# core.net
KiCad netlist of a schematic drawn in EAGLE
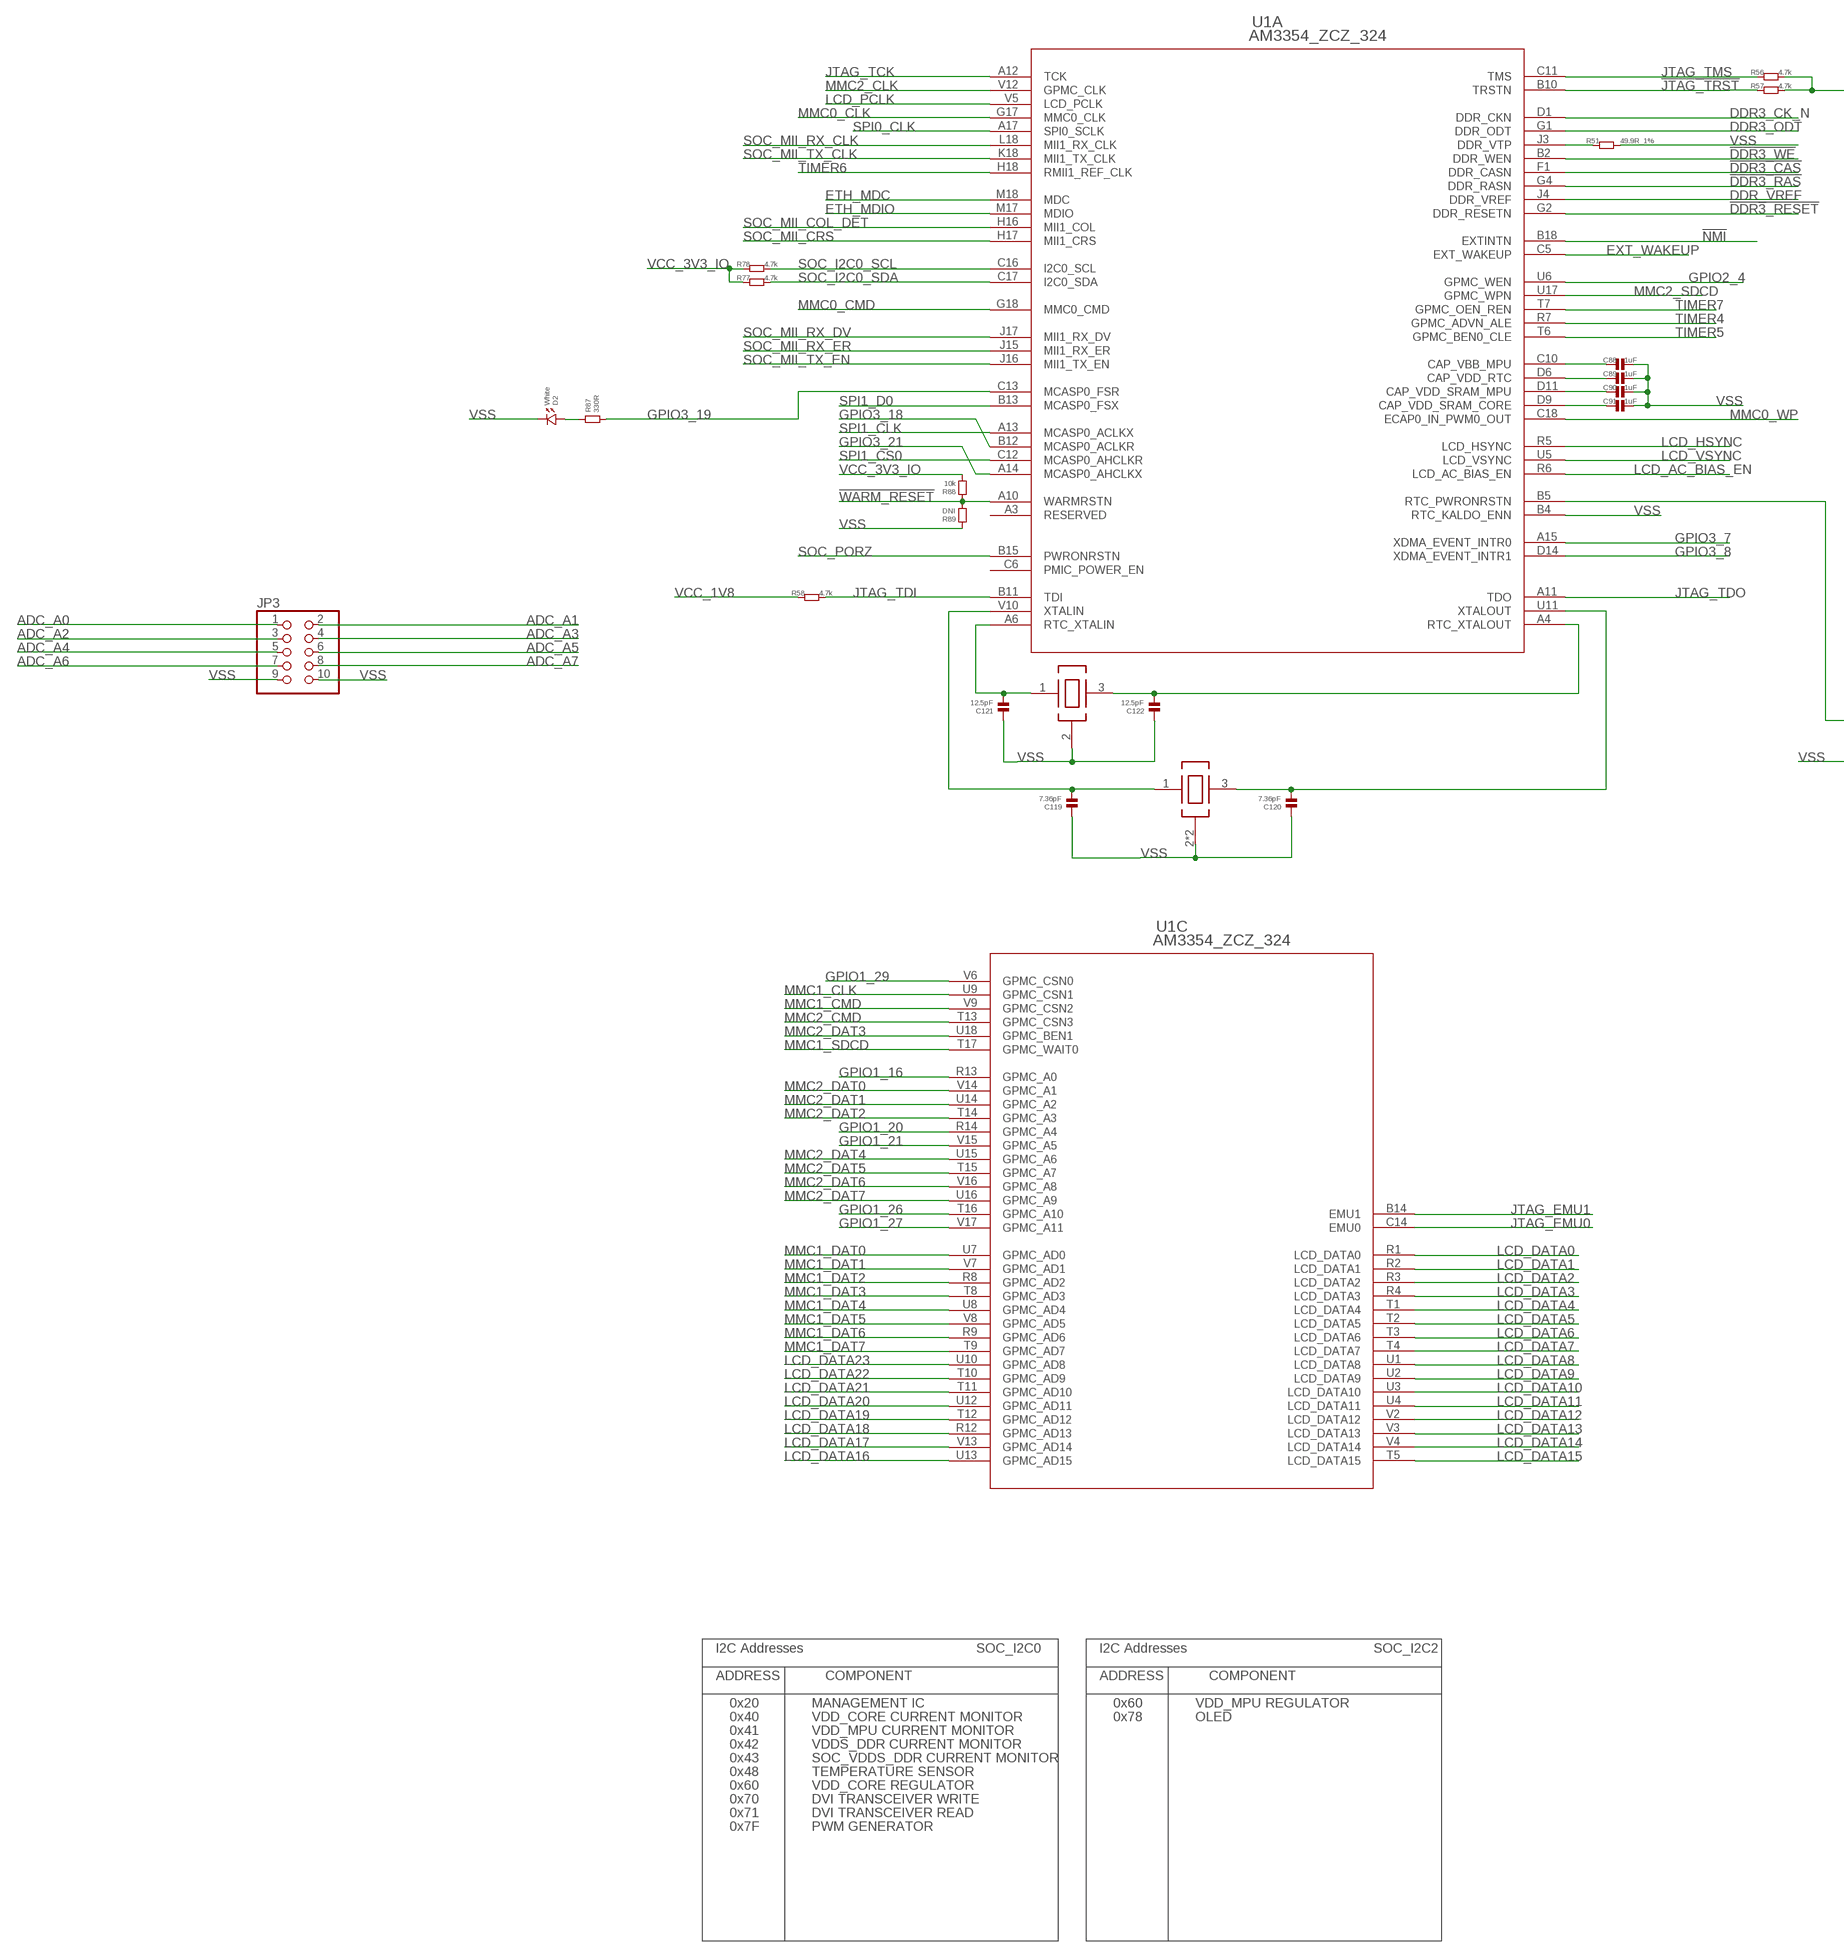
[diagram p0: schematic, sheet 1, part 1 of 2]
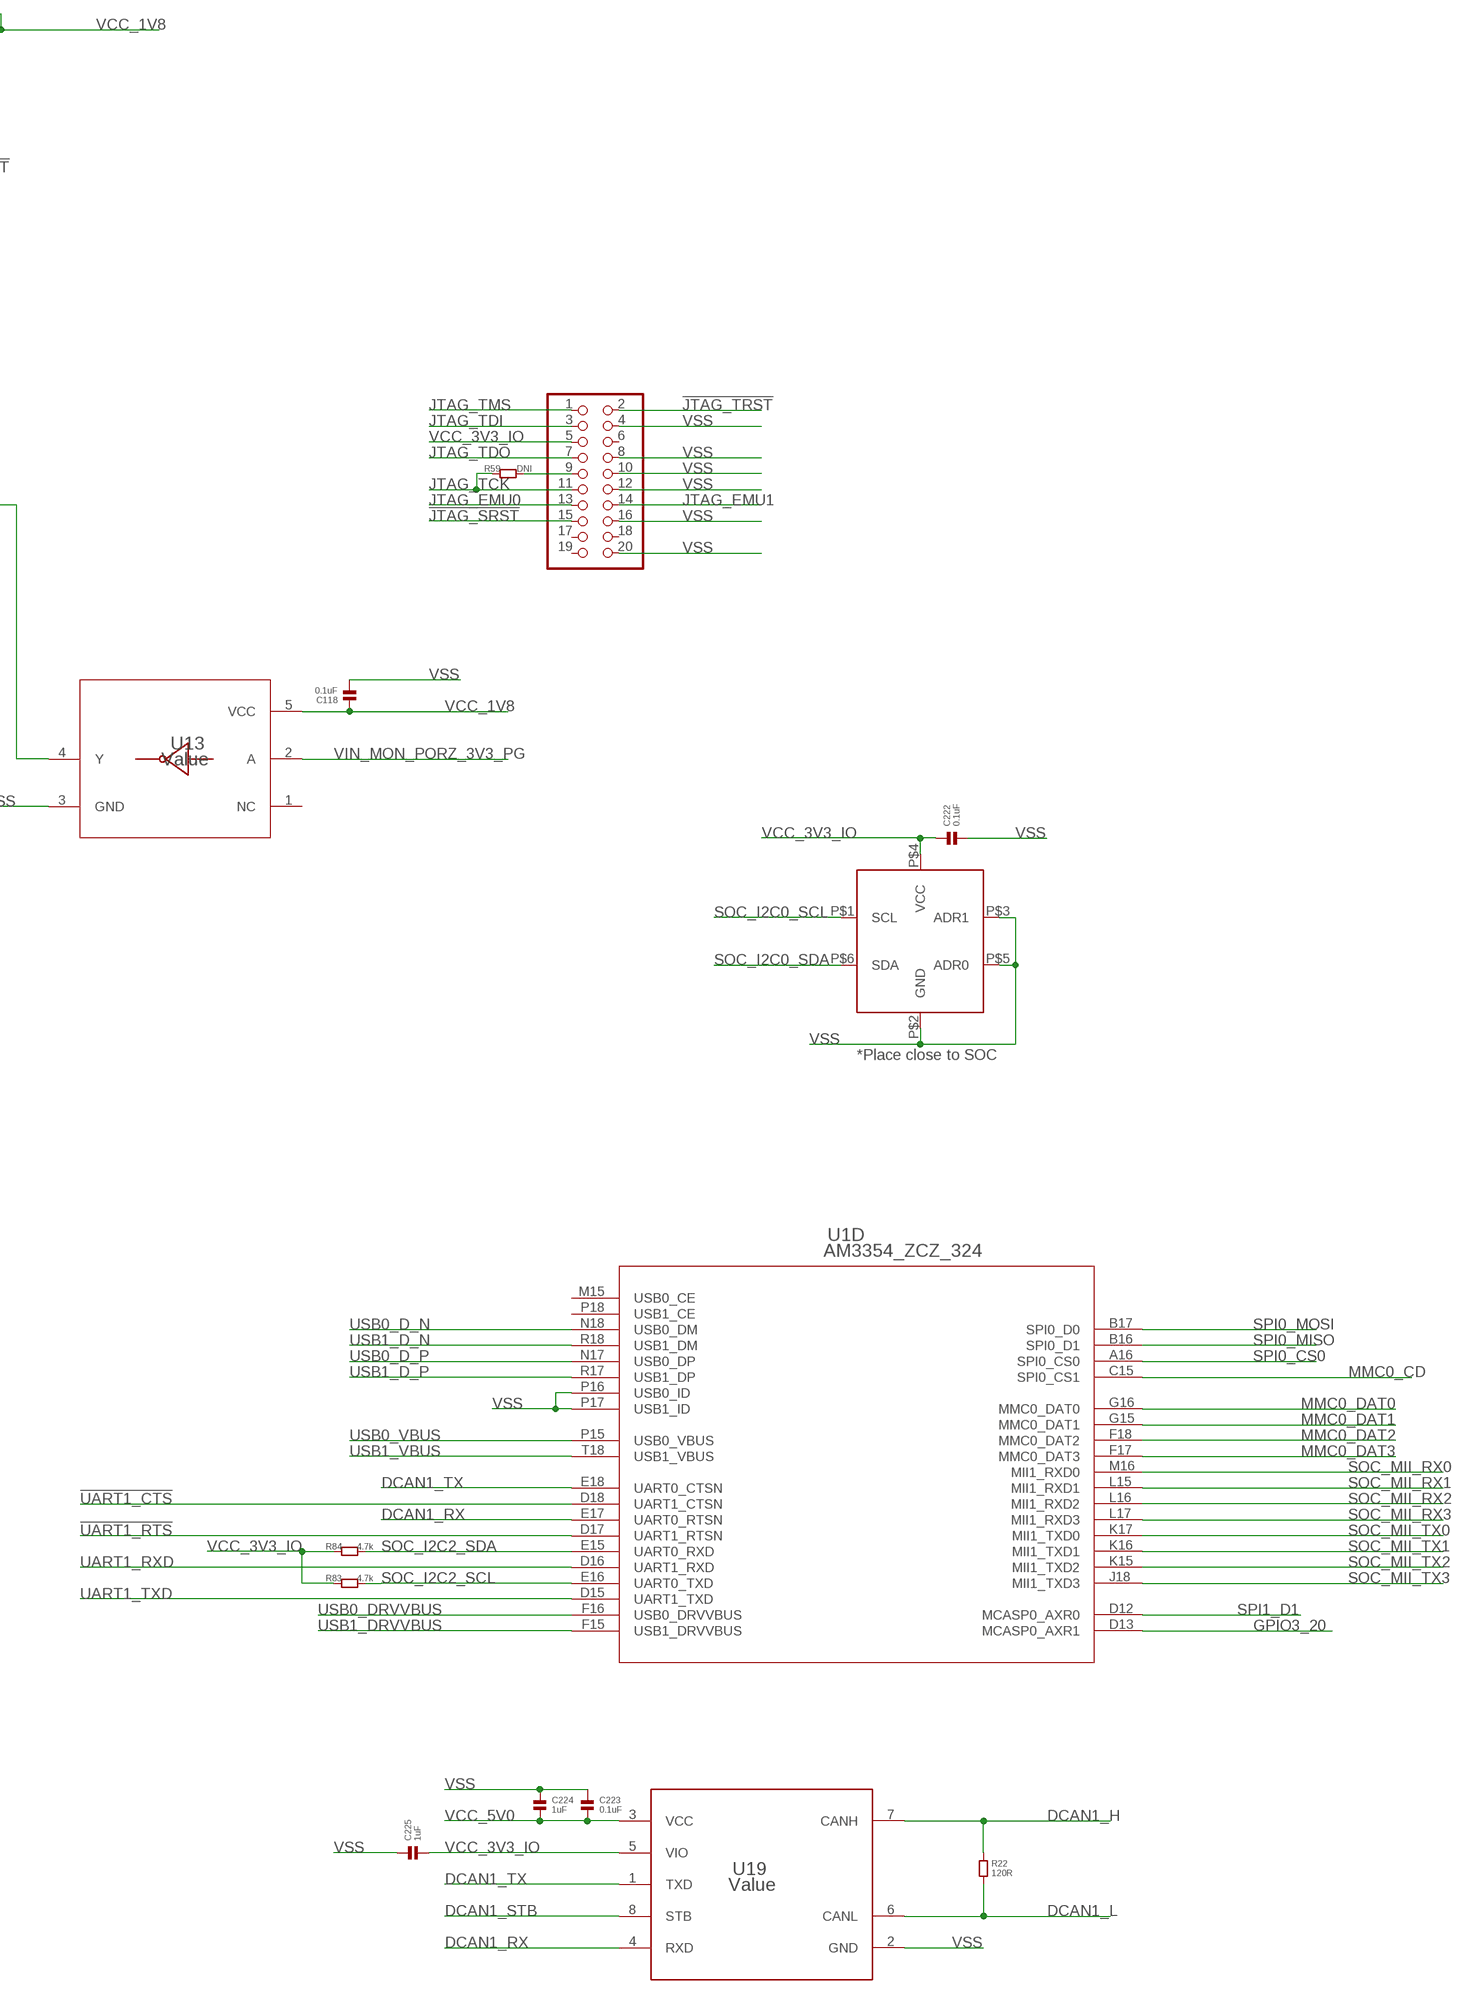
[diagram p1: schematic, sheet 1, part 2 of 2]
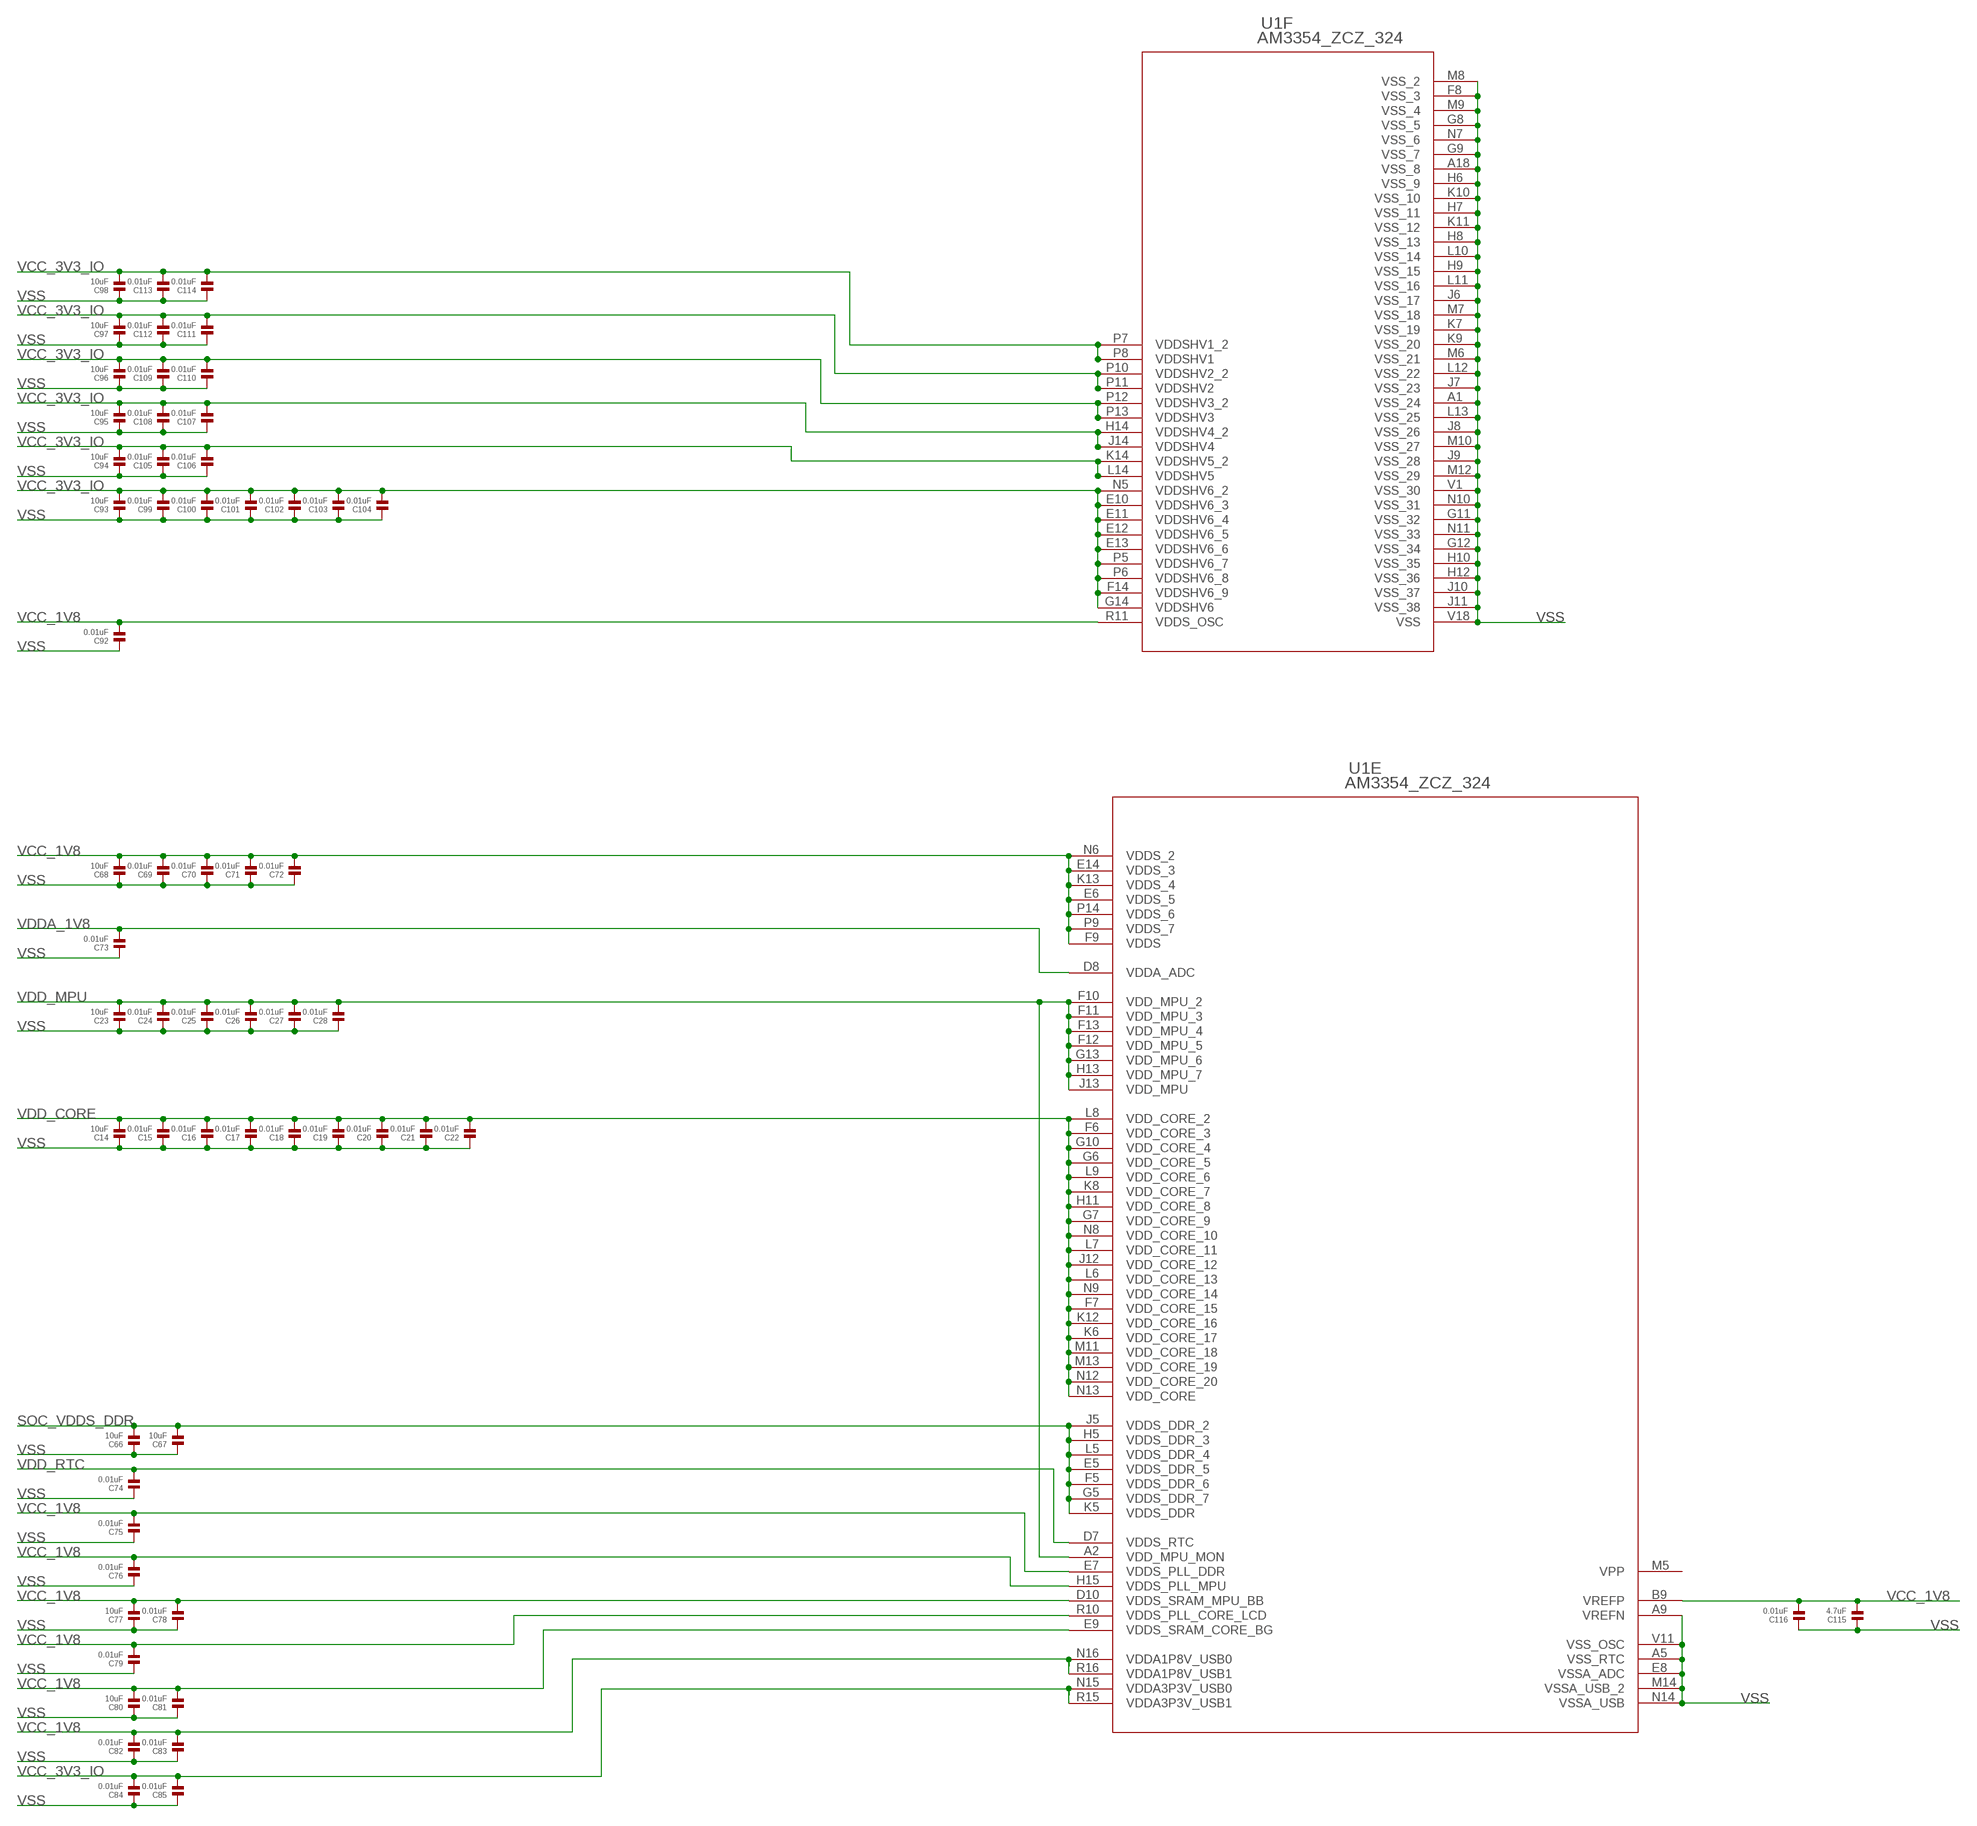
[diagram p2: schematic, sheet 2]
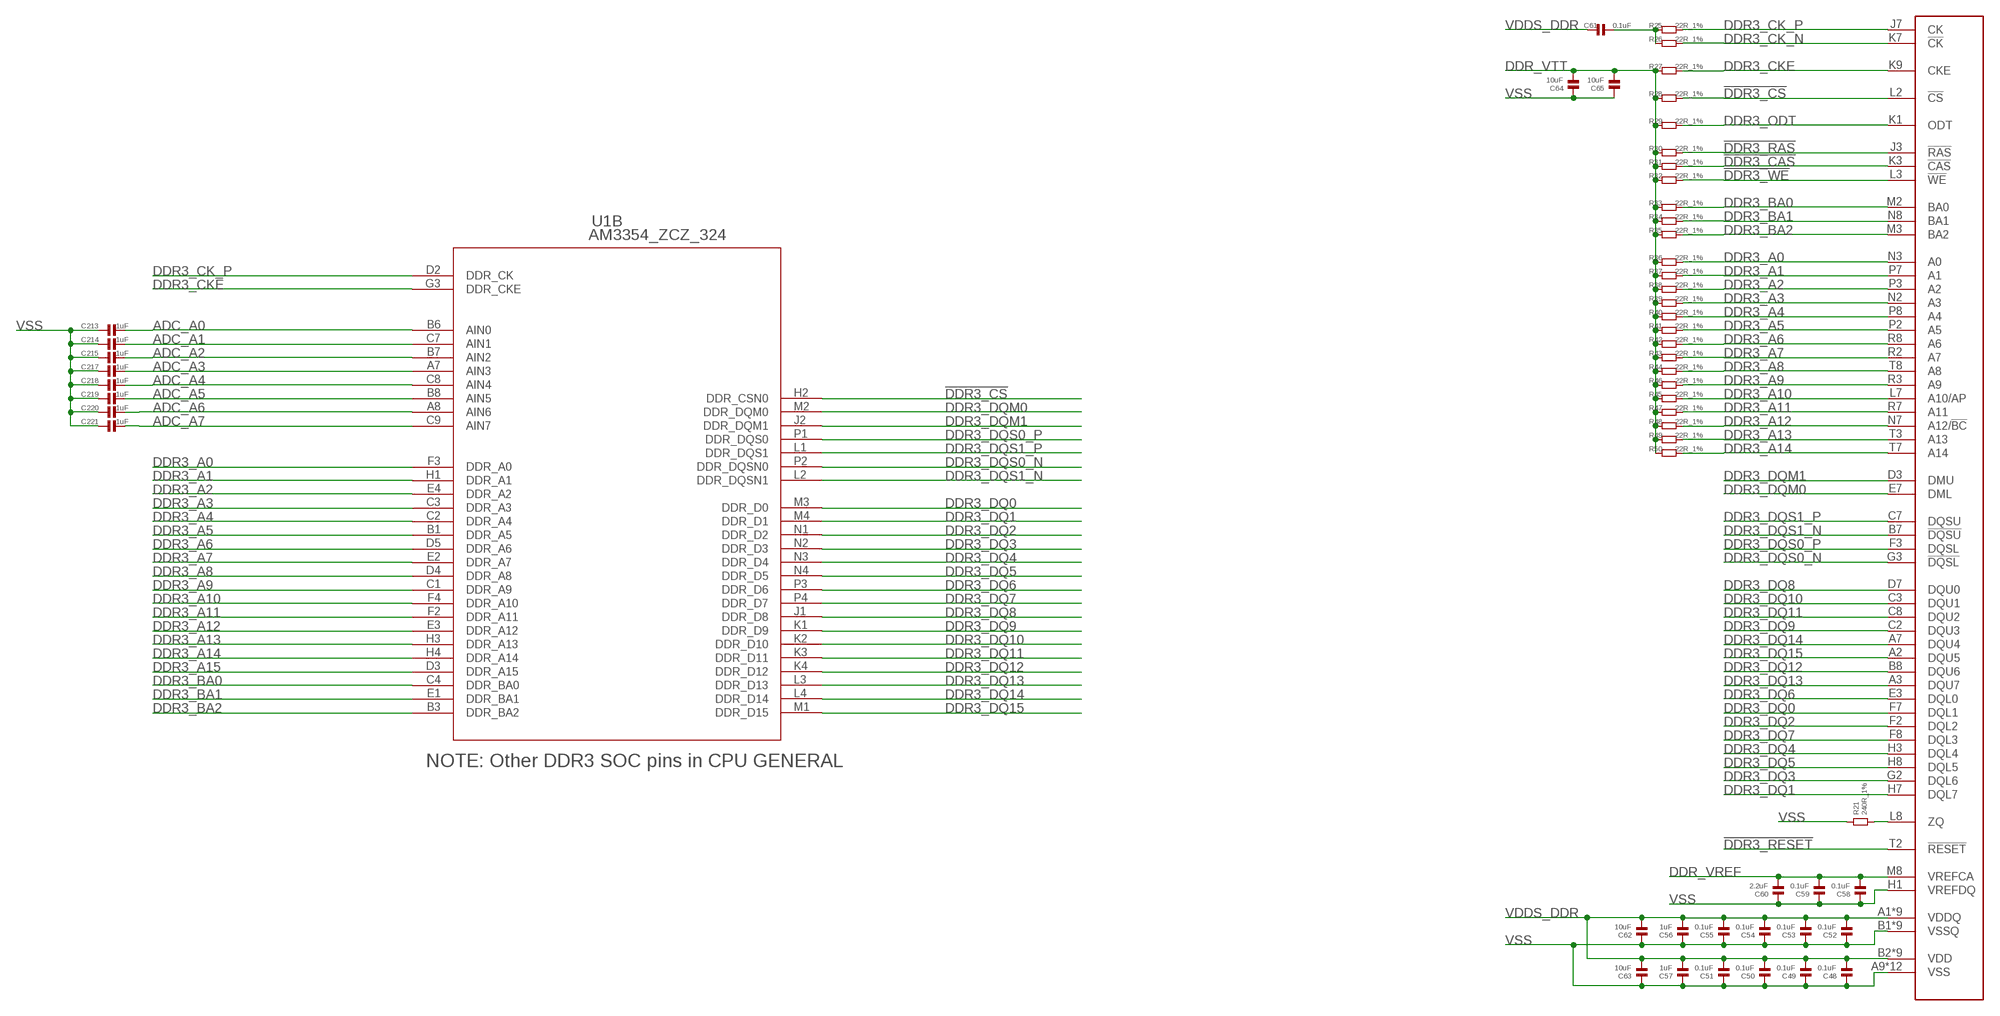
[diagram p3: schematic, sheet 3]
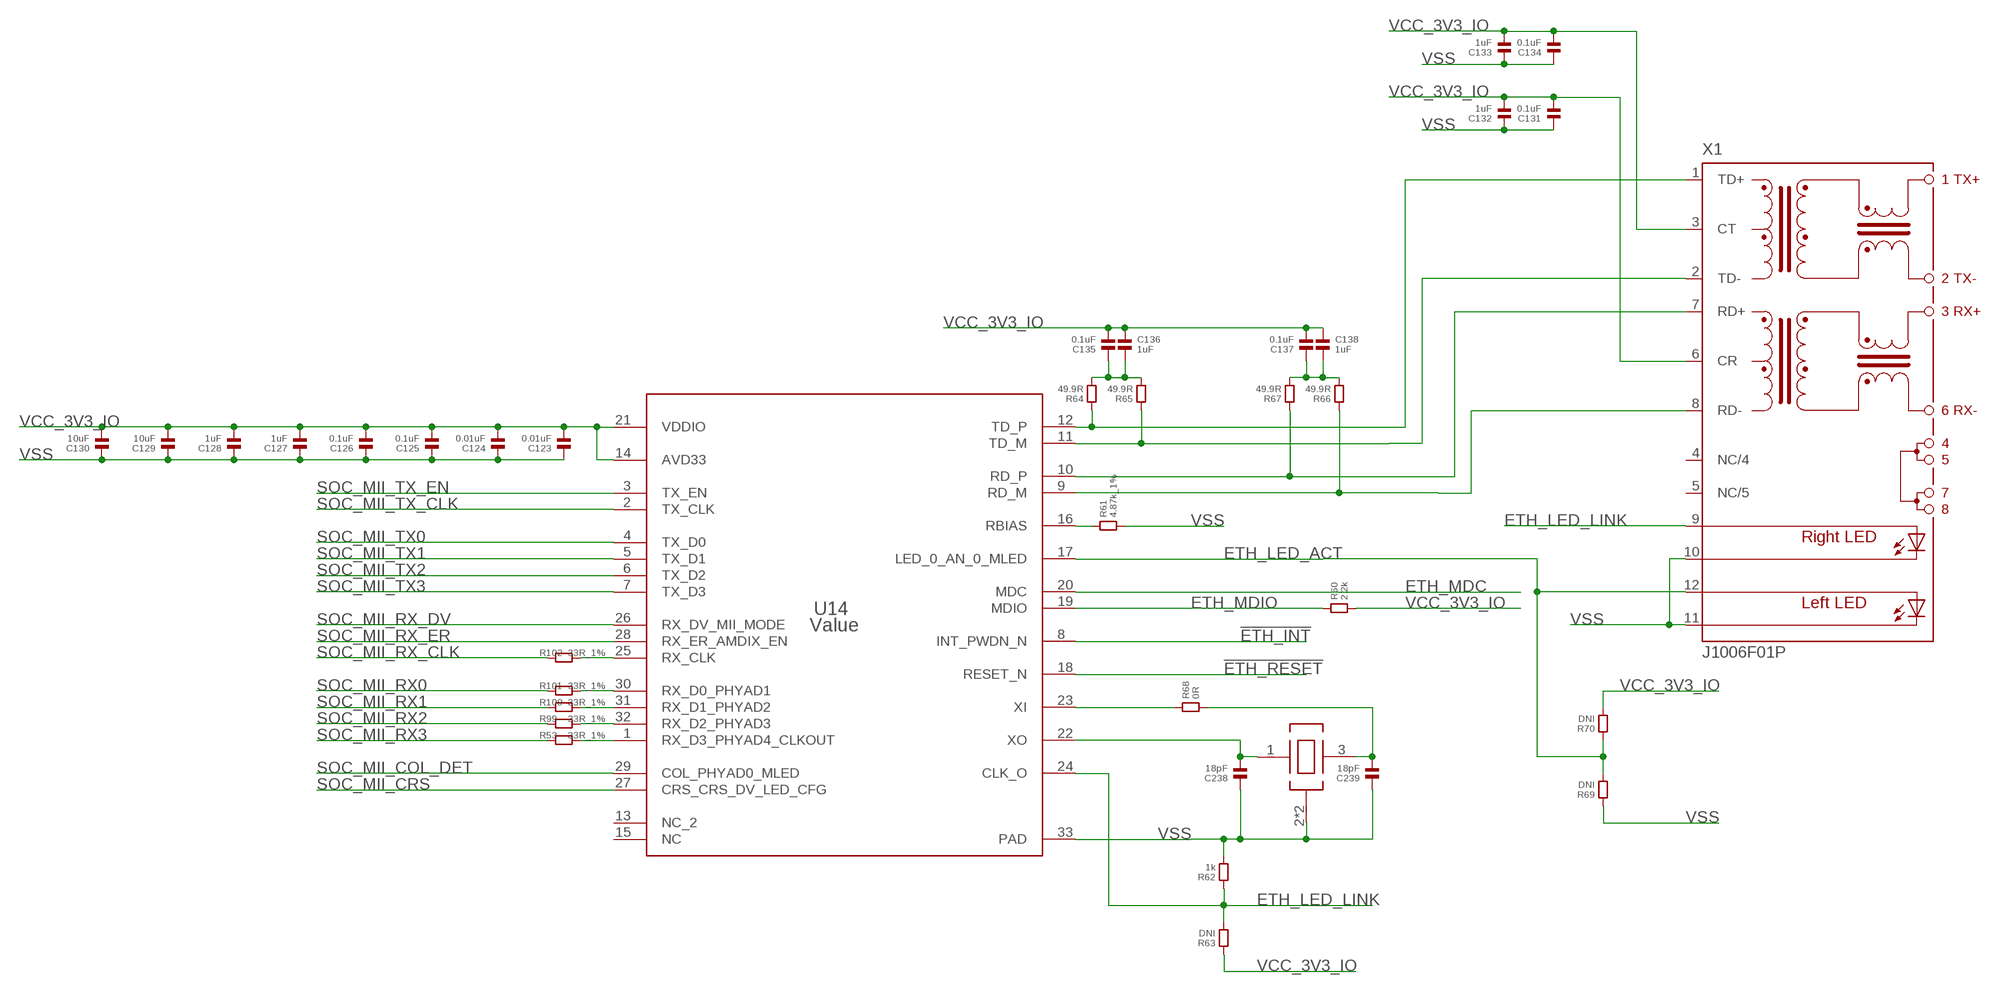
[diagram p4: schematic, sheet 4]
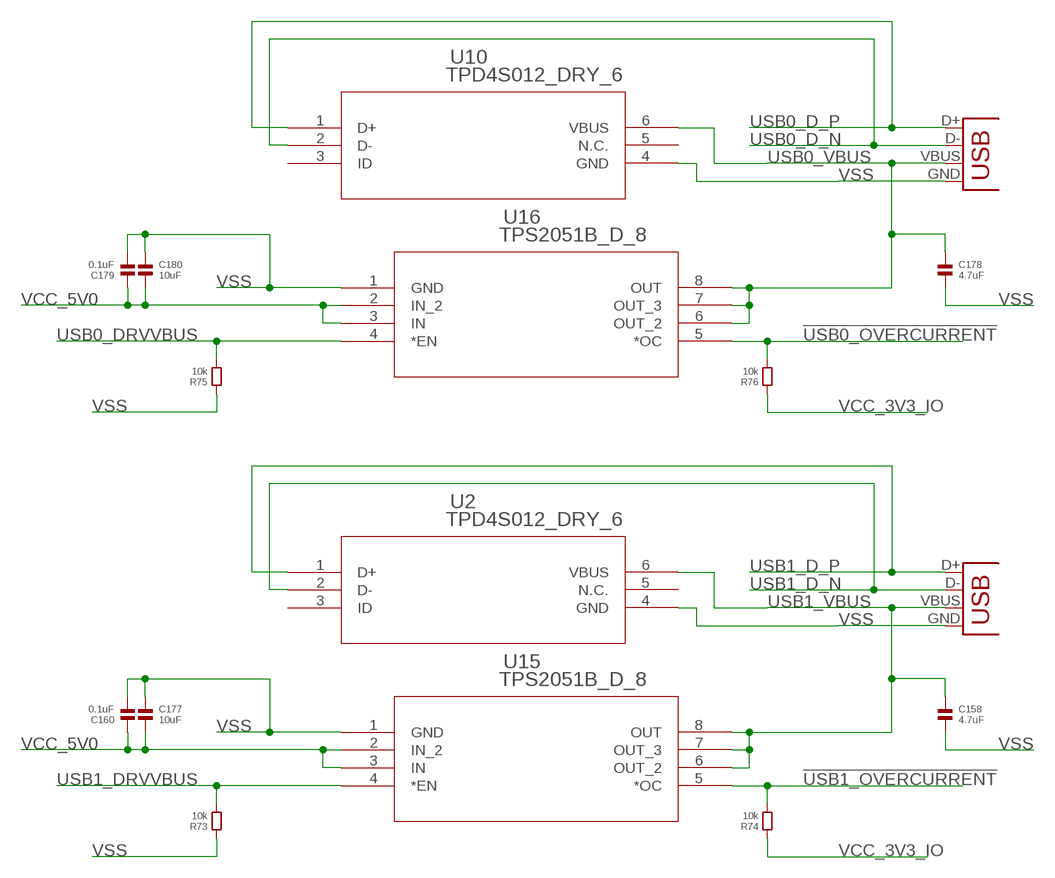
[diagram p5: schematic, sheet 5]
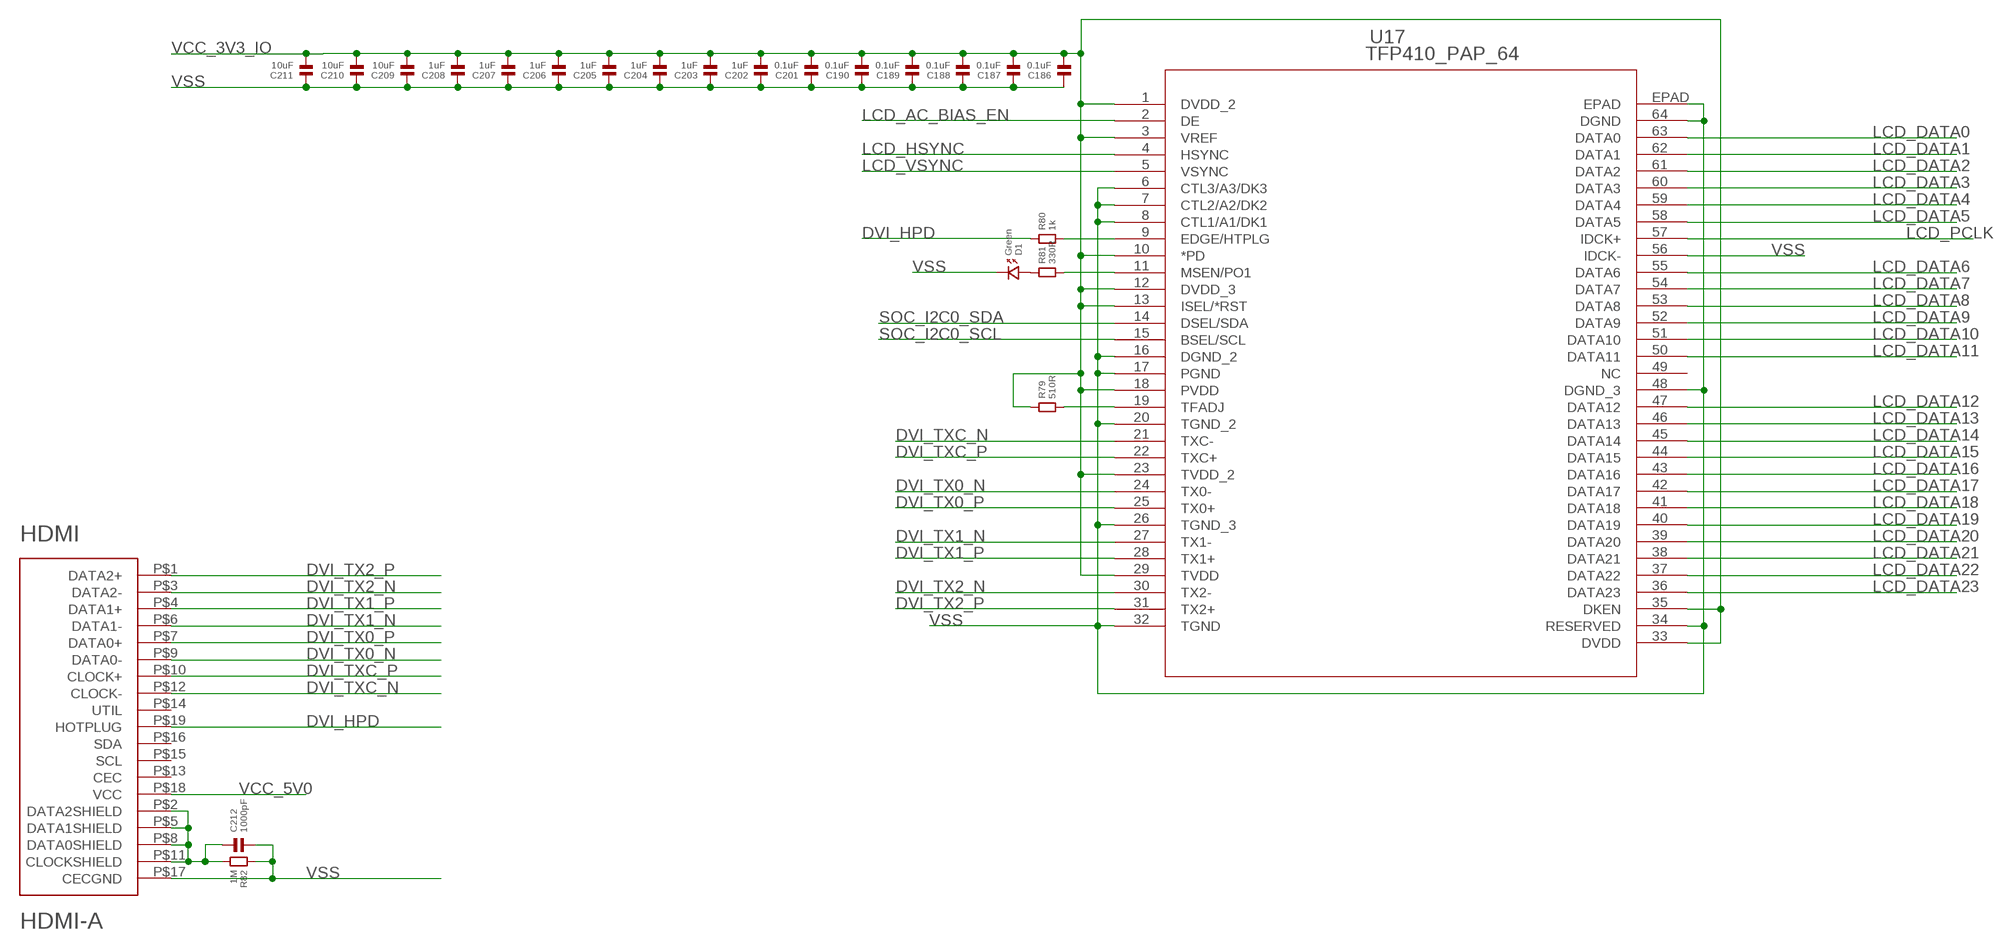
[diagram p6: schematic, sheet 6]
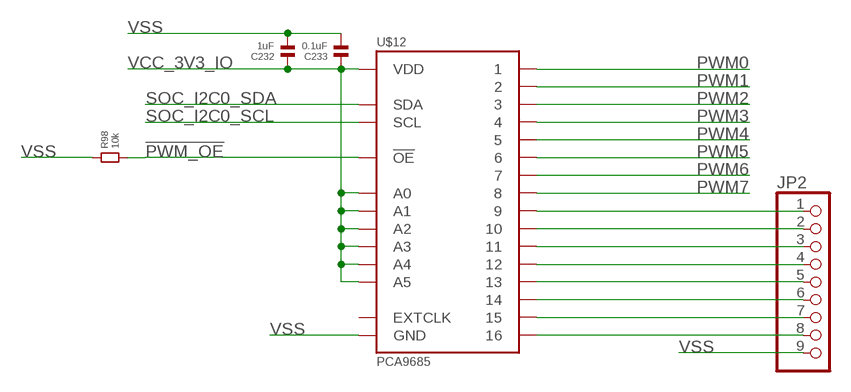
[diagram p7: schematic, sheet 7]
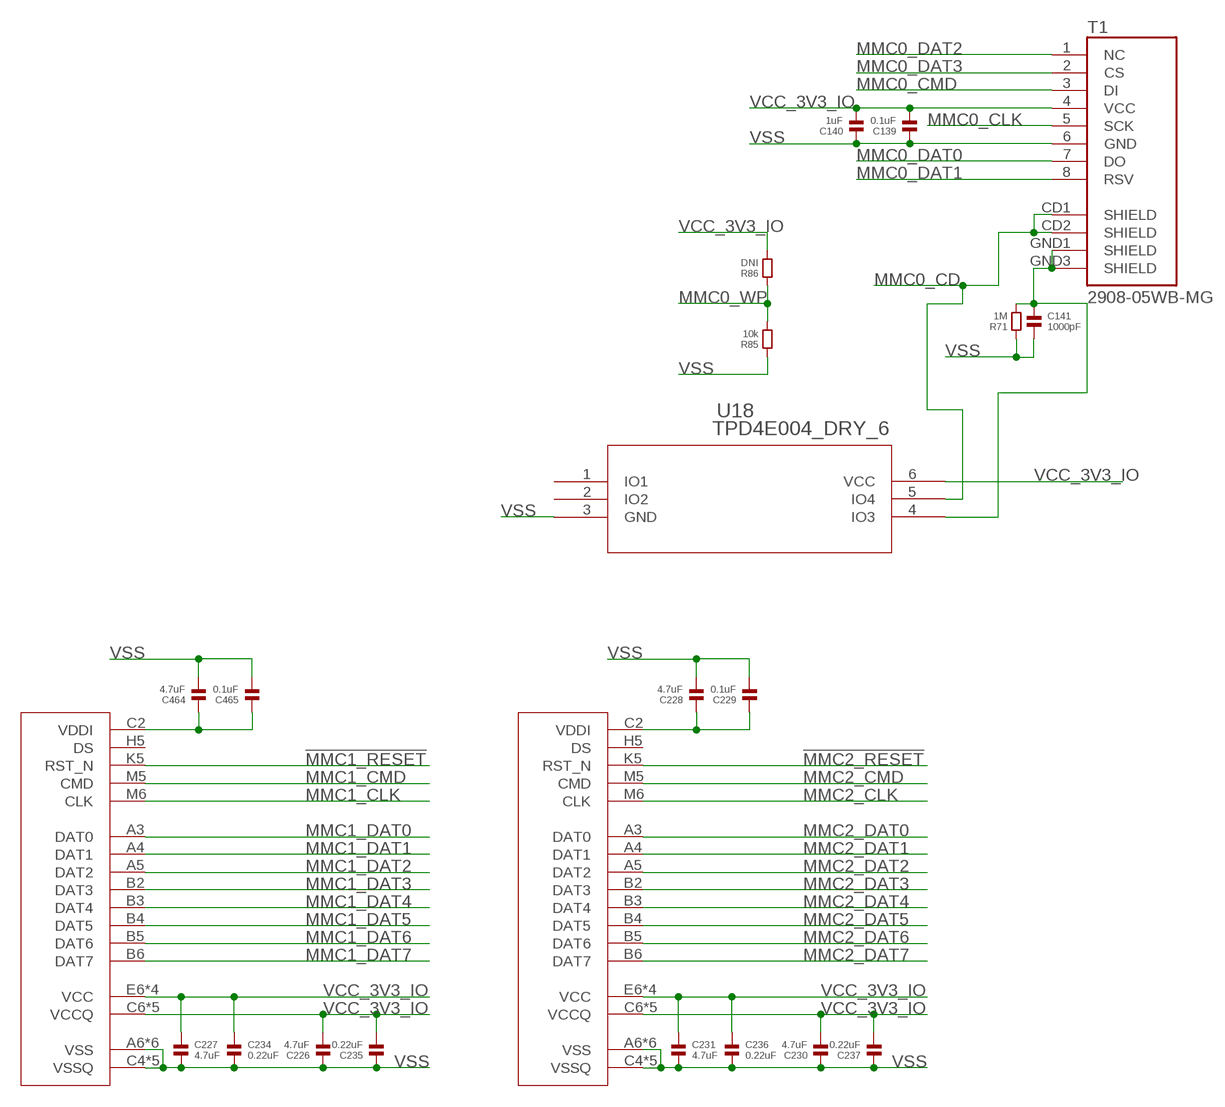
[diagram p8: schematic, sheet 8]
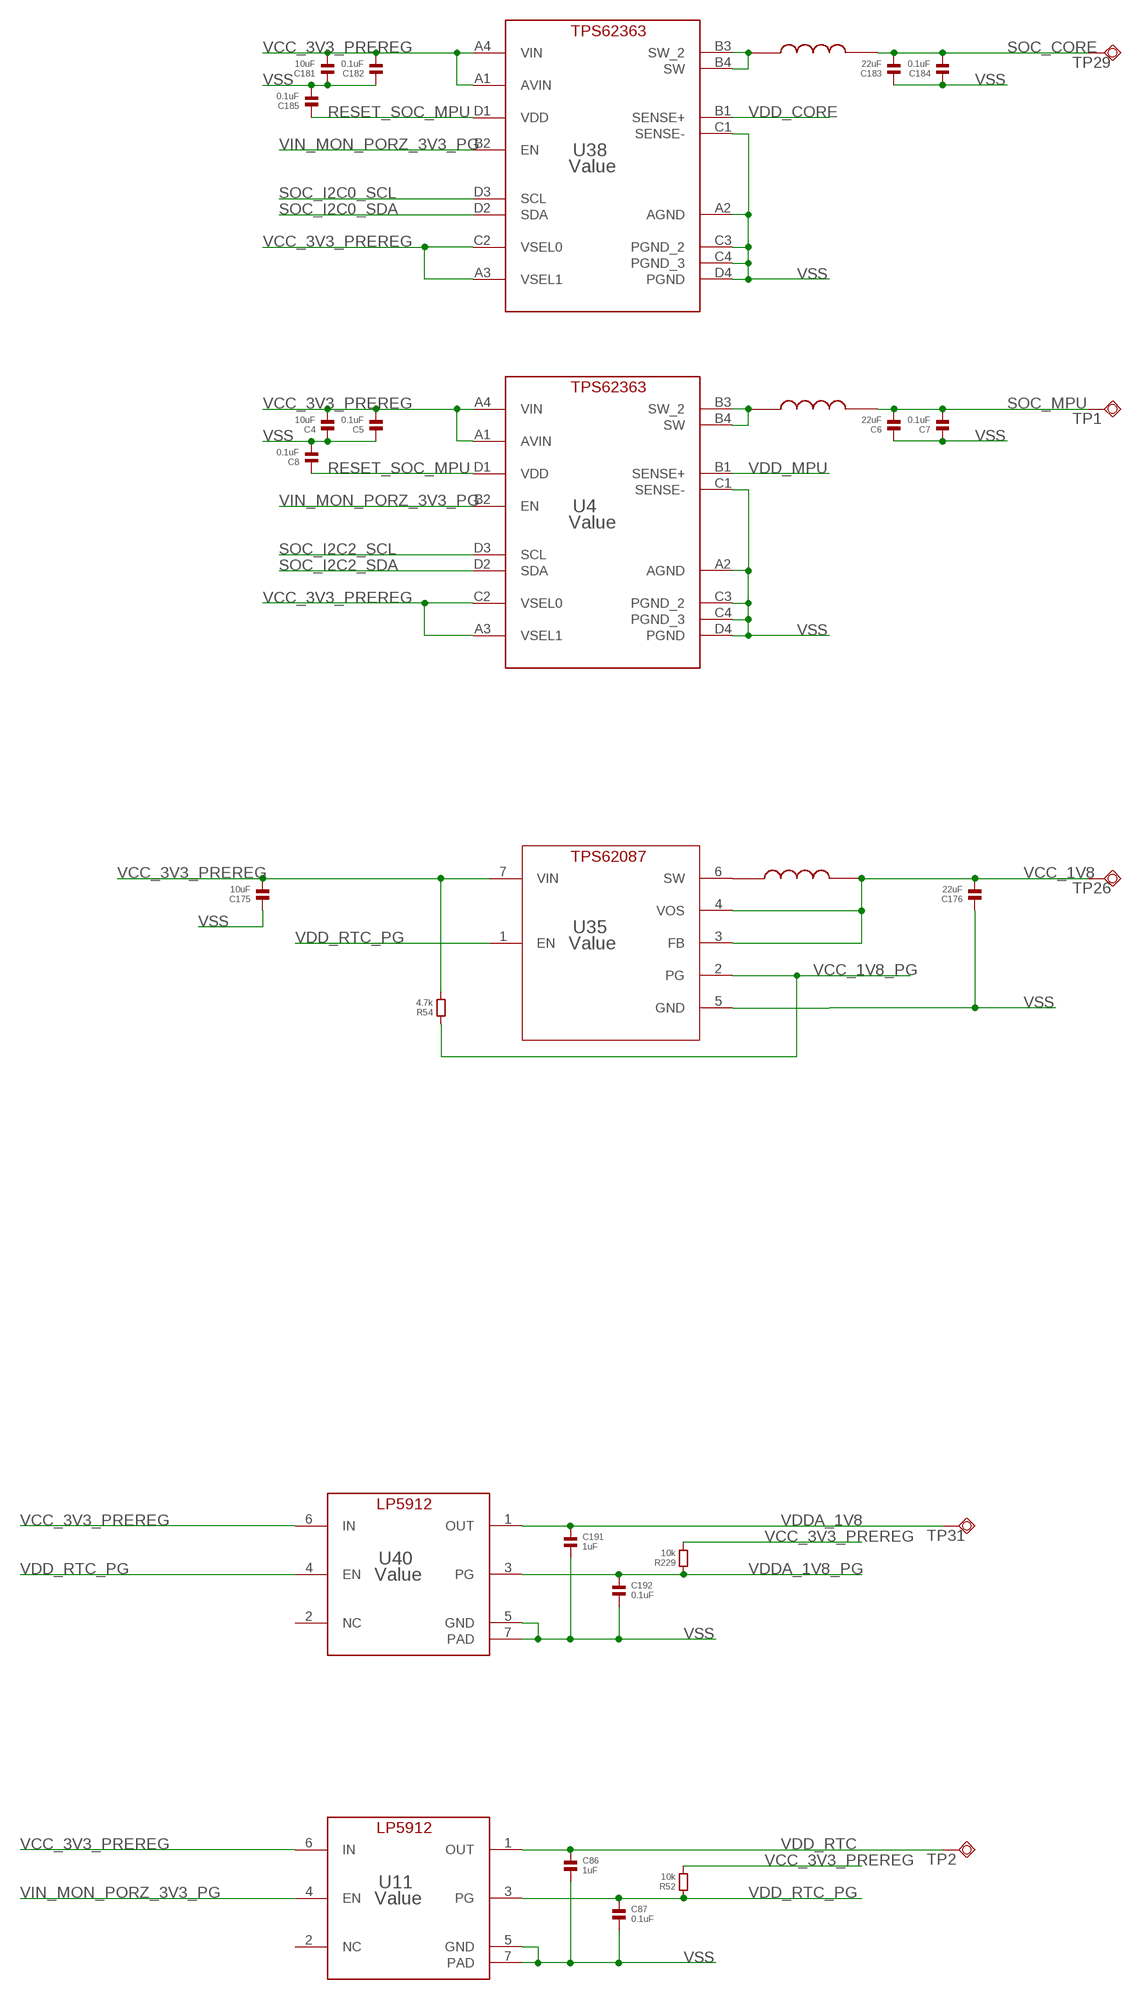
[diagram p9: schematic, sheet 9, part 1 of 2]
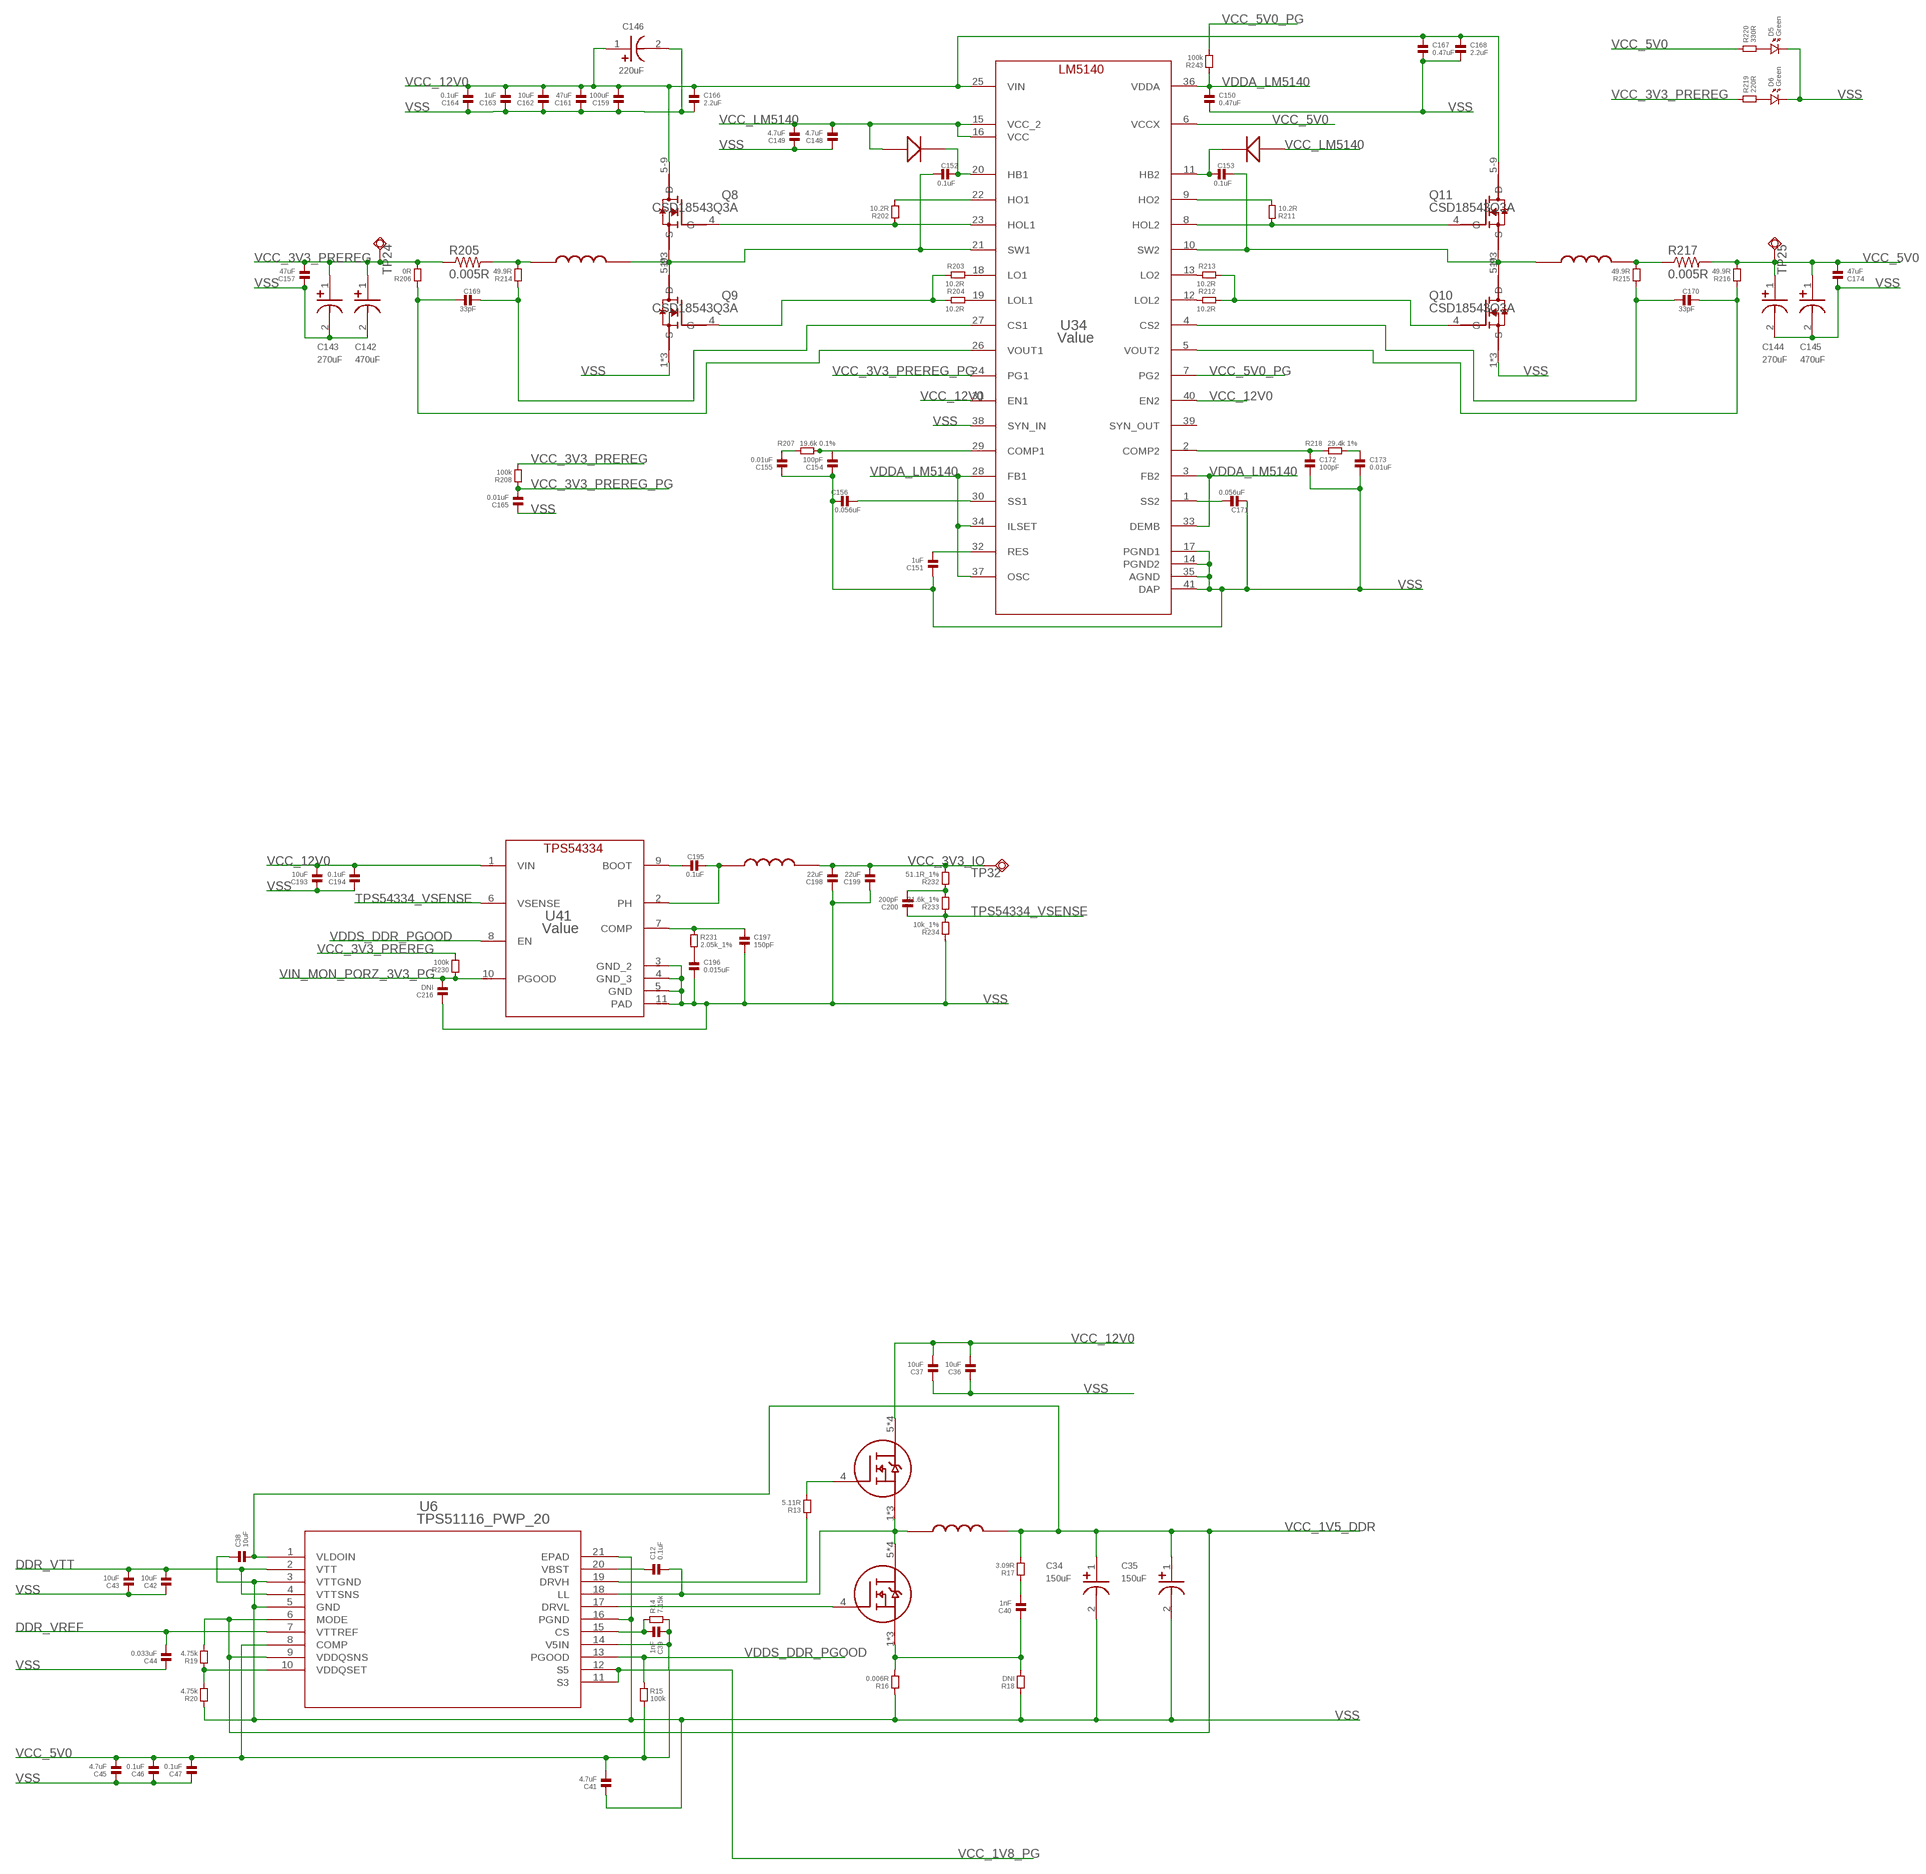
[diagram p10: schematic, sheet 9, part 2 of 2]
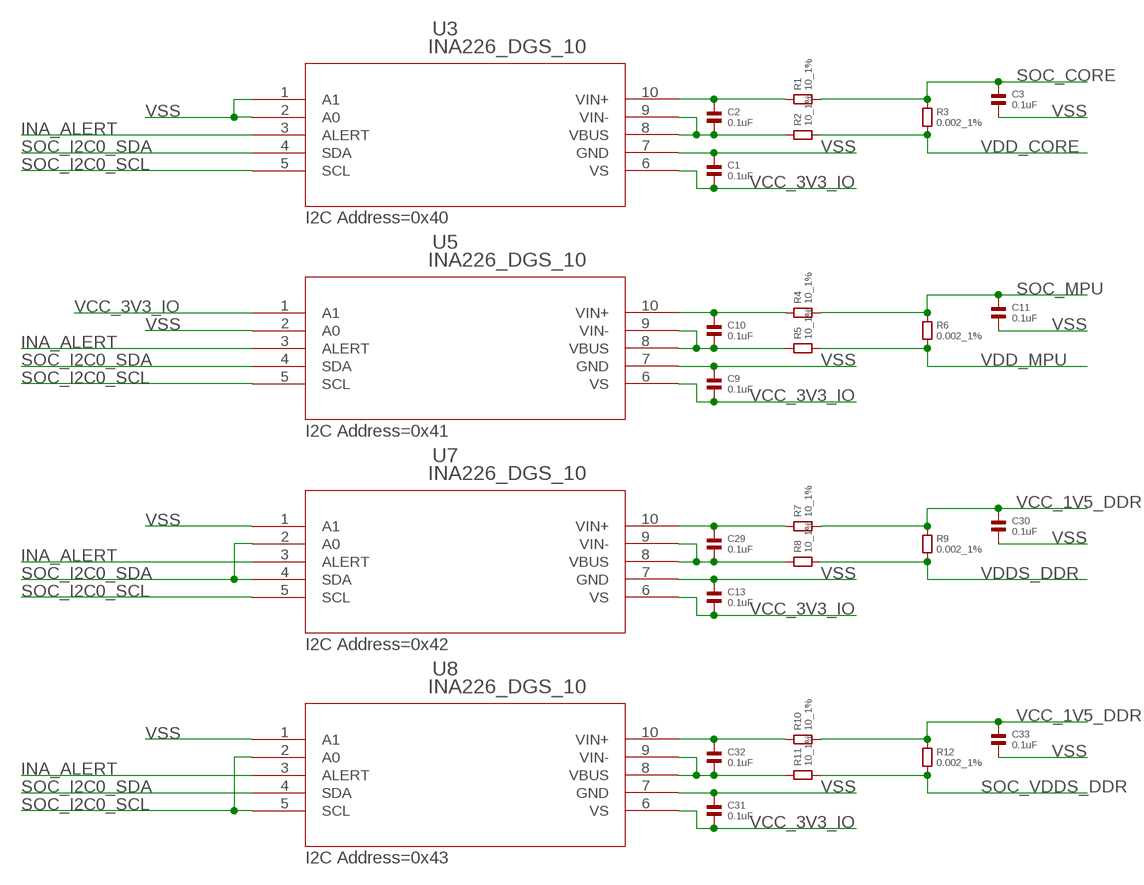
[diagram p11: schematic, sheet 10]
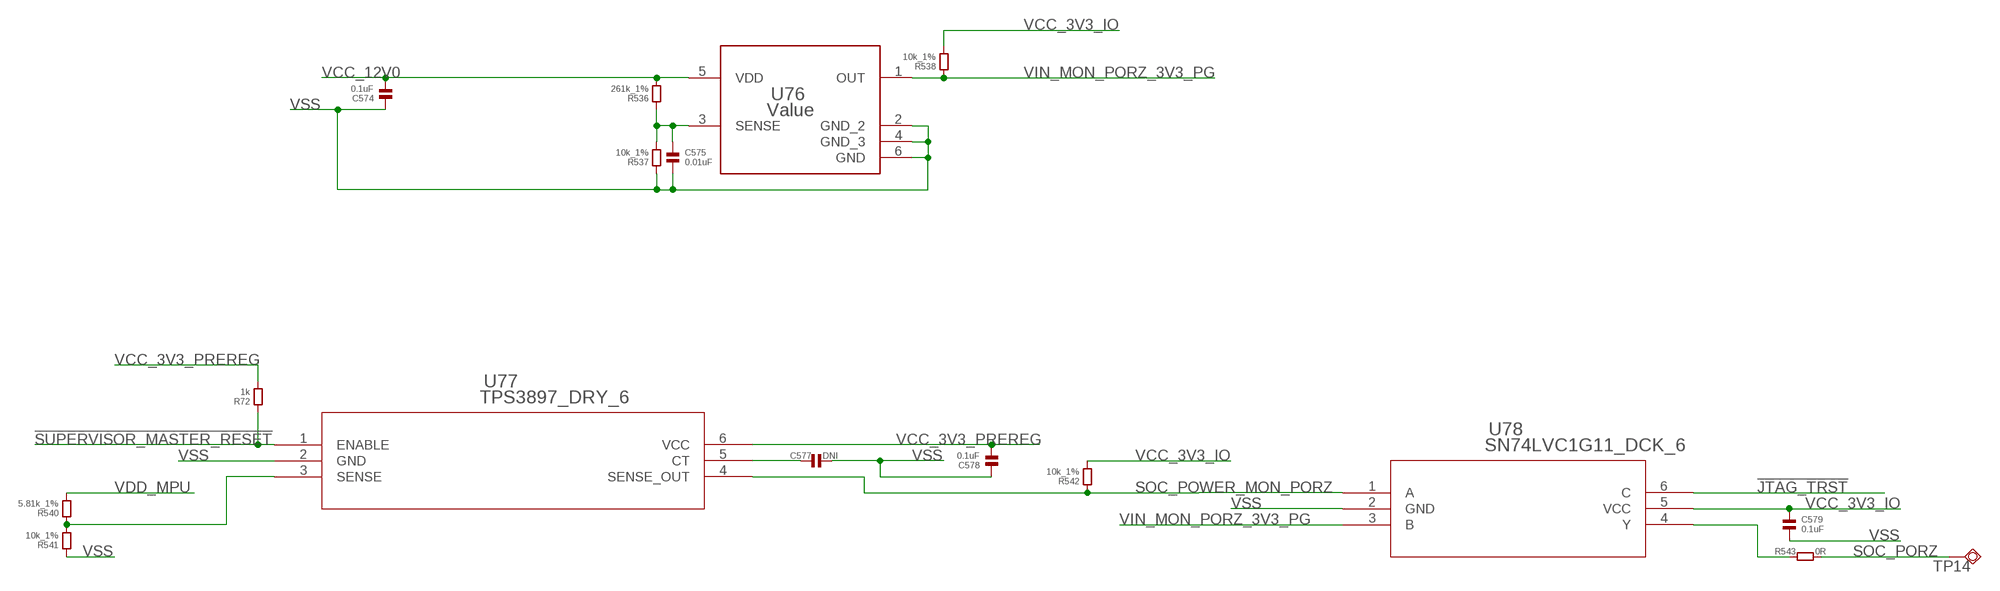
[diagram p12: schematic, sheet 11]
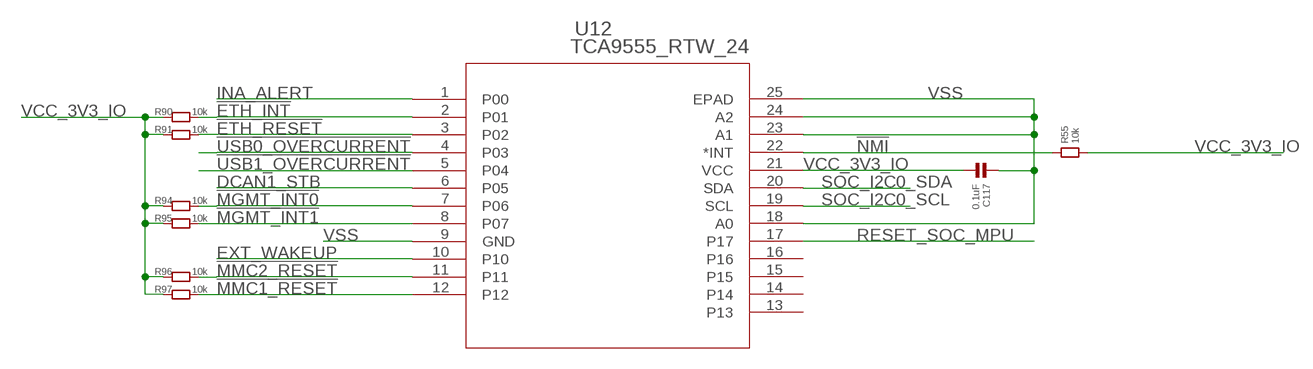
[diagram p13: schematic, sheet 12]
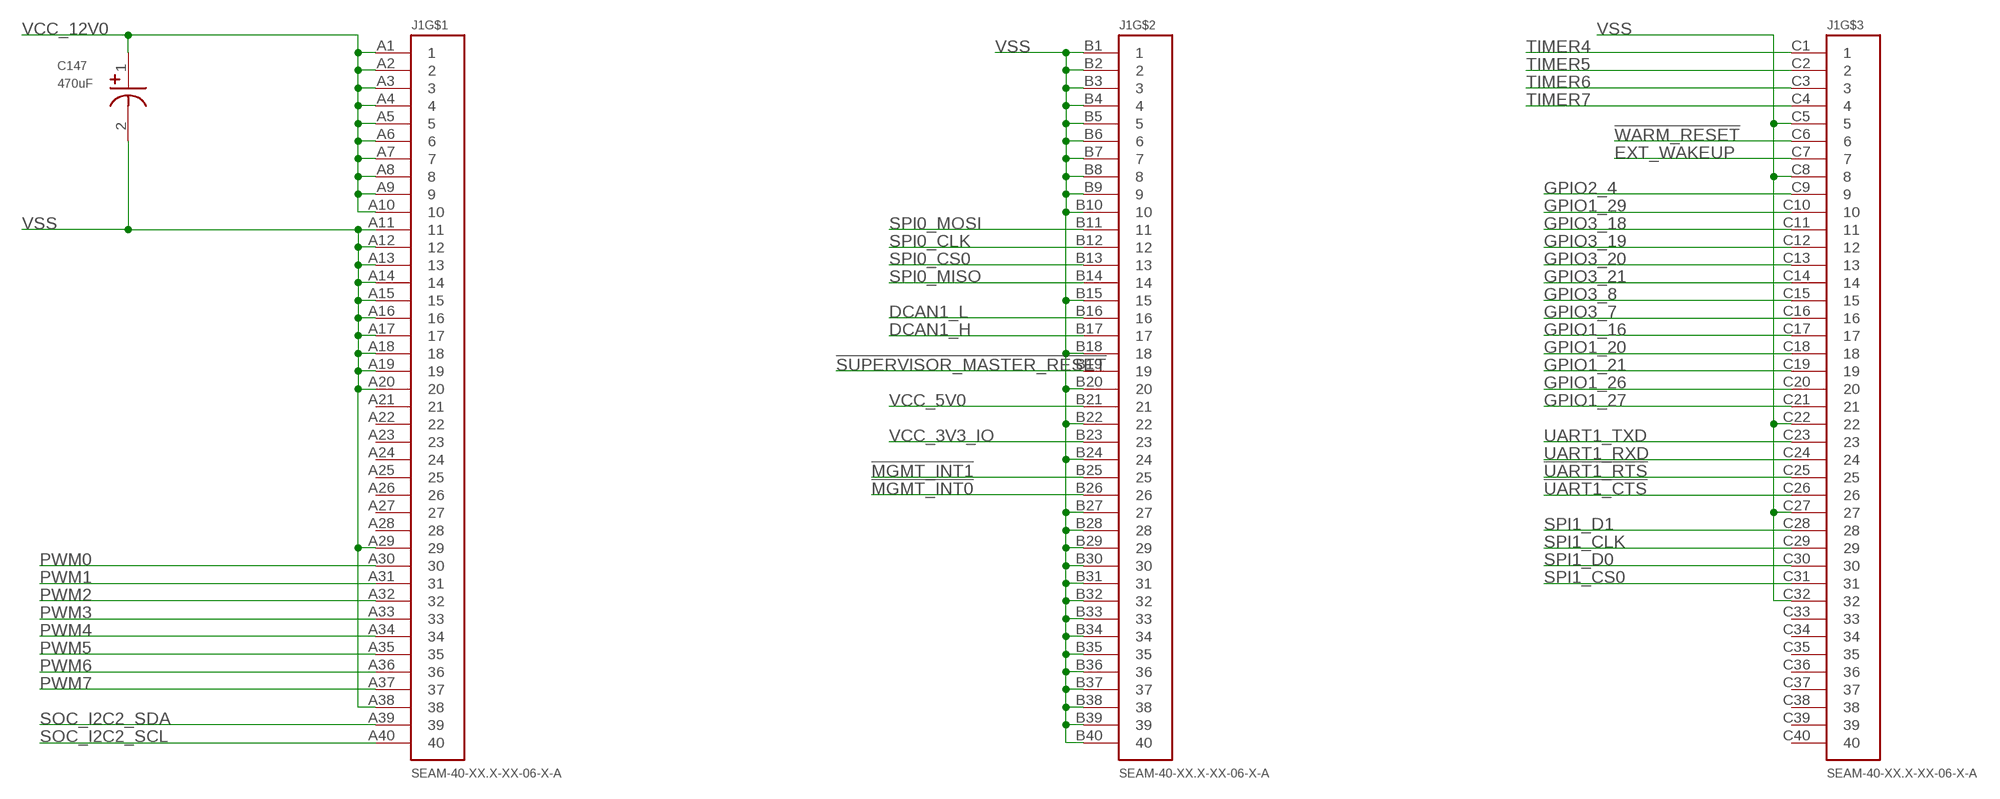
[diagram p14: schematic, sheet 13, part 1 of 2]
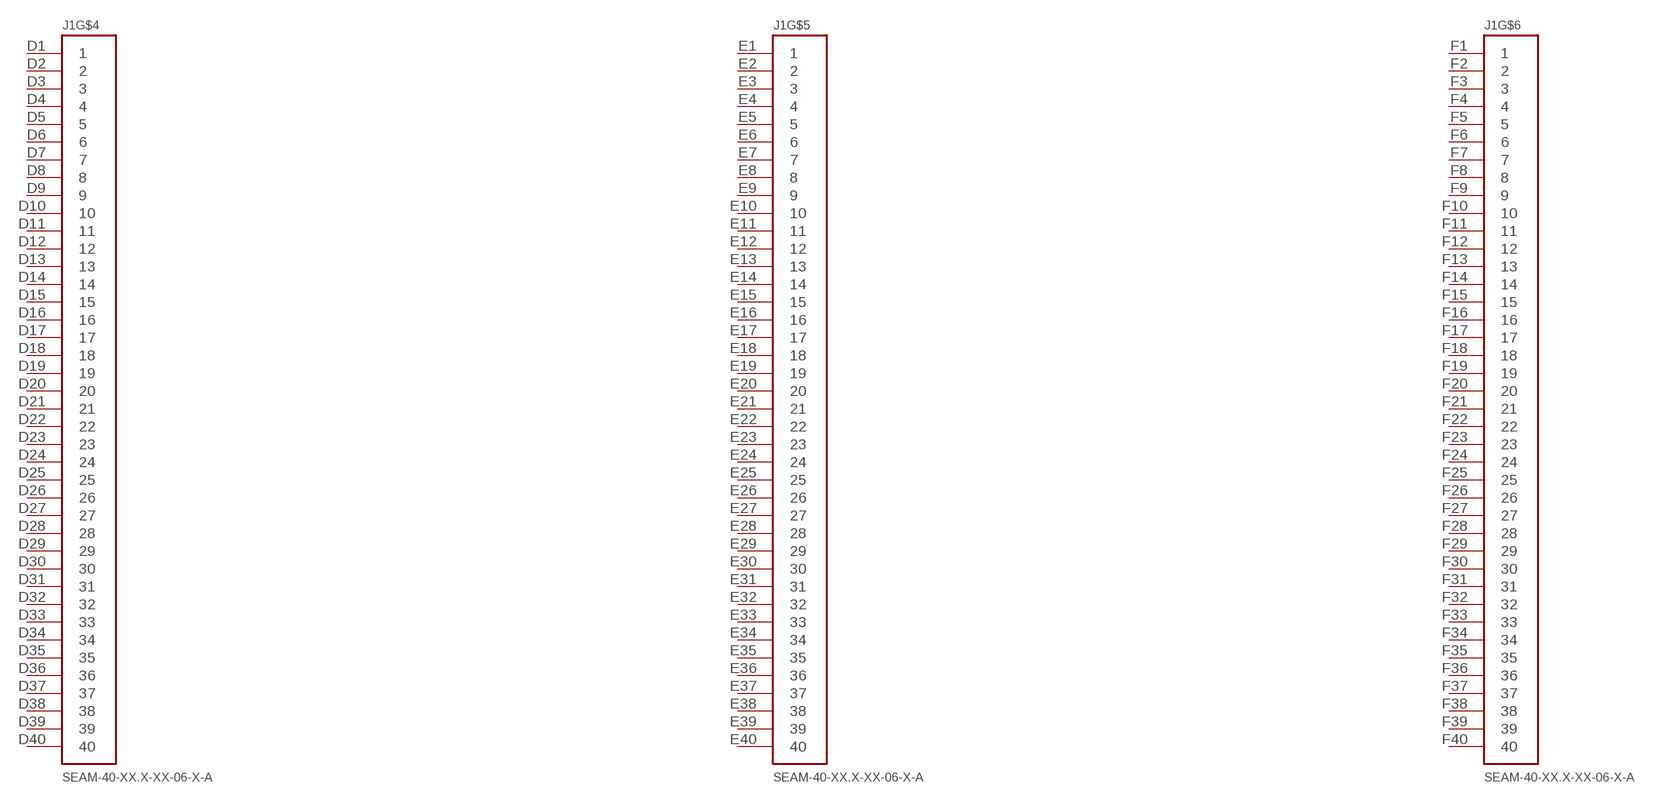
[diagram p15: schematic, sheet 13, part 2 of 2]

(export (version "E")
  (design (tool "Eeschema 10.0.6"))
  (components
    (comp (ref "C14")
      (value "10uF")
      (footprint "eagle-import:0402")
      (libsource (lib "eagle-import") (part "CAPACITOR.0402"))
    )
    (comp (ref "C15")
      (value "0.01uF")
      (footprint "eagle-import:0201")
      (libsource (lib "eagle-import") (part "CAPACITOR.0201"))
    )
    (comp (ref "C16")
      (value "0.01uF")
      (footprint "eagle-import:0201")
      (libsource (lib "eagle-import") (part "CAPACITOR.0201"))
    )
    (comp (ref "C17")
      (value "0.01uF")
      (footprint "eagle-import:0201")
      (libsource (lib "eagle-import") (part "CAPACITOR.0201"))
    )
    (comp (ref "C18")
      (value "0.01uF")
      (footprint "eagle-import:0201")
      (libsource (lib "eagle-import") (part "CAPACITOR.0201"))
    )
    (comp (ref "C19")
      (value "0.01uF")
      (footprint "eagle-import:0201")
      (libsource (lib "eagle-import") (part "CAPACITOR.0201"))
    )
    (comp (ref "C20")
      (value "0.01uF")
      (footprint "eagle-import:0201")
      (libsource (lib "eagle-import") (part "CAPACITOR.0201"))
    )
    (comp (ref "C21")
      (value "0.01uF")
      (footprint "eagle-import:0201")
      (libsource (lib "eagle-import") (part "CAPACITOR.0201"))
    )
    (comp (ref "C22")
      (value "0.01uF")
      (footprint "eagle-import:0201")
      (libsource (lib "eagle-import") (part "CAPACITOR.0201"))
    )
    (comp (ref "C23")
      (value "10uF")
      (footprint "eagle-import:0402")
      (libsource (lib "eagle-import") (part "CAPACITOR.0402"))
    )
    (comp (ref "C24")
      (value "0.01uF")
      (footprint "eagle-import:0201")
      (libsource (lib "eagle-import") (part "CAPACITOR.0201"))
    )
    (comp (ref "C25")
      (value "0.01uF")
      (footprint "eagle-import:0201")
      (libsource (lib "eagle-import") (part "CAPACITOR.0201"))
    )
    (comp (ref "C26")
      (value "0.01uF")
      (footprint "eagle-import:0201")
      (libsource (lib "eagle-import") (part "CAPACITOR.0201"))
    )
    (comp (ref "C27")
      (value "0.01uF")
      (footprint "eagle-import:0201")
      (libsource (lib "eagle-import") (part "CAPACITOR.0201"))
    )
    (comp (ref "C28")
      (value "0.01uF")
      (footprint "eagle-import:0201")
      (libsource (lib "eagle-import") (part "CAPACITOR.0201"))
    )
    (comp (ref "C66")
      (value "10uF")
      (footprint "eagle-import:0402")
      (libsource (lib "eagle-import") (part "CAPACITOR.0402"))
    )
    (comp (ref "C67")
      (value "10uF")
      (footprint "eagle-import:0402")
      (libsource (lib "eagle-import") (part "CAPACITOR.0402"))
    )
    (comp (ref "C68")
      (value "10uF")
      (footprint "eagle-import:0402")
      (libsource (lib "eagle-import") (part "CAPACITOR.0402"))
    )
    (comp (ref "C69")
      (value "0.01uF")
      (footprint "eagle-import:0201")
      (libsource (lib "eagle-import") (part "CAPACITOR.0201"))
    )
    (comp (ref "C70")
      (value "0.01uF")
      (footprint "eagle-import:0201")
      (libsource (lib "eagle-import") (part "CAPACITOR.0201"))
    )
    (comp (ref "C71")
      (value "0.01uF")
      (footprint "eagle-import:0201")
      (libsource (lib "eagle-import") (part "CAPACITOR.0201"))
    )
    (comp (ref "C72")
      (value "0.01uF")
      (footprint "eagle-import:0201")
      (libsource (lib "eagle-import") (part "CAPACITOR.0201"))
    )
    (comp (ref "C73")
      (value "0.01uF")
      (footprint "eagle-import:0201")
      (libsource (lib "eagle-import") (part "CAPACITOR.0201"))
    )
    (comp (ref "C74")
      (value "0.01uF")
      (footprint "eagle-import:0201")
      (libsource (lib "eagle-import") (part "CAPACITOR.0201"))
    )
    (comp (ref "C75")
      (value "0.01uF")
      (footprint "eagle-import:0201")
      (libsource (lib "eagle-import") (part "CAPACITOR.0201"))
    )
    (comp (ref "C76")
      (value "0.01uF")
      (footprint "eagle-import:0201")
      (libsource (lib "eagle-import") (part "CAPACITOR.0201"))
    )
    (comp (ref "C77")
      (value "10uF")
      (footprint "eagle-import:0402")
      (libsource (lib "eagle-import") (part "CAPACITOR.0402"))
    )
    (comp (ref "C78")
      (value "0.01uF")
      (footprint "eagle-import:0201")
      (libsource (lib "eagle-import") (part "CAPACITOR.0201"))
    )
    (comp (ref "C79")
      (value "0.01uF")
      (footprint "eagle-import:0201")
      (libsource (lib "eagle-import") (part "CAPACITOR.0201"))
    )
    (comp (ref "C80")
      (value "10uF")
      (footprint "eagle-import:0402")
      (libsource (lib "eagle-import") (part "CAPACITOR.0402"))
    )
    (comp (ref "C81")
      (value "0.01uF")
      (footprint "eagle-import:0201")
      (libsource (lib "eagle-import") (part "CAPACITOR.0201"))
    )
    (comp (ref "C82")
      (value "0.01uF")
      (footprint "eagle-import:0201")
      (libsource (lib "eagle-import") (part "CAPACITOR.0201"))
    )
    (comp (ref "C83")
      (value "0.01uF")
      (footprint "eagle-import:0201")
      (libsource (lib "eagle-import") (part "CAPACITOR.0201"))
    )
    (comp (ref "C84")
      (value "0.01uF")
      (footprint "eagle-import:0201")
      (libsource (lib "eagle-import") (part "CAPACITOR.0201"))
    )
    (comp (ref "C85")
      (value "0.01uF")
      (footprint "eagle-import:0201")
      (libsource (lib "eagle-import") (part "CAPACITOR.0201"))
    )
    (comp (ref "C92")
      (value "0.01uF")
      (footprint "eagle-import:0201")
      (libsource (lib "eagle-import") (part "CAPACITOR.0201"))
    )
    (comp (ref "C93")
      (value "10uF")
      (footprint "eagle-import:0402")
      (libsource (lib "eagle-import") (part "CAPACITOR.0402"))
    )
    (comp (ref "C94")
      (value "10uF")
      (footprint "eagle-import:0402")
      (libsource (lib "eagle-import") (part "CAPACITOR.0402"))
    )
    (comp (ref "C95")
      (value "10uF")
      (footprint "eagle-import:0402")
      (libsource (lib "eagle-import") (part "CAPACITOR.0402"))
    )
    (comp (ref "C96")
      (value "10uF")
      (footprint "eagle-import:0402")
      (libsource (lib "eagle-import") (part "CAPACITOR.0402"))
    )
    (comp (ref "C97")
      (value "10uF")
      (footprint "eagle-import:0402")
      (libsource (lib "eagle-import") (part "CAPACITOR.0402"))
    )
    (comp (ref "C98")
      (value "10uF")
      (footprint "eagle-import:0402")
      (libsource (lib "eagle-import") (part "CAPACITOR.0402"))
    )
    (comp (ref "C99")
      (value "0.01uF")
      (footprint "eagle-import:0201")
      (libsource (lib "eagle-import") (part "CAPACITOR.0201"))
    )
    (comp (ref "C100")
      (value "0.01uF")
      (footprint "eagle-import:0201")
      (libsource (lib "eagle-import") (part "CAPACITOR.0201"))
    )
    (comp (ref "C101")
      (value "0.01uF")
      (footprint "eagle-import:0201")
      (libsource (lib "eagle-import") (part "CAPACITOR.0201"))
    )
    (comp (ref "C102")
      (value "0.01uF")
      (footprint "eagle-import:0201")
      (libsource (lib "eagle-import") (part "CAPACITOR.0201"))
    )
    (comp (ref "C103")
      (value "0.01uF")
      (footprint "eagle-import:0201")
      (libsource (lib "eagle-import") (part "CAPACITOR.0201"))
    )
    (comp (ref "C104")
      (value "0.01uF")
      (footprint "eagle-import:0201")
      (libsource (lib "eagle-import") (part "CAPACITOR.0201"))
    )
    (comp (ref "C105")
      (value "0.01uF")
      (footprint "eagle-import:0201")
      (libsource (lib "eagle-import") (part "CAPACITOR.0201"))
    )
    (comp (ref "C106")
      (value "0.01uF")
      (footprint "eagle-import:0201")
      (libsource (lib "eagle-import") (part "CAPACITOR.0201"))
    )
    (comp (ref "C107")
      (value "0.01uF")
      (footprint "eagle-import:0201")
      (libsource (lib "eagle-import") (part "CAPACITOR.0201"))
    )
    (comp (ref "C108")
      (value "0.01uF")
      (footprint "eagle-import:0201")
      (libsource (lib "eagle-import") (part "CAPACITOR.0201"))
    )
    (comp (ref "C109")
      (value "0.01uF")
      (footprint "eagle-import:0201")
      (libsource (lib "eagle-import") (part "CAPACITOR.0201"))
    )
    (comp (ref "C110")
      (value "0.01uF")
      (footprint "eagle-import:0201")
      (libsource (lib "eagle-import") (part "CAPACITOR.0201"))
    )
    (comp (ref "C111")
      (value "0.01uF")
      (footprint "eagle-import:0201")
      (libsource (lib "eagle-import") (part "CAPACITOR.0201"))
    )
    (comp (ref "C112")
      (value "0.01uF")
      (footprint "eagle-import:0201")
      (libsource (lib "eagle-import") (part "CAPACITOR.0201"))
    )
    (comp (ref "C113")
      (value "0.01uF")
      (footprint "eagle-import:0201")
      (libsource (lib "eagle-import") (part "CAPACITOR.0201"))
    )
    (comp (ref "C114")
      (value "0.01uF")
      (footprint "eagle-import:0201")
      (libsource (lib "eagle-import") (part "CAPACITOR.0201"))
    )
    (comp (ref "C115")
      (value "4.7uF")
      (footprint "eagle-import:0402")
      (libsource (lib "eagle-import") (part "CAPACITOR.0402"))
    )
    (comp (ref "C116")
      (value "0.01uF")
      (footprint "eagle-import:0201")
      (libsource (lib "eagle-import") (part "CAPACITOR.0201"))
    )
    (comp (ref "U1")
      (value "AM3354_ZCZ_324")
      (footprint "eagle-import:ZCZ324")
      (fields (field (name "GENERIC_PART_NUMBER") "AM3354") (field (name "MANUFACTURER") "Texas Instruments"))
      (libsource (lib "eagle-import") (part "AM3354_ZCZ_324"))
    )
    (comp (ref "C88")
      (value "1uF")
      (footprint "eagle-import:0201")
      (libsource (lib "eagle-import") (part "CAPACITOR.0201"))
    )
    (comp (ref "C89")
      (value "1uF")
      (footprint "eagle-import:0201")
      (libsource (lib "eagle-import") (part "CAPACITOR.0201"))
    )
    (comp (ref "C90")
      (value "1uF")
      (footprint "eagle-import:0201")
      (libsource (lib "eagle-import") (part "CAPACITOR.0201"))
    )
    (comp (ref "C91")
      (value "1uF")
      (footprint "eagle-import:0201")
      (libsource (lib "eagle-import") (part "CAPACITOR.0201"))
    )
    (comp (ref "C118")
      (value "0.1uF")
      (footprint "eagle-import:0402")
      (libsource (lib "eagle-import") (part "CAPACITOR.0402"))
    )
    (comp (ref "C119")
      (value "7.36pF")
      (footprint "eagle-import:0402")
      (libsource (lib "eagle-import") (part "CAPACITOR.0402"))
    )
    (comp (ref "C120")
      (value "7.36pF")
      (footprint "eagle-import:0402")
      (libsource (lib "eagle-import") (part "CAPACITOR.0402"))
    )
    (comp (ref "C121")
      (value "12.5pF")
      (footprint "eagle-import:0402")
      (libsource (lib "eagle-import") (part "CAPACITOR.0402"))
    )
    (comp (ref "C122")
      (value "12.5pF")
      (footprint "eagle-import:0402")
      (libsource (lib "eagle-import") (part "CAPACITOR.0402"))
    )
    (comp (ref "C222")
      (value "0.1uF")
      (footprint "eagle-import:0402")
      (libsource (lib "eagle-import") (part "CAPACITOR.0402"))
    )
    (comp (ref "C223")
      (value "0.1uF")
      (footprint "eagle-import:0402")
      (libsource (lib "eagle-import") (part "CAPACITOR.0402"))
    )
    (comp (ref "C224")
      (value "1uF")
      (footprint "eagle-import:0402")
      (libsource (lib "eagle-import") (part "CAPACITOR.0402"))
    )
    (comp (ref "C225")
      (value "1uF")
      (footprint "eagle-import:0402")
      (libsource (lib "eagle-import") (part "CAPACITOR.0402"))
    )
    (comp (ref "D2")
      (value "White")
      (footprint "eagle-import:0603.LED")
      (libsource (lib "eagle-import") (part "LED.0603"))
    )
    (comp (ref "JP1")
      (value "PINHD-2X10")
      (footprint "eagle-import:2X10")
      (libsource (lib "eagle-import") (part "PINHD-2X10"))
    )
    (comp (ref "JP3")
      (value "PINHD-2X5")
      (footprint "eagle-import:2X05")
      (libsource (lib "eagle-import") (part "PINHD-2X5"))
    )
    (comp (ref "R22")
      (value "120R")
      (footprint "eagle-import:0402")
      (libsource (lib "eagle-import") (part "RESISTOR.0402"))
    )
    (comp (ref "R51")
      (value "49.9R_1%")
      (footprint "eagle-import:0201")
      (libsource (lib "eagle-import") (part "RESISTOR.0201"))
    )
    (comp (ref "R56")
      (value "4.7k")
      (footprint "eagle-import:0603")
      (libsource (lib "eagle-import") (part "RESISTOR.0603"))
    )
    (comp (ref "R57")
      (value "4.7k")
      (footprint "eagle-import:0603")
      (libsource (lib "eagle-import") (part "RESISTOR.0603"))
    )
    (comp (ref "R58")
      (value "4.7k")
      (footprint "eagle-import:0603")
      (libsource (lib "eagle-import") (part "RESISTOR.0603"))
    )
    (comp (ref "R59")
      (value "DNI")
      (footprint "eagle-import:0402")
      (libsource (lib "eagle-import") (part "RESISTOR.0402"))
    )
    (comp (ref "R77")
      (value "4.7k")
      (footprint "eagle-import:0402")
      (libsource (lib "eagle-import") (part "RESISTOR.0402"))
    )
    (comp (ref "R78")
      (value "4.7k")
      (footprint "eagle-import:0402")
      (libsource (lib "eagle-import") (part "RESISTOR.0402"))
    )
    (comp (ref "R83")
      (value "4.7k")
      (footprint "eagle-import:0402")
      (libsource (lib "eagle-import") (part "RESISTOR.0402"))
    )
    (comp (ref "R84")
      (value "4.7k")
      (footprint "eagle-import:0402")
      (libsource (lib "eagle-import") (part "RESISTOR.0402"))
    )
    (comp (ref "R87")
      (value "330R")
      (footprint "eagle-import:0603")
      (libsource (lib "eagle-import") (part "RESISTOR.0603"))
    )
    (comp (ref "R88")
      (value "10k")
      (footprint "eagle-import:0402")
      (libsource (lib "eagle-import") (part "RESISTOR.0402"))
    )
    (comp (ref "R89")
      (value "DNI")
      (footprint "eagle-import:0402")
      (libsource (lib "eagle-import") (part "RESISTOR.0402"))
    )
    (comp (ref "U$5")
      (value "ECS-.327-12.5-1210B-N-TR")
      (footprint "eagle-import:OSCCC120X100X35")
      (libsource (lib "eagle-import") (part "ECS-.327-12.5-1210B-N-TR"))
    )
    (comp (ref "U$6")
      (value "NX3225SA-26.000000MHZ-G3")
      (footprint "eagle-import:OSCCC320X250X70")
      (libsource (lib "eagle-import") (part "NX3225SA-26.000000MHZ-G3"))
    )
    (comp (ref "U$9")
      (value "TMP100")
      (footprint "eagle-import:SOT23-6")
      (libsource (lib "eagle-import") (part "TMP100"))
    )
    (comp (ref "U13")
      (value "Value")
      (footprint "eagle-import:DCK0005A_N")
      (fields
        (field (name "ALTERNATEPARTNUMBER") "SN74LVC1G04DCKT")
        (field (name "MANUFACTURER") "Texas Instruments")
        (field (name "PARTNUMBER") "SN74LVC1G04DCKR")
      )
      (libsource (lib "eagle-import") (part "SN74LVC1G04DCKR"))
    )
    (comp (ref "U19")
      (value "Value")
      (footprint "eagle-import:D0008A_N")
      (fields (field (name "MANUFACTURER") "Texas Instruments") (field (name "PARTNUMBER") "TCAN1042VDRQ1"))
      (libsource (lib "eagle-import") (part "TCAN1042VDRQ1"))
    )
    (comp (ref "C158")
      (value "4.7uF")
      (footprint "eagle-import:0603")
      (libsource (lib "eagle-import") (part "CAPACITOR.0603"))
    )
    (comp (ref "C160")
      (value "0.1uF")
      (footprint "eagle-import:0603")
      (libsource (lib "eagle-import") (part "CAPACITOR.0603"))
    )
    (comp (ref "C177")
      (value "10uF")
      (footprint "eagle-import:0603")
      (libsource (lib "eagle-import") (part "CAPACITOR.0603"))
    )
    (comp (ref "C178")
      (value "4.7uF")
      (footprint "eagle-import:0603")
      (libsource (lib "eagle-import") (part "CAPACITOR.0603"))
    )
    (comp (ref "C179")
      (value "0.1uF")
      (footprint "eagle-import:0603")
      (libsource (lib "eagle-import") (part "CAPACITOR.0603"))
    )
    (comp (ref "C180")
      (value "10uF")
      (footprint "eagle-import:0603")
      (libsource (lib "eagle-import") (part "CAPACITOR.0603"))
    )
    (comp (ref "R73")
      (value "10k")
      (footprint "eagle-import:0402")
      (libsource (lib "eagle-import") (part "RESISTOR.0402"))
    )
    (comp (ref "R74")
      (value "10k")
      (footprint "eagle-import:0402")
      (libsource (lib "eagle-import") (part "RESISTOR.0402"))
    )
    (comp (ref "R75")
      (value "10k")
      (footprint "eagle-import:0402")
      (libsource (lib "eagle-import") (part "RESISTOR.0402"))
    )
    (comp (ref "R76")
      (value "10k")
      (footprint "eagle-import:0402")
      (libsource (lib "eagle-import") (part "RESISTOR.0402"))
    )
    (comp (ref "U2")
      (value "TPD4S012_DRY_6")
      (footprint "eagle-import:DRY6")
      (fields
        (field (name "GENERIC_PART_NUMBER") "TPD4S012")
        (field (name "MANUFACTURER") "Texas Instruments")
        (field (name "MANUFACTURER_PART_NUMBER") "tpd4s012_dry_6")
      )
      (libsource (lib "eagle-import") (part "TPD4S012_DRY_6"))
    )
    (comp (ref "U10")
      (value "TPD4S012_DRY_6")
      (footprint "eagle-import:DRY6")
      (fields
        (field (name "GENERIC_PART_NUMBER") "TPD4S012")
        (field (name "MANUFACTURER") "Texas Instruments")
        (field (name "MANUFACTURER_PART_NUMBER") "tpd4s012_dry_6")
      )
      (libsource (lib "eagle-import") (part "TPD4S012_DRY_6"))
    )
    (comp (ref "U15")
      (value "TPS2051B_D_8")
      (footprint "eagle-import:D8")
      (fields
        (field (name "GENERIC_PART_NUMBER") "TPS2051B")
        (field (name "MANUFACTURER") "Texas Instruments")
        (field (name "MANUFACTURER_PART_NUMBER") "tps2051b_d_8")
      )
      (libsource (lib "eagle-import") (part "TPS2051B_D_8"))
    )
    (comp (ref "U16")
      (value "TPS2051B_D_8")
      (footprint "eagle-import:D8")
      (fields
        (field (name "GENERIC_PART_NUMBER") "TPS2051B")
        (field (name "MANUFACTURER") "Texas Instruments")
        (field (name "MANUFACTURER_PART_NUMBER") "tps2051b_d_8")
      )
      (libsource (lib "eagle-import") (part "TPS2051B_D_8"))
    )
    (comp (ref "X2")
      (value "USB-A-H")
      (footprint "eagle-import:USB-A-H")
      (libsource (lib "eagle-import") (part "USB-A-H"))
    )
    (comp (ref "X3")
      (value "USB-A-H")
      (footprint "eagle-import:USB-A-H")
      (libsource (lib "eagle-import") (part "USB-A-H"))
    )
    (comp (ref "C232")
      (value "1uF")
      (footprint "eagle-import:0402")
      (libsource (lib "eagle-import") (part "CAPACITOR.0402"))
    )
    (comp (ref "C233")
      (value "0.1uF")
      (footprint "eagle-import:0402")
      (libsource (lib "eagle-import") (part "CAPACITOR.0402"))
    )
    (comp (ref "JP2")
      (value "PINHD-1X9")
      (footprint "eagle-import:1X09")
      (libsource (lib "eagle-import") (part "PINHD-1X9"))
    )
    (comp (ref "R98")
      (value "10k")
      (footprint "eagle-import:0402")
      (libsource (lib "eagle-import") (part "RESISTOR.0402"))
    )
    (comp (ref "U$12")
      (value "PCA9685")
      (footprint "eagle-import:HVQFN28")
      (libsource (lib "eagle-import") (part "PCA9685"))
    )
    (comp (ref "C139")
      (value "0.1uF")
      (footprint "eagle-import:0402")
      (libsource (lib "eagle-import") (part "CAPACITOR.0402"))
    )
    (comp (ref "C140")
      (value "1uF")
      (footprint "eagle-import:0402")
      (libsource (lib "eagle-import") (part "CAPACITOR.0402"))
    )
    (comp (ref "C141")
      (value "1000pF")
      (footprint "eagle-import:0402")
      (libsource (lib "eagle-import") (part "CAPACITOR.0402"))
    )
    (comp (ref "C226")
      (value "4.7uF")
      (footprint "eagle-import:0603")
      (libsource (lib "eagle-import") (part "CAPACITOR.0603"))
    )
    (comp (ref "C227")
      (value "4.7uF")
      (footprint "eagle-import:0603")
      (libsource (lib "eagle-import") (part "CAPACITOR.0603"))
    )
    (comp (ref "C228")
      (value "4.7uF")
      (footprint "eagle-import:0603")
      (libsource (lib "eagle-import") (part "CAPACITOR.0603"))
    )
    (comp (ref "C229")
      (value "0.1uF")
      (footprint "eagle-import:0603")
      (libsource (lib "eagle-import") (part "CAPACITOR.0603"))
    )
    (comp (ref "C230")
      (value "4.7uF")
      (footprint "eagle-import:0603")
      (libsource (lib "eagle-import") (part "CAPACITOR.0603"))
    )
    (comp (ref "C231")
      (value "4.7uF")
      (footprint "eagle-import:0603")
      (libsource (lib "eagle-import") (part "CAPACITOR.0603"))
    )
    (comp (ref "C234")
      (value "0.22uF")
      (footprint "eagle-import:0603")
      (libsource (lib "eagle-import") (part "CAPACITOR.0603"))
    )
    (comp (ref "C235")
      (value "0.22uF")
      (footprint "eagle-import:0603")
      (libsource (lib "eagle-import") (part "CAPACITOR.0603"))
    )
    (comp (ref "C236")
      (value "0.22uF")
      (footprint "eagle-import:0603")
      (libsource (lib "eagle-import") (part "CAPACITOR.0603"))
    )
    (comp (ref "C237")
      (value "0.22uF")
      (footprint "eagle-import:0603")
      (libsource (lib "eagle-import") (part "CAPACITOR.0603"))
    )
    (comp (ref "C464")
      (value "4.7uF")
      (footprint "eagle-import:0603")
      (libsource (lib "eagle-import") (part "CAPACITOR.0603"))
    )
    (comp (ref "C465")
      (value "0.1uF")
      (footprint "eagle-import:0603")
      (libsource (lib "eagle-import") (part "CAPACITOR.0603"))
    )
    (comp (ref "R71")
      (value "1M")
      (footprint "eagle-import:0402")
      (libsource (lib "eagle-import") (part "RESISTOR.0402"))
    )
    (comp (ref "R85")
      (value "10k")
      (footprint "eagle-import:0402")
      (libsource (lib "eagle-import") (part "RESISTOR.0402"))
    )
    (comp (ref "R86")
      (value "DNI")
      (footprint "eagle-import:0402")
      (libsource (lib "eagle-import") (part "RESISTOR.0402"))
    )
    (comp (ref "T1")
      (value "2908-05WB-MG")
      (footprint "eagle-import:MICRO-SD-SOCKET-PP")
      (libsource (lib "eagle-import") (part "2908-05WB-MG"))
    )
    (comp (ref "U$10")
      (value "IS21ES16G")
      (footprint "eagle-import:BGA153C50P14X14_1150X1300X100N")
      (libsource (lib "eagle-import") (part "IS21ES16G"))
    )
    (comp (ref "U$11")
      (value "IS21ES16G")
      (footprint "eagle-import:BGA153C50P14X14_1150X1300X100N")
      (libsource (lib "eagle-import") (part "IS21ES16G"))
    )
    (comp (ref "U18")
      (value "TPD4E004_DRY_6")
      (footprint "eagle-import:DRY6")
      (fields
        (field (name "GENERIC_PART_NUMBER") "TPD4E004")
        (field (name "MANUFACTURER") "Texas Instruments")
        (field (name "MANUFACTURER_PART_NUMBER") "tpd4e004_dry_6")
      )
      (libsource (lib "eagle-import") (part "TPD4E004_DRY_6"))
    )
    (comp (ref "C48")
      (value "0.1uF")
      (footprint "eagle-import:0402")
      (libsource (lib "eagle-import") (part "CAPACITOR.0402"))
    )
    (comp (ref "C49")
      (value "0.1uF")
      (footprint "eagle-import:0402")
      (libsource (lib "eagle-import") (part "CAPACITOR.0402"))
    )
    (comp (ref "C50")
      (value "0.1uF")
      (footprint "eagle-import:0402")
      (libsource (lib "eagle-import") (part "CAPACITOR.0402"))
    )
    (comp (ref "C51")
      (value "0.1uF")
      (footprint "eagle-import:0402")
      (libsource (lib "eagle-import") (part "CAPACITOR.0402"))
    )
    (comp (ref "C52")
      (value "0.1uF")
      (footprint "eagle-import:0402")
      (libsource (lib "eagle-import") (part "CAPACITOR.0402"))
    )
    (comp (ref "C53")
      (value "0.1uF")
      (footprint "eagle-import:0402")
      (libsource (lib "eagle-import") (part "CAPACITOR.0402"))
    )
    (comp (ref "C54")
      (value "0.1uF")
      (footprint "eagle-import:0402")
      (libsource (lib "eagle-import") (part "CAPACITOR.0402"))
    )
    (comp (ref "C55")
      (value "0.1uF")
      (footprint "eagle-import:0402")
      (libsource (lib "eagle-import") (part "CAPACITOR.0402"))
    )
    (comp (ref "C56")
      (value "1uF")
      (footprint "eagle-import:0402")
      (libsource (lib "eagle-import") (part "CAPACITOR.0402"))
    )
    (comp (ref "C57")
      (value "1uF")
      (footprint "eagle-import:0402")
      (libsource (lib "eagle-import") (part "CAPACITOR.0402"))
    )
    (comp (ref "C58")
      (value "0.1uF")
      (footprint "eagle-import:0201")
      (libsource (lib "eagle-import") (part "CAPACITOR.0201"))
    )
    (comp (ref "C59")
      (value "0.1uF")
      (footprint "eagle-import:0402")
      (libsource (lib "eagle-import") (part "CAPACITOR.0402"))
    )
    (comp (ref "C60")
      (value "2.2uF")
      (footprint "eagle-import:0603")
      (libsource (lib "eagle-import") (part "CAPACITOR.0603"))
    )
    (comp (ref "C61")
      (value "0.1uF")
      (footprint "eagle-import:0201")
      (libsource (lib "eagle-import") (part "CAPACITOR.0201"))
    )
    (comp (ref "C62")
      (value "10uF")
      (footprint "eagle-import:0603")
      (libsource (lib "eagle-import") (part "CAPACITOR.0603"))
    )
    (comp (ref "C63")
      (value "10uF")
      (footprint "eagle-import:0603")
      (libsource (lib "eagle-import") (part "CAPACITOR.0603"))
    )
    (comp (ref "C64")
      (value "10uF")
      (footprint "eagle-import:0402")
      (libsource (lib "eagle-import") (part "CAPACITOR.0402"))
    )
    (comp (ref "C65")
      (value "10uF")
      (footprint "eagle-import:0402")
      (libsource (lib "eagle-import") (part "CAPACITOR.0402"))
    )
    (comp (ref "C213")
      (value "1uF")
      (footprint "eagle-import:0402")
      (libsource (lib "eagle-import") (part "CAPACITOR.0402"))
    )
    (comp (ref "C214")
      (value "1uF")
      (footprint "eagle-import:0402")
      (libsource (lib "eagle-import") (part "CAPACITOR.0402"))
    )
    (comp (ref "C215")
      (value "1uF")
      (footprint "eagle-import:0402")
      (libsource (lib "eagle-import") (part "CAPACITOR.0402"))
    )
    (comp (ref "C217")
      (value "1uF")
      (footprint "eagle-import:0402")
      (libsource (lib "eagle-import") (part "CAPACITOR.0402"))
    )
    (comp (ref "C218")
      (value "1uF")
      (footprint "eagle-import:0402")
      (libsource (lib "eagle-import") (part "CAPACITOR.0402"))
    )
    (comp (ref "C219")
      (value "1uF")
      (footprint "eagle-import:0402")
      (libsource (lib "eagle-import") (part "CAPACITOR.0402"))
    )
    (comp (ref "C220")
      (value "1uF")
      (footprint "eagle-import:0402")
      (libsource (lib "eagle-import") (part "CAPACITOR.0402"))
    )
    (comp (ref "C221")
      (value "1uF")
      (footprint "eagle-import:0402")
      (libsource (lib "eagle-import") (part "CAPACITOR.0402"))
    )
    (comp (ref "R21")
      (value "240R_1%")
      (footprint "eagle-import:0402")
      (libsource (lib "eagle-import") (part "RESISTOR.0402"))
    )
    (comp (ref "R25")
      (value "22R_1%")
      (footprint "eagle-import:0201")
      (libsource (lib "eagle-import") (part "RESISTOR.0201"))
    )
    (comp (ref "R26")
      (value "22R_1%")
      (footprint "eagle-import:0201")
      (libsource (lib "eagle-import") (part "RESISTOR.0201"))
    )
    (comp (ref "R27")
      (value "22R_1%")
      (footprint "eagle-import:0201")
      (libsource (lib "eagle-import") (part "RESISTOR.0201"))
    )
    (comp (ref "R28")
      (value "22R_1%")
      (footprint "eagle-import:0201")
      (libsource (lib "eagle-import") (part "RESISTOR.0201"))
    )
    (comp (ref "R29")
      (value "22R_1%")
      (footprint "eagle-import:0201")
      (libsource (lib "eagle-import") (part "RESISTOR.0201"))
    )
    (comp (ref "R30")
      (value "22R_1%")
      (footprint "eagle-import:0201")
      (libsource (lib "eagle-import") (part "RESISTOR.0201"))
    )
    (comp (ref "R31")
      (value "22R_1%")
      (footprint "eagle-import:0201")
      (libsource (lib "eagle-import") (part "RESISTOR.0201"))
    )
    (comp (ref "R32")
      (value "22R_1%")
      (footprint "eagle-import:0201")
      (libsource (lib "eagle-import") (part "RESISTOR.0201"))
    )
    (comp (ref "R33")
      (value "22R_1%")
      (footprint "eagle-import:0201")
      (libsource (lib "eagle-import") (part "RESISTOR.0201"))
    )
    (comp (ref "R34")
      (value "22R_1%")
      (footprint "eagle-import:0201")
      (libsource (lib "eagle-import") (part "RESISTOR.0201"))
    )
    (comp (ref "R35")
      (value "22R_1%")
      (footprint "eagle-import:0201")
      (libsource (lib "eagle-import") (part "RESISTOR.0201"))
    )
    (comp (ref "R36")
      (value "22R_1%")
      (footprint "eagle-import:0201")
      (libsource (lib "eagle-import") (part "RESISTOR.0201"))
    )
    (comp (ref "R37")
      (value "22R_1%")
      (footprint "eagle-import:0201")
      (libsource (lib "eagle-import") (part "RESISTOR.0201"))
    )
    (comp (ref "R38")
      (value "22R_1%")
      (footprint "eagle-import:0201")
      (libsource (lib "eagle-import") (part "RESISTOR.0201"))
    )
    (comp (ref "R39")
      (value "22R_1%")
      (footprint "eagle-import:0201")
      (libsource (lib "eagle-import") (part "RESISTOR.0201"))
    )
    (comp (ref "R40")
      (value "22R_1%")
      (footprint "eagle-import:0201")
      (libsource (lib "eagle-import") (part "RESISTOR.0201"))
    )
    (comp (ref "R41")
      (value "22R_1%")
      (footprint "eagle-import:0201")
      (libsource (lib "eagle-import") (part "RESISTOR.0201"))
    )
    (comp (ref "R42")
      (value "22R_1%")
      (footprint "eagle-import:0201")
      (libsource (lib "eagle-import") (part "RESISTOR.0201"))
    )
    (comp (ref "R43")
      (value "22R_1%")
      (footprint "eagle-import:0201")
      (libsource (lib "eagle-import") (part "RESISTOR.0201"))
    )
    (comp (ref "R44")
      (value "22R_1%")
      (footprint "eagle-import:0201")
      (libsource (lib "eagle-import") (part "RESISTOR.0201"))
    )
    (comp (ref "R45")
      (value "22R_1%")
      (footprint "eagle-import:0201")
      (libsource (lib "eagle-import") (part "RESISTOR.0201"))
    )
    (comp (ref "R46")
      (value "22R_1%")
      (footprint "eagle-import:0201")
      (libsource (lib "eagle-import") (part "RESISTOR.0201"))
    )
    (comp (ref "R47")
      (value "22R_1%")
      (footprint "eagle-import:0201")
      (libsource (lib "eagle-import") (part "RESISTOR.0201"))
    )
    (comp (ref "R48")
      (value "22R_1%")
      (footprint "eagle-import:0201")
      (libsource (lib "eagle-import") (part "RESISTOR.0201"))
    )
    (comp (ref "R49")
      (value "22R_1%")
      (footprint "eagle-import:0201")
      (libsource (lib "eagle-import") (part "RESISTOR.0201"))
    )
    (comp (ref "R50")
      (value "22R_1%")
      (footprint "eagle-import:0201")
      (libsource (lib "eagle-import") (part "RESISTOR.0201"))
    )
    (comp (ref "U9")
      (value "AS4C256M16D3B-12BIN")
      (footprint "eagle-import:BGA144C80P9X16_1350X900X120")
      (libsource (lib "eagle-import") (part "AS4C256M16D3B-12BIN"))
    )
    (comp (ref "C117")
      (value "0.1uF")
      (footprint "eagle-import:0402")
      (libsource (lib "eagle-import") (part "CAPACITOR.0402"))
    )
    (comp (ref "R55")
      (value "10k")
      (footprint "eagle-import:0402")
      (libsource (lib "eagle-import") (part "RESISTOR.0402"))
    )
    (comp (ref "R90")
      (value "10k")
      (footprint "eagle-import:0402")
      (libsource (lib "eagle-import") (part "RESISTOR.0402"))
    )
    (comp (ref "R91")
      (value "10k")
      (footprint "eagle-import:0402")
      (libsource (lib "eagle-import") (part "RESISTOR.0402"))
    )
    (comp (ref "R94")
      (value "10k")
      (footprint "eagle-import:0402")
      (libsource (lib "eagle-import") (part "RESISTOR.0402"))
    )
    (comp (ref "R95")
      (value "10k")
      (footprint "eagle-import:0402")
      (libsource (lib "eagle-import") (part "RESISTOR.0402"))
    )
    (comp (ref "R96")
      (value "10k")
      (footprint "eagle-import:0402")
      (libsource (lib "eagle-import") (part "RESISTOR.0402"))
    )
    (comp (ref "R97")
      (value "10k")
      (footprint "eagle-import:0402")
      (libsource (lib "eagle-import") (part "RESISTOR.0402"))
    )
    (comp (ref "U12")
      (value "TCA9555_RTW_24")
      (footprint "eagle-import:RTW24_2P45X2P45")
      (fields
        (field (name "GENERIC_PART_NUMBER") "TCA9555")
        (field (name "MANUFACTURER") "Texas Instruments")
        (field (name "MANUFACTURER_PART_NUMBER") "tca9555_rtw_24")
      )
      (libsource (lib "eagle-import") (part "TCA9555_RTW_24"))
    )
    (comp (ref "C4")
      (value "10uF")
      (footprint "eagle-import:0603")
      (libsource (lib "eagle-import") (part "CAPACITOR.0603"))
    )
    (comp (ref "C5")
      (value "0.1uF")
      (footprint "eagle-import:0603")
      (libsource (lib "eagle-import") (part "CAPACITOR.0603"))
    )
    (comp (ref "C6")
      (value "22uF")
      (footprint "eagle-import:0603")
      (libsource (lib "eagle-import") (part "CAPACITOR.0603"))
    )
    (comp (ref "C7")
      (value "0.1uF")
      (footprint "eagle-import:0603")
      (libsource (lib "eagle-import") (part "CAPACITOR.0603"))
    )
    (comp (ref "C8")
      (value "0.1uF")
      (footprint "eagle-import:0603")
      (libsource (lib "eagle-import") (part "CAPACITOR.0603"))
    )
    (comp (ref "C12")
      (value "0.1uF")
      (footprint "eagle-import:0603")
      (libsource (lib "eagle-import") (part "CAPACITOR.0603"))
    )
    (comp (ref "C34")
      (value "150uF")
      (footprint "eagle-import:CAPPRD350W65D800H1500B")
      (libsource (lib "eagle-import") (part "CAPACITOR_POLARIZED2"))
    )
    (comp (ref "C35")
      (value "150uF")
      (footprint "eagle-import:CAPPRD350W65D800H1500B")
      (libsource (lib "eagle-import") (part "CAPACITOR_POLARIZED2"))
    )
    (comp (ref "C36")
      (value "10uF")
      (footprint "eagle-import:0603")
      (libsource (lib "eagle-import") (part "CAPACITOR.0603"))
    )
    (comp (ref "C37")
      (value "10uF")
      (footprint "eagle-import:0603")
      (libsource (lib "eagle-import") (part "CAPACITOR.0603"))
    )
    (comp (ref "C38")
      (value "10uF")
      (footprint "eagle-import:0603")
      (libsource (lib "eagle-import") (part "CAPACITOR.0603"))
    )
    (comp (ref "C39")
      (value "1nF")
      (footprint "eagle-import:0603")
      (libsource (lib "eagle-import") (part "CAPACITOR.0603"))
    )
    (comp (ref "C40")
      (value "1nF")
      (footprint "eagle-import:0603")
      (libsource (lib "eagle-import") (part "CAPACITOR.0603"))
    )
    (comp (ref "C41")
      (value "4.7uF")
      (footprint "eagle-import:0603")
      (libsource (lib "eagle-import") (part "CAPACITOR.0603"))
    )
    (comp (ref "C42")
      (value "10uF")
      (footprint "eagle-import:0603")
      (libsource (lib "eagle-import") (part "CAPACITOR.0603"))
    )
    (comp (ref "C43")
      (value "10uF")
      (footprint "eagle-import:0603")
      (libsource (lib "eagle-import") (part "CAPACITOR.0603"))
    )
    (comp (ref "C44")
      (value "0.033uF")
      (footprint "eagle-import:0603")
      (libsource (lib "eagle-import") (part "CAPACITOR.0603"))
    )
    (comp (ref "C45")
      (value "4.7uF")
      (footprint "eagle-import:0603")
      (libsource (lib "eagle-import") (part "CAPACITOR.0603"))
    )
    (comp (ref "C46")
      (value "0.1uF")
      (footprint "eagle-import:0603")
      (libsource (lib "eagle-import") (part "CAPACITOR.0603"))
    )
    (comp (ref "C47")
      (value "0.1uF")
      (footprint "eagle-import:0603")
      (libsource (lib "eagle-import") (part "CAPACITOR.0603"))
    )
    (comp (ref "C86")
      (value "1uF")
      (footprint "eagle-import:0603")
      (libsource (lib "eagle-import") (part "CAPACITOR.0603"))
    )
    (comp (ref "C87")
      (value "0.1uF")
      (footprint "eagle-import:0603")
      (libsource (lib "eagle-import") (part "CAPACITOR.0603"))
    )
    (comp (ref "C142")
      (value "470uF")
      (footprint "eagle-import:CAPPRD300W65D800H1200B")
      (libsource (lib "eagle-import") (part "CAPACITOR_POLARIZED1"))
    )
    (comp (ref "C143")
      (value "270uF")
      (footprint "eagle-import:CAPPRD350W65D800H1500B")
      (libsource (lib "eagle-import") (part "CAPACITOR_POLARIZED2"))
    )
    (comp (ref "C144")
      (value "270uF")
      (footprint "eagle-import:CAPPRD350W65D800H1500B")
      (libsource (lib "eagle-import") (part "CAPACITOR_POLARIZED2"))
    )
    (comp (ref "C145")
      (value "470uF")
      (footprint "eagle-import:CAPPRD300W65D800H1200B")
      (libsource (lib "eagle-import") (part "CAPACITOR_POLARIZED1"))
    )
    (comp (ref "C146")
      (value "220uF")
      (footprint "eagle-import:CAPPRD250W65D600H1100B")
      (libsource (lib "eagle-import") (part "CAPACITOR_POLARIZED"))
    )
    (comp (ref "C148")
      (value "4.7uF")
      (footprint "eagle-import:0603")
      (libsource (lib "eagle-import") (part "CAPACITOR.0603"))
    )
    (comp (ref "C149")
      (value "4.7uF")
      (footprint "eagle-import:0603")
      (libsource (lib "eagle-import") (part "CAPACITOR.0603"))
    )
    (comp (ref "C150")
      (value "0.47uF")
      (footprint "eagle-import:0603")
      (libsource (lib "eagle-import") (part "CAPACITOR.0603"))
    )
    (comp (ref "C151")
      (value "1uF")
      (footprint "eagle-import:0603")
      (libsource (lib "eagle-import") (part "CAPACITOR.0603"))
    )
    (comp (ref "C152")
      (value "0.1uF")
      (footprint "eagle-import:0603")
      (libsource (lib "eagle-import") (part "CAPACITOR.0603"))
    )
    (comp (ref "C153")
      (value "0.1uF")
      (footprint "eagle-import:0603")
      (libsource (lib "eagle-import") (part "CAPACITOR.0603"))
    )
    (comp (ref "C154")
      (value "100pF")
      (footprint "eagle-import:0603")
      (libsource (lib "eagle-import") (part "CAPACITOR.0603"))
    )
    (comp (ref "C155")
      (value "0.01uF")
      (footprint "eagle-import:0603")
      (libsource (lib "eagle-import") (part "CAPACITOR.0603"))
    )
    (comp (ref "C156")
      (value "0.056uF")
      (footprint "eagle-import:0603")
      (libsource (lib "eagle-import") (part "CAPACITOR.0603"))
    )
    (comp (ref "C157")
      (value "47uF")
      (footprint "eagle-import:0805")
      (libsource (lib "eagle-import") (part "CAPACITOR.0805"))
    )
    (comp (ref "C159")
      (value "100uF")
      (footprint "eagle-import:0805")
      (libsource (lib "eagle-import") (part "CAPACITOR.0805"))
    )
    (comp (ref "C161")
      (value "47uF")
      (footprint "eagle-import:0805")
      (libsource (lib "eagle-import") (part "CAPACITOR.0805"))
    )
    (comp (ref "C162")
      (value "10uF")
      (footprint "eagle-import:0603")
      (libsource (lib "eagle-import") (part "CAPACITOR.0603"))
    )
    (comp (ref "C163")
      (value "1uF")
      (footprint "eagle-import:0603")
      (libsource (lib "eagle-import") (part "CAPACITOR.0603"))
    )
    (comp (ref "C164")
      (value "0.1uF")
      (footprint "eagle-import:0603")
      (libsource (lib "eagle-import") (part "CAPACITOR.0603"))
    )
    (comp (ref "C165")
      (value "0.01uF")
      (footprint "eagle-import:0603")
      (libsource (lib "eagle-import") (part "CAPACITOR.0603"))
    )
    (comp (ref "C166")
      (value "2.2uF")
      (footprint "eagle-import:0603")
      (libsource (lib "eagle-import") (part "CAPACITOR.0603"))
    )
    (comp (ref "C167")
      (value "0.47uF")
      (footprint "eagle-import:0603")
      (libsource (lib "eagle-import") (part "CAPACITOR.0603"))
    )
    (comp (ref "C168")
      (value "2.2uF")
      (footprint "eagle-import:0603")
      (libsource (lib "eagle-import") (part "CAPACITOR.0603"))
    )
    (comp (ref "C169")
      (value "33pF")
      (footprint "eagle-import:0603")
      (libsource (lib "eagle-import") (part "CAPACITOR.0603"))
    )
    (comp (ref "C170")
      (value "33pF")
      (footprint "eagle-import:0603")
      (libsource (lib "eagle-import") (part "CAPACITOR.0603"))
    )
    (comp (ref "C171")
      (value "0.056uF")
      (footprint "eagle-import:0603")
      (libsource (lib "eagle-import") (part "CAPACITOR.0603"))
    )
    (comp (ref "C172")
      (value "100pF")
      (footprint "eagle-import:0603")
      (libsource (lib "eagle-import") (part "CAPACITOR.0603"))
    )
    (comp (ref "C173")
      (value "0.01uF")
      (footprint "eagle-import:0603")
      (libsource (lib "eagle-import") (part "CAPACITOR.0603"))
    )
    (comp (ref "C174")
      (value "47uF")
      (footprint "eagle-import:0805")
      (libsource (lib "eagle-import") (part "CAPACITOR.0805"))
    )
    (comp (ref "C175")
      (value "10uF")
      (footprint "eagle-import:0603")
      (libsource (lib "eagle-import") (part "CAPACITOR.0603"))
    )
    (comp (ref "C176")
      (value "22uF")
      (footprint "eagle-import:0603")
      (libsource (lib "eagle-import") (part "CAPACITOR.0603"))
    )
    (comp (ref "C181")
      (value "10uF")
      (footprint "eagle-import:0603")
      (libsource (lib "eagle-import") (part "CAPACITOR.0603"))
    )
    (comp (ref "C182")
      (value "0.1uF")
      (footprint "eagle-import:0603")
      (libsource (lib "eagle-import") (part "CAPACITOR.0603"))
    )
    (comp (ref "C183")
      (value "22uF")
      (footprint "eagle-import:0603")
      (libsource (lib "eagle-import") (part "CAPACITOR.0603"))
    )
    (comp (ref "C184")
      (value "0.1uF")
      (footprint "eagle-import:0603")
      (libsource (lib "eagle-import") (part "CAPACITOR.0603"))
    )
    (comp (ref "C185")
      (value "0.1uF")
      (footprint "eagle-import:0603")
      (libsource (lib "eagle-import") (part "CAPACITOR.0603"))
    )
    (comp (ref "C191")
      (value "1uF")
      (footprint "eagle-import:0603")
      (libsource (lib "eagle-import") (part "CAPACITOR.0603"))
    )
    (comp (ref "C192")
      (value "0.1uF")
      (footprint "eagle-import:0603")
      (libsource (lib "eagle-import") (part "CAPACITOR.0603"))
    )
    (comp (ref "C193")
      (value "10uF")
      (footprint "eagle-import:0805")
      (libsource (lib "eagle-import") (part "CAPACITOR.0805"))
    )
    (comp (ref "C194")
      (value "0.1uF")
      (footprint "eagle-import:0805")
      (libsource (lib "eagle-import") (part "CAPACITOR.0805"))
    )
    (comp (ref "C195")
      (value "0.1uF")
      (footprint "eagle-import:0603")
      (libsource (lib "eagle-import") (part "CAPACITOR.0603"))
    )
    (comp (ref "C196")
      (value "0.015uF")
      (footprint "eagle-import:0603")
      (libsource (lib "eagle-import") (part "CAPACITOR.0603"))
    )
    (comp (ref "C197")
      (value "150pF")
      (footprint "eagle-import:0603")
      (libsource (lib "eagle-import") (part "CAPACITOR.0603"))
    )
    (comp (ref "C198")
      (value "22uF")
      (footprint "eagle-import:0603")
      (libsource (lib "eagle-import") (part "CAPACITOR.0603"))
    )
    (comp (ref "C199")
      (value "22uF")
      (footprint "eagle-import:0603")
      (libsource (lib "eagle-import") (part "CAPACITOR.0603"))
    )
    (comp (ref "C200")
      (value "200pF")
      (footprint "eagle-import:0603")
      (libsource (lib "eagle-import") (part "CAPACITOR.0603"))
    )
    (comp (ref "C216")
      (value "DNI")
      (footprint "eagle-import:0603")
      (libsource (lib "eagle-import") (part "CAPACITOR.0603"))
    )
    (comp (ref "D5")
      (value "Green")
      (footprint "eagle-import:0603.LED")
      (libsource (lib "eagle-import") (part "LED.0603"))
    )
    (comp (ref "D6")
      (value "Green")
      (footprint "eagle-import:0603.LED")
      (libsource (lib "eagle-import") (part "LED.0603"))
    )
    (comp (ref "Q8")
      (value "CSD18543Q3A")
      (footprint "eagle-import:SON65P300X315X90-9N")
      (fields (field (name "MF") "Texas Instruments"))
      (libsource (lib "eagle-import") (part "CSD18543Q3A"))
    )
    (comp (ref "Q9")
      (value "CSD18543Q3A")
      (footprint "eagle-import:SON65P300X315X90-9N")
      (fields (field (name "MF") "Texas Instruments"))
      (libsource (lib "eagle-import") (part "CSD18543Q3A"))
    )
    (comp (ref "Q10")
      (value "CSD18543Q3A")
      (footprint "eagle-import:SON65P300X315X90-9N")
      (fields (field (name "MF") "Texas Instruments"))
      (libsource (lib "eagle-import") (part "CSD18543Q3A"))
    )
    (comp (ref "Q11")
      (value "CSD18543Q3A")
      (footprint "eagle-import:SON65P300X315X90-9N")
      (fields (field (name "MF") "Texas Instruments"))
      (libsource (lib "eagle-import") (part "CSD18543Q3A"))
    )
    (comp (ref "R13")
      (value "5.11R")
      (footprint "eagle-import:0603")
      (libsource (lib "eagle-import") (part "RESISTOR.0603"))
    )
    (comp (ref "R14")
      (value "7.15k")
      (footprint "eagle-import:0603")
      (libsource (lib "eagle-import") (part "RESISTOR.0603"))
    )
    (comp (ref "R15")
      (value "100k")
      (footprint "eagle-import:0603")
      (libsource (lib "eagle-import") (part "RESISTOR.0603"))
    )
    (comp (ref "R16")
      (value "0.006R")
      (footprint "eagle-import:0805")
      (libsource (lib "eagle-import") (part "RESISTOR.0805"))
    )
    (comp (ref "R17")
      (value "3.09R")
      (footprint "eagle-import:0603")
      (libsource (lib "eagle-import") (part "RESISTOR.0603"))
    )
    (comp (ref "R18")
      (value "DNI")
      (footprint "eagle-import:0603")
      (libsource (lib "eagle-import") (part "RESISTOR.0603"))
    )
    (comp (ref "R19")
      (value "4.75k")
      (footprint "eagle-import:0603")
      (libsource (lib "eagle-import") (part "RESISTOR.0603"))
    )
    (comp (ref "R20")
      (value "4.75k")
      (footprint "eagle-import:0603")
      (libsource (lib "eagle-import") (part "RESISTOR.0603"))
    )
    (comp (ref "R52")
      (value "10k")
      (footprint "eagle-import:0603")
      (libsource (lib "eagle-import") (part "RESISTOR.0603"))
    )
    (comp (ref "R54")
      (value "4.7k")
      (footprint "eagle-import:0603")
      (libsource (lib "eagle-import") (part "RESISTOR.0603"))
    )
    (comp (ref "R202")
      (value "10.2R")
      (footprint "eagle-import:0603")
      (libsource (lib "eagle-import") (part "RESISTOR.0603"))
    )
    (comp (ref "R203")
      (value "10.2R")
      (footprint "eagle-import:0603")
      (libsource (lib "eagle-import") (part "RESISTOR.0603"))
    )
    (comp (ref "R204")
      (value "10.2R")
      (footprint "eagle-import:0603")
      (libsource (lib "eagle-import") (part "RESISTOR.0603"))
    )
    (comp (ref "R205")
      (value "0.005R")
      (footprint "eagle-import:R2512")
      (libsource (lib "eagle-import") (part "R-US_R2512"))
    )
    (comp (ref "R206")
      (value "0R")
      (footprint "eagle-import:0603")
      (libsource (lib "eagle-import") (part "RESISTOR.0603"))
    )
    (comp (ref "R207")
      (value "19.6k 0.1%")
      (footprint "eagle-import:0603")
      (libsource (lib "eagle-import") (part "RESISTOR.0603"))
    )
    (comp (ref "R208")
      (value "100k")
      (footprint "eagle-import:0603")
      (libsource (lib "eagle-import") (part "RESISTOR.0603"))
    )
    (comp (ref "R211")
      (value "10.2R")
      (footprint "eagle-import:0603")
      (libsource (lib "eagle-import") (part "RESISTOR.0603"))
    )
    (comp (ref "R212")
      (value "10.2R")
      (footprint "eagle-import:0603")
      (libsource (lib "eagle-import") (part "RESISTOR.0603"))
    )
    (comp (ref "R213")
      (value "10.2R")
      (footprint "eagle-import:0603")
      (libsource (lib "eagle-import") (part "RESISTOR.0603"))
    )
    (comp (ref "R214")
      (value "49.9R")
      (footprint "eagle-import:0603")
      (libsource (lib "eagle-import") (part "RESISTOR.0603"))
    )
    (comp (ref "R215")
      (value "49.9R")
      (footprint "eagle-import:0603")
      (libsource (lib "eagle-import") (part "RESISTOR.0603"))
    )
    (comp (ref "R216")
      (value "49.9R")
      (footprint "eagle-import:0603")
      (libsource (lib "eagle-import") (part "RESISTOR.0603"))
    )
    (comp (ref "R217")
      (value "0.005R")
      (footprint "eagle-import:R2512")
      (libsource (lib "eagle-import") (part "R-US_R2512"))
    )
    (comp (ref "R218")
      (value "29.4k 1%")
      (footprint "eagle-import:0603")
      (libsource (lib "eagle-import") (part "RESISTOR.0603"))
    )
    (comp (ref "R219")
      (value "220R")
      (footprint "eagle-import:0603")
      (libsource (lib "eagle-import") (part "RESISTOR.0603"))
    )
    (comp (ref "R220")
      (value "330R")
      (footprint "eagle-import:0603")
      (libsource (lib "eagle-import") (part "RESISTOR.0603"))
    )
    (comp (ref "R229")
      (value "10k")
      (footprint "eagle-import:0603")
      (libsource (lib "eagle-import") (part "RESISTOR.0603"))
    )
    (comp (ref "R230")
      (value "100k")
      (footprint "eagle-import:0603")
      (libsource (lib "eagle-import") (part "RESISTOR.0603"))
    )
    (comp (ref "R231")
      (value "2.05k_1%")
      (footprint "eagle-import:0603")
      (libsource (lib "eagle-import") (part "RESISTOR.0603"))
    )
    (comp (ref "R232")
      (value "51.1R_1%")
      (footprint "eagle-import:0603")
      (libsource (lib "eagle-import") (part "RESISTOR.0603"))
    )
    (comp (ref "R233")
      (value "31.6k_1%")
      (footprint "eagle-import:0603")
      (libsource (lib "eagle-import") (part "RESISTOR.0603"))
    )
    (comp (ref "R234")
      (value "10k_1%")
      (footprint "eagle-import:0603")
      (libsource (lib "eagle-import") (part "RESISTOR.0603"))
    )
    (comp (ref "R243")
      (value "100k")
      (footprint "eagle-import:0603")
      (libsource (lib "eagle-import") (part "RESISTOR.0603"))
    )
    (comp (ref "TP1")
      (value "TESTPAD_TPSQB1,27")
      (footprint "eagle-import:TESTPAD_B1,27")
      (libsource (lib "eagle-import") (part "TESTPAD_TPSQB1,27"))
    )
    (comp (ref "TP2")
      (value "TESTPAD_TPSQB1,27")
      (footprint "eagle-import:TESTPAD_B1,27")
      (libsource (lib "eagle-import") (part "TESTPAD_TPSQB1,27"))
    )
    (comp (ref "TP24")
      (value "TESTPAD_TPSQB1,27")
      (footprint "eagle-import:TESTPAD_B1,27")
      (libsource (lib "eagle-import") (part "TESTPAD_TPSQB1,27"))
    )
    (comp (ref "TP25")
      (value "TESTPAD_TPSQB1,27")
      (footprint "eagle-import:TESTPAD_B1,27")
      (libsource (lib "eagle-import") (part "TESTPAD_TPSQB1,27"))
    )
    (comp (ref "TP26")
      (value "TESTPAD_TPSQB1,27")
      (footprint "eagle-import:TESTPAD_B1,27")
      (libsource (lib "eagle-import") (part "TESTPAD_TPSQB1,27"))
    )
    (comp (ref "TP29")
      (value "TESTPAD_TPSQB1,27")
      (footprint "eagle-import:TESTPAD_B1,27")
      (libsource (lib "eagle-import") (part "TESTPAD_TPSQB1,27"))
    )
    (comp (ref "TP31")
      (value "TESTPAD_TPSQB1,27")
      (footprint "eagle-import:TESTPAD_B1,27")
      (libsource (lib "eagle-import") (part "TESTPAD_TPSQB1,27"))
    )
    (comp (ref "TP32")
      (value "TESTPAD_TPSQB1,27")
      (footprint "eagle-import:TESTPAD_B1,27")
      (libsource (lib "eagle-import") (part "TESTPAD_TPSQB1,27"))
    )
    (comp (ref "U$1")
      (value "XFL4015-471MEB")
      (footprint "eagle-import:XFL4015-471MEB")
      (libsource (lib "eagle-import") (part "XFL4015-471MEB"))
    )
    (comp (ref "U$2")
      (value "IRF7821")
      (footprint "eagle-import:SOIC127P600X175-8_V2")
      (libsource (lib "eagle-import") (part "IRF7821"))
    )
    (comp (ref "U$3")
      (value "IRF7832")
      (footprint "eagle-import:SOIC127P600X175-8_V2")
      (libsource (lib "eagle-import") (part "IRF7832"))
    )
    (comp (ref "U$4")
      (value "XFL4020-102MEB")
      (footprint "eagle-import:XFL4020-102MEB")
      (libsource (lib "eagle-import") (part "XFL4020-102MEB"))
    )
    (comp (ref "U$20")
      (value "DB2441700L")
      (footprint "eagle-import:DB2441700L")
      (libsource (lib "eagle-import") (part "DB2441700L"))
    )
    (comp (ref "U$21")
      (value "DB2441700L")
      (footprint "eagle-import:DB2441700L")
      (libsource (lib "eagle-import") (part "DB2441700L"))
    )
    (comp (ref "U$22")
      (value "XEL6030-152MEB")
      (footprint "eagle-import:XEL6030-152MEB")
      (libsource (lib "eagle-import") (part "XEL6030-152MEB"))
    )
    (comp (ref "U$25")
      (value "XEL6030-152MEB")
      (footprint "eagle-import:XEL6030-152MEB")
      (libsource (lib "eagle-import") (part "XEL6030-152MEB"))
    )
    (comp (ref "U$28")
      (value "XFL4015-471MEB")
      (footprint "eagle-import:XFL4015-471MEB")
      (libsource (lib "eagle-import") (part "XFL4015-471MEB"))
    )
    (comp (ref "U$30")
      (value "XFL4015-471MEB")
      (footprint "eagle-import:XFL4015-471MEB")
      (libsource (lib "eagle-import") (part "XFL4015-471MEB"))
    )
    (comp (ref "U$33")
      (value "XEL4030-682ME_")
      (footprint "eagle-import:XEL4030-682ME_")
      (libsource (lib "eagle-import") (part "XEL4030-682ME_"))
    )
    (comp (ref "U4")
      (value "Value")
      (footprint "eagle-import:YZH0016AFAF")
      (fields
        (field (name "ALTERNATEPARTNUMBER") "TPS62363YZHT")
        (field (name "MANUFACTURER") "Texas Instruments")
        (field (name "PARTNUMBER") "TPS62363YZHR")
      )
      (libsource (lib "eagle-import") (part "TPS62363YZHR"))
    )
    (comp (ref "U6")
      (value "TPS51116_PWP_20")
      (footprint "eagle-import:PWP20_3P4X2P4")
      (fields
        (field (name "GENERIC_PART_NUMBER") "TPS51116")
        (field (name "MANUFACTURER") "Texas Instruments")
        (field (name "MANUFACTURER_PART_NUMBER") "tps51116_pwp_20")
      )
      (libsource (lib "eagle-import") (part "TPS51116_PWP_20"))
    )
    (comp (ref "U11")
      (value "Value")
      (footprint "eagle-import:DRV0006A")
      (fields (field (name "MANUFACTURER") "Texas Instruments") (field (name "PARTNUMBER") "LP59121.1DRVR"))
      (libsource (lib "eagle-import") (part "LP5912-1.1DRVR"))
    )
    (comp (ref "U34")
      (value "Value")
      (footprint "eagle-import:RWG0040A")
      (fields (field (name "MANUFACTURER") "Texas Instruments") (field (name "PARTNUMBER") "LM5140QRWGRQ1"))
      (libsource (lib "eagle-import") (part "LM5140QRWGRQ1"))
    )
    (comp (ref "U35")
      (value "Value")
      (footprint "eagle-import:RLT0007A")
      (fields (field (name "MANUFACTURER") "Texas Instruments") (field (name "PARTNUMBER") "TPS62087RLTR"))
      (libsource (lib "eagle-import") (part "TPS62087RLTR"))
    )
    (comp (ref "U38")
      (value "Value")
      (footprint "eagle-import:YZH0016AFAF")
      (fields
        (field (name "ALTERNATEPARTNUMBER") "TPS62363YZHT")
        (field (name "MANUFACTURER") "Texas Instruments")
        (field (name "PARTNUMBER") "TPS62363YZHR")
      )
      (libsource (lib "eagle-import") (part "TPS62363YZHR"))
    )
    (comp (ref "U40")
      (value "Value")
      (footprint "eagle-import:DRV0006A")
      (fields (field (name "MANUFACTURER") "Texas Instruments") (field (name "PARTNUMBER") "LP59121.1DRVR"))
      (libsource (lib "eagle-import") (part "LP5912-1.1DRVR"))
    )
    (comp (ref "U41")
      (value "Value")
      (footprint "eagle-import:DRC0010J")
      (fields
        (field (name "ALTERNATEPARTNUMBER") "TPS54334DRCT")
        (field (name "MANUFACTURER") "Texas Instruments")
        (field (name "PARTNUMBER") "TPS54334DRCR")
      )
      (libsource (lib "eagle-import") (part "TPS54334DRCR"))
    )
    (comp (ref "C123")
      (value "0.01uF")
      (footprint "eagle-import:0402")
      (libsource (lib "eagle-import") (part "CAPACITOR.0402"))
    )
    (comp (ref "C124")
      (value "0.01uF")
      (footprint "eagle-import:0402")
      (libsource (lib "eagle-import") (part "CAPACITOR.0402"))
    )
    (comp (ref "C125")
      (value "0.1uF")
      (footprint "eagle-import:0402")
      (libsource (lib "eagle-import") (part "CAPACITOR.0402"))
    )
    (comp (ref "C126")
      (value "0.1uF")
      (footprint "eagle-import:0402")
      (libsource (lib "eagle-import") (part "CAPACITOR.0402"))
    )
    (comp (ref "C127")
      (value "1uF")
      (footprint "eagle-import:0402")
      (libsource (lib "eagle-import") (part "CAPACITOR.0402"))
    )
    (comp (ref "C128")
      (value "1uF")
      (footprint "eagle-import:0402")
      (libsource (lib "eagle-import") (part "CAPACITOR.0402"))
    )
    (comp (ref "C129")
      (value "10uF")
      (footprint "eagle-import:0402")
      (libsource (lib "eagle-import") (part "CAPACITOR.0402"))
    )
    (comp (ref "C130")
      (value "10uF")
      (footprint "eagle-import:0402")
      (libsource (lib "eagle-import") (part "CAPACITOR.0402"))
    )
    (comp (ref "C131")
      (value "0.1uF")
      (footprint "eagle-import:0402")
      (libsource (lib "eagle-import") (part "CAPACITOR.0402"))
    )
    (comp (ref "C132")
      (value "1uF")
      (footprint "eagle-import:0402")
      (libsource (lib "eagle-import") (part "CAPACITOR.0402"))
    )
    (comp (ref "C133")
      (value "1uF")
      (footprint "eagle-import:0402")
      (libsource (lib "eagle-import") (part "CAPACITOR.0402"))
    )
    (comp (ref "C134")
      (value "0.1uF")
      (footprint "eagle-import:0402")
      (libsource (lib "eagle-import") (part "CAPACITOR.0402"))
    )
    (comp (ref "C135")
      (value "0.1uF")
      (footprint "eagle-import:0402")
      (libsource (lib "eagle-import") (part "CAPACITOR.0402"))
    )
    (comp (ref "C136")
      (value "1uF")
      (footprint "eagle-import:0402")
      (libsource (lib "eagle-import") (part "CAPACITOR.0402"))
    )
    (comp (ref "C137")
      (value "0.1uF")
      (footprint "eagle-import:0402")
      (libsource (lib "eagle-import") (part "CAPACITOR.0402"))
    )
    (comp (ref "C138")
      (value "1uF")
      (footprint "eagle-import:0402")
      (libsource (lib "eagle-import") (part "CAPACITOR.0402"))
    )
    (comp (ref "C238")
      (value "18pF")
      (footprint "eagle-import:0402")
      (libsource (lib "eagle-import") (part "CAPACITOR.0402"))
    )
    (comp (ref "C239")
      (value "18pF")
      (footprint "eagle-import:0402")
      (libsource (lib "eagle-import") (part "CAPACITOR.0402"))
    )
    (comp (ref "R53")
      (value "33R_1%")
      (footprint "eagle-import:0402")
      (libsource (lib "eagle-import") (part "RESISTOR.0402"))
    )
    (comp (ref "R60")
      (value "2.2k")
      (footprint "eagle-import:0402")
      (libsource (lib "eagle-import") (part "RESISTOR.0402"))
    )
    (comp (ref "R61")
      (value "4.87k_1%")
      (footprint "eagle-import:0402")
      (libsource (lib "eagle-import") (part "RESISTOR.0402"))
    )
    (comp (ref "R62")
      (value "1k")
      (footprint "eagle-import:0402")
      (libsource (lib "eagle-import") (part "RESISTOR.0402"))
    )
    (comp (ref "R63")
      (value "DNI")
      (footprint "eagle-import:0402")
      (libsource (lib "eagle-import") (part "RESISTOR.0402"))
    )
    (comp (ref "R64")
      (value "49.9R")
      (footprint "eagle-import:0402")
      (libsource (lib "eagle-import") (part "RESISTOR.0402"))
    )
    (comp (ref "R65")
      (value "49.9R")
      (footprint "eagle-import:0402")
      (libsource (lib "eagle-import") (part "RESISTOR.0402"))
    )
    (comp (ref "R66")
      (value "49.9R")
      (footprint "eagle-import:0402")
      (libsource (lib "eagle-import") (part "RESISTOR.0402"))
    )
    (comp (ref "R67")
      (value "49.9R")
      (footprint "eagle-import:0402")
      (libsource (lib "eagle-import") (part "RESISTOR.0402"))
    )
    (comp (ref "R68")
      (value "0R")
      (footprint "eagle-import:0402")
      (libsource (lib "eagle-import") (part "RESISTOR.0402"))
    )
    (comp (ref "R69")
      (value "DNI")
      (footprint "eagle-import:0402")
      (libsource (lib "eagle-import") (part "RESISTOR.0402"))
    )
    (comp (ref "R70")
      (value "DNI")
      (footprint "eagle-import:0402")
      (libsource (lib "eagle-import") (part "RESISTOR.0402"))
    )
    (comp (ref "R99")
      (value "33R_1%")
      (footprint "eagle-import:0402")
      (libsource (lib "eagle-import") (part "RESISTOR.0402"))
    )
    (comp (ref "R100")
      (value "33R_1%")
      (footprint "eagle-import:0402")
      (libsource (lib "eagle-import") (part "RESISTOR.0402"))
    )
    (comp (ref "R101")
      (value "33R_1%")
      (footprint "eagle-import:0402")
      (libsource (lib "eagle-import") (part "RESISTOR.0402"))
    )
    (comp (ref "R102")
      (value "33R_1%")
      (footprint "eagle-import:0402")
      (libsource (lib "eagle-import") (part "RESISTOR.0402"))
    )
    (comp (ref "U$7")
      (value "ECS-250-18-36B-CKY-TR")
      (footprint "eagle-import:OSCCC250X200X65")
      (libsource (lib "eagle-import") (part "ECS-250-18-36B-CKY-TR"))
    )
    (comp (ref "U14")
      (value "Value")
      (footprint "eagle-import:RHB0032B")
      (fields (field (name "MANUFACTURER") "Texas Instruments") (field (name "PARTNUMBER") "DP83822HRHBR"))
      (libsource (lib "eagle-import") (part "DP83822HRHBR"))
    )
    (comp (ref "X1")
      (value "J1006F01P")
      (footprint "eagle-import:J1")
      (libsource (lib "eagle-import") (part "J1006F01P"))
    )
    (comp (ref "C574")
      (value "0.1uF")
      (footprint "eagle-import:0402")
      (libsource (lib "eagle-import") (part "CAPACITOR.0402"))
    )
    (comp (ref "C575")
      (value "0.01uF")
      (footprint "eagle-import:0402")
      (libsource (lib "eagle-import") (part "CAPACITOR.0402"))
    )
    (comp (ref "C577")
      (value "DNI")
      (footprint "eagle-import:0402")
      (libsource (lib "eagle-import") (part "CAPACITOR.0402"))
    )
    (comp (ref "C578")
      (value "0.1uF")
      (footprint "eagle-import:0402")
      (libsource (lib "eagle-import") (part "CAPACITOR.0402"))
    )
    (comp (ref "C579")
      (value "0.1uF")
      (footprint "eagle-import:0402")
      (libsource (lib "eagle-import") (part "CAPACITOR.0402"))
    )
    (comp (ref "R72")
      (value "1k")
      (footprint "eagle-import:0402")
      (libsource (lib "eagle-import") (part "RESISTOR.0402"))
    )
    (comp (ref "R536")
      (value "261k_1%")
      (footprint "eagle-import:0402")
      (libsource (lib "eagle-import") (part "RESISTOR.0402"))
    )
    (comp (ref "R537")
      (value "10k_1%")
      (footprint "eagle-import:0402")
      (libsource (lib "eagle-import") (part "RESISTOR.0402"))
    )
    (comp (ref "R538")
      (value "10k_1%")
      (footprint "eagle-import:0402")
      (libsource (lib "eagle-import") (part "RESISTOR.0402"))
    )
    (comp (ref "R540")
      (value "5.81k_1%")
      (footprint "eagle-import:0402")
      (libsource (lib "eagle-import") (part "RESISTOR.0402"))
    )
    (comp (ref "R541")
      (value "10k_1%")
      (footprint "eagle-import:0402")
      (libsource (lib "eagle-import") (part "RESISTOR.0402"))
    )
    (comp (ref "R542")
      (value "10k_1%")
      (footprint "eagle-import:0402")
      (libsource (lib "eagle-import") (part "RESISTOR.0402"))
    )
    (comp (ref "R543")
      (value "0R")
      (footprint "eagle-import:0402")
      (libsource (lib "eagle-import") (part "RESISTOR.0402"))
    )
    (comp (ref "TP14")
      (value "TESTPAD_TPSQB1,27")
      (footprint "eagle-import:TESTPAD_B1,27")
      (libsource (lib "eagle-import") (part "TESTPAD_TPSQB1,27"))
    )
    (comp (ref "U76")
      (value "Value")
      (footprint "eagle-import:DDC0006A_N")
      (fields (field (name "MANUFACTURER") "Texas Instruments") (field (name "PARTNUMBER") "TPS3711DDCR"))
      (libsource (lib "eagle-import") (part "TPS3711DDCR"))
    )
    (comp (ref "U77")
      (value "TPS3897_DRY_6")
      (footprint "eagle-import:DRY6")
      (fields
        (field (name "GENERIC_PART_NUMBER") "TPS3897")
        (field (name "MANUFACTURER") "Texas Instruments")
        (field (name "MANUFACTURER_PART_NUMBER") "tps3897_dry_6")
      )
      (libsource (lib "eagle-import") (part "TPS3897_DRY_6"))
    )
    (comp (ref "U78")
      (value "SN74LVC1G11_DCK_6")
      (footprint "eagle-import:DCK6")
      (fields
        (field (name "GENERIC_PART_NUMBER") "SN74LVC1G11")
        (field (name "MANUFACTURER") "Texas Instruments")
        (field (name "MANUFACTURER_PART_NUMBER") "sn74lvc1g11_dck_6")
      )
      (libsource (lib "eagle-import") (part "SN74LVC1G11_DCK_6"))
    )
    (comp (ref "C147")
      (value "470uF")
      (footprint "eagle-import:CAPPRD300W65D800H1200B")
      (libsource (lib "eagle-import") (part "CAPACITOR_POLARIZED1"))
    )
    (comp (ref "J1")
      (value "SEAM-40-XX.X-XX-06-X-A")
      (footprint "eagle-import:SEAM-40-XX.X-XX-06-X-A")
      (libsource (lib "eagle-import") (part "SEAM-40-XX.X-XX-06-X-A"))
    )
    (comp (ref "C1")
      (value "0.1uF")
      (footprint "eagle-import:0603")
      (libsource (lib "eagle-import") (part "CAPACITOR.0603"))
    )
    (comp (ref "C2")
      (value "0.1uF")
      (footprint "eagle-import:0603")
      (libsource (lib "eagle-import") (part "CAPACITOR.0603"))
    )
    (comp (ref "C3")
      (value "0.1uF")
      (footprint "eagle-import:0603")
      (libsource (lib "eagle-import") (part "CAPACITOR.0603"))
    )
    (comp (ref "C9")
      (value "0.1uF")
      (footprint "eagle-import:0603")
      (libsource (lib "eagle-import") (part "CAPACITOR.0603"))
    )
    (comp (ref "C10")
      (value "0.1uF")
      (footprint "eagle-import:0603")
      (libsource (lib "eagle-import") (part "CAPACITOR.0603"))
    )
    (comp (ref "C11")
      (value "0.1uF")
      (footprint "eagle-import:0603")
      (libsource (lib "eagle-import") (part "CAPACITOR.0603"))
    )
    (comp (ref "C13")
      (value "0.1uF")
      (footprint "eagle-import:0603")
      (libsource (lib "eagle-import") (part "CAPACITOR.0603"))
    )
    (comp (ref "C29")
      (value "0.1uF")
      (footprint "eagle-import:0603")
      (libsource (lib "eagle-import") (part "CAPACITOR.0603"))
    )
    (comp (ref "C30")
      (value "0.1uF")
      (footprint "eagle-import:0603")
      (libsource (lib "eagle-import") (part "CAPACITOR.0603"))
    )
    (comp (ref "C31")
      (value "0.1uF")
      (footprint "eagle-import:0603")
      (libsource (lib "eagle-import") (part "CAPACITOR.0603"))
    )
    (comp (ref "C32")
      (value "0.1uF")
      (footprint "eagle-import:0603")
      (libsource (lib "eagle-import") (part "CAPACITOR.0603"))
    )
    (comp (ref "C33")
      (value "0.1uF")
      (footprint "eagle-import:0603")
      (libsource (lib "eagle-import") (part "CAPACITOR.0603"))
    )
    (comp (ref "R1")
      (value "10_1%")
      (footprint "eagle-import:0603")
      (libsource (lib "eagle-import") (part "RESISTOR.0603"))
    )
    (comp (ref "R2")
      (value "10_1%")
      (footprint "eagle-import:0603")
      (libsource (lib "eagle-import") (part "RESISTOR.0603"))
    )
    (comp (ref "R3")
      (value "0.002_1%")
      (footprint "eagle-import:1206")
      (libsource (lib "eagle-import") (part "RESISTOR.1206"))
    )
    (comp (ref "R4")
      (value "10_1%")
      (footprint "eagle-import:0603")
      (libsource (lib "eagle-import") (part "RESISTOR.0603"))
    )
    (comp (ref "R5")
      (value "10_1%")
      (footprint "eagle-import:0603")
      (libsource (lib "eagle-import") (part "RESISTOR.0603"))
    )
    (comp (ref "R6")
      (value "0.002_1%")
      (footprint "eagle-import:1206")
      (libsource (lib "eagle-import") (part "RESISTOR.1206"))
    )
    (comp (ref "R7")
      (value "10_1%")
      (footprint "eagle-import:0603")
      (libsource (lib "eagle-import") (part "RESISTOR.0603"))
    )
    (comp (ref "R8")
      (value "10_1%")
      (footprint "eagle-import:0603")
      (libsource (lib "eagle-import") (part "RESISTOR.0603"))
    )
    (comp (ref "R9")
      (value "0.002_1%")
      (footprint "eagle-import:1206")
      (libsource (lib "eagle-import") (part "RESISTOR.1206"))
    )
    (comp (ref "R10")
      (value "10_1%")
      (footprint "eagle-import:0603")
      (libsource (lib "eagle-import") (part "RESISTOR.0603"))
    )
    (comp (ref "R11")
      (value "10_1%")
      (footprint "eagle-import:0603")
      (libsource (lib "eagle-import") (part "RESISTOR.0603"))
    )
    (comp (ref "R12")
      (value "0.002_1%")
      (footprint "eagle-import:1206")
      (libsource (lib "eagle-import") (part "RESISTOR.1206"))
    )
    (comp (ref "U3")
      (value "INA226_DGS_10")
      (footprint "eagle-import:DGS10")
      (fields
        (field (name "GENERIC_PART_NUMBER") "INA226")
        (field (name "MANUFACTURER") "Texas Instruments")
        (field (name "MANUFACTURER_PART_NUMBER") "ina226_dgs_10")
      )
      (libsource (lib "eagle-import") (part "INA226_DGS_10"))
    )
    (comp (ref "U5")
      (value "INA226_DGS_10")
      (footprint "eagle-import:DGS10")
      (fields
        (field (name "GENERIC_PART_NUMBER") "INA226")
        (field (name "MANUFACTURER") "Texas Instruments")
        (field (name "MANUFACTURER_PART_NUMBER") "ina226_dgs_10")
      )
      (libsource (lib "eagle-import") (part "INA226_DGS_10"))
    )
    (comp (ref "U7")
      (value "INA226_DGS_10")
      (footprint "eagle-import:DGS10")
      (fields
        (field (name "GENERIC_PART_NUMBER") "INA226")
        (field (name "MANUFACTURER") "Texas Instruments")
        (field (name "MANUFACTURER_PART_NUMBER") "ina226_dgs_10")
      )
      (libsource (lib "eagle-import") (part "INA226_DGS_10"))
    )
    (comp (ref "U8")
      (value "INA226_DGS_10")
      (footprint "eagle-import:DGS10")
      (fields
        (field (name "GENERIC_PART_NUMBER") "INA226")
        (field (name "MANUFACTURER") "Texas Instruments")
        (field (name "MANUFACTURER_PART_NUMBER") "ina226_dgs_10")
      )
      (libsource (lib "eagle-import") (part "INA226_DGS_10"))
    )
    (comp (ref "C186")
      (value "0.1uF")
      (footprint "eagle-import:0402")
      (libsource (lib "eagle-import") (part "CAPACITOR.0402"))
    )
    (comp (ref "C187")
      (value "0.1uF")
      (footprint "eagle-import:0402")
      (libsource (lib "eagle-import") (part "CAPACITOR.0402"))
    )
    (comp (ref "C188")
      (value "0.1uF")
      (footprint "eagle-import:0402")
      (libsource (lib "eagle-import") (part "CAPACITOR.0402"))
    )
    (comp (ref "C189")
      (value "0.1uF")
      (footprint "eagle-import:0402")
      (libsource (lib "eagle-import") (part "CAPACITOR.0402"))
    )
    (comp (ref "C190")
      (value "0.1uF")
      (footprint "eagle-import:0402")
      (libsource (lib "eagle-import") (part "CAPACITOR.0402"))
    )
    (comp (ref "C201")
      (value "0.1uF")
      (footprint "eagle-import:0402")
      (libsource (lib "eagle-import") (part "CAPACITOR.0402"))
    )
    (comp (ref "C202")
      (value "1uF")
      (footprint "eagle-import:0402")
      (libsource (lib "eagle-import") (part "CAPACITOR.0402"))
    )
    (comp (ref "C203")
      (value "1uF")
      (footprint "eagle-import:0402")
      (libsource (lib "eagle-import") (part "CAPACITOR.0402"))
    )
    (comp (ref "C204")
      (value "1uF")
      (footprint "eagle-import:0402")
      (libsource (lib "eagle-import") (part "CAPACITOR.0402"))
    )
    (comp (ref "C205")
      (value "1uF")
      (footprint "eagle-import:0402")
      (libsource (lib "eagle-import") (part "CAPACITOR.0402"))
    )
    (comp (ref "C206")
      (value "1uF")
      (footprint "eagle-import:0402")
      (libsource (lib "eagle-import") (part "CAPACITOR.0402"))
    )
    (comp (ref "C207")
      (value "1uF")
      (footprint "eagle-import:0402")
      (libsource (lib "eagle-import") (part "CAPACITOR.0402"))
    )
    (comp (ref "C208")
      (value "1uF")
      (footprint "eagle-import:0402")
      (libsource (lib "eagle-import") (part "CAPACITOR.0402"))
    )
    (comp (ref "C209")
      (value "10uF")
      (footprint "eagle-import:0603")
      (libsource (lib "eagle-import") (part "CAPACITOR.0603"))
    )
    (comp (ref "C210")
      (value "10uF")
      (footprint "eagle-import:0603")
      (libsource (lib "eagle-import") (part "CAPACITOR.0603"))
    )
    (comp (ref "C211")
      (value "10uF")
      (footprint "eagle-import:0603")
      (libsource (lib "eagle-import") (part "CAPACITOR.0603"))
    )
    (comp (ref "C212")
      (value "1000pF")
      (footprint "eagle-import:0402")
      (libsource (lib "eagle-import") (part "CAPACITOR.0402"))
    )
    (comp (ref "D1")
      (value "Green")
      (footprint "eagle-import:0603.LED")
      (libsource (lib "eagle-import") (part "LED.0603"))
    )
    (comp (ref "HDMI")
      (value "HDMI-A")
      (footprint "eagle-import:HDMI_A")
      (libsource (lib "eagle-import") (part "HDMI-A"))
    )
    (comp (ref "R79")
      (value "510R")
      (footprint "eagle-import:0402")
      (libsource (lib "eagle-import") (part "RESISTOR.0402"))
    )
    (comp (ref "R80")
      (value "1k")
      (footprint "eagle-import:0402")
      (libsource (lib "eagle-import") (part "RESISTOR.0402"))
    )
    (comp (ref "R81")
      (value "330R")
      (footprint "eagle-import:0402")
      (libsource (lib "eagle-import") (part "RESISTOR.0402"))
    )
    (comp (ref "R82")
      (value "1M")
      (footprint "eagle-import:0402")
      (libsource (lib "eagle-import") (part "RESISTOR.0402"))
    )
    (comp (ref "U17")
      (value "TFP410_PAP_64")
      (footprint "eagle-import:PAP64_5X5")
      (fields
        (field (name "GENERIC_PART_NUMBER") "TFP410")
        (field (name "MANUFACTURER") "Texas Instruments")
        (field (name "MANUFACTURER_PART_NUMBER") "tfp410_pap_64")
      )
      (libsource (lib "eagle-import") (part "TFP410_PAP_64"))
    )
  )
  (nets
    (net (code "1") (name "ADC_A0") (class "Default")
      (node (ref "C213") (pin "2") (pinfunction "2_2") (pintype "bidirectional"))
      (node (ref "JP3") (pin "1") (pinfunction "1_1") (pintype "passive"))
      (node (ref "U1") (pin "B6") (pinfunction "AIN0_B6") (pintype "passive"))
    )
    (net (code "2") (name "ADC_A1") (class "Default")
      (node (ref "C214") (pin "2") (pinfunction "2_2") (pintype "bidirectional"))
      (node (ref "JP3") (pin "2") (pinfunction "2_2") (pintype "passive"))
      (node (ref "U1") (pin "C7") (pinfunction "AIN1_C7") (pintype "passive"))
    )
    (net (code "3") (name "ADC_A2") (class "Default")
      (node (ref "C215") (pin "2") (pinfunction "2_2") (pintype "bidirectional"))
      (node (ref "JP3") (pin "3") (pinfunction "3_3") (pintype "passive"))
      (node (ref "U1") (pin "B7") (pinfunction "AIN2_B7") (pintype "passive"))
    )
    (net (code "4") (name "ADC_A3") (class "Default")
      (node (ref "C217") (pin "2") (pinfunction "2_2") (pintype "bidirectional"))
      (node (ref "JP3") (pin "4") (pinfunction "4_4") (pintype "passive"))
      (node (ref "U1") (pin "A7") (pinfunction "AIN3_A7") (pintype "passive"))
    )
    (net (code "5") (name "ADC_A4") (class "Default")
      (node (ref "C218") (pin "2") (pinfunction "2_2") (pintype "bidirectional"))
      (node (ref "JP3") (pin "5") (pinfunction "5_5") (pintype "passive"))
      (node (ref "U1") (pin "C8") (pinfunction "AIN4_C8") (pintype "passive"))
    )
    (net (code "6") (name "ADC_A5") (class "Default")
      (node (ref "C219") (pin "2") (pinfunction "2_2") (pintype "bidirectional"))
      (node (ref "JP3") (pin "6") (pinfunction "6_6") (pintype "passive"))
      (node (ref "U1") (pin "B8") (pinfunction "AIN5_B8") (pintype "passive"))
    )
    (net (code "7") (name "ADC_A6") (class "Default")
      (node (ref "C220") (pin "2") (pinfunction "2_2") (pintype "bidirectional"))
      (node (ref "JP3") (pin "7") (pinfunction "7_7") (pintype "passive"))
      (node (ref "U1") (pin "A8") (pinfunction "AIN6_A8") (pintype "passive"))
    )
    (net (code "8") (name "ADC_A7") (class "Default")
      (node (ref "C221") (pin "2") (pinfunction "2_2") (pintype "bidirectional"))
      (node (ref "JP3") (pin "8") (pinfunction "8_8") (pintype "passive"))
      (node (ref "U1") (pin "C9") (pinfunction "AIN7_C9") (pintype "passive"))
    )
    (net (code "9") (name "DCAN1_H") (class "Default")
      (node (ref "J1") (pin "B17") (pinfunction "17_B17") (pintype "bidirectional"))
      (node (ref "R22") (pin "1") (pinfunction "1_1") (pintype "bidirectional"))
      (node (ref "U19") (pin "7") (pinfunction "CANH_7") (pintype "bidirectional"))
    )
    (net (code "10") (name "DCAN1_L") (class "Default")
      (node (ref "J1") (pin "B16") (pinfunction "16_B16") (pintype "bidirectional"))
      (node (ref "R22") (pin "2") (pinfunction "2_2") (pintype "bidirectional"))
      (node (ref "U19") (pin "6") (pinfunction "CANL_6") (pintype "bidirectional"))
    )
    (net (code "11") (name "DCAN1_RX") (class "Default")
      (node (ref "U1") (pin "E17") (pinfunction "UART0_RTSN_E17") (pintype "passive"))
      (node (ref "U19") (pin "4") (pinfunction "RXD_4") (pintype "output"))
    )
    (net (code "12") (name "DCAN1_STB") (class "Default")
      (node (ref "U12") (pin "6") (pinfunction "P05_6") (pintype "bidirectional"))
      (node (ref "U19") (pin "8") (pinfunction "STB_8") (pintype "input"))
    )
    (net (code "13") (name "DCAN1_TX") (class "Default")
      (node (ref "U1") (pin "E18") (pinfunction "UART0_CTSN_E18") (pintype "passive"))
      (node (ref "U19") (pin "1") (pinfunction "TXD_1") (pintype "input"))
    )
    (net (code "14") (name "DDR3_A0") (class "Default")
      (node (ref "R36") (pin "2") (pinfunction "2_2") (pintype "bidirectional"))
      (node (ref "U1") (pin "F3") (pinfunction "DDR_A0_F3") (pintype "passive"))
      (node (ref "U9") (pin "N3") (pinfunction "A0_N3") (pintype "bidirectional"))
    )
    (net (code "15") (name "DDR3_A1") (class "Default")
      (node (ref "R37") (pin "2") (pinfunction "2_2") (pintype "bidirectional"))
      (node (ref "U1") (pin "H1") (pinfunction "DDR_A1_H1") (pintype "passive"))
      (node (ref "U9") (pin "P7") (pinfunction "A1_P7") (pintype "bidirectional"))
    )
    (net (code "16") (name "DDR3_A2") (class "Default")
      (node (ref "R38") (pin "2") (pinfunction "2_2") (pintype "bidirectional"))
      (node (ref "U1") (pin "E4") (pinfunction "DDR_A2_E4") (pintype "passive"))
      (node (ref "U9") (pin "P3") (pinfunction "A2_P3") (pintype "bidirectional"))
    )
    (net (code "17") (name "DDR3_A3") (class "Default")
      (node (ref "R39") (pin "2") (pinfunction "2_2") (pintype "bidirectional"))
      (node (ref "U1") (pin "C3") (pinfunction "DDR_A3_C3") (pintype "passive"))
      (node (ref "U9") (pin "N2") (pinfunction "A3_N2") (pintype "bidirectional"))
    )
    (net (code "18") (name "DDR3_A4") (class "Default")
      (node (ref "R40") (pin "2") (pinfunction "2_2") (pintype "bidirectional"))
      (node (ref "U1") (pin "C2") (pinfunction "DDR_A4_C2") (pintype "passive"))
      (node (ref "U9") (pin "P8") (pinfunction "A4_P8") (pintype "bidirectional"))
    )
    (net (code "19") (name "DDR3_A5") (class "Default")
      (node (ref "R41") (pin "2") (pinfunction "2_2") (pintype "bidirectional"))
      (node (ref "U1") (pin "B1") (pinfunction "DDR_A5_B1") (pintype "passive"))
      (node (ref "U9") (pin "P2") (pinfunction "A5_P2") (pintype "bidirectional"))
    )
    (net (code "20") (name "DDR3_A6") (class "Default")
      (node (ref "R42") (pin "2") (pinfunction "2_2") (pintype "bidirectional"))
      (node (ref "U1") (pin "D5") (pinfunction "DDR_A6_D5") (pintype "passive"))
      (node (ref "U9") (pin "R8") (pinfunction "A6_R8") (pintype "bidirectional"))
    )
    (net (code "21") (name "DDR3_A7") (class "Default")
      (node (ref "R43") (pin "2") (pinfunction "2_2") (pintype "bidirectional"))
      (node (ref "U1") (pin "E2") (pinfunction "DDR_A7_E2") (pintype "passive"))
      (node (ref "U9") (pin "R2") (pinfunction "A7_R2") (pintype "bidirectional"))
    )
    (net (code "22") (name "DDR3_A8") (class "Default")
      (node (ref "R44") (pin "2") (pinfunction "2_2") (pintype "bidirectional"))
      (node (ref "U1") (pin "D4") (pinfunction "DDR_A8_D4") (pintype "passive"))
      (node (ref "U9") (pin "T8") (pinfunction "A8_T8") (pintype "bidirectional"))
    )
    (net (code "23") (name "DDR3_A9") (class "Default")
      (node (ref "R46") (pin "2") (pinfunction "2_2") (pintype "bidirectional"))
      (node (ref "U1") (pin "C1") (pinfunction "DDR_A9_C1") (pintype "passive"))
      (node (ref "U9") (pin "R3") (pinfunction "A9_R3") (pintype "bidirectional"))
    )
    (net (code "24") (name "DDR3_A10") (class "Default")
      (node (ref "R45") (pin "2") (pinfunction "2_2") (pintype "bidirectional"))
      (node (ref "U1") (pin "F4") (pinfunction "DDR_A10_F4") (pintype "passive"))
      (node (ref "U9") (pin "L7") (pinfunction "A10/AP_L7") (pintype "bidirectional"))
    )
    (net (code "25") (name "DDR3_A11") (class "Default")
      (node (ref "R47") (pin "2") (pinfunction "2_2") (pintype "bidirectional"))
      (node (ref "U1") (pin "F2") (pinfunction "DDR_A11_F2") (pintype "passive"))
      (node (ref "U9") (pin "R7") (pinfunction "A11_R7") (pintype "bidirectional"))
    )
    (net (code "26") (name "DDR3_A12") (class "Default")
      (node (ref "R48") (pin "2") (pinfunction "2_2") (pintype "bidirectional"))
      (node (ref "U1") (pin "E3") (pinfunction "DDR_A12_E3") (pintype "passive"))
      (node (ref "U9") (pin "N7") (pinfunction "A12/~{BC}_N7") (pintype "bidirectional"))
    )
    (net (code "27") (name "DDR3_A13") (class "Default")
      (node (ref "R49") (pin "2") (pinfunction "2_2") (pintype "bidirectional"))
      (node (ref "U1") (pin "H3") (pinfunction "DDR_A13_H3") (pintype "passive"))
      (node (ref "U9") (pin "T3") (pinfunction "A13_T3") (pintype "bidirectional"))
    )
    (net (code "28") (name "DDR3_A14") (class "Default")
      (node (ref "R50") (pin "2") (pinfunction "2_2") (pintype "bidirectional"))
      (node (ref "U1") (pin "H4") (pinfunction "DDR_A14_H4") (pintype "passive"))
      (node (ref "U9") (pin "T7") (pinfunction "A14_T7") (pintype "bidirectional"))
    )
    (net (code "29") (name "DDR3_A15") (class "Default")
      (node (ref "U1") (pin "D3") (pinfunction "DDR_A15_D3") (pintype "passive"))
    )
    (net (code "30") (name "DDR3_BA0") (class "Default")
      (node (ref "R33") (pin "2") (pinfunction "2_2") (pintype "bidirectional"))
      (node (ref "U1") (pin "C4") (pinfunction "DDR_BA0_C4") (pintype "passive"))
      (node (ref "U9") (pin "M2") (pinfunction "BA0_M2") (pintype "bidirectional"))
    )
    (net (code "31") (name "DDR3_BA1") (class "Default")
      (node (ref "R34") (pin "2") (pinfunction "2_2") (pintype "bidirectional"))
      (node (ref "U1") (pin "E1") (pinfunction "DDR_BA1_E1") (pintype "passive"))
      (node (ref "U9") (pin "N8") (pinfunction "BA1_N8") (pintype "bidirectional"))
    )
    (net (code "32") (name "DDR3_BA2") (class "Default")
      (node (ref "R35") (pin "2") (pinfunction "2_2") (pintype "bidirectional"))
      (node (ref "U1") (pin "B3") (pinfunction "DDR_BA2_B3") (pintype "passive"))
      (node (ref "U9") (pin "M3") (pinfunction "BA2_M3") (pintype "bidirectional"))
    )
    (net (code "33") (name "DDR3_CKE") (class "Default")
      (node (ref "R27") (pin "2") (pinfunction "2_2") (pintype "bidirectional"))
      (node (ref "U1") (pin "G3") (pinfunction "DDR_CKE_G3") (pintype "passive"))
      (node (ref "U9") (pin "K9") (pinfunction "CKE_K9") (pintype "bidirectional"))
    )
    (net (code "34") (name "DDR3_CK_N") (class "Default")
      (node (ref "R26") (pin "2") (pinfunction "2_2") (pintype "bidirectional"))
      (node (ref "U1") (pin "D1") (pinfunction "DDR_CKN_D1") (pintype "passive"))
      (node (ref "U9") (pin "K7") (pinfunction "~{CK}_K7") (pintype "bidirectional"))
    )
    (net (code "35") (name "DDR3_CK_P") (class "Default")
      (node (ref "R25") (pin "2") (pinfunction "2_2") (pintype "bidirectional"))
      (node (ref "U1") (pin "D2") (pinfunction "DDR_CK_D2") (pintype "passive"))
      (node (ref "U9") (pin "J7") (pinfunction "CK_J7") (pintype "bidirectional"))
    )
    (net (code "36") (name "DDR3_DQ0") (class "Default")
      (node (ref "U1") (pin "M3") (pinfunction "DDR_D0_M3") (pintype "passive"))
      (node (ref "U9") (pin "F7") (pinfunction "DQL1_F7") (pintype "bidirectional"))
    )
    (net (code "37") (name "DDR3_DQ1") (class "Default")
      (node (ref "U1") (pin "M4") (pinfunction "DDR_D1_M4") (pintype "passive"))
      (node (ref "U9") (pin "H7") (pinfunction "DQL7_H7") (pintype "bidirectional"))
    )
    (net (code "38") (name "DDR3_DQ2") (class "Default")
      (node (ref "U1") (pin "N1") (pinfunction "DDR_D2_N1") (pintype "passive"))
      (node (ref "U9") (pin "F2") (pinfunction "DQL2_F2") (pintype "bidirectional"))
    )
    (net (code "39") (name "DDR3_DQ3") (class "Default")
      (node (ref "U1") (pin "N2") (pinfunction "DDR_D3_N2") (pintype "passive"))
      (node (ref "U9") (pin "G2") (pinfunction "DQL6_G2") (pintype "bidirectional"))
    )
    (net (code "40") (name "DDR3_DQ4") (class "Default")
      (node (ref "U1") (pin "N3") (pinfunction "DDR_D4_N3") (pintype "passive"))
      (node (ref "U9") (pin "H3") (pinfunction "DQL4_H3") (pintype "bidirectional"))
    )
    (net (code "41") (name "DDR3_DQ5") (class "Default")
      (node (ref "U1") (pin "N4") (pinfunction "DDR_D5_N4") (pintype "passive"))
      (node (ref "U9") (pin "H8") (pinfunction "DQL5_H8") (pintype "bidirectional"))
    )
    (net (code "42") (name "DDR3_DQ6") (class "Default")
      (node (ref "U1") (pin "P3") (pinfunction "DDR_D6_P3") (pintype "passive"))
      (node (ref "U9") (pin "E3") (pinfunction "DQL0_E3") (pintype "bidirectional"))
    )
    (net (code "43") (name "DDR3_DQ7") (class "Default")
      (node (ref "U1") (pin "P4") (pinfunction "DDR_D7_P4") (pintype "passive"))
      (node (ref "U9") (pin "F8") (pinfunction "DQL3_F8") (pintype "bidirectional"))
    )
    (net (code "44") (name "DDR3_DQ8") (class "Default")
      (node (ref "U1") (pin "J1") (pinfunction "DDR_D8_J1") (pintype "passive"))
      (node (ref "U9") (pin "D7") (pinfunction "DQU0_D7") (pintype "bidirectional"))
    )
    (net (code "45") (name "DDR3_DQ9") (class "Default")
      (node (ref "U1") (pin "K1") (pinfunction "DDR_D9_K1") (pintype "passive"))
      (node (ref "U9") (pin "C2") (pinfunction "DQU3_C2") (pintype "bidirectional"))
    )
    (net (code "46") (name "DDR3_DQ10") (class "Default")
      (node (ref "U1") (pin "K2") (pinfunction "DDR_D10_K2") (pintype "passive"))
      (node (ref "U9") (pin "C3") (pinfunction "DQU1_C3") (pintype "bidirectional"))
    )
    (net (code "47") (name "DDR3_DQ11") (class "Default")
      (node (ref "U1") (pin "K3") (pinfunction "DDR_D11_K3") (pintype "passive"))
      (node (ref "U9") (pin "C8") (pinfunction "DQU2_C8") (pintype "bidirectional"))
    )
    (net (code "48") (name "DDR3_DQ12") (class "Default")
      (node (ref "U1") (pin "K4") (pinfunction "DDR_D12_K4") (pintype "passive"))
      (node (ref "U9") (pin "B8") (pinfunction "DQU6_B8") (pintype "bidirectional"))
    )
    (net (code "49") (name "DDR3_DQ13") (class "Default")
      (node (ref "U1") (pin "L3") (pinfunction "DDR_D13_L3") (pintype "passive"))
      (node (ref "U9") (pin "A3") (pinfunction "DQU7_A3") (pintype "bidirectional"))
    )
    (net (code "50") (name "DDR3_DQ14") (class "Default")
      (node (ref "U1") (pin "L4") (pinfunction "DDR_D14_L4") (pintype "passive"))
      (node (ref "U9") (pin "A7") (pinfunction "DQU4_A7") (pintype "bidirectional"))
    )
    (net (code "51") (name "DDR3_DQ15") (class "Default")
      (node (ref "U1") (pin "M1") (pinfunction "DDR_D15_M1") (pintype "passive"))
      (node (ref "U9") (pin "A2") (pinfunction "DQU5_A2") (pintype "bidirectional"))
    )
    (net (code "52") (name "DDR3_DQM0") (class "Default")
      (node (ref "U1") (pin "M2") (pinfunction "DDR_DQM0_M2") (pintype "passive"))
      (node (ref "U9") (pin "E7") (pinfunction "DML_E7") (pintype "bidirectional"))
    )
    (net (code "53") (name "DDR3_DQM1") (class "Default")
      (node (ref "U1") (pin "J2") (pinfunction "DDR_DQM1_J2") (pintype "passive"))
      (node (ref "U9") (pin "D3") (pinfunction "DMU_D3") (pintype "bidirectional"))
    )
    (net (code "54") (name "DDR3_DQS0_N") (class "Default")
      (node (ref "U1") (pin "P2") (pinfunction "DDR_DQSN0_P2") (pintype "passive"))
      (node (ref "U9") (pin "G3") (pinfunction "~{DQSL}_G3") (pintype "bidirectional"))
    )
    (net (code "55") (name "DDR3_DQS0_P") (class "Default")
      (node (ref "U1") (pin "P1") (pinfunction "DDR_DQS0_P1") (pintype "passive"))
      (node (ref "U9") (pin "F3") (pinfunction "DQSL_F3") (pintype "bidirectional"))
    )
    (net (code "56") (name "DDR3_DQS1_N") (class "Default")
      (node (ref "U1") (pin "L2") (pinfunction "DDR_DQSN1_L2") (pintype "passive"))
      (node (ref "U9") (pin "B7") (pinfunction "~{DQSU}_B7") (pintype "bidirectional"))
    )
    (net (code "57") (name "DDR3_DQS1_P") (class "Default")
      (node (ref "U1") (pin "L1") (pinfunction "DDR_DQS1_L1") (pintype "passive"))
      (node (ref "U9") (pin "C7") (pinfunction "DQSU_C7") (pintype "bidirectional"))
    )
    (net (code "58") (name "DDR3_ODT") (class "Default")
      (node (ref "R29") (pin "2") (pinfunction "2_2") (pintype "bidirectional"))
      (node (ref "U1") (pin "G1") (pinfunction "DDR_ODT_G1") (pintype "passive"))
      (node (ref "U9") (pin "K1") (pinfunction "ODT_K1") (pintype "bidirectional"))
    )
    (net (code "59") (name "DDR_VREF") (class "Default")
      (node (ref "C44") (pin "2") (pinfunction "2_2") (pintype "bidirectional"))
      (node (ref "C58") (pin "2") (pinfunction "2_2") (pintype "bidirectional"))
      (node (ref "C59") (pin "2") (pinfunction "2_2") (pintype "bidirectional"))
      (node (ref "C60") (pin "2") (pinfunction "2_2") (pintype "bidirectional"))
      (node (ref "U1") (pin "J4") (pinfunction "DDR_VREF_J4") (pintype "passive"))
      (node (ref "U6") (pin "7") (pinfunction "VTTREF_7") (pintype "output"))
      (node (ref "U9") (pin "M8") (pinfunction "VREFCA_M8") (pintype "bidirectional"))
    )
    (net (code "60") (name "DDR_VTT") (class "Default")
      (node (ref "C42") (pin "2") (pinfunction "2_2") (pintype "bidirectional"))
      (node (ref "C43") (pin "2") (pinfunction "2_2") (pintype "bidirectional"))
      (node (ref "C64") (pin "2") (pinfunction "2_2") (pintype "bidirectional"))
      (node (ref "C65") (pin "2") (pinfunction "2_2") (pintype "bidirectional"))
      (node (ref "R27") (pin "1") (pinfunction "1_1") (pintype "bidirectional"))
      (node (ref "R28") (pin "1") (pinfunction "1_1") (pintype "bidirectional"))
      (node (ref "R29") (pin "1") (pinfunction "1_1") (pintype "bidirectional"))
      (node (ref "R30") (pin "1") (pinfunction "1_1") (pintype "bidirectional"))
      (node (ref "R31") (pin "1") (pinfunction "1_1") (pintype "bidirectional"))
      (node (ref "R32") (pin "1") (pinfunction "1_1") (pintype "bidirectional"))
      (node (ref "R33") (pin "1") (pinfunction "1_1") (pintype "bidirectional"))
      (node (ref "R34") (pin "1") (pinfunction "1_1") (pintype "bidirectional"))
      (node (ref "R35") (pin "1") (pinfunction "1_1") (pintype "bidirectional"))
      (node (ref "R36") (pin "1") (pinfunction "1_1") (pintype "bidirectional"))
      (node (ref "R37") (pin "1") (pinfunction "1_1") (pintype "bidirectional"))
      (node (ref "R38") (pin "1") (pinfunction "1_1") (pintype "bidirectional"))
      (node (ref "R39") (pin "1") (pinfunction "1_1") (pintype "bidirectional"))
      (node (ref "R40") (pin "1") (pinfunction "1_1") (pintype "bidirectional"))
      (node (ref "R41") (pin "1") (pinfunction "1_1") (pintype "bidirectional"))
      (node (ref "R42") (pin "1") (pinfunction "1_1") (pintype "bidirectional"))
      (node (ref "R43") (pin "1") (pinfunction "1_1") (pintype "bidirectional"))
      (node (ref "R44") (pin "1") (pinfunction "1_1") (pintype "bidirectional"))
      (node (ref "R45") (pin "1") (pinfunction "1_1") (pintype "bidirectional"))
      (node (ref "R46") (pin "1") (pinfunction "1_1") (pintype "bidirectional"))
      (node (ref "R47") (pin "1") (pinfunction "1_1") (pintype "bidirectional"))
      (node (ref "R48") (pin "1") (pinfunction "1_1") (pintype "bidirectional"))
      (node (ref "R49") (pin "1") (pinfunction "1_1") (pintype "bidirectional"))
      (node (ref "R50") (pin "1") (pinfunction "1_1") (pintype "bidirectional"))
      (node (ref "U6") (pin "2") (pinfunction "VTT_2") (pintype "output"))
      (node (ref "U6") (pin "4") (pinfunction "VTTSNS_4") (pintype "input"))
    )
    (net (code "61") (name "DVI_HPD") (class "Default")
      (node (ref "HDMI") (pin "P$19") (pinfunction "HOTPLUG_P$19") (pintype "bidirectional"))
      (node (ref "R80") (pin "1") (pinfunction "1_1") (pintype "bidirectional"))
    )
    (net (code "62") (name "DVI_TX0_N") (class "Default")
      (node (ref "HDMI") (pin "P$9") (pinfunction "DATA0-_P$9") (pintype "bidirectional"))
      (node (ref "U17") (pin "24") (pinfunction "TX0-_24") (pintype "output"))
    )
    (net (code "63") (name "DVI_TX0_P") (class "Default")
      (node (ref "HDMI") (pin "P$7") (pinfunction "DATA0+_P$7") (pintype "bidirectional"))
      (node (ref "U17") (pin "25") (pinfunction "TX0+_25") (pintype "output"))
    )
    (net (code "64") (name "DVI_TX1_N") (class "Default")
      (node (ref "HDMI") (pin "P$6") (pinfunction "DATA1-_P$6") (pintype "bidirectional"))
      (node (ref "U17") (pin "27") (pinfunction "TX1-_27") (pintype "output"))
    )
    (net (code "65") (name "DVI_TX1_P") (class "Default")
      (node (ref "HDMI") (pin "P$4") (pinfunction "DATA1+_P$4") (pintype "bidirectional"))
      (node (ref "U17") (pin "28") (pinfunction "TX1+_28") (pintype "output"))
    )
    (net (code "66") (name "DVI_TX2_N") (class "Default")
      (node (ref "HDMI") (pin "P$3") (pinfunction "DATA2-_P$3") (pintype "bidirectional"))
      (node (ref "U17") (pin "30") (pinfunction "TX2-_30") (pintype "output"))
    )
    (net (code "67") (name "DVI_TX2_P") (class "Default")
      (node (ref "HDMI") (pin "P$1") (pinfunction "DATA2+_P$1") (pintype "bidirectional"))
      (node (ref "U17") (pin "31") (pinfunction "TX2+_31") (pintype "output"))
    )
    (net (code "68") (name "DVI_TXC_N") (class "Default")
      (node (ref "HDMI") (pin "P$12") (pinfunction "CLOCK-_P$12") (pintype "bidirectional"))
      (node (ref "U17") (pin "21") (pinfunction "TXC-_21") (pintype "output"))
    )
    (net (code "69") (name "DVI_TXC_P") (class "Default")
      (node (ref "HDMI") (pin "P$10") (pinfunction "CLOCK+_P$10") (pintype "bidirectional"))
      (node (ref "U17") (pin "22") (pinfunction "TXC+_22") (pintype "output"))
    )
    (net (code "70") (name "ETH_LED_ACT") (class "Default")
      (node (ref "R69") (pin "2") (pinfunction "2_2") (pintype "bidirectional"))
      (node (ref "R70") (pin "1") (pinfunction "1_1") (pintype "bidirectional"))
      (node (ref "U14") (pin "17") (pinfunction "LED_0_AN_0_MLED_17") (pintype "bidirectional"))
      (node (ref "X1") (pin "12") (pinfunction "A-L_12") (pintype "passive"))
    )
    (net (code "71") (name "ETH_LED_LINK") (class "Default")
      (node (ref "R62") (pin "1") (pinfunction "1_1") (pintype "bidirectional"))
      (node (ref "R63") (pin "2") (pinfunction "2_2") (pintype "bidirectional"))
      (node (ref "U14") (pin "24") (pinfunction "CLK_O_24") (pintype "output"))
      (node (ref "X1") (pin "9") (pinfunction "A-R_9") (pintype "passive"))
    )
    (net (code "72") (name "ETH_MDC") (class "Default")
      (node (ref "U1") (pin "M18") (pinfunction "MDC_M18") (pintype "passive"))
      (node (ref "U14") (pin "20") (pinfunction "MDC_20") (pintype "input"))
    )
    (net (code "73") (name "ETH_MDIO") (class "Default")
      (node (ref "R60") (pin "1") (pinfunction "1_1") (pintype "bidirectional"))
      (node (ref "U1") (pin "M17") (pinfunction "MDIO_M17") (pintype "passive"))
      (node (ref "U14") (pin "19") (pinfunction "MDIO_19") (pintype "bidirectional"))
    )
    (net (code "74") (name "EXT_WAKEUP") (class "Default")
      (node (ref "J1") (pin "C7") (pinfunction "7_C7") (pintype "bidirectional"))
      (node (ref "U1") (pin "C5") (pinfunction "EXT_WAKEUP_C5") (pintype "passive"))
      (node (ref "U12") (pin "10") (pinfunction "P10_10") (pintype "bidirectional"))
    )
    (net (code "75") (name "GPIO1_16") (class "Default")
      (node (ref "J1") (pin "C17") (pinfunction "17_C17") (pintype "bidirectional"))
      (node (ref "U1") (pin "R13") (pinfunction "GPMC_A0_R13") (pintype "passive"))
    )
    (net (code "76") (name "GPIO1_20") (class "Default")
      (node (ref "J1") (pin "C18") (pinfunction "18_C18") (pintype "bidirectional"))
      (node (ref "U1") (pin "R14") (pinfunction "GPMC_A4_R14") (pintype "passive"))
    )
    (net (code "77") (name "GPIO1_21") (class "Default")
      (node (ref "J1") (pin "C19") (pinfunction "19_C19") (pintype "bidirectional"))
      (node (ref "U1") (pin "V15") (pinfunction "GPMC_A5_V15") (pintype "passive"))
    )
    (net (code "78") (name "GPIO1_26") (class "Default")
      (node (ref "J1") (pin "C20") (pinfunction "20_C20") (pintype "bidirectional"))
      (node (ref "U1") (pin "T16") (pinfunction "GPMC_A10_T16") (pintype "passive"))
    )
    (net (code "79") (name "GPIO1_27") (class "Default")
      (node (ref "J1") (pin "C21") (pinfunction "21_C21") (pintype "bidirectional"))
      (node (ref "U1") (pin "V17") (pinfunction "GPMC_A11_V17") (pintype "passive"))
    )
    (net (code "80") (name "GPIO1_29") (class "Default")
      (node (ref "J1") (pin "C10") (pinfunction "10_C10") (pintype "bidirectional"))
      (node (ref "U1") (pin "V6") (pinfunction "GPMC_CSN0_V6") (pintype "passive"))
    )
    (net (code "81") (name "GPIO2_4") (class "Default")
      (node (ref "J1") (pin "C9") (pinfunction "9_C9") (pintype "bidirectional"))
      (node (ref "U1") (pin "U6") (pinfunction "GPMC_WEN_U6") (pintype "passive"))
    )
    (net (code "82") (name "GPIO3_7") (class "Default")
      (node (ref "J1") (pin "C16") (pinfunction "16_C16") (pintype "bidirectional"))
      (node (ref "U1") (pin "A15") (pinfunction "XDMA_EVENT_INTR0_A15") (pintype "passive"))
    )
    (net (code "83") (name "GPIO3_8") (class "Default")
      (node (ref "J1") (pin "C15") (pinfunction "15_C15") (pintype "bidirectional"))
      (node (ref "U1") (pin "D14") (pinfunction "XDMA_EVENT_INTR1_D14") (pintype "passive"))
    )
    (net (code "84") (name "GPIO3_18") (class "Default")
      (node (ref "J1") (pin "C11") (pinfunction "11_C11") (pintype "bidirectional"))
      (node (ref "U1") (pin "B12") (pinfunction "MCASP0_ACLKR_B12") (pintype "passive"))
    )
    (net (code "85") (name "GPIO3_19") (class "Default")
      (node (ref "J1") (pin "C12") (pinfunction "12_C12") (pintype "bidirectional"))
      (node (ref "R87") (pin "2") (pinfunction "2_2") (pintype "bidirectional"))
      (node (ref "U1") (pin "C13") (pinfunction "MCASP0_FSR_C13") (pintype "passive"))
    )
    (net (code "86") (name "GPIO3_20") (class "Default")
      (node (ref "J1") (pin "C13") (pinfunction "13_C13") (pintype "bidirectional"))
      (node (ref "U1") (pin "D13") (pinfunction "MCASP0_AXR1_D13") (pintype "passive"))
    )
    (net (code "87") (name "GPIO3_21") (class "Default")
      (node (ref "J1") (pin "C14") (pinfunction "14_C14") (pintype "bidirectional"))
      (node (ref "U1") (pin "A14") (pinfunction "MCASP0_AHCLKX_A14") (pintype "passive"))
    )
    (net (code "88") (name "INA_ALERT") (class "Default")
      (node (ref "U12") (pin "1") (pinfunction "P00_1") (pintype "bidirectional"))
      (node (ref "U3") (pin "3") (pinfunction "ALERT_3") (pintype "output"))
      (node (ref "U5") (pin "3") (pinfunction "ALERT_3") (pintype "output"))
      (node (ref "U7") (pin "3") (pinfunction "ALERT_3") (pintype "output"))
      (node (ref "U8") (pin "3") (pinfunction "ALERT_3") (pintype "output"))
    )
    (net (code "89") (name "JTAG_EMU0") (class "Default")
      (node (ref "JP1") (pin "13") (pinfunction "13_13") (pintype "passive"))
      (node (ref "U1") (pin "C14") (pinfunction "EMU0_C14") (pintype "passive"))
    )
    (net (code "90") (name "JTAG_EMU1") (class "Default")
      (node (ref "JP1") (pin "14") (pinfunction "14_14") (pintype "passive"))
      (node (ref "U1") (pin "B14") (pinfunction "EMU1_B14") (pintype "passive"))
    )
    (net (code "91") (name "JTAG_TCK") (class "Default")
      (node (ref "JP1") (pin "11") (pinfunction "11_11") (pintype "passive"))
      (node (ref "R59") (pin "1") (pinfunction "1_1") (pintype "bidirectional"))
      (node (ref "U1") (pin "A12") (pinfunction "TCK_A12") (pintype "passive"))
    )
    (net (code "92") (name "JTAG_TDI") (class "Default")
      (node (ref "JP1") (pin "3") (pinfunction "3_3") (pintype "passive"))
      (node (ref "R58") (pin "2") (pinfunction "2_2") (pintype "bidirectional"))
      (node (ref "U1") (pin "B11") (pinfunction "TDI_B11") (pintype "passive"))
    )
    (net (code "93") (name "JTAG_TDO") (class "Default")
      (node (ref "JP1") (pin "7") (pinfunction "7_7") (pintype "passive"))
      (node (ref "U1") (pin "A11") (pinfunction "TDO_A11") (pintype "passive"))
    )
    (net (code "94") (name "JTAG_TMS") (class "Default")
      (node (ref "JP1") (pin "1") (pinfunction "1_1") (pintype "passive"))
      (node (ref "R56") (pin "1") (pinfunction "1_1") (pintype "bidirectional"))
      (node (ref "U1") (pin "C11") (pinfunction "TMS_C11") (pintype "passive"))
    )
    (net (code "95") (name "LCD_AC_BIAS_EN") (class "Default")
      (node (ref "U1") (pin "R6") (pinfunction "LCD_AC_BIAS_EN_R6") (pintype "passive"))
      (node (ref "U17") (pin "2") (pinfunction "DE_2") (pintype "input"))
    )
    (net (code "96") (name "LCD_DATA0") (class "Default")
      (node (ref "U1") (pin "R1") (pinfunction "LCD_DATA0_R1") (pintype "passive"))
      (node (ref "U17") (pin "63") (pinfunction "DATA0_63") (pintype "input"))
    )
    (net (code "97") (name "LCD_DATA1") (class "Default")
      (node (ref "U1") (pin "R2") (pinfunction "LCD_DATA1_R2") (pintype "passive"))
      (node (ref "U17") (pin "62") (pinfunction "DATA1_62") (pintype "input"))
    )
    (net (code "98") (name "LCD_DATA2") (class "Default")
      (node (ref "U1") (pin "R3") (pinfunction "LCD_DATA2_R3") (pintype "passive"))
      (node (ref "U17") (pin "61") (pinfunction "DATA2_61") (pintype "input"))
    )
    (net (code "99") (name "LCD_DATA3") (class "Default")
      (node (ref "U1") (pin "R4") (pinfunction "LCD_DATA3_R4") (pintype "passive"))
      (node (ref "U17") (pin "60") (pinfunction "DATA3_60") (pintype "input"))
    )
    (net (code "100") (name "LCD_DATA4") (class "Default")
      (node (ref "U1") (pin "T1") (pinfunction "LCD_DATA4_T1") (pintype "passive"))
      (node (ref "U17") (pin "59") (pinfunction "DATA4_59") (pintype "input"))
    )
    (net (code "101") (name "LCD_DATA5") (class "Default")
      (node (ref "U1") (pin "T2") (pinfunction "LCD_DATA5_T2") (pintype "passive"))
      (node (ref "U17") (pin "58") (pinfunction "DATA5_58") (pintype "input"))
    )
    (net (code "102") (name "LCD_DATA6") (class "Default")
      (node (ref "U1") (pin "T3") (pinfunction "LCD_DATA6_T3") (pintype "passive"))
      (node (ref "U17") (pin "55") (pinfunction "DATA6_55") (pintype "input"))
    )
    (net (code "103") (name "LCD_DATA7") (class "Default")
      (node (ref "U1") (pin "T4") (pinfunction "LCD_DATA7_T4") (pintype "passive"))
      (node (ref "U17") (pin "54") (pinfunction "DATA7_54") (pintype "input"))
    )
    (net (code "104") (name "LCD_DATA8") (class "Default")
      (node (ref "U1") (pin "U1") (pinfunction "LCD_DATA8_U1") (pintype "passive"))
      (node (ref "U17") (pin "53") (pinfunction "DATA8_53") (pintype "input"))
    )
    (net (code "105") (name "LCD_DATA9") (class "Default")
      (node (ref "U1") (pin "U2") (pinfunction "LCD_DATA9_U2") (pintype "passive"))
      (node (ref "U17") (pin "52") (pinfunction "DATA9_52") (pintype "input"))
    )
    (net (code "106") (name "LCD_DATA10") (class "Default")
      (node (ref "U1") (pin "U3") (pinfunction "LCD_DATA10_U3") (pintype "passive"))
      (node (ref "U17") (pin "51") (pinfunction "DATA10_51") (pintype "input"))
    )
    (net (code "107") (name "LCD_DATA11") (class "Default")
      (node (ref "U1") (pin "U4") (pinfunction "LCD_DATA11_U4") (pintype "passive"))
      (node (ref "U17") (pin "50") (pinfunction "DATA11_50") (pintype "input"))
    )
    (net (code "108") (name "LCD_DATA12") (class "Default")
      (node (ref "U1") (pin "V2") (pinfunction "LCD_DATA12_V2") (pintype "passive"))
      (node (ref "U17") (pin "47") (pinfunction "DATA12_47") (pintype "input"))
    )
    (net (code "109") (name "LCD_DATA13") (class "Default")
      (node (ref "U1") (pin "V3") (pinfunction "LCD_DATA13_V3") (pintype "passive"))
      (node (ref "U17") (pin "46") (pinfunction "DATA13_46") (pintype "input"))
    )
    (net (code "110") (name "LCD_DATA14") (class "Default")
      (node (ref "U1") (pin "V4") (pinfunction "LCD_DATA14_V4") (pintype "passive"))
      (node (ref "U17") (pin "45") (pinfunction "DATA14_45") (pintype "input"))
    )
    (net (code "111") (name "LCD_DATA15") (class "Default")
      (node (ref "U1") (pin "T5") (pinfunction "LCD_DATA15_T5") (pintype "passive"))
      (node (ref "U17") (pin "44") (pinfunction "DATA15_44") (pintype "input"))
    )
    (net (code "112") (name "LCD_DATA16") (class "Default")
      (node (ref "U1") (pin "U13") (pinfunction "GPMC_AD15_U13") (pintype "passive"))
      (node (ref "U17") (pin "43") (pinfunction "DATA16_43") (pintype "input"))
    )
    (net (code "113") (name "LCD_DATA17") (class "Default")
      (node (ref "U1") (pin "V13") (pinfunction "GPMC_AD14_V13") (pintype "passive"))
      (node (ref "U17") (pin "42") (pinfunction "DATA17_42") (pintype "input"))
    )
    (net (code "114") (name "LCD_DATA18") (class "Default")
      (node (ref "U1") (pin "R12") (pinfunction "GPMC_AD13_R12") (pintype "passive"))
      (node (ref "U17") (pin "41") (pinfunction "DATA18_41") (pintype "input"))
    )
    (net (code "115") (name "LCD_DATA19") (class "Default")
      (node (ref "U1") (pin "T12") (pinfunction "GPMC_AD12_T12") (pintype "passive"))
      (node (ref "U17") (pin "40") (pinfunction "DATA19_40") (pintype "input"))
    )
    (net (code "116") (name "LCD_DATA20") (class "Default")
      (node (ref "U1") (pin "U12") (pinfunction "GPMC_AD11_U12") (pintype "passive"))
      (node (ref "U17") (pin "39") (pinfunction "DATA20_39") (pintype "input"))
    )
    (net (code "117") (name "LCD_DATA21") (class "Default")
      (node (ref "U1") (pin "T11") (pinfunction "GPMC_AD10_T11") (pintype "passive"))
      (node (ref "U17") (pin "38") (pinfunction "DATA21_38") (pintype "input"))
    )
    (net (code "118") (name "LCD_DATA22") (class "Default")
      (node (ref "U1") (pin "T10") (pinfunction "GPMC_AD9_T10") (pintype "passive"))
      (node (ref "U17") (pin "37") (pinfunction "DATA22_37") (pintype "input"))
    )
    (net (code "119") (name "LCD_DATA23") (class "Default")
      (node (ref "U1") (pin "U10") (pinfunction "GPMC_AD8_U10") (pintype "passive"))
      (node (ref "U17") (pin "36") (pinfunction "DATA23_36") (pintype "input"))
    )
    (net (code "120") (name "LCD_HSYNC") (class "Default")
      (node (ref "U1") (pin "R5") (pinfunction "LCD_HSYNC_R5") (pintype "passive"))
      (node (ref "U17") (pin "4") (pinfunction "HSYNC_4") (pintype "input"))
    )
    (net (code "121") (name "LCD_PCLK") (class "Default")
      (node (ref "U1") (pin "V5") (pinfunction "LCD_PCLK_V5") (pintype "passive"))
      (node (ref "U17") (pin "57") (pinfunction "IDCK+_57") (pintype "input"))
    )
    (net (code "122") (name "LCD_VSYNC") (class "Default")
      (node (ref "U1") (pin "U5") (pinfunction "LCD_VSYNC_U5") (pintype "passive"))
      (node (ref "U17") (pin "5") (pinfunction "VSYNC_5") (pintype "input"))
    )
    (net (code "123") (name "MMC0_CD") (class "Default")
      (node (ref "T1") (pin "CD1") (pinfunction "SHIELD_CD1") (pintype "bidirectional"))
      (node (ref "T1") (pin "CD2") (pinfunction "SHIELD_CD2") (pintype "bidirectional"))
      (node (ref "U1") (pin "C15") (pinfunction "SPI0_CS1_C15") (pintype "passive"))
      (node (ref "U18") (pin "5") (pinfunction "IO4_5") (pintype "passive"))
    )
    (net (code "124") (name "MMC0_CLK") (class "Default")
      (node (ref "T1") (pin "5") (pinfunction "SCK_5") (pintype "bidirectional"))
      (node (ref "U1") (pin "G17") (pinfunction "MMC0_CLK_G17") (pintype "passive"))
    )
    (net (code "125") (name "MMC0_CMD") (class "Default")
      (node (ref "T1") (pin "3") (pinfunction "DI_3") (pintype "bidirectional"))
      (node (ref "U1") (pin "G18") (pinfunction "MMC0_CMD_G18") (pintype "passive"))
    )
    (net (code "126") (name "MMC0_DAT0") (class "Default")
      (node (ref "T1") (pin "7") (pinfunction "DO_7") (pintype "bidirectional"))
      (node (ref "U1") (pin "G16") (pinfunction "MMC0_DAT0_G16") (pintype "passive"))
    )
    (net (code "127") (name "MMC0_DAT1") (class "Default")
      (node (ref "T1") (pin "8") (pinfunction "RSV_8") (pintype "bidirectional"))
      (node (ref "U1") (pin "G15") (pinfunction "MMC0_DAT1_G15") (pintype "passive"))
    )
    (net (code "128") (name "MMC0_DAT2") (class "Default")
      (node (ref "T1") (pin "1") (pinfunction "NC_1") (pintype "bidirectional"))
      (node (ref "U1") (pin "F18") (pinfunction "MMC0_DAT2_F18") (pintype "passive"))
    )
    (net (code "129") (name "MMC0_DAT3") (class "Default")
      (node (ref "T1") (pin "2") (pinfunction "CS_2") (pintype "bidirectional"))
      (node (ref "U1") (pin "F17") (pinfunction "MMC0_DAT3_F17") (pintype "passive"))
    )
    (net (code "130") (name "MMC0_WP") (class "Default")
      (node (ref "R85") (pin "2") (pinfunction "2_2") (pintype "bidirectional"))
      (node (ref "R86") (pin "1") (pinfunction "1_1") (pintype "bidirectional"))
      (node (ref "U1") (pin "C18") (pinfunction "ECAP0_IN_PWM0_OUT_C18") (pintype "passive"))
    )
    (net (code "131") (name "MMC1_CLK") (class "Default")
      (node (ref "U$10") (pin "M6") (pinfunction "CLK_M6") (pintype "bidirectional"))
      (node (ref "U1") (pin "U9") (pinfunction "GPMC_CSN1_U9") (pintype "passive"))
    )
    (net (code "132") (name "MMC1_CMD") (class "Default")
      (node (ref "U$10") (pin "M5") (pinfunction "CMD_M5") (pintype "bidirectional"))
      (node (ref "U1") (pin "V9") (pinfunction "GPMC_CSN2_V9") (pintype "passive"))
    )
    (net (code "133") (name "MMC1_DAT0") (class "Default")
      (node (ref "U$10") (pin "A3") (pinfunction "DAT0_A3") (pintype "bidirectional"))
      (node (ref "U1") (pin "U7") (pinfunction "GPMC_AD0_U7") (pintype "passive"))
    )
    (net (code "134") (name "MMC1_DAT1") (class "Default")
      (node (ref "U$10") (pin "A4") (pinfunction "DAT1_A4") (pintype "bidirectional"))
      (node (ref "U1") (pin "V7") (pinfunction "GPMC_AD1_V7") (pintype "passive"))
    )
    (net (code "135") (name "MMC1_DAT2") (class "Default")
      (node (ref "U$10") (pin "A5") (pinfunction "DAT2_A5") (pintype "bidirectional"))
      (node (ref "U1") (pin "R8") (pinfunction "GPMC_AD2_R8") (pintype "passive"))
    )
    (net (code "136") (name "MMC1_DAT3") (class "Default")
      (node (ref "U$10") (pin "B2") (pinfunction "DAT3_B2") (pintype "bidirectional"))
      (node (ref "U1") (pin "T8") (pinfunction "GPMC_AD3_T8") (pintype "passive"))
    )
    (net (code "137") (name "MMC1_DAT4") (class "Default")
      (node (ref "U$10") (pin "B3") (pinfunction "DAT4_B3") (pintype "bidirectional"))
      (node (ref "U1") (pin "U8") (pinfunction "GPMC_AD4_U8") (pintype "passive"))
    )
    (net (code "138") (name "MMC1_DAT5") (class "Default")
      (node (ref "U$10") (pin "B4") (pinfunction "DAT5_B4") (pintype "bidirectional"))
      (node (ref "U1") (pin "V8") (pinfunction "GPMC_AD5_V8") (pintype "passive"))
    )
    (net (code "139") (name "MMC1_DAT6") (class "Default")
      (node (ref "U$10") (pin "B5") (pinfunction "DAT6_B5") (pintype "bidirectional"))
      (node (ref "U1") (pin "R9") (pinfunction "GPMC_AD6_R9") (pintype "passive"))
    )
    (net (code "140") (name "MMC1_DAT7") (class "Default")
      (node (ref "U$10") (pin "B6") (pinfunction "DAT7_B6") (pintype "bidirectional"))
      (node (ref "U1") (pin "T9") (pinfunction "GPMC_AD7_T9") (pintype "passive"))
    )
    (net (code "141") (name "MMC1_SDCD") (class "Default")
      (node (ref "U1") (pin "T17") (pinfunction "GPMC_WAIT0_T17") (pintype "passive"))
    )
    (net (code "142") (name "MMC2_CLK") (class "Default")
      (node (ref "U$11") (pin "M6") (pinfunction "CLK_M6") (pintype "bidirectional"))
      (node (ref "U1") (pin "V12") (pinfunction "GPMC_CLK_V12") (pintype "passive"))
    )
    (net (code "143") (name "MMC2_CMD") (class "Default")
      (node (ref "U$11") (pin "M5") (pinfunction "CMD_M5") (pintype "bidirectional"))
      (node (ref "U1") (pin "T13") (pinfunction "GPMC_CSN3_T13") (pintype "passive"))
    )
    (net (code "144") (name "MMC2_DAT0") (class "Default")
      (node (ref "U$11") (pin "A3") (pinfunction "DAT0_A3") (pintype "bidirectional"))
      (node (ref "U1") (pin "V14") (pinfunction "GPMC_A1_V14") (pintype "passive"))
    )
    (net (code "145") (name "MMC2_DAT1") (class "Default")
      (node (ref "U$11") (pin "A4") (pinfunction "DAT1_A4") (pintype "bidirectional"))
      (node (ref "U1") (pin "U14") (pinfunction "GPMC_A2_U14") (pintype "passive"))
    )
    (net (code "146") (name "MMC2_DAT2") (class "Default")
      (node (ref "U$11") (pin "A5") (pinfunction "DAT2_A5") (pintype "bidirectional"))
      (node (ref "U1") (pin "T14") (pinfunction "GPMC_A3_T14") (pintype "passive"))
    )
    (net (code "147") (name "MMC2_DAT3") (class "Default")
      (node (ref "U$11") (pin "B2") (pinfunction "DAT3_B2") (pintype "bidirectional"))
      (node (ref "U1") (pin "U18") (pinfunction "GPMC_BEN1_U18") (pintype "passive"))
    )
    (net (code "148") (name "MMC2_DAT4") (class "Default")
      (node (ref "U$11") (pin "B3") (pinfunction "DAT4_B3") (pintype "bidirectional"))
      (node (ref "U1") (pin "U15") (pinfunction "GPMC_A6_U15") (pintype "passive"))
    )
    (net (code "149") (name "MMC2_DAT5") (class "Default")
      (node (ref "U$11") (pin "B4") (pinfunction "DAT5_B4") (pintype "bidirectional"))
      (node (ref "U1") (pin "T15") (pinfunction "GPMC_A7_T15") (pintype "passive"))
    )
    (net (code "150") (name "MMC2_DAT6") (class "Default")
      (node (ref "U$11") (pin "B5") (pinfunction "DAT6_B5") (pintype "bidirectional"))
      (node (ref "U1") (pin "V16") (pinfunction "GPMC_A8_V16") (pintype "passive"))
    )
    (net (code "151") (name "MMC2_DAT7") (class "Default")
      (node (ref "U$11") (pin "B6") (pinfunction "DAT7_B6") (pintype "bidirectional"))
      (node (ref "U1") (pin "U16") (pinfunction "GPMC_A9_U16") (pintype "passive"))
    )
    (net (code "152") (name "MMC2_SDCD") (class "Default")
      (node (ref "U1") (pin "U17") (pinfunction "GPMC_WPN_U17") (pintype "passive"))
    )
    (net (code "153") (name "Net-(C40-Pad1)") (class "Default")
      (node (ref "C40") (pin "1") (pinfunction "1_1") (pintype "bidirectional"))
      (node (ref "R16") (pin "2") (pinfunction "2_2") (pintype "bidirectional"))
      (node (ref "R18") (pin "2") (pinfunction "2_2") (pintype "bidirectional"))
      (node (ref "U$3") (pin "1") (pinfunction "SOURCE_1") (pintype "bidirectional"))
      (node (ref "U$3") (pin "2") (pinfunction "SOURCE_2") (pintype "bidirectional"))
      (node (ref "U$3") (pin "3") (pinfunction "SOURCE_3") (pintype "bidirectional"))
    )
    (net (code "154") (name "Net-(C40-Pad2)") (class "Default")
      (node (ref "C40") (pin "2") (pinfunction "2_2") (pintype "bidirectional"))
      (node (ref "R17") (pin "1") (pinfunction "1_1") (pintype "bidirectional"))
    )
    (net (code "155") (name "Net-(C61-Pad2)") (class "Default")
      (node (ref "C61") (pin "2") (pinfunction "2_2") (pintype "bidirectional"))
      (node (ref "R25") (pin "1") (pinfunction "1_1") (pintype "bidirectional"))
      (node (ref "R26") (pin "1") (pinfunction "1_1") (pintype "bidirectional"))
    )
    (net (code "156") (name "Net-(C135-Pad1)") (class "Default")
      (node (ref "C135") (pin "1") (pinfunction "1_1") (pintype "bidirectional"))
      (node (ref "C136") (pin "2") (pinfunction "2_2") (pintype "bidirectional"))
      (node (ref "R64") (pin "2") (pinfunction "2_2") (pintype "bidirectional"))
      (node (ref "R65") (pin "2") (pinfunction "2_2") (pintype "bidirectional"))
    )
    (net (code "157") (name "Net-(C137-Pad1)") (class "Default")
      (node (ref "C137") (pin "1") (pinfunction "1_1") (pintype "bidirectional"))
      (node (ref "C138") (pin "2") (pinfunction "2_2") (pintype "bidirectional"))
      (node (ref "R66") (pin "2") (pinfunction "2_2") (pintype "bidirectional"))
      (node (ref "R67") (pin "2") (pinfunction "2_2") (pintype "bidirectional"))
    )
    (net (code "158") (name "Net-(C155-Pad2)") (class "Default")
      (node (ref "C155") (pin "2") (pinfunction "2_2") (pintype "bidirectional"))
      (node (ref "R207") (pin "1") (pinfunction "1_1") (pintype "bidirectional"))
    )
    (net (code "159") (name "Net-(C173-Pad1)") (class "Default")
      (node (ref "C173") (pin "1") (pinfunction "1_1") (pintype "bidirectional"))
      (node (ref "R218") (pin "2") (pinfunction "2_2") (pintype "bidirectional"))
    )
    (net (code "160") (name "Net-(C196-Pad1)") (class "Default")
      (node (ref "C196") (pin "1") (pinfunction "1_1") (pintype "bidirectional"))
      (node (ref "R231") (pin "2") (pinfunction "2_2") (pintype "bidirectional"))
    )
    (net (code "161") (name "Net-(C200-Pad2)") (class "Default")
      (node (ref "C200") (pin "2") (pinfunction "2_2") (pintype "bidirectional"))
      (node (ref "R232") (pin "1") (pinfunction "1_1") (pintype "bidirectional"))
      (node (ref "R233") (pin "2") (pinfunction "2_2") (pintype "bidirectional"))
    )
    (net (code "162") (name "Net-(D1-1)") (class "Default")
      (node (ref "D1") (pin "P$1") (pinfunction "1_P$1") (pintype "bidirectional"))
      (node (ref "R81") (pin "1") (pinfunction "1_1") (pintype "bidirectional"))
    )
    (net (code "163") (name "Net-(D2-1)") (class "Default")
      (node (ref "D2") (pin "P$1") (pinfunction "1_P$1") (pintype "bidirectional"))
      (node (ref "R87") (pin "1") (pinfunction "1_1") (pintype "bidirectional"))
    )
    (net (code "164") (name "Net-(D5-1)") (class "Default")
      (node (ref "D5") (pin "P$1") (pinfunction "1_P$1") (pintype "bidirectional"))
      (node (ref "R220") (pin "2") (pinfunction "2_2") (pintype "bidirectional"))
    )
    (net (code "165") (name "Net-(D6-1)") (class "Default")
      (node (ref "D6") (pin "P$1") (pinfunction "1_P$1") (pintype "bidirectional"))
      (node (ref "R219") (pin "2") (pinfunction "2_2") (pintype "bidirectional"))
    )
    (net (code "166") (name "Net-(HDMI-CLOCKSHIELD)") (class "Default")
      (node (ref "C212") (pin "1") (pinfunction "1_1") (pintype "bidirectional"))
      (node (ref "HDMI") (pin "P$11") (pinfunction "CLOCKSHIELD_P$11") (pintype "bidirectional"))
      (node (ref "HDMI") (pin "P$2") (pinfunction "DATA2SHIELD_P$2") (pintype "bidirectional"))
      (node (ref "HDMI") (pin "P$5") (pinfunction "DATA1SHIELD_P$5") (pintype "bidirectional"))
      (node (ref "HDMI") (pin "P$8") (pinfunction "DATA0SHIELD_P$8") (pintype "bidirectional"))
      (node (ref "R82") (pin "2") (pinfunction "2_2") (pintype "bidirectional"))
    )
    (net (code "167") (name "Net-(JP1-Pad9)") (class "Default")
      (node (ref "JP1") (pin "9") (pinfunction "9_9") (pintype "passive"))
      (node (ref "R59") (pin "2") (pinfunction "2_2") (pintype "bidirectional"))
    )
    (net (code "168") (name "Net-(Q8-G)") (class "Default")
      (node (ref "Q8") (pin "4") (pinfunction "G_4") (pintype "passive"))
      (node (ref "R202") (pin "1") (pinfunction "1_1") (pintype "bidirectional"))
      (node (ref "U34") (pin "23") (pinfunction "HOL1_23") (pintype "output"))
    )
    (net (code "169") (name "Net-(Q9-D)") (class "Default")
      (node (ref "C152") (pin "2") (pinfunction "2_2") (pintype "bidirectional"))
      (node (ref "Q8") (pin "1") (pinfunction "S_1") (pintype "passive"))
      (node (ref "Q8") (pin "2") (pinfunction "S_2") (pintype "passive"))
      (node (ref "Q8") (pin "3") (pinfunction "S_3") (pintype "passive"))
      (node (ref "Q9") (pin "5-9") (pinfunction "D_5-9") (pintype "passive"))
      (node (ref "U$22") (pin "P$2") (pinfunction "P$2_P$2") (pintype "bidirectional"))
      (node (ref "U34") (pin "21") (pinfunction "SW1_21") (pintype "power_in"))
    )
    (net (code "170") (name "Net-(Q9-G)") (class "Default")
      (node (ref "Q9") (pin "4") (pinfunction "G_4") (pintype "passive"))
      (node (ref "R203") (pin "1") (pinfunction "1_1") (pintype "bidirectional"))
      (node (ref "R204") (pin "1") (pinfunction "1_1") (pintype "bidirectional"))
    )
    (net (code "171") (name "Net-(Q10-D)") (class "Default")
      (node (ref "C153") (pin "1") (pinfunction "1_1") (pintype "bidirectional"))
      (node (ref "Q10") (pin "5-9") (pinfunction "D_5-9") (pintype "passive"))
      (node (ref "Q11") (pin "1") (pinfunction "S_1") (pintype "passive"))
      (node (ref "Q11") (pin "2") (pinfunction "S_2") (pintype "passive"))
      (node (ref "Q11") (pin "3") (pinfunction "S_3") (pintype "passive"))
      (node (ref "U$25") (pin "P$1") (pinfunction "P$1_P$1") (pintype "bidirectional"))
      (node (ref "U34") (pin "10") (pinfunction "SW2_10") (pintype "power_in"))
    )
    (net (code "172") (name "Net-(Q10-G)") (class "Default")
      (node (ref "Q10") (pin "4") (pinfunction "G_4") (pintype "passive"))
      (node (ref "R212") (pin "2") (pinfunction "2_2") (pintype "bidirectional"))
      (node (ref "R213") (pin "2") (pinfunction "2_2") (pintype "bidirectional"))
    )
    (net (code "173") (name "Net-(Q11-G)") (class "Default")
      (node (ref "Q11") (pin "4") (pinfunction "G_4") (pintype "passive"))
      (node (ref "R211") (pin "1") (pinfunction "1_1") (pintype "bidirectional"))
      (node (ref "U34") (pin "8") (pinfunction "HOL2_8") (pintype "output"))
    )
    (net (code "174") (name "Net-(R205-Pad2)") (class "Default")
      (node (ref "R205") (pin "2") (pinfunction "2_2") (pintype "passive"))
      (node (ref "R214") (pin "2") (pinfunction "2_2") (pintype "bidirectional"))
      (node (ref "U$22") (pin "P$1") (pinfunction "P$1_P$1") (pintype "bidirectional"))
    )
    (net (code "175") (name "Net-(R215-Pad2)") (class "Default")
      (node (ref "R215") (pin "2") (pinfunction "2_2") (pintype "bidirectional"))
      (node (ref "R217") (pin "1") (pinfunction "1_1") (pintype "passive"))
      (node (ref "U$25") (pin "P$2") (pinfunction "P$2_P$2") (pintype "bidirectional"))
    )
    (net (code "176") (name "Net-(U$2-GATE)") (class "Default")
      (node (ref "R13") (pin "2") (pinfunction "2_2") (pintype "bidirectional"))
      (node (ref "U$2") (pin "4") (pinfunction "GATE_4") (pintype "bidirectional"))
    )
    (net (code "177") (name "Net-(U$3-GATE)") (class "Default")
      (node (ref "U$3") (pin "4") (pinfunction "GATE_4") (pintype "bidirectional"))
      (node (ref "U6") (pin "17") (pinfunction "DRVL_17") (pintype "output"))
    )
    (net (code "178") (name "Net-(U$4-P$1)") (class "Default")
      (node (ref "C12") (pin "2") (pinfunction "2_2") (pintype "bidirectional"))
      (node (ref "U$2") (pin "1") (pinfunction "SOURCE_1") (pintype "bidirectional"))
      (node (ref "U$2") (pin "2") (pinfunction "SOURCE_2") (pintype "bidirectional"))
      (node (ref "U$2") (pin "3") (pinfunction "SOURCE_3") (pintype "bidirectional"))
      (node (ref "U$3") (pin "5") (pinfunction "DRAIN_5") (pintype "bidirectional"))
      (node (ref "U$3") (pin "6") (pinfunction "DRAIN_6") (pintype "bidirectional"))
      (node (ref "U$3") (pin "7") (pinfunction "DRAIN_7") (pintype "bidirectional"))
      (node (ref "U$3") (pin "8") (pinfunction "DRAIN_8") (pintype "bidirectional"))
      (node (ref "U$4") (pin "V") (pinfunction "P$1_V") (pintype "bidirectional"))
      (node (ref "U6") (pin "18") (pinfunction "LL_18") (pintype "bidirectional"))
    )
    (net (code "179") (name "Net-(U$5-XI)") (class "Default")
      (node (ref "C121") (pin "2") (pinfunction "2_2") (pintype "bidirectional"))
      (node (ref "U$5") (pin "1") (pinfunction "XI_1") (pintype "bidirectional"))
      (node (ref "U1") (pin "A6") (pinfunction "RTC_XTALIN_A6") (pintype "passive"))
    )
    (net (code "180") (name "Net-(U$5-XO)") (class "Default")
      (node (ref "C122") (pin "2") (pinfunction "2_2") (pintype "bidirectional"))
      (node (ref "U$5") (pin "3") (pinfunction "XO_3") (pintype "bidirectional"))
      (node (ref "U1") (pin "A4") (pinfunction "RTC_XTALOUT_A4") (pintype "passive"))
    )
    (net (code "181") (name "Net-(U$6-XI)") (class "Default")
      (node (ref "C119") (pin "2") (pinfunction "2_2") (pintype "bidirectional"))
      (node (ref "U$6") (pin "1") (pinfunction "XI_1") (pintype "bidirectional"))
      (node (ref "U1") (pin "V10") (pinfunction "XTALIN_V10") (pintype "passive"))
    )
    (net (code "182") (name "Net-(U$6-XO)") (class "Default")
      (node (ref "C120") (pin "2") (pinfunction "2_2") (pintype "bidirectional"))
      (node (ref "U$6") (pin "3") (pinfunction "XO_3") (pintype "bidirectional"))
      (node (ref "U1") (pin "U11") (pinfunction "XTALOUT_U11") (pintype "passive"))
    )
    (net (code "183") (name "Net-(U$7-XI)") (class "Default")
      (node (ref "C238") (pin "2") (pinfunction "2_2") (pintype "bidirectional"))
      (node (ref "U$7") (pin "1") (pinfunction "XI_1") (pintype "bidirectional"))
      (node (ref "U14") (pin "22") (pinfunction "XO_22") (pintype "passive"))
    )
    (net (code "184") (name "Net-(U$7-XO)") (class "Default")
      (node (ref "C239") (pin "2") (pinfunction "2_2") (pintype "bidirectional"))
      (node (ref "R68") (pin "2") (pinfunction "2_2") (pintype "bidirectional"))
      (node (ref "U$7") (pin "3") (pinfunction "XO_3") (pintype "bidirectional"))
    )
    (net (code "185") (name "Net-(U$10-VDDI)") (class "Default")
      (node (ref "C464") (pin "1") (pinfunction "1_1") (pintype "bidirectional"))
      (node (ref "C465") (pin "1") (pinfunction "1_1") (pintype "bidirectional"))
      (node (ref "U$10") (pin "C2") (pinfunction "VDDI_C2") (pintype "bidirectional"))
    )
    (net (code "186") (name "Net-(U$11-VDDI)") (class "Default")
      (node (ref "C228") (pin "1") (pinfunction "1_1") (pintype "bidirectional"))
      (node (ref "C229") (pin "1") (pinfunction "1_1") (pintype "bidirectional"))
      (node (ref "U$11") (pin "C2") (pinfunction "VDDI_C2") (pintype "bidirectional"))
    )
    (net (code "187") (name "Net-(U$12-9)") (class "Default")
      (node (ref "JP2") (pin "1") (pinfunction "1_1") (pintype "passive"))
      (node (ref "U$12") (pin "15") (pinfunction "9_15") (pintype "bidirectional"))
    )
    (net (code "188") (name "Net-(U$12-10)") (class "Default")
      (node (ref "JP2") (pin "2") (pinfunction "2_2") (pintype "passive"))
      (node (ref "U$12") (pin "16") (pinfunction "10_16") (pintype "bidirectional"))
    )
    (net (code "189") (name "Net-(U$12-11)") (class "Default")
      (node (ref "JP2") (pin "3") (pinfunction "3_3") (pintype "passive"))
      (node (ref "U$12") (pin "17") (pinfunction "11_17") (pintype "bidirectional"))
    )
    (net (code "190") (name "Net-(U$12-12)") (class "Default")
      (node (ref "JP2") (pin "4") (pinfunction "4_4") (pintype "passive"))
      (node (ref "U$12") (pin "18") (pinfunction "12_18") (pintype "bidirectional"))
    )
    (net (code "191") (name "Net-(U$12-13)") (class "Default")
      (node (ref "JP2") (pin "5") (pinfunction "5_5") (pintype "passive"))
      (node (ref "U$12") (pin "19") (pinfunction "13_19") (pintype "bidirectional"))
    )
    (net (code "192") (name "Net-(U$12-14)") (class "Default")
      (node (ref "JP2") (pin "6") (pinfunction "6_6") (pintype "passive"))
      (node (ref "U$12") (pin "20") (pinfunction "14_20") (pintype "bidirectional"))
    )
    (net (code "193") (name "Net-(U$12-15)") (class "Default")
      (node (ref "JP2") (pin "7") (pinfunction "7_7") (pintype "passive"))
      (node (ref "U$12") (pin "21") (pinfunction "15_21") (pintype "bidirectional"))
    )
    (net (code "194") (name "Net-(U$12-16)") (class "Default")
      (node (ref "JP2") (pin "8") (pinfunction "8_8") (pintype "passive"))
      (node (ref "U$12") (pin "22") (pinfunction "16_22") (pintype "bidirectional"))
    )
    (net (code "195") (name "Net-(U1A-CAP_VBB_MPU)") (class "Default")
      (node (ref "C88") (pin "1") (pinfunction "1_1") (pintype "bidirectional"))
      (node (ref "U1") (pin "C10") (pinfunction "CAP_VBB_MPU_C10") (pintype "passive"))
    )
    (net (code "196") (name "Net-(U1A-CAP_VDD_RTC)") (class "Default")
      (node (ref "C89") (pin "1") (pinfunction "1_1") (pintype "bidirectional"))
      (node (ref "U1") (pin "D6") (pinfunction "CAP_VDD_RTC_D6") (pintype "power_in"))
    )
    (net (code "197") (name "Net-(U1A-CAP_VDD_SRAM_CORE)") (class "Default")
      (node (ref "C91") (pin "1") (pinfunction "1_1") (pintype "bidirectional"))
      (node (ref "U1") (pin "D9") (pinfunction "CAP_VDD_SRAM_CORE_D9") (pintype "power_in"))
    )
    (net (code "198") (name "Net-(U1A-CAP_VDD_SRAM_MPU)") (class "Default")
      (node (ref "C90") (pin "1") (pinfunction "1_1") (pintype "bidirectional"))
      (node (ref "U1") (pin "D11") (pinfunction "CAP_VDD_SRAM_MPU_D11") (pintype "passive"))
    )
    (net (code "199") (name "Net-(U1A-DDR_VTP)") (class "Default")
      (node (ref "R51") (pin "1") (pinfunction "1_1") (pintype "bidirectional"))
      (node (ref "U1") (pin "J3") (pinfunction "DDR_VTP_J3") (pintype "passive"))
    )
    (net (code "200") (name "Net-(U3-VBUS)") (class "Default")
      (node (ref "C2") (pin "2") (pinfunction "2_2") (pintype "bidirectional"))
      (node (ref "R2") (pin "1") (pinfunction "1_1") (pintype "bidirectional"))
      (node (ref "U3") (pin "8") (pinfunction "VBUS_8") (pintype "input"))
      (node (ref "U3") (pin "9") (pinfunction "VIN-_9") (pintype "input"))
    )
    (net (code "201") (name "Net-(U3-VIN+)") (class "Default")
      (node (ref "C2") (pin "1") (pinfunction "1_1") (pintype "bidirectional"))
      (node (ref "R1") (pin "1") (pinfunction "1_1") (pintype "bidirectional"))
      (node (ref "U3") (pin "10") (pinfunction "VIN+_10") (pintype "input"))
    )
    (net (code "202") (name "Net-(U4-SW)") (class "Default")
      (node (ref "U$1") (pin "P$1") (pinfunction "P$1_P$1") (pintype "bidirectional"))
      (node (ref "U4") (pin "B3") (pinfunction "SW_2_B3") (pintype "power_in"))
      (node (ref "U4") (pin "B4") (pinfunction "SW_B4") (pintype "power_in"))
    )
    (net (code "203") (name "Net-(U5-VBUS)") (class "Default")
      (node (ref "C10") (pin "2") (pinfunction "2_2") (pintype "bidirectional"))
      (node (ref "R5") (pin "1") (pinfunction "1_1") (pintype "bidirectional"))
      (node (ref "U5") (pin "8") (pinfunction "VBUS_8") (pintype "input"))
      (node (ref "U5") (pin "9") (pinfunction "VIN-_9") (pintype "input"))
    )
    (net (code "204") (name "Net-(U5-VIN+)") (class "Default")
      (node (ref "C10") (pin "1") (pinfunction "1_1") (pintype "bidirectional"))
      (node (ref "R4") (pin "1") (pinfunction "1_1") (pintype "bidirectional"))
      (node (ref "U5") (pin "10") (pinfunction "VIN+_10") (pintype "input"))
    )
    (net (code "205") (name "Net-(U6-CS)") (class "Default")
      (node (ref "C39") (pin "2") (pinfunction "2_2") (pintype "bidirectional"))
      (node (ref "R14") (pin "1") (pinfunction "1_1") (pintype "bidirectional"))
      (node (ref "U6") (pin "15") (pinfunction "CS_15") (pintype "bidirectional"))
    )
    (net (code "206") (name "Net-(U6-DRVH)") (class "Default")
      (node (ref "R13") (pin "1") (pinfunction "1_1") (pintype "bidirectional"))
      (node (ref "U6") (pin "19") (pinfunction "DRVH_19") (pintype "output"))
    )
    (net (code "207") (name "Net-(U6-VBST)") (class "Default")
      (node (ref "C12") (pin "1") (pinfunction "1_1") (pintype "bidirectional"))
      (node (ref "U6") (pin "20") (pinfunction "VBST_20") (pintype "bidirectional"))
    )
    (net (code "208") (name "Net-(U6-VDDQSET)") (class "Default")
      (node (ref "R19") (pin "1") (pinfunction "1_1") (pintype "bidirectional"))
      (node (ref "R20") (pin "2") (pinfunction "2_2") (pintype "bidirectional"))
      (node (ref "U6") (pin "10") (pinfunction "VDDQSET_10") (pintype "input"))
    )
    (net (code "209") (name "Net-(U7-VBUS)") (class "Default")
      (node (ref "C29") (pin "2") (pinfunction "2_2") (pintype "bidirectional"))
      (node (ref "R8") (pin "1") (pinfunction "1_1") (pintype "bidirectional"))
      (node (ref "U7") (pin "8") (pinfunction "VBUS_8") (pintype "input"))
      (node (ref "U7") (pin "9") (pinfunction "VIN-_9") (pintype "input"))
    )
    (net (code "210") (name "Net-(U7-VIN+)") (class "Default")
      (node (ref "C29") (pin "1") (pinfunction "1_1") (pintype "bidirectional"))
      (node (ref "R7") (pin "1") (pinfunction "1_1") (pintype "bidirectional"))
      (node (ref "U7") (pin "10") (pinfunction "VIN+_10") (pintype "input"))
    )
    (net (code "211") (name "Net-(U8-VBUS)") (class "Default")
      (node (ref "C32") (pin "2") (pinfunction "2_2") (pintype "bidirectional"))
      (node (ref "R11") (pin "1") (pinfunction "1_1") (pintype "bidirectional"))
      (node (ref "U8") (pin "8") (pinfunction "VBUS_8") (pintype "input"))
      (node (ref "U8") (pin "9") (pinfunction "VIN-_9") (pintype "input"))
    )
    (net (code "212") (name "Net-(U8-VIN+)") (class "Default")
      (node (ref "C32") (pin "1") (pinfunction "1_1") (pintype "bidirectional"))
      (node (ref "R10") (pin "1") (pinfunction "1_1") (pintype "bidirectional"))
      (node (ref "U8") (pin "10") (pinfunction "VIN+_10") (pintype "input"))
    )
    (net (code "213") (name "Net-(U9-ZQ)") (class "Default")
      (node (ref "R21") (pin "2") (pinfunction "2_2") (pintype "bidirectional"))
      (node (ref "U9") (pin "L8") (pinfunction "ZQ_L8") (pintype "bidirectional"))
    )
    (net (code "214") (name "Net-(U13-Y)") (class "Default")
      (node (ref "U1") (pin "B5") (pinfunction "RTC_PWRONRSTN_B5") (pintype "passive"))
      (node (ref "U13") (pin "4") (pinfunction "Y_4") (pintype "output"))
    )
    (net (code "215") (name "Net-(U14-RBIAS)") (class "Default")
      (node (ref "R61") (pin "1") (pinfunction "1_1") (pintype "bidirectional"))
      (node (ref "U14") (pin "16") (pinfunction "RBIAS_16") (pintype "passive"))
    )
    (net (code "216") (name "Net-(U14-RD_M)") (class "Default")
      (node (ref "R66") (pin "1") (pinfunction "1_1") (pintype "bidirectional"))
      (node (ref "U14") (pin "9") (pinfunction "RD_M_9") (pintype "bidirectional"))
      (node (ref "X1") (pin "8") (pinfunction "RD-_8") (pintype "input"))
    )
    (net (code "217") (name "Net-(U14-RD_P)") (class "Default")
      (node (ref "R67") (pin "1") (pinfunction "1_1") (pintype "bidirectional"))
      (node (ref "U14") (pin "10") (pinfunction "RD_P_10") (pintype "bidirectional"))
      (node (ref "X1") (pin "7") (pinfunction "RD+_7") (pintype "input"))
    )
    (net (code "218") (name "Net-(U14-RX_CLK)") (class "Default")
      (node (ref "R102") (pin "2") (pinfunction "2_2") (pintype "bidirectional"))
      (node (ref "U14") (pin "25") (pinfunction "RX_CLK_25") (pintype "output"))
    )
    (net (code "219") (name "Net-(U14-RX_D0_PHYAD1)") (class "Default")
      (node (ref "R101") (pin "2") (pinfunction "2_2") (pintype "bidirectional"))
      (node (ref "U14") (pin "30") (pinfunction "RX_D0_PHYAD1_30") (pintype "bidirectional"))
    )
    (net (code "220") (name "Net-(U14-RX_D1_PHYAD2)") (class "Default")
      (node (ref "R100") (pin "2") (pinfunction "2_2") (pintype "bidirectional"))
      (node (ref "U14") (pin "31") (pinfunction "RX_D1_PHYAD2_31") (pintype "bidirectional"))
    )
    (net (code "221") (name "Net-(U14-RX_D2_PHYAD3)") (class "Default")
      (node (ref "R99") (pin "2") (pinfunction "2_2") (pintype "bidirectional"))
      (node (ref "U14") (pin "32") (pinfunction "RX_D2_PHYAD3_32") (pintype "bidirectional"))
    )
    (net (code "222") (name "Net-(U14-RX_D3_PHYAD4_CLKOUT)") (class "Default")
      (node (ref "R53") (pin "2") (pinfunction "2_2") (pintype "bidirectional"))
      (node (ref "U14") (pin "1") (pinfunction "RX_D3_PHYAD4_CLKOUT_1") (pintype "bidirectional"))
    )
    (net (code "223") (name "Net-(U14-TD_M)") (class "Default")
      (node (ref "R65") (pin "1") (pinfunction "1_1") (pintype "bidirectional"))
      (node (ref "U14") (pin "11") (pinfunction "TD_M_11") (pintype "bidirectional"))
      (node (ref "X1") (pin "2") (pinfunction "TD-_2") (pintype "input"))
    )
    (net (code "224") (name "Net-(U14-TD_P)") (class "Default")
      (node (ref "R64") (pin "1") (pinfunction "1_1") (pintype "bidirectional"))
      (node (ref "U14") (pin "12") (pinfunction "TD_P_12") (pintype "bidirectional"))
      (node (ref "X1") (pin "1") (pinfunction "TD+_1") (pintype "input"))
    )
    (net (code "225") (name "Net-(U14-XI)") (class "Default")
      (node (ref "R68") (pin "1") (pinfunction "1_1") (pintype "bidirectional"))
      (node (ref "U14") (pin "23") (pinfunction "XI_23") (pintype "passive"))
    )
    (net (code "226") (name "Net-(U17-EDGE{slash}HTPLG)") (class "Default")
      (node (ref "R80") (pin "2") (pinfunction "2_2") (pintype "bidirectional"))
      (node (ref "U17") (pin "9") (pinfunction "EDGE/HTPLG_9") (pintype "passive"))
    )
    (net (code "227") (name "Net-(U17-MSEN{slash}PO1)") (class "Default")
      (node (ref "R81") (pin "2") (pinfunction "2_2") (pintype "bidirectional"))
      (node (ref "U17") (pin "11") (pinfunction "MSEN/PO1_11") (pintype "output"))
    )
    (net (code "228") (name "Net-(U17-TFADJ)") (class "Default")
      (node (ref "R79") (pin "2") (pinfunction "2_2") (pintype "bidirectional"))
      (node (ref "U17") (pin "19") (pinfunction "TFADJ_19") (pintype "input"))
    )
    (net (code "229") (name "Net-(U18-IO3)") (class "Default")
      (node (ref "C141") (pin "1") (pinfunction "1_1") (pintype "bidirectional"))
      (node (ref "R71") (pin "2") (pinfunction "2_2") (pintype "bidirectional"))
      (node (ref "T1") (pin "GND1") (pinfunction "SHIELD_GND1") (pintype "bidirectional"))
      (node (ref "T1") (pin "GND3") (pinfunction "SHIELD_GND3") (pintype "bidirectional"))
      (node (ref "U18") (pin "4") (pinfunction "IO3_4") (pintype "passive"))
    )
    (net (code "230") (name "Net-(U34-COMP1)") (class "Default")
      (node (ref "C154") (pin "2") (pinfunction "2_2") (pintype "bidirectional"))
      (node (ref "R207") (pin "2") (pinfunction "2_2") (pintype "bidirectional"))
      (node (ref "U34") (pin "29") (pinfunction "COMP1_29") (pintype "output"))
    )
    (net (code "231") (name "Net-(U34-COMP2)") (class "Default")
      (node (ref "C172") (pin "1") (pinfunction "1_1") (pintype "bidirectional"))
      (node (ref "R218") (pin "1") (pinfunction "1_1") (pintype "bidirectional"))
      (node (ref "U34") (pin "2") (pinfunction "COMP2_2") (pintype "output"))
    )
    (net (code "232") (name "Net-(U34-CS1)") (class "Default")
      (node (ref "C169") (pin "1") (pinfunction "1_1") (pintype "bidirectional"))
      (node (ref "R214") (pin "1") (pinfunction "1_1") (pintype "bidirectional"))
      (node (ref "U34") (pin "27") (pinfunction "CS1_27") (pintype "input"))
    )
    (net (code "233") (name "Net-(U34-CS2)") (class "Default")
      (node (ref "C170") (pin "2") (pinfunction "2_2") (pintype "bidirectional"))
      (node (ref "R215") (pin "1") (pinfunction "1_1") (pintype "bidirectional"))
      (node (ref "U34") (pin "4") (pinfunction "CS2_4") (pintype "input"))
    )
    (net (code "234") (name "Net-(U34-HB1)") (class "Default")
      (node (ref "C152") (pin "1") (pinfunction "1_1") (pintype "bidirectional"))
      (node (ref "U$21") (pin "CATHODE") (pinfunction "CATHODE_CATHODE") (pintype "bidirectional"))
      (node (ref "U34") (pin "20") (pinfunction "HB1_20") (pintype "output"))
    )
    (net (code "235") (name "Net-(U34-HB2)") (class "Default")
      (node (ref "C153") (pin "2") (pinfunction "2_2") (pintype "bidirectional"))
      (node (ref "U$20") (pin "CATHODE") (pinfunction "CATHODE_CATHODE") (pintype "bidirectional"))
      (node (ref "U34") (pin "11") (pinfunction "HB2_11") (pintype "output"))
    )
    (net (code "236") (name "Net-(U34-HO1)") (class "Default")
      (node (ref "R202") (pin "2") (pinfunction "2_2") (pintype "bidirectional"))
      (node (ref "U34") (pin "22") (pinfunction "HO1_22") (pintype "output"))
    )
    (net (code "237") (name "Net-(U34-HO2)") (class "Default")
      (node (ref "R211") (pin "2") (pinfunction "2_2") (pintype "bidirectional"))
      (node (ref "U34") (pin "9") (pinfunction "HO2_9") (pintype "output"))
    )
    (net (code "238") (name "Net-(U34-LO1)") (class "Default")
      (node (ref "R203") (pin "2") (pinfunction "2_2") (pintype "bidirectional"))
      (node (ref "U34") (pin "18") (pinfunction "LO1_18") (pintype "output"))
    )
    (net (code "239") (name "Net-(U34-LO2)") (class "Default")
      (node (ref "R213") (pin "1") (pinfunction "1_1") (pintype "bidirectional"))
      (node (ref "U34") (pin "13") (pinfunction "LO2_13") (pintype "output"))
    )
    (net (code "240") (name "Net-(U34-LOL1)") (class "Default")
      (node (ref "R204") (pin "2") (pinfunction "2_2") (pintype "bidirectional"))
      (node (ref "U34") (pin "19") (pinfunction "LOL1_19") (pintype "output"))
    )
    (net (code "241") (name "Net-(U34-LOL2)") (class "Default")
      (node (ref "R212") (pin "1") (pinfunction "1_1") (pintype "bidirectional"))
      (node (ref "U34") (pin "12") (pinfunction "LOL2_12") (pintype "output"))
    )
    (net (code "242") (name "Net-(U34-RES)") (class "Default")
      (node (ref "C151") (pin "2") (pinfunction "2_2") (pintype "bidirectional"))
      (node (ref "U34") (pin "32") (pinfunction "RES_32") (pintype "output"))
    )
    (net (code "243") (name "Net-(U34-SS1)") (class "Default")
      (node (ref "C156") (pin "2") (pinfunction "2_2") (pintype "bidirectional"))
      (node (ref "U34") (pin "30") (pinfunction "SS1_30") (pintype "input"))
    )
    (net (code "244") (name "Net-(U34-SS2)") (class "Default")
      (node (ref "C171") (pin "2") (pinfunction "2_2") (pintype "bidirectional"))
      (node (ref "U34") (pin "1") (pinfunction "SS2_1") (pintype "input"))
    )
    (net (code "245") (name "Net-(U34-VOUT1)") (class "Default")
      (node (ref "C169") (pin "2") (pinfunction "2_2") (pintype "bidirectional"))
      (node (ref "R206") (pin "1") (pinfunction "1_1") (pintype "bidirectional"))
      (node (ref "U34") (pin "26") (pinfunction "VOUT1_26") (pintype "input"))
    )
    (net (code "246") (name "Net-(U34-VOUT2)") (class "Default")
      (node (ref "C170") (pin "1") (pinfunction "1_1") (pintype "bidirectional"))
      (node (ref "R216") (pin "1") (pinfunction "1_1") (pintype "bidirectional"))
      (node (ref "U34") (pin "5") (pinfunction "VOUT2_5") (pintype "input"))
    )
    (net (code "247") (name "Net-(U35-SW)") (class "Default")
      (node (ref "U$28") (pin "P$1") (pinfunction "P$1_P$1") (pintype "bidirectional"))
      (node (ref "U35") (pin "6") (pinfunction "SW_6") (pintype "power_in"))
    )
    (net (code "248") (name "Net-(U38-SW)") (class "Default")
      (node (ref "U$30") (pin "P$1") (pinfunction "P$1_P$1") (pintype "bidirectional"))
      (node (ref "U38") (pin "B3") (pinfunction "SW_2_B3") (pintype "power_in"))
      (node (ref "U38") (pin "B4") (pinfunction "SW_B4") (pintype "power_in"))
    )
    (net (code "249") (name "Net-(U41-BOOT)") (class "Default")
      (node (ref "C195") (pin "1") (pinfunction "1_1") (pintype "bidirectional"))
      (node (ref "U41") (pin "9") (pinfunction "BOOT_9") (pintype "power_in"))
    )
    (net (code "250") (name "Net-(U41-COMP)") (class "Default")
      (node (ref "C197") (pin "1") (pinfunction "1_1") (pintype "bidirectional"))
      (node (ref "R231") (pin "1") (pinfunction "1_1") (pintype "bidirectional"))
      (node (ref "U41") (pin "7") (pinfunction "COMP_7") (pintype "bidirectional"))
    )
    (net (code "251") (name "Net-(U41-PH)") (class "Default")
      (node (ref "C195") (pin "2") (pinfunction "2_2") (pintype "bidirectional"))
      (node (ref "U$33") (pin "P$1") (pinfunction "P$1_P$1") (pintype "bidirectional"))
      (node (ref "U41") (pin "2") (pinfunction "PH_2") (pintype "power_in"))
    )
    (net (code "252") (name "Net-(U76-SENSE)") (class "Default")
      (node (ref "C575") (pin "1") (pinfunction "1_1") (pintype "bidirectional"))
      (node (ref "R536") (pin "1") (pinfunction "1_1") (pintype "bidirectional"))
      (node (ref "R537") (pin "2") (pinfunction "2_2") (pintype "bidirectional"))
      (node (ref "U76") (pin "3") (pinfunction "SENSE_3") (pintype "input"))
    )
    (net (code "253") (name "Net-(U77-CT)") (class "Default")
      (node (ref "C577") (pin "1") (pinfunction "1_1") (pintype "bidirectional"))
      (node (ref "U77") (pin "5") (pinfunction "CT_5") (pintype "passive"))
    )
    (net (code "254") (name "Net-(U77-SENSE)") (class "Default")
      (node (ref "R540") (pin "1") (pinfunction "1_1") (pintype "bidirectional"))
      (node (ref "R541") (pin "2") (pinfunction "2_2") (pintype "bidirectional"))
      (node (ref "U77") (pin "3") (pinfunction "SENSE_3") (pintype "passive"))
    )
    (net (code "255") (name "Net-(U78-Y)") (class "Default")
      (node (ref "R543") (pin "1") (pinfunction "1_1") (pintype "bidirectional"))
      (node (ref "U78") (pin "4") (pinfunction "Y_4") (pintype "output"))
    )
    (net (code "256") (name "PWM0") (class "Default")
      (node (ref "J1") (pin "A30") (pinfunction "30_A30") (pintype "bidirectional"))
      (node (ref "U$12") (pin "6") (pinfunction "1_6") (pintype "bidirectional"))
    )
    (net (code "257") (name "PWM1") (class "Default")
      (node (ref "J1") (pin "A31") (pinfunction "31_A31") (pintype "bidirectional"))
      (node (ref "U$12") (pin "7") (pinfunction "2_7") (pintype "bidirectional"))
    )
    (net (code "258") (name "PWM2") (class "Default")
      (node (ref "J1") (pin "A32") (pinfunction "32_A32") (pintype "bidirectional"))
      (node (ref "U$12") (pin "8") (pinfunction "3_8") (pintype "bidirectional"))
    )
    (net (code "259") (name "PWM3") (class "Default")
      (node (ref "J1") (pin "A33") (pinfunction "33_A33") (pintype "bidirectional"))
      (node (ref "U$12") (pin "9") (pinfunction "4_9") (pintype "bidirectional"))
    )
    (net (code "260") (name "PWM4") (class "Default")
      (node (ref "J1") (pin "A34") (pinfunction "34_A34") (pintype "bidirectional"))
      (node (ref "U$12") (pin "10") (pinfunction "5_10") (pintype "bidirectional"))
    )
    (net (code "261") (name "PWM5") (class "Default")
      (node (ref "J1") (pin "A35") (pinfunction "35_A35") (pintype "bidirectional"))
      (node (ref "U$12") (pin "11") (pinfunction "6_11") (pintype "bidirectional"))
    )
    (net (code "262") (name "PWM6") (class "Default")
      (node (ref "J1") (pin "A36") (pinfunction "36_A36") (pintype "bidirectional"))
      (node (ref "U$12") (pin "12") (pinfunction "7_12") (pintype "bidirectional"))
    )
    (net (code "263") (name "PWM7") (class "Default")
      (node (ref "J1") (pin "A37") (pinfunction "37_A37") (pintype "bidirectional"))
      (node (ref "U$12") (pin "13") (pinfunction "8_13") (pintype "bidirectional"))
    )
    (net (code "264") (name "RESET_SOC_MPU") (class "Default")
      (node (ref "C185") (pin "1") (pinfunction "1_1") (pintype "bidirectional"))
      (node (ref "C8") (pin "1") (pinfunction "1_1") (pintype "bidirectional"))
      (node (ref "U12") (pin "17") (pinfunction "P17_17") (pintype "bidirectional"))
      (node (ref "U38") (pin "D1") (pinfunction "VDD_D1") (pintype "power_in"))
      (node (ref "U4") (pin "D1") (pinfunction "VDD_D1") (pintype "power_in"))
    )
    (net (code "265") (name "SOC_CORE") (class "Default")
      (node (ref "C183") (pin "2") (pinfunction "2_2") (pintype "bidirectional"))
      (node (ref "C184") (pin "2") (pinfunction "2_2") (pintype "bidirectional"))
      (node (ref "C3") (pin "1") (pinfunction "1_1") (pintype "bidirectional"))
      (node (ref "R1") (pin "2") (pinfunction "2_2") (pintype "bidirectional"))
      (node (ref "R3") (pin "1") (pinfunction "1_1") (pintype "bidirectional"))
      (node (ref "TP29") (pin "TP") (pinfunction "TP_TP") (pintype "input"))
      (node (ref "U$30") (pin "P$2") (pinfunction "P$2_P$2") (pintype "bidirectional"))
    )
    (net (code "266") (name "SOC_I2C0_SCL") (class "Default")
      (node (ref "R78") (pin "2") (pinfunction "2_2") (pintype "bidirectional"))
      (node (ref "U$12") (pin "26") (pinfunction "SCL_26") (pintype "bidirectional"))
      (node (ref "U$9") (pin "P$1") (pinfunction "SCL_P$1") (pintype "bidirectional"))
      (node (ref "U1") (pin "C16") (pinfunction "I2C0_SCL_C16") (pintype "passive"))
      (node (ref "U12") (pin "19") (pinfunction "SCL_19") (pintype "bidirectional"))
      (node (ref "U17") (pin "15") (pinfunction "BSEL/SCL_15") (pintype "input"))
      (node (ref "U3") (pin "5") (pinfunction "SCL_5") (pintype "input"))
      (node (ref "U38") (pin "D3") (pinfunction "SCL_D3") (pintype "input"))
      (node (ref "U5") (pin "5") (pinfunction "SCL_5") (pintype "input"))
      (node (ref "U7") (pin "5") (pinfunction "SCL_5") (pintype "input"))
      (node (ref "U8") (pin "2") (pinfunction "A0_2") (pintype "passive"))
      (node (ref "U8") (pin "5") (pinfunction "SCL_5") (pintype "input"))
    )
    (net (code "267") (name "SOC_I2C0_SDA") (class "Default")
      (node (ref "R77") (pin "2") (pinfunction "2_2") (pintype "bidirectional"))
      (node (ref "U$12") (pin "27") (pinfunction "SDA_27") (pintype "bidirectional"))
      (node (ref "U$9") (pin "P$6") (pinfunction "SDA_P$6") (pintype "bidirectional"))
      (node (ref "U1") (pin "C17") (pinfunction "I2C0_SDA_C17") (pintype "passive"))
      (node (ref "U12") (pin "20") (pinfunction "SDA_20") (pintype "bidirectional"))
      (node (ref "U17") (pin "14") (pinfunction "DSEL/SDA_14") (pintype "bidirectional"))
      (node (ref "U3") (pin "4") (pinfunction "SDA_4") (pintype "bidirectional"))
      (node (ref "U38") (pin "D2") (pinfunction "SDA_D2") (pintype "bidirectional"))
      (node (ref "U5") (pin "4") (pinfunction "SDA_4") (pintype "bidirectional"))
      (node (ref "U7") (pin "2") (pinfunction "A0_2") (pintype "passive"))
      (node (ref "U7") (pin "4") (pinfunction "SDA_4") (pintype "bidirectional"))
      (node (ref "U8") (pin "4") (pinfunction "SDA_4") (pintype "bidirectional"))
    )
    (net (code "268") (name "SOC_I2C2_SCL") (class "Default")
      (node (ref "J1") (pin "A40") (pinfunction "40_A40") (pintype "bidirectional"))
      (node (ref "R83") (pin "2") (pinfunction "2_2") (pintype "bidirectional"))
      (node (ref "U1") (pin "E16") (pinfunction "UART0_TXD_E16") (pintype "passive"))
      (node (ref "U4") (pin "D3") (pinfunction "SCL_D3") (pintype "input"))
    )
    (net (code "269") (name "SOC_I2C2_SDA") (class "Default")
      (node (ref "J1") (pin "A39") (pinfunction "39_A39") (pintype "bidirectional"))
      (node (ref "R84") (pin "2") (pinfunction "2_2") (pintype "bidirectional"))
      (node (ref "U1") (pin "E15") (pinfunction "UART0_RXD_E15") (pintype "passive"))
      (node (ref "U4") (pin "D2") (pinfunction "SDA_D2") (pintype "bidirectional"))
    )
    (net (code "270") (name "SOC_MII_COL_DET") (class "Default")
      (node (ref "U1") (pin "H16") (pinfunction "MII1_COL_H16") (pintype "passive"))
      (node (ref "U14") (pin "29") (pinfunction "COL_PHYAD0_MLED_29") (pintype "bidirectional"))
    )
    (net (code "271") (name "SOC_MII_CRS") (class "Default")
      (node (ref "U1") (pin "H17") (pinfunction "MII1_CRS_H17") (pintype "passive"))
      (node (ref "U14") (pin "27") (pinfunction "CRS_CRS_DV_LED_CFG_27") (pintype "bidirectional"))
    )
    (net (code "272") (name "SOC_MII_RX0") (class "Default")
      (node (ref "R101") (pin "1") (pinfunction "1_1") (pintype "bidirectional"))
      (node (ref "U1") (pin "M16") (pinfunction "MII1_RXD0_M16") (pintype "passive"))
    )
    (net (code "273") (name "SOC_MII_RX1") (class "Default")
      (node (ref "R100") (pin "1") (pinfunction "1_1") (pintype "bidirectional"))
      (node (ref "U1") (pin "L15") (pinfunction "MII1_RXD1_L15") (pintype "passive"))
    )
    (net (code "274") (name "SOC_MII_RX2") (class "Default")
      (node (ref "R99") (pin "1") (pinfunction "1_1") (pintype "bidirectional"))
      (node (ref "U1") (pin "L16") (pinfunction "MII1_RXD2_L16") (pintype "passive"))
    )
    (net (code "275") (name "SOC_MII_RX3") (class "Default")
      (node (ref "R53") (pin "1") (pinfunction "1_1") (pintype "bidirectional"))
      (node (ref "U1") (pin "L17") (pinfunction "MII1_RXD3_L17") (pintype "passive"))
    )
    (net (code "276") (name "SOC_MII_RX_CLK") (class "Default")
      (node (ref "R102") (pin "1") (pinfunction "1_1") (pintype "bidirectional"))
      (node (ref "U1") (pin "L18") (pinfunction "MII1_RX_CLK_L18") (pintype "passive"))
    )
    (net (code "277") (name "SOC_MII_RX_DV") (class "Default")
      (node (ref "U1") (pin "J17") (pinfunction "MII1_RX_DV_J17") (pintype "passive"))
      (node (ref "U14") (pin "26") (pinfunction "RX_DV_MII_MODE_26") (pintype "bidirectional"))
    )
    (net (code "278") (name "SOC_MII_RX_ER") (class "Default")
      (node (ref "U1") (pin "J15") (pinfunction "MII1_RX_ER_J15") (pintype "passive"))
      (node (ref "U14") (pin "28") (pinfunction "RX_ER_AMDIX_EN_28") (pintype "bidirectional"))
    )
    (net (code "279") (name "SOC_MII_TX0") (class "Default")
      (node (ref "U1") (pin "K17") (pinfunction "MII1_TXD0_K17") (pintype "passive"))
      (node (ref "U14") (pin "4") (pinfunction "TX_D0_4") (pintype "input"))
    )
    (net (code "280") (name "SOC_MII_TX1") (class "Default")
      (node (ref "U1") (pin "K16") (pinfunction "MII1_TXD1_K16") (pintype "passive"))
      (node (ref "U14") (pin "5") (pinfunction "TX_D1_5") (pintype "input"))
    )
    (net (code "281") (name "SOC_MII_TX2") (class "Default")
      (node (ref "U1") (pin "K15") (pinfunction "MII1_TXD2_K15") (pintype "passive"))
      (node (ref "U14") (pin "6") (pinfunction "TX_D2_6") (pintype "input"))
    )
    (net (code "282") (name "SOC_MII_TX3") (class "Default")
      (node (ref "U1") (pin "J18") (pinfunction "MII1_TXD3_J18") (pintype "passive"))
      (node (ref "U14") (pin "7") (pinfunction "TX_D3_7") (pintype "input"))
    )
    (net (code "283") (name "SOC_MII_TX_CLK") (class "Default")
      (node (ref "U1") (pin "K18") (pinfunction "MII1_TX_CLK_K18") (pintype "passive"))
      (node (ref "U14") (pin "2") (pinfunction "TX_CLK_2") (pintype "output"))
    )
    (net (code "284") (name "SOC_MII_TX_EN") (class "Default")
      (node (ref "U1") (pin "J16") (pinfunction "MII1_TX_EN_J16") (pintype "passive"))
      (node (ref "U14") (pin "3") (pinfunction "TX_EN_3") (pintype "input"))
    )
    (net (code "285") (name "SOC_MPU") (class "Default")
      (node (ref "C11") (pin "1") (pinfunction "1_1") (pintype "bidirectional"))
      (node (ref "C6") (pin "2") (pinfunction "2_2") (pintype "bidirectional"))
      (node (ref "C7") (pin "2") (pinfunction "2_2") (pintype "bidirectional"))
      (node (ref "R4") (pin "2") (pinfunction "2_2") (pintype "bidirectional"))
      (node (ref "R6") (pin "1") (pinfunction "1_1") (pintype "bidirectional"))
      (node (ref "TP1") (pin "TP") (pinfunction "TP_TP") (pintype "input"))
      (node (ref "U$1") (pin "P$2") (pinfunction "P$2_P$2") (pintype "bidirectional"))
    )
    (net (code "286") (name "SOC_PORZ") (class "Default")
      (node (ref "R543") (pin "2") (pinfunction "2_2") (pintype "bidirectional"))
      (node (ref "TP14") (pin "TP") (pinfunction "TP_TP") (pintype "input"))
      (node (ref "U1") (pin "B15") (pinfunction "PWRONRSTN_B15") (pintype "passive"))
    )
    (net (code "287") (name "SOC_POWER_MON_PORZ") (class "Default")
      (node (ref "R542") (pin "1") (pinfunction "1_1") (pintype "bidirectional"))
      (node (ref "U77") (pin "4") (pinfunction "SENSE_OUT_4") (pintype "output"))
      (node (ref "U78") (pin "1") (pinfunction "A_1") (pintype "input"))
    )
    (net (code "288") (name "SOC_VDDS_DDR") (class "Default")
      (node (ref "C66") (pin "2") (pinfunction "2_2") (pintype "bidirectional"))
      (node (ref "C67") (pin "2") (pinfunction "2_2") (pintype "bidirectional"))
      (node (ref "R11") (pin "2") (pinfunction "2_2") (pintype "bidirectional"))
      (node (ref "R12") (pin "2") (pinfunction "2_2") (pintype "bidirectional"))
      (node (ref "U1") (pin "E5") (pinfunction "VDDS_DDR_5_E5") (pintype "power_in"))
      (node (ref "U1") (pin "F5") (pinfunction "VDDS_DDR_6_F5") (pintype "power_in"))
      (node (ref "U1") (pin "G5") (pinfunction "VDDS_DDR_7_G5") (pintype "power_in"))
      (node (ref "U1") (pin "H5") (pinfunction "VDDS_DDR_3_H5") (pintype "power_in"))
      (node (ref "U1") (pin "J5") (pinfunction "VDDS_DDR_2_J5") (pintype "power_in"))
      (node (ref "U1") (pin "K5") (pinfunction "VDDS_DDR_K5") (pintype "power_in"))
      (node (ref "U1") (pin "L5") (pinfunction "VDDS_DDR_4_L5") (pintype "power_in"))
    )
    (net (code "289") (name "SPI0_CLK") (class "Default")
      (node (ref "J1") (pin "B12") (pinfunction "12_B12") (pintype "bidirectional"))
      (node (ref "U1") (pin "A17") (pinfunction "SPI0_SCLK_A17") (pintype "passive"))
    )
    (net (code "290") (name "SPI0_CS0") (class "Default")
      (node (ref "J1") (pin "B13") (pinfunction "13_B13") (pintype "bidirectional"))
      (node (ref "U1") (pin "A16") (pinfunction "SPI0_CS0_A16") (pintype "passive"))
    )
    (net (code "291") (name "SPI0_MISO") (class "Default")
      (node (ref "J1") (pin "B14") (pinfunction "14_B14") (pintype "bidirectional"))
      (node (ref "U1") (pin "B16") (pinfunction "SPI0_D1_B16") (pintype "passive"))
    )
    (net (code "292") (name "SPI0_MOSI") (class "Default")
      (node (ref "J1") (pin "B11") (pinfunction "11_B11") (pintype "bidirectional"))
      (node (ref "U1") (pin "B17") (pinfunction "SPI0_D0_B17") (pintype "passive"))
    )
    (net (code "293") (name "SPI1_CLK") (class "Default")
      (node (ref "J1") (pin "C29") (pinfunction "29_C29") (pintype "bidirectional"))
      (node (ref "U1") (pin "A13") (pinfunction "MCASP0_ACLKX_A13") (pintype "passive"))
    )
    (net (code "294") (name "SPI1_CS0") (class "Default")
      (node (ref "J1") (pin "C31") (pinfunction "31_C31") (pintype "bidirectional"))
      (node (ref "U1") (pin "C12") (pinfunction "MCASP0_AHCLKR_C12") (pintype "passive"))
    )
    (net (code "295") (name "SPI1_D0") (class "Default")
      (node (ref "J1") (pin "C30") (pinfunction "30_C30") (pintype "bidirectional"))
      (node (ref "U1") (pin "B13") (pinfunction "MCASP0_FSX_B13") (pintype "passive"))
    )
    (net (code "296") (name "SPI1_D1") (class "Default")
      (node (ref "J1") (pin "C28") (pinfunction "28_C28") (pintype "bidirectional"))
      (node (ref "U1") (pin "D12") (pinfunction "MCASP0_AXR0_D12") (pintype "passive"))
    )
    (net (code "297") (name "TIMER4") (class "Default")
      (node (ref "J1") (pin "C1") (pinfunction "1_C1") (pintype "bidirectional"))
      (node (ref "U1") (pin "R7") (pinfunction "GPMC_ADVN_ALE_R7") (pintype "passive"))
    )
    (net (code "298") (name "TIMER5") (class "Default")
      (node (ref "J1") (pin "C2") (pinfunction "2_C2") (pintype "bidirectional"))
      (node (ref "U1") (pin "T6") (pinfunction "GPMC_BEN0_CLE_T6") (pintype "passive"))
    )
    (net (code "299") (name "TIMER6") (class "Default")
      (node (ref "J1") (pin "C3") (pinfunction "3_C3") (pintype "bidirectional"))
      (node (ref "U1") (pin "H18") (pinfunction "RMII1_REF_CLK_H18") (pintype "passive"))
    )
    (net (code "300") (name "TIMER7") (class "Default")
      (node (ref "J1") (pin "C4") (pinfunction "4_C4") (pintype "bidirectional"))
      (node (ref "U1") (pin "T7") (pinfunction "GPMC_OEN_REN_T7") (pintype "passive"))
    )
    (net (code "301") (name "TPS54334_VSENSE") (class "Default")
      (node (ref "C200") (pin "1") (pinfunction "1_1") (pintype "bidirectional"))
      (node (ref "R233") (pin "1") (pinfunction "1_1") (pintype "bidirectional"))
      (node (ref "R234") (pin "2") (pinfunction "2_2") (pintype "bidirectional"))
      (node (ref "U41") (pin "6") (pinfunction "VSENSE_6") (pintype "input"))
    )
    (net (code "302") (name "UART1_RXD") (class "Default")
      (node (ref "J1") (pin "C24") (pinfunction "24_C24") (pintype "bidirectional"))
      (node (ref "U1") (pin "D16") (pinfunction "UART1_RXD_D16") (pintype "passive"))
    )
    (net (code "303") (name "UART1_TXD") (class "Default")
      (node (ref "J1") (pin "C23") (pinfunction "23_C23") (pintype "bidirectional"))
      (node (ref "U1") (pin "D15") (pinfunction "UART1_TXD_D15") (pintype "passive"))
    )
    (net (code "304") (name "USB0_DRVVBUS") (class "Default")
      (node (ref "R75") (pin "2") (pinfunction "2_2") (pintype "bidirectional"))
      (node (ref "U1") (pin "F16") (pinfunction "USB0_DRVVBUS_F16") (pintype "passive"))
      (node (ref "U16") (pin "4") (pinfunction "*EN_4") (pintype "input"))
    )
    (net (code "305") (name "USB0_D_N") (class "Default")
      (node (ref "U1") (pin "N18") (pinfunction "USB0_DM_N18") (pintype "passive"))
      (node (ref "U10") (pin "2") (pinfunction "D-_2") (pintype "passive"))
      (node (ref "X3") (pin "D-") (pinfunction "D-_D-") (pintype "bidirectional"))
    )
    (net (code "306") (name "USB0_D_P") (class "Default")
      (node (ref "U1") (pin "N17") (pinfunction "USB0_DP_N17") (pintype "passive"))
      (node (ref "U10") (pin "1") (pinfunction "D+_1") (pintype "passive"))
      (node (ref "X3") (pin "D+") (pinfunction "D+_D+") (pintype "bidirectional"))
    )
    (net (code "307") (name "USB0_VBUS") (class "Default")
      (node (ref "C178") (pin "1") (pinfunction "1_1") (pintype "bidirectional"))
      (node (ref "U1") (pin "P15") (pinfunction "USB0_VBUS_P15") (pintype "passive"))
      (node (ref "U10") (pin "6") (pinfunction "VBUS_6") (pintype "passive"))
      (node (ref "U16") (pin "6") (pinfunction "OUT_2_6") (pintype "output"))
      (node (ref "U16") (pin "7") (pinfunction "OUT_3_7") (pintype "output"))
      (node (ref "U16") (pin "8") (pinfunction "OUT_8") (pintype "output"))
      (node (ref "X3") (pin "VBUS") (pinfunction "VBUS_VBUS") (pintype "bidirectional"))
    )
    (net (code "308") (name "USB1_DRVVBUS") (class "Default")
      (node (ref "R73") (pin "2") (pinfunction "2_2") (pintype "bidirectional"))
      (node (ref "U1") (pin "F15") (pinfunction "USB1_DRVVBUS_F15") (pintype "passive"))
      (node (ref "U15") (pin "4") (pinfunction "*EN_4") (pintype "input"))
    )
    (net (code "309") (name "USB1_D_N") (class "Default")
      (node (ref "U1") (pin "R18") (pinfunction "USB1_DM_R18") (pintype "passive"))
      (node (ref "U2") (pin "2") (pinfunction "D-_2") (pintype "passive"))
      (node (ref "X2") (pin "D-") (pinfunction "D-_D-") (pintype "bidirectional"))
    )
    (net (code "310") (name "USB1_D_P") (class "Default")
      (node (ref "U1") (pin "R17") (pinfunction "USB1_DP_R17") (pintype "passive"))
      (node (ref "U2") (pin "1") (pinfunction "D+_1") (pintype "passive"))
      (node (ref "X2") (pin "D+") (pinfunction "D+_D+") (pintype "bidirectional"))
    )
    (net (code "311") (name "USB1_VBUS") (class "Default")
      (node (ref "C158") (pin "1") (pinfunction "1_1") (pintype "bidirectional"))
      (node (ref "U1") (pin "T18") (pinfunction "USB1_VBUS_T18") (pintype "passive"))
      (node (ref "U15") (pin "6") (pinfunction "OUT_2_6") (pintype "output"))
      (node (ref "U15") (pin "7") (pinfunction "OUT_3_7") (pintype "output"))
      (node (ref "U15") (pin "8") (pinfunction "OUT_8") (pintype "output"))
      (node (ref "U2") (pin "6") (pinfunction "VBUS_6") (pintype "passive"))
      (node (ref "X2") (pin "VBUS") (pinfunction "VBUS_VBUS") (pintype "bidirectional"))
    )
    (net (code "312") (name "VCC_1V5_DDR") (class "Default")
      (node (ref "C30") (pin "1") (pinfunction "1_1") (pintype "bidirectional"))
      (node (ref "C33") (pin "1") (pinfunction "1_1") (pintype "bidirectional"))
      (node (ref "C34") (pin "1") (pinfunction "+_1") (pintype "bidirectional"))
      (node (ref "C35") (pin "1") (pinfunction "+_1") (pintype "bidirectional"))
      (node (ref "C38") (pin "2") (pinfunction "2_2") (pintype "bidirectional"))
      (node (ref "R10") (pin "2") (pinfunction "2_2") (pintype "bidirectional"))
      (node (ref "R12") (pin "1") (pinfunction "1_1") (pintype "bidirectional"))
      (node (ref "R17") (pin "2") (pinfunction "2_2") (pintype "bidirectional"))
      (node (ref "R19") (pin "2") (pinfunction "2_2") (pintype "bidirectional"))
      (node (ref "R7") (pin "2") (pinfunction "2_2") (pintype "bidirectional"))
      (node (ref "R9") (pin "1") (pinfunction "1_1") (pintype "bidirectional"))
      (node (ref "U$4") (pin "V1") (pinfunction "P$2_V1") (pintype "bidirectional"))
      (node (ref "U6") (pin "1") (pinfunction "VLDOIN_1") (pintype "input"))
      (node (ref "U6") (pin "6") (pinfunction "MODE_6") (pintype "input"))
      (node (ref "U6") (pin "9") (pinfunction "VDDQSNS_9") (pintype "bidirectional"))
    )
    (net (code "313") (name "VCC_1V8") (class "Default")
      (node (ref "C115") (pin "2") (pinfunction "2_2") (pintype "bidirectional"))
      (node (ref "C116") (pin "2") (pinfunction "2_2") (pintype "bidirectional"))
      (node (ref "C118") (pin "1") (pinfunction "1_1") (pintype "bidirectional"))
      (node (ref "C176") (pin "2") (pinfunction "2_2") (pintype "bidirectional"))
      (node (ref "C68") (pin "2") (pinfunction "2_2") (pintype "bidirectional"))
      (node (ref "C69") (pin "2") (pinfunction "2_2") (pintype "bidirectional"))
      (node (ref "C70") (pin "2") (pinfunction "2_2") (pintype "bidirectional"))
      (node (ref "C71") (pin "2") (pinfunction "2_2") (pintype "bidirectional"))
      (node (ref "C72") (pin "2") (pinfunction "2_2") (pintype "bidirectional"))
      (node (ref "C75") (pin "2") (pinfunction "2_2") (pintype "bidirectional"))
      (node (ref "C76") (pin "2") (pinfunction "2_2") (pintype "bidirectional"))
      (node (ref "C77") (pin "2") (pinfunction "2_2") (pintype "bidirectional"))
      (node (ref "C78") (pin "2") (pinfunction "2_2") (pintype "bidirectional"))
      (node (ref "C79") (pin "2") (pinfunction "2_2") (pintype "bidirectional"))
      (node (ref "C80") (pin "2") (pinfunction "2_2") (pintype "bidirectional"))
      (node (ref "C81") (pin "2") (pinfunction "2_2") (pintype "bidirectional"))
      (node (ref "C82") (pin "2") (pinfunction "2_2") (pintype "bidirectional"))
      (node (ref "C83") (pin "2") (pinfunction "2_2") (pintype "bidirectional"))
      (node (ref "C92") (pin "2") (pinfunction "2_2") (pintype "bidirectional"))
      (node (ref "R56") (pin "2") (pinfunction "2_2") (pintype "bidirectional"))
      (node (ref "R57") (pin "2") (pinfunction "2_2") (pintype "bidirectional"))
      (node (ref "R58") (pin "1") (pinfunction "1_1") (pintype "bidirectional"))
      (node (ref "TP26") (pin "TP") (pinfunction "TP_TP") (pintype "input"))
      (node (ref "U$28") (pin "P$2") (pinfunction "P$2_P$2") (pintype "bidirectional"))
      (node (ref "U1") (pin "B9") (pinfunction "VREFP_B9") (pintype "power_in"))
      (node (ref "U1") (pin "D10") (pinfunction "VDDS_SRAM_MPU_BB_D10") (pintype "passive"))
      (node (ref "U1") (pin "E14") (pinfunction "VDDS_3_E14") (pintype "power_in"))
      (node (ref "U1") (pin "E6") (pinfunction "VDDS_5_E6") (pintype "power_in"))
      (node (ref "U1") (pin "E7") (pinfunction "VDDS_PLL_DDR_E7") (pintype "power_in"))
      (node (ref "U1") (pin "E9") (pinfunction "VDDS_SRAM_CORE_BG_E9") (pintype "power_in"))
      (node (ref "U1") (pin "F9") (pinfunction "VDDS_F9") (pintype "power_in"))
      (node (ref "U1") (pin "H15") (pinfunction "VDDS_PLL_MPU_H15") (pintype "power_in"))
      (node (ref "U1") (pin "K13") (pinfunction "VDDS_4_K13") (pintype "power_in"))
      (node (ref "U1") (pin "N16") (pinfunction "VDDA1P8V_USB0_N16") (pintype "power_in"))
      (node (ref "U1") (pin "N6") (pinfunction "VDDS_2_N6") (pintype "power_in"))
      (node (ref "U1") (pin "P14") (pinfunction "VDDS_6_P14") (pintype "power_in"))
      (node (ref "U1") (pin "P9") (pinfunction "VDDS_7_P9") (pintype "power_in"))
      (node (ref "U1") (pin "R10") (pinfunction "VDDS_PLL_CORE_LCD_R10") (pintype "power_in"))
      (node (ref "U1") (pin "R11") (pinfunction "VDDS_OSC_R11") (pintype "power_in"))
      (node (ref "U1") (pin "R16") (pinfunction "VDDA1P8V_USB1_R16") (pintype "power_in"))
      (node (ref "U13") (pin "5") (pinfunction "VCC_5") (pintype "power_in"))
      (node (ref "U35") (pin "3") (pinfunction "FB_3") (pintype "input"))
      (node (ref "U35") (pin "4") (pinfunction "VOS_4") (pintype "input"))
    )
    (net (code "314") (name "VCC_1V8_PG") (class "Default")
      (node (ref "R54") (pin "1") (pinfunction "1_1") (pintype "bidirectional"))
      (node (ref "U35") (pin "2") (pinfunction "PG_2") (pintype "output"))
      (node (ref "U6") (pin "11") (pinfunction "S3_11") (pintype "input"))
      (node (ref "U6") (pin "12") (pinfunction "S5_12") (pintype "input"))
    )
    (net (code "315") (name "VCC_3V3_IO") (class "Default")
      (node (ref "C1") (pin "2") (pinfunction "2_2") (pintype "bidirectional"))
      (node (ref "C100") (pin "2") (pinfunction "2_2") (pintype "bidirectional"))
      (node (ref "C101") (pin "2") (pinfunction "2_2") (pintype "bidirectional"))
      (node (ref "C102") (pin "2") (pinfunction "2_2") (pintype "bidirectional"))
      (node (ref "C103") (pin "2") (pinfunction "2_2") (pintype "bidirectional"))
      (node (ref "C104") (pin "2") (pinfunction "2_2") (pintype "bidirectional"))
      (node (ref "C105") (pin "2") (pinfunction "2_2") (pintype "bidirectional"))
      (node (ref "C106") (pin "2") (pinfunction "2_2") (pintype "bidirectional"))
      (node (ref "C107") (pin "2") (pinfunction "2_2") (pintype "bidirectional"))
      (node (ref "C108") (pin "2") (pinfunction "2_2") (pintype "bidirectional"))
      (node (ref "C109") (pin "2") (pinfunction "2_2") (pintype "bidirectional"))
      (node (ref "C110") (pin "2") (pinfunction "2_2") (pintype "bidirectional"))
      (node (ref "C111") (pin "2") (pinfunction "2_2") (pintype "bidirectional"))
      (node (ref "C112") (pin "2") (pinfunction "2_2") (pintype "bidirectional"))
      (node (ref "C113") (pin "2") (pinfunction "2_2") (pintype "bidirectional"))
      (node (ref "C114") (pin "2") (pinfunction "2_2") (pintype "bidirectional"))
      (node (ref "C117") (pin "2") (pinfunction "2_2") (pintype "bidirectional"))
      (node (ref "C123") (pin "2") (pinfunction "2_2") (pintype "bidirectional"))
      (node (ref "C124") (pin "2") (pinfunction "2_2") (pintype "bidirectional"))
      (node (ref "C125") (pin "2") (pinfunction "2_2") (pintype "bidirectional"))
      (node (ref "C126") (pin "2") (pinfunction "2_2") (pintype "bidirectional"))
      (node (ref "C127") (pin "2") (pinfunction "2_2") (pintype "bidirectional"))
      (node (ref "C128") (pin "2") (pinfunction "2_2") (pintype "bidirectional"))
      (node (ref "C129") (pin "2") (pinfunction "2_2") (pintype "bidirectional"))
      (node (ref "C13") (pin "2") (pinfunction "2_2") (pintype "bidirectional"))
      (node (ref "C130") (pin "2") (pinfunction "2_2") (pintype "bidirectional"))
      (node (ref "C131") (pin "2") (pinfunction "2_2") (pintype "bidirectional"))
      (node (ref "C132") (pin "2") (pinfunction "2_2") (pintype "bidirectional"))
      (node (ref "C133") (pin "2") (pinfunction "2_2") (pintype "bidirectional"))
      (node (ref "C134") (pin "2") (pinfunction "2_2") (pintype "bidirectional"))
      (node (ref "C135") (pin "2") (pinfunction "2_2") (pintype "bidirectional"))
      (node (ref "C136") (pin "1") (pinfunction "1_1") (pintype "bidirectional"))
      (node (ref "C137") (pin "2") (pinfunction "2_2") (pintype "bidirectional"))
      (node (ref "C138") (pin "1") (pinfunction "1_1") (pintype "bidirectional"))
      (node (ref "C139") (pin "2") (pinfunction "2_2") (pintype "bidirectional"))
      (node (ref "C140") (pin "2") (pinfunction "2_2") (pintype "bidirectional"))
      (node (ref "C186") (pin "2") (pinfunction "2_2") (pintype "bidirectional"))
      (node (ref "C187") (pin "2") (pinfunction "2_2") (pintype "bidirectional"))
      (node (ref "C188") (pin "2") (pinfunction "2_2") (pintype "bidirectional"))
      (node (ref "C189") (pin "2") (pinfunction "2_2") (pintype "bidirectional"))
      (node (ref "C190") (pin "2") (pinfunction "2_2") (pintype "bidirectional"))
      (node (ref "C198") (pin "2") (pinfunction "2_2") (pintype "bidirectional"))
      (node (ref "C199") (pin "2") (pinfunction "2_2") (pintype "bidirectional"))
      (node (ref "C201") (pin "2") (pinfunction "2_2") (pintype "bidirectional"))
      (node (ref "C202") (pin "2") (pinfunction "2_2") (pintype "bidirectional"))
      (node (ref "C203") (pin "2") (pinfunction "2_2") (pintype "bidirectional"))
      (node (ref "C204") (pin "2") (pinfunction "2_2") (pintype "bidirectional"))
      (node (ref "C205") (pin "2") (pinfunction "2_2") (pintype "bidirectional"))
      (node (ref "C206") (pin "2") (pinfunction "2_2") (pintype "bidirectional"))
      (node (ref "C207") (pin "2") (pinfunction "2_2") (pintype "bidirectional"))
      (node (ref "C208") (pin "2") (pinfunction "2_2") (pintype "bidirectional"))
      (node (ref "C209") (pin "2") (pinfunction "2_2") (pintype "bidirectional"))
      (node (ref "C210") (pin "2") (pinfunction "2_2") (pintype "bidirectional"))
      (node (ref "C211") (pin "2") (pinfunction "2_2") (pintype "bidirectional"))
      (node (ref "C222") (pin "1") (pinfunction "1_1") (pintype "bidirectional"))
      (node (ref "C225") (pin "2") (pinfunction "2_2") (pintype "bidirectional"))
      (node (ref "C226") (pin "2") (pinfunction "2_2") (pintype "bidirectional"))
      (node (ref "C227") (pin "1") (pinfunction "1_1") (pintype "bidirectional"))
      (node (ref "C230") (pin "2") (pinfunction "2_2") (pintype "bidirectional"))
      (node (ref "C231") (pin "1") (pinfunction "1_1") (pintype "bidirectional"))
      (node (ref "C232") (pin "1") (pinfunction "1_1") (pintype "bidirectional"))
      (node (ref "C233") (pin "1") (pinfunction "1_1") (pintype "bidirectional"))
      (node (ref "C234") (pin "1") (pinfunction "1_1") (pintype "bidirectional"))
      (node (ref "C235") (pin "2") (pinfunction "2_2") (pintype "bidirectional"))
      (node (ref "C236") (pin "1") (pinfunction "1_1") (pintype "bidirectional"))
      (node (ref "C237") (pin "2") (pinfunction "2_2") (pintype "bidirectional"))
      (node (ref "C31") (pin "2") (pinfunction "2_2") (pintype "bidirectional"))
      (node (ref "C579") (pin "1") (pinfunction "1_1") (pintype "bidirectional"))
      (node (ref "C84") (pin "2") (pinfunction "2_2") (pintype "bidirectional"))
      (node (ref "C85") (pin "2") (pinfunction "2_2") (pintype "bidirectional"))
      (node (ref "C9") (pin "2") (pinfunction "2_2") (pintype "bidirectional"))
      (node (ref "C93") (pin "2") (pinfunction "2_2") (pintype "bidirectional"))
      (node (ref "C94") (pin "2") (pinfunction "2_2") (pintype "bidirectional"))
      (node (ref "C95") (pin "2") (pinfunction "2_2") (pintype "bidirectional"))
      (node (ref "C96") (pin "2") (pinfunction "2_2") (pintype "bidirectional"))
      (node (ref "C97") (pin "2") (pinfunction "2_2") (pintype "bidirectional"))
      (node (ref "C98") (pin "2") (pinfunction "2_2") (pintype "bidirectional"))
      (node (ref "C99") (pin "2") (pinfunction "2_2") (pintype "bidirectional"))
      (node (ref "J1") (pin "B23") (pinfunction "23_B23") (pintype "bidirectional"))
      (node (ref "JP1") (pin "5") (pinfunction "5_5") (pintype "passive"))
      (node (ref "R232") (pin "2") (pinfunction "2_2") (pintype "bidirectional"))
      (node (ref "R538") (pin "2") (pinfunction "2_2") (pintype "bidirectional"))
      (node (ref "R542") (pin "2") (pinfunction "2_2") (pintype "bidirectional"))
      (node (ref "R55") (pin "2") (pinfunction "2_2") (pintype "bidirectional"))
      (node (ref "R60") (pin "2") (pinfunction "2_2") (pintype "bidirectional"))
      (node (ref "R63") (pin "1") (pinfunction "1_1") (pintype "bidirectional"))
      (node (ref "R70") (pin "2") (pinfunction "2_2") (pintype "bidirectional"))
      (node (ref "R74") (pin "1") (pinfunction "1_1") (pintype "bidirectional"))
      (node (ref "R76") (pin "1") (pinfunction "1_1") (pintype "bidirectional"))
      (node (ref "R77") (pin "1") (pinfunction "1_1") (pintype "bidirectional"))
      (node (ref "R78") (pin "1") (pinfunction "1_1") (pintype "bidirectional"))
      (node (ref "R79") (pin "1") (pinfunction "1_1") (pintype "bidirectional"))
      (node (ref "R83") (pin "1") (pinfunction "1_1") (pintype "bidirectional"))
      (node (ref "R84") (pin "1") (pinfunction "1_1") (pintype "bidirectional"))
      (node (ref "R86") (pin "2") (pinfunction "2_2") (pintype "bidirectional"))
      (node (ref "R88") (pin "2") (pinfunction "2_2") (pintype "bidirectional"))
      (node (ref "R90") (pin "1") (pinfunction "1_1") (pintype "bidirectional"))
      (node (ref "R91") (pin "1") (pinfunction "1_1") (pintype "bidirectional"))
      (node (ref "R94") (pin "1") (pinfunction "1_1") (pintype "bidirectional"))
      (node (ref "R95") (pin "1") (pinfunction "1_1") (pintype "bidirectional"))
      (node (ref "R96") (pin "1") (pinfunction "1_1") (pintype "bidirectional"))
      (node (ref "R97") (pin "1") (pinfunction "1_1") (pintype "bidirectional"))
      (node (ref "T1") (pin "4") (pinfunction "VCC_4") (pintype "bidirectional"))
      (node (ref "TP32") (pin "TP") (pinfunction "TP_TP") (pintype "input"))
      (node (ref "U$10") (pin "C6") (pinfunction "VCCQ_C6") (pintype "bidirectional"))
      (node (ref "U$10") (pin "E6") (pinfunction "VCC_E6") (pintype "bidirectional"))
      (node (ref "U$10") (pin "F5") (pinfunction "VCC_F5") (pintype "bidirectional"))
      (node (ref "U$10") (pin "J10") (pinfunction "VCC_J10") (pintype "bidirectional"))
      (node (ref "U$10") (pin "K9") (pinfunction "VCC_K9") (pintype "bidirectional"))
      (node (ref "U$10") (pin "M4") (pinfunction "VCCQ_M4") (pintype "bidirectional"))
      (node (ref "U$10") (pin "N4") (pinfunction "VCCQ_N4") (pintype "bidirectional"))
      (node (ref "U$10") (pin "P3") (pinfunction "VCCQ_P3") (pintype "bidirectional"))
      (node (ref "U$10") (pin "P5") (pinfunction "VCCQ_P5") (pintype "bidirectional"))
      (node (ref "U$11") (pin "C6") (pinfunction "VCCQ_C6") (pintype "bidirectional"))
      (node (ref "U$11") (pin "E6") (pinfunction "VCC_E6") (pintype "bidirectional"))
      (node (ref "U$11") (pin "F5") (pinfunction "VCC_F5") (pintype "bidirectional"))
      (node (ref "U$11") (pin "J10") (pinfunction "VCC_J10") (pintype "bidirectional"))
      (node (ref "U$11") (pin "K9") (pinfunction "VCC_K9") (pintype "bidirectional"))
      (node (ref "U$11") (pin "M4") (pinfunction "VCCQ_M4") (pintype "bidirectional"))
      (node (ref "U$11") (pin "N4") (pinfunction "VCCQ_N4") (pintype "bidirectional"))
      (node (ref "U$11") (pin "P3") (pinfunction "VCCQ_P3") (pintype "bidirectional"))
      (node (ref "U$11") (pin "P5") (pinfunction "VCCQ_P5") (pintype "bidirectional"))
      (node (ref "U$12") (pin "1") (pinfunction "A0_1") (pintype "bidirectional"))
      (node (ref "U$12") (pin "2") (pinfunction "A1_2") (pintype "bidirectional"))
      (node (ref "U$12") (pin "24") (pinfunction "A5_24") (pintype "bidirectional"))
      (node (ref "U$12") (pin "28") (pinfunction "VDD_28") (pintype "bidirectional"))
      (node (ref "U$12") (pin "3") (pinfunction "A2_3") (pintype "bidirectional"))
      (node (ref "U$12") (pin "4") (pinfunction "A3_4") (pintype "bidirectional"))
      (node (ref "U$12") (pin "5") (pinfunction "A4_5") (pintype "bidirectional"))
      (node (ref "U$33") (pin "P$2") (pinfunction "P$2_P$2") (pintype "bidirectional"))
      (node (ref "U$9") (pin "P$4") (pinfunction "VCC_P$4") (pintype "power_in"))
      (node (ref "U1") (pin "E10") (pinfunction "VDDSHV6_3_E10") (pintype "power_in"))
      (node (ref "U1") (pin "E11") (pinfunction "VDDSHV6_4_E11") (pintype "power_in"))
      (node (ref "U1") (pin "E12") (pinfunction "VDDSHV6_5_E12") (pintype "power_in"))
      (node (ref "U1") (pin "E13") (pinfunction "VDDSHV6_6_E13") (pintype "power_in"))
      (node (ref "U1") (pin "F14") (pinfunction "VDDSHV6_9_F14") (pintype "power_in"))
      (node (ref "U1") (pin "G14") (pinfunction "VDDSHV6_G14") (pintype "power_in"))
      (node (ref "U1") (pin "H14") (pinfunction "VDDSHV4_2_H14") (pintype "power_in"))
      (node (ref "U1") (pin "J14") (pinfunction "VDDSHV4_J14") (pintype "power_in"))
      (node (ref "U1") (pin "K14") (pinfunction "VDDSHV5_2_K14") (pintype "power_in"))
      (node (ref "U1") (pin "L14") (pinfunction "VDDSHV5_L14") (pintype "power_in"))
      (node (ref "U1") (pin "N15") (pinfunction "VDDA3P3V_USB0_N15") (pintype "power_in"))
      (node (ref "U1") (pin "N5") (pinfunction "VDDSHV6_2_N5") (pintype "power_in"))
      (node (ref "U1") (pin "P10") (pinfunction "VDDSHV2_2_P10") (pintype "power_in"))
      (node (ref "U1") (pin "P11") (pinfunction "VDDSHV2_P11") (pintype "power_in"))
      (node (ref "U1") (pin "P12") (pinfunction "VDDSHV3_2_P12") (pintype "power_in"))
      (node (ref "U1") (pin "P13") (pinfunction "VDDSHV3_P13") (pintype "power_in"))
      (node (ref "U1") (pin "P5") (pinfunction "VDDSHV6_7_P5") (pintype "power_in"))
      (node (ref "U1") (pin "P6") (pinfunction "VDDSHV6_8_P6") (pintype "power_in"))
      (node (ref "U1") (pin "P7") (pinfunction "VDDSHV1_2_P7") (pintype "power_in"))
      (node (ref "U1") (pin "P8") (pinfunction "VDDSHV1_P8") (pintype "power_in"))
      (node (ref "U1") (pin "R15") (pinfunction "VDDA3P3V_USB1_R15") (pintype "power_in"))
      (node (ref "U12") (pin "21") (pinfunction "VCC_21") (pintype "power_in"))
      (node (ref "U14") (pin "14") (pinfunction "AVD33_14") (pintype "power_in"))
      (node (ref "U14") (pin "21") (pinfunction "VDDIO_21") (pintype "power_in"))
      (node (ref "U17") (pin "1") (pinfunction "DVDD_2_1") (pintype "power_in"))
      (node (ref "U17") (pin "10") (pinfunction "*PD_10") (pintype "input"))
      (node (ref "U17") (pin "12") (pinfunction "DVDD_3_12") (pintype "power_in"))
      (node (ref "U17") (pin "13") (pinfunction "ISEL/*RST_13") (pintype "input"))
      (node (ref "U17") (pin "18") (pinfunction "PVDD_18") (pintype "power_in"))
      (node (ref "U17") (pin "23") (pinfunction "TVDD_2_23") (pintype "power_in"))
      (node (ref "U17") (pin "29") (pinfunction "TVDD_29") (pintype "power_in"))
      (node (ref "U17") (pin "3") (pinfunction "VREF_3") (pintype "input"))
      (node (ref "U17") (pin "33") (pinfunction "DVDD_33") (pintype "power_in"))
      (node (ref "U17") (pin "35") (pinfunction "DKEN_35") (pintype "input"))
      (node (ref "U18") (pin "6") (pinfunction "VCC_6") (pintype "power_in"))
      (node (ref "U19") (pin "5") (pinfunction "VIO_5") (pintype "power_in"))
      (node (ref "U3") (pin "6") (pinfunction "VS_6") (pintype "power_in"))
      (node (ref "U5") (pin "1") (pinfunction "A1_1") (pintype "passive"))
      (node (ref "U5") (pin "6") (pinfunction "VS_6") (pintype "power_in"))
      (node (ref "U7") (pin "6") (pinfunction "VS_6") (pintype "power_in"))
      (node (ref "U78") (pin "5") (pinfunction "VCC_5") (pintype "power_in"))
      (node (ref "U8") (pin "6") (pinfunction "VS_6") (pintype "power_in"))
      (node (ref "X1") (pin "3") (pinfunction "CT_3") (pintype "input"))
      (node (ref "X1") (pin "6") (pinfunction "CR_6") (pintype "input"))
    )
    (net (code "316") (name "VCC_3V3_PREREG") (class "Default")
      (node (ref "C142") (pin "1") (pinfunction "+_1") (pintype "bidirectional"))
      (node (ref "C143") (pin "1") (pinfunction "+_1") (pintype "bidirectional"))
      (node (ref "C157") (pin "2") (pinfunction "2_2") (pintype "bidirectional"))
      (node (ref "C175") (pin "2") (pinfunction "2_2") (pintype "bidirectional"))
      (node (ref "C181") (pin "2") (pinfunction "2_2") (pintype "bidirectional"))
      (node (ref "C182") (pin "2") (pinfunction "2_2") (pintype "bidirectional"))
      (node (ref "C4") (pin "2") (pinfunction "2_2") (pintype "bidirectional"))
      (node (ref "C5") (pin "2") (pinfunction "2_2") (pintype "bidirectional"))
      (node (ref "C578") (pin "2") (pinfunction "2_2") (pintype "bidirectional"))
      (node (ref "R205") (pin "1") (pinfunction "1_1") (pintype "passive"))
      (node (ref "R206") (pin "2") (pinfunction "2_2") (pintype "bidirectional"))
      (node (ref "R208") (pin "2") (pinfunction "2_2") (pintype "bidirectional"))
      (node (ref "R219") (pin "1") (pinfunction "1_1") (pintype "bidirectional"))
      (node (ref "R229") (pin "2") (pinfunction "2_2") (pintype "bidirectional"))
      (node (ref "R230") (pin "2") (pinfunction "2_2") (pintype "bidirectional"))
      (node (ref "R52") (pin "2") (pinfunction "2_2") (pintype "bidirectional"))
      (node (ref "R54") (pin "2") (pinfunction "2_2") (pintype "bidirectional"))
      (node (ref "R72") (pin "2") (pinfunction "2_2") (pintype "bidirectional"))
      (node (ref "TP24") (pin "TP") (pinfunction "TP_TP") (pintype "input"))
      (node (ref "U11") (pin "6") (pinfunction "IN_6") (pintype "power_in"))
      (node (ref "U35") (pin "7") (pinfunction "VIN_7") (pintype "power_in"))
      (node (ref "U38") (pin "A1") (pinfunction "AVIN_A1") (pintype "power_in"))
      (node (ref "U38") (pin "A3") (pinfunction "VSEL1_A3") (pintype "input"))
      (node (ref "U38") (pin "A4") (pinfunction "VIN_A4") (pintype "power_in"))
      (node (ref "U38") (pin "C2") (pinfunction "VSEL0_C2") (pintype "input"))
      (node (ref "U4") (pin "A1") (pinfunction "AVIN_A1") (pintype "power_in"))
      (node (ref "U4") (pin "A3") (pinfunction "VSEL1_A3") (pintype "input"))
      (node (ref "U4") (pin "A4") (pinfunction "VIN_A4") (pintype "power_in"))
      (node (ref "U4") (pin "C2") (pinfunction "VSEL0_C2") (pintype "input"))
      (node (ref "U40") (pin "6") (pinfunction "IN_6") (pintype "power_in"))
      (node (ref "U77") (pin "6") (pinfunction "VCC_6") (pintype "power_in"))
    )
    (net (code "317") (name "VCC_3V3_PREREG_PG") (class "Default")
      (node (ref "C165") (pin "2") (pinfunction "2_2") (pintype "bidirectional"))
      (node (ref "R208") (pin "1") (pinfunction "1_1") (pintype "bidirectional"))
      (node (ref "U34") (pin "24") (pinfunction "PG1_24") (pintype "open_collector"))
    )
    (net (code "318") (name "VCC_5V0") (class "Default")
      (node (ref "C144") (pin "1") (pinfunction "+_1") (pintype "bidirectional"))
      (node (ref "C145") (pin "1") (pinfunction "+_1") (pintype "bidirectional"))
      (node (ref "C160") (pin "1") (pinfunction "1_1") (pintype "bidirectional"))
      (node (ref "C174") (pin "2") (pinfunction "2_2") (pintype "bidirectional"))
      (node (ref "C177") (pin "2") (pinfunction "2_2") (pintype "bidirectional"))
      (node (ref "C179") (pin "1") (pinfunction "1_1") (pintype "bidirectional"))
      (node (ref "C180") (pin "2") (pinfunction "2_2") (pintype "bidirectional"))
      (node (ref "C223") (pin "2") (pinfunction "2_2") (pintype "bidirectional"))
      (node (ref "C224") (pin "2") (pinfunction "2_2") (pintype "bidirectional"))
      (node (ref "C39") (pin "1") (pinfunction "1_1") (pintype "bidirectional"))
      (node (ref "C41") (pin "2") (pinfunction "2_2") (pintype "bidirectional"))
      (node (ref "C45") (pin "2") (pinfunction "2_2") (pintype "bidirectional"))
      (node (ref "C46") (pin "2") (pinfunction "2_2") (pintype "bidirectional"))
      (node (ref "C47") (pin "2") (pinfunction "2_2") (pintype "bidirectional"))
      (node (ref "HDMI") (pin "P$18") (pinfunction "VCC_P$18") (pintype "bidirectional"))
      (node (ref "J1") (pin "B21") (pinfunction "21_B21") (pintype "bidirectional"))
      (node (ref "R14") (pin "2") (pinfunction "2_2") (pintype "bidirectional"))
      (node (ref "R15") (pin "2") (pinfunction "2_2") (pintype "bidirectional"))
      (node (ref "R216") (pin "2") (pinfunction "2_2") (pintype "bidirectional"))
      (node (ref "R217") (pin "2") (pinfunction "2_2") (pintype "passive"))
      (node (ref "R220") (pin "1") (pinfunction "1_1") (pintype "bidirectional"))
      (node (ref "TP25") (pin "TP") (pinfunction "TP_TP") (pintype "input"))
      (node (ref "U15") (pin "2") (pinfunction "IN_2_2") (pintype "input"))
      (node (ref "U15") (pin "3") (pinfunction "IN_3") (pintype "input"))
      (node (ref "U16") (pin "2") (pinfunction "IN_2_2") (pintype "input"))
      (node (ref "U16") (pin "3") (pinfunction "IN_3") (pintype "input"))
      (node (ref "U19") (pin "3") (pinfunction "VCC_3") (pintype "power_in"))
      (node (ref "U34") (pin "6") (pinfunction "VCCX_6") (pintype "power_in"))
      (node (ref "U6") (pin "14") (pinfunction "V5IN_14") (pintype "input"))
      (node (ref "U6") (pin "8") (pinfunction "COMP_8") (pintype "bidirectional"))
    )
    (net (code "319") (name "VCC_5V0_PG") (class "Default")
      (node (ref "R243") (pin "2") (pinfunction "2_2") (pintype "bidirectional"))
      (node (ref "U34") (pin "7") (pinfunction "PG2_7") (pintype "open_collector"))
    )
    (net (code "320") (name "VCC_12V0") (class "Default")
      (node (ref "C146") (pin "1") (pinfunction "+_1") (pintype "bidirectional"))
      (node (ref "C147") (pin "1") (pinfunction "+_1") (pintype "bidirectional"))
      (node (ref "C159") (pin "2") (pinfunction "2_2") (pintype "bidirectional"))
      (node (ref "C161") (pin "2") (pinfunction "2_2") (pintype "bidirectional"))
      (node (ref "C162") (pin "2") (pinfunction "2_2") (pintype "bidirectional"))
      (node (ref "C163") (pin "2") (pinfunction "2_2") (pintype "bidirectional"))
      (node (ref "C164") (pin "2") (pinfunction "2_2") (pintype "bidirectional"))
      (node (ref "C166") (pin "1") (pinfunction "1_1") (pintype "bidirectional"))
      (node (ref "C167") (pin "1") (pinfunction "1_1") (pintype "bidirectional"))
      (node (ref "C168") (pin "1") (pinfunction "1_1") (pintype "bidirectional"))
      (node (ref "C193") (pin "2") (pinfunction "2_2") (pintype "bidirectional"))
      (node (ref "C194") (pin "2") (pinfunction "2_2") (pintype "bidirectional"))
      (node (ref "C36") (pin "2") (pinfunction "2_2") (pintype "bidirectional"))
      (node (ref "C37") (pin "2") (pinfunction "2_2") (pintype "bidirectional"))
      (node (ref "C574") (pin "2") (pinfunction "2_2") (pintype "bidirectional"))
      (node (ref "J1") (pin "A1") (pinfunction "1_A1") (pintype "bidirectional"))
      (node (ref "J1") (pin "A10") (pinfunction "10_A10") (pintype "bidirectional"))
      (node (ref "J1") (pin "A2") (pinfunction "2_A2") (pintype "bidirectional"))
      (node (ref "J1") (pin "A3") (pinfunction "3_A3") (pintype "bidirectional"))
      (node (ref "J1") (pin "A4") (pinfunction "4_A4") (pintype "bidirectional"))
      (node (ref "J1") (pin "A5") (pinfunction "5_A5") (pintype "bidirectional"))
      (node (ref "J1") (pin "A6") (pinfunction "6_A6") (pintype "bidirectional"))
      (node (ref "J1") (pin "A7") (pinfunction "7_A7") (pintype "bidirectional"))
      (node (ref "J1") (pin "A8") (pinfunction "8_A8") (pintype "bidirectional"))
      (node (ref "J1") (pin "A9") (pinfunction "9_A9") (pintype "bidirectional"))
      (node (ref "Q11") (pin "5-9") (pinfunction "D_5-9") (pintype "passive"))
      (node (ref "Q8") (pin "5-9") (pinfunction "D_5-9") (pintype "passive"))
      (node (ref "R536") (pin "2") (pinfunction "2_2") (pintype "bidirectional"))
      (node (ref "U$2") (pin "5") (pinfunction "DRAIN_5") (pintype "bidirectional"))
      (node (ref "U$2") (pin "6") (pinfunction "DRAIN_6") (pintype "bidirectional"))
      (node (ref "U$2") (pin "7") (pinfunction "DRAIN_7") (pintype "bidirectional"))
      (node (ref "U$2") (pin "8") (pinfunction "DRAIN_8") (pintype "bidirectional"))
      (node (ref "U34") (pin "25") (pinfunction "VIN_25") (pintype "power_in"))
      (node (ref "U34") (pin "31") (pinfunction "EN1_31") (pintype "input"))
      (node (ref "U34") (pin "40") (pinfunction "EN2_40") (pintype "input"))
      (node (ref "U41") (pin "1") (pinfunction "VIN_1") (pintype "power_in"))
      (node (ref "U76") (pin "5") (pinfunction "VDD_5") (pintype "power_in"))
    )
    (net (code "321") (name "VCC_LM5140") (class "Default")
      (node (ref "C148") (pin "2") (pinfunction "2_2") (pintype "bidirectional"))
      (node (ref "C149") (pin "2") (pinfunction "2_2") (pintype "bidirectional"))
      (node (ref "U$20") (pin "ANODE") (pinfunction "ANODE_ANODE") (pintype "bidirectional"))
      (node (ref "U$21") (pin "ANODE") (pinfunction "ANODE_ANODE") (pintype "bidirectional"))
      (node (ref "U34") (pin "15") (pinfunction "VCC_2_15") (pintype "power_in"))
      (node (ref "U34") (pin "16") (pinfunction "VCC_16") (pintype "power_in"))
    )
    (net (code "322") (name "VDDA_1V8") (class "Default")
      (node (ref "C191") (pin "1") (pinfunction "1_1") (pintype "bidirectional"))
      (node (ref "C73") (pin "2") (pinfunction "2_2") (pintype "bidirectional"))
      (node (ref "TP31") (pin "TP") (pinfunction "TP_TP") (pintype "input"))
      (node (ref "U1") (pin "D8") (pinfunction "VDDA_ADC_D8") (pintype "power_in"))
      (node (ref "U40") (pin "1") (pinfunction "OUT_1") (pintype "power_in"))
    )
    (net (code "323") (name "VDDA_1V8_PG") (class "Default")
      (node (ref "C192") (pin "1") (pinfunction "1_1") (pintype "bidirectional"))
      (node (ref "R229") (pin "1") (pinfunction "1_1") (pintype "bidirectional"))
      (node (ref "U40") (pin "3") (pinfunction "PG_3") (pintype "output"))
    )
    (net (code "324") (name "VDDA_LM5140") (class "Default")
      (node (ref "C150") (pin "1") (pinfunction "1_1") (pintype "bidirectional"))
      (node (ref "R243") (pin "1") (pinfunction "1_1") (pintype "bidirectional"))
      (node (ref "U34") (pin "28") (pinfunction "FB1_28") (pintype "input"))
      (node (ref "U34") (pin "3") (pinfunction "FB2_3") (pintype "input"))
      (node (ref "U34") (pin "33") (pinfunction "DEMB_33") (pintype "input"))
      (node (ref "U34") (pin "34") (pinfunction "ILSET_34") (pintype "input"))
      (node (ref "U34") (pin "36") (pinfunction "VDDA_36") (pintype "power_in"))
      (node (ref "U34") (pin "37") (pinfunction "OSC_37") (pintype "input"))
    )
    (net (code "325") (name "VDDS_DDR") (class "Default")
      (node (ref "C48") (pin "2") (pinfunction "2_2") (pintype "bidirectional"))
      (node (ref "C49") (pin "2") (pinfunction "2_2") (pintype "bidirectional"))
      (node (ref "C50") (pin "2") (pinfunction "2_2") (pintype "bidirectional"))
      (node (ref "C51") (pin "2") (pinfunction "2_2") (pintype "bidirectional"))
      (node (ref "C52") (pin "2") (pinfunction "2_2") (pintype "bidirectional"))
      (node (ref "C53") (pin "2") (pinfunction "2_2") (pintype "bidirectional"))
      (node (ref "C54") (pin "2") (pinfunction "2_2") (pintype "bidirectional"))
      (node (ref "C55") (pin "2") (pinfunction "2_2") (pintype "bidirectional"))
      (node (ref "C56") (pin "2") (pinfunction "2_2") (pintype "bidirectional"))
      (node (ref "C57") (pin "2") (pinfunction "2_2") (pintype "bidirectional"))
      (node (ref "C61") (pin "1") (pinfunction "1_1") (pintype "bidirectional"))
      (node (ref "C62") (pin "2") (pinfunction "2_2") (pintype "bidirectional"))
      (node (ref "C63") (pin "2") (pinfunction "2_2") (pintype "bidirectional"))
      (node (ref "R8") (pin "2") (pinfunction "2_2") (pintype "bidirectional"))
      (node (ref "R9") (pin "2") (pinfunction "2_2") (pintype "bidirectional"))
      (node (ref "U9") (pin "A1") (pinfunction "VDDQ_A1") (pintype "bidirectional"))
      (node (ref "U9") (pin "A8") (pinfunction "VDDQ_A8") (pintype "bidirectional"))
      (node (ref "U9") (pin "B2") (pinfunction "VDD_B2") (pintype "bidirectional"))
      (node (ref "U9") (pin "C1") (pinfunction "VDDQ_C1") (pintype "bidirectional"))
      (node (ref "U9") (pin "C9") (pinfunction "VDDQ_C9") (pintype "bidirectional"))
      (node (ref "U9") (pin "D2") (pinfunction "VDDQ_D2") (pintype "bidirectional"))
      (node (ref "U9") (pin "D9") (pinfunction "VDD_D9") (pintype "bidirectional"))
      (node (ref "U9") (pin "E9") (pinfunction "VDDQ_E9") (pintype "bidirectional"))
      (node (ref "U9") (pin "F1") (pinfunction "VDDQ_F1") (pintype "bidirectional"))
      (node (ref "U9") (pin "G7") (pinfunction "VDD_G7") (pintype "bidirectional"))
      (node (ref "U9") (pin "H2") (pinfunction "VDDQ_H2") (pintype "bidirectional"))
      (node (ref "U9") (pin "H9") (pinfunction "VDDQ_H9") (pintype "bidirectional"))
      (node (ref "U9") (pin "K2") (pinfunction "VDD_K2") (pintype "bidirectional"))
      (node (ref "U9") (pin "K8") (pinfunction "VDD_K8") (pintype "bidirectional"))
      (node (ref "U9") (pin "N1") (pinfunction "VDD_N1") (pintype "bidirectional"))
      (node (ref "U9") (pin "N9") (pinfunction "VDD_N9") (pintype "bidirectional"))
      (node (ref "U9") (pin "R1") (pinfunction "VDD_R1") (pintype "bidirectional"))
      (node (ref "U9") (pin "R9") (pinfunction "VDD_R9") (pintype "bidirectional"))
    )
    (net (code "326") (name "VDDS_DDR_PGOOD") (class "Default")
      (node (ref "R15") (pin "1") (pinfunction "1_1") (pintype "bidirectional"))
      (node (ref "U41") (pin "8") (pinfunction "EN_8") (pintype "input"))
      (node (ref "U6") (pin "13") (pinfunction "PGOOD_13") (pintype "output"))
    )
    (net (code "327") (name "VDD_CORE") (class "Default")
      (node (ref "C14") (pin "2") (pinfunction "2_2") (pintype "bidirectional"))
      (node (ref "C15") (pin "2") (pinfunction "2_2") (pintype "bidirectional"))
      (node (ref "C16") (pin "2") (pinfunction "2_2") (pintype "bidirectional"))
      (node (ref "C17") (pin "2") (pinfunction "2_2") (pintype "bidirectional"))
      (node (ref "C18") (pin "2") (pinfunction "2_2") (pintype "bidirectional"))
      (node (ref "C19") (pin "2") (pinfunction "2_2") (pintype "bidirectional"))
      (node (ref "C20") (pin "2") (pinfunction "2_2") (pintype "bidirectional"))
      (node (ref "C21") (pin "2") (pinfunction "2_2") (pintype "bidirectional"))
      (node (ref "C22") (pin "2") (pinfunction "2_2") (pintype "bidirectional"))
      (node (ref "R2") (pin "2") (pinfunction "2_2") (pintype "bidirectional"))
      (node (ref "R3") (pin "2") (pinfunction "2_2") (pintype "bidirectional"))
      (node (ref "U1") (pin "F6") (pinfunction "VDD_CORE_3_F6") (pintype "power_in"))
      (node (ref "U1") (pin "F7") (pinfunction "VDD_CORE_15_F7") (pintype "power_in"))
      (node (ref "U1") (pin "G10") (pinfunction "VDD_CORE_4_G10") (pintype "power_in"))
      (node (ref "U1") (pin "G6") (pinfunction "VDD_CORE_5_G6") (pintype "power_in"))
      (node (ref "U1") (pin "G7") (pinfunction "VDD_CORE_9_G7") (pintype "power_in"))
      (node (ref "U1") (pin "H11") (pinfunction "VDD_CORE_8_H11") (pintype "power_in"))
      (node (ref "U1") (pin "J12") (pinfunction "VDD_CORE_12_J12") (pintype "power_in"))
      (node (ref "U1") (pin "K12") (pinfunction "VDD_CORE_16_K12") (pintype "power_in"))
      (node (ref "U1") (pin "K6") (pinfunction "VDD_CORE_17_K6") (pintype "power_in"))
      (node (ref "U1") (pin "K8") (pinfunction "VDD_CORE_7_K8") (pintype "power_in"))
      (node (ref "U1") (pin "L6") (pinfunction "VDD_CORE_13_L6") (pintype "power_in"))
      (node (ref "U1") (pin "L7") (pinfunction "VDD_CORE_11_L7") (pintype "power_in"))
      (node (ref "U1") (pin "L8") (pinfunction "VDD_CORE_2_L8") (pintype "power_in"))
      (node (ref "U1") (pin "L9") (pinfunction "VDD_CORE_6_L9") (pintype "power_in"))
      (node (ref "U1") (pin "M11") (pinfunction "VDD_CORE_18_M11") (pintype "power_in"))
      (node (ref "U1") (pin "M13") (pinfunction "VDD_CORE_19_M13") (pintype "power_in"))
      (node (ref "U1") (pin "N12") (pinfunction "VDD_CORE_20_N12") (pintype "power_in"))
      (node (ref "U1") (pin "N13") (pinfunction "VDD_CORE_N13") (pintype "power_in"))
      (node (ref "U1") (pin "N8") (pinfunction "VDD_CORE_10_N8") (pintype "power_in"))
      (node (ref "U1") (pin "N9") (pinfunction "VDD_CORE_14_N9") (pintype "power_in"))
      (node (ref "U38") (pin "B1") (pinfunction "SENSE+_B1") (pintype "input"))
    )
    (net (code "328") (name "VDD_MPU") (class "Default")
      (node (ref "C23") (pin "2") (pinfunction "2_2") (pintype "bidirectional"))
      (node (ref "C24") (pin "2") (pinfunction "2_2") (pintype "bidirectional"))
      (node (ref "C25") (pin "2") (pinfunction "2_2") (pintype "bidirectional"))
      (node (ref "C26") (pin "2") (pinfunction "2_2") (pintype "bidirectional"))
      (node (ref "C27") (pin "2") (pinfunction "2_2") (pintype "bidirectional"))
      (node (ref "C28") (pin "2") (pinfunction "2_2") (pintype "bidirectional"))
      (node (ref "R5") (pin "2") (pinfunction "2_2") (pintype "bidirectional"))
      (node (ref "R540") (pin "2") (pinfunction "2_2") (pintype "bidirectional"))
      (node (ref "R6") (pin "2") (pinfunction "2_2") (pintype "bidirectional"))
      (node (ref "U1") (pin "A2") (pinfunction "VDD_MPU_MON_A2") (pintype "power_in"))
      (node (ref "U1") (pin "F10") (pinfunction "VDD_MPU_2_F10") (pintype "power_in"))
      (node (ref "U1") (pin "F11") (pinfunction "VDD_MPU_3_F11") (pintype "power_in"))
      (node (ref "U1") (pin "F12") (pinfunction "VDD_MPU_5_F12") (pintype "power_in"))
      (node (ref "U1") (pin "F13") (pinfunction "VDD_MPU_4_F13") (pintype "power_in"))
      (node (ref "U1") (pin "G13") (pinfunction "VDD_MPU_6_G13") (pintype "power_in"))
      (node (ref "U1") (pin "H13") (pinfunction "VDD_MPU_7_H13") (pintype "power_in"))
      (node (ref "U1") (pin "J13") (pinfunction "VDD_MPU_J13") (pintype "power_in"))
      (node (ref "U4") (pin "B1") (pinfunction "SENSE+_B1") (pintype "input"))
    )
    (net (code "329") (name "VDD_RTC") (class "Default")
      (node (ref "C74") (pin "2") (pinfunction "2_2") (pintype "bidirectional"))
      (node (ref "C86") (pin "1") (pinfunction "1_1") (pintype "bidirectional"))
      (node (ref "TP2") (pin "TP") (pinfunction "TP_TP") (pintype "input"))
      (node (ref "U1") (pin "D7") (pinfunction "VDDS_RTC_D7") (pintype "power_in"))
      (node (ref "U11") (pin "1") (pinfunction "OUT_1") (pintype "power_in"))
    )
    (net (code "330") (name "VDD_RTC_PG") (class "Default")
      (node (ref "C87") (pin "1") (pinfunction "1_1") (pintype "bidirectional"))
      (node (ref "R52") (pin "1") (pinfunction "1_1") (pintype "bidirectional"))
      (node (ref "U11") (pin "3") (pinfunction "PG_3") (pintype "output"))
      (node (ref "U35") (pin "1") (pinfunction "EN_1") (pintype "input"))
      (node (ref "U40") (pin "4") (pinfunction "EN_4") (pintype "input"))
    )
    (net (code "331") (name "VIN_MON_PORZ_3V3_PG") (class "Default")
      (node (ref "C216") (pin "2") (pinfunction "2_2") (pintype "bidirectional"))
      (node (ref "R230") (pin "1") (pinfunction "1_1") (pintype "bidirectional"))
      (node (ref "R538") (pin "1") (pinfunction "1_1") (pintype "bidirectional"))
      (node (ref "U11") (pin "4") (pinfunction "EN_4") (pintype "input"))
      (node (ref "U13") (pin "2") (pinfunction "A_2") (pintype "input"))
      (node (ref "U38") (pin "B2") (pinfunction "EN_B2") (pintype "input"))
      (node (ref "U4") (pin "B2") (pinfunction "EN_B2") (pintype "input"))
      (node (ref "U41") (pin "10") (pinfunction "PGOOD_10") (pintype "open_collector"))
      (node (ref "U76") (pin "1") (pinfunction "OUT_1") (pintype "open_collector"))
      (node (ref "U78") (pin "3") (pinfunction "B_3") (pintype "input"))
    )
    (net (code "332") (name "VPP") (class "Default")
      (node (ref "U1") (pin "M5") (pinfunction "VPP_M5") (pintype "power_in"))
    )
    (net (code "333") (name "VSS") (class "Default")
      (node (ref "C1") (pin "1") (pinfunction "1_1") (pintype "bidirectional"))
      (node (ref "C100") (pin "1") (pinfunction "1_1") (pintype "bidirectional"))
      (node (ref "C101") (pin "1") (pinfunction "1_1") (pintype "bidirectional"))
      (node (ref "C102") (pin "1") (pinfunction "1_1") (pintype "bidirectional"))
      (node (ref "C103") (pin "1") (pinfunction "1_1") (pintype "bidirectional"))
      (node (ref "C104") (pin "1") (pinfunction "1_1") (pintype "bidirectional"))
      (node (ref "C105") (pin "1") (pinfunction "1_1") (pintype "bidirectional"))
      (node (ref "C106") (pin "1") (pinfunction "1_1") (pintype "bidirectional"))
      (node (ref "C107") (pin "1") (pinfunction "1_1") (pintype "bidirectional"))
      (node (ref "C108") (pin "1") (pinfunction "1_1") (pintype "bidirectional"))
      (node (ref "C109") (pin "1") (pinfunction "1_1") (pintype "bidirectional"))
      (node (ref "C11") (pin "2") (pinfunction "2_2") (pintype "bidirectional"))
      (node (ref "C110") (pin "1") (pinfunction "1_1") (pintype "bidirectional"))
      (node (ref "C111") (pin "1") (pinfunction "1_1") (pintype "bidirectional"))
      (node (ref "C112") (pin "1") (pinfunction "1_1") (pintype "bidirectional"))
      (node (ref "C113") (pin "1") (pinfunction "1_1") (pintype "bidirectional"))
      (node (ref "C114") (pin "1") (pinfunction "1_1") (pintype "bidirectional"))
      (node (ref "C115") (pin "1") (pinfunction "1_1") (pintype "bidirectional"))
      (node (ref "C116") (pin "1") (pinfunction "1_1") (pintype "bidirectional"))
      (node (ref "C117") (pin "1") (pinfunction "1_1") (pintype "bidirectional"))
      (node (ref "C118") (pin "2") (pinfunction "2_2") (pintype "bidirectional"))
      (node (ref "C119") (pin "1") (pinfunction "1_1") (pintype "bidirectional"))
      (node (ref "C120") (pin "1") (pinfunction "1_1") (pintype "bidirectional"))
      (node (ref "C121") (pin "1") (pinfunction "1_1") (pintype "bidirectional"))
      (node (ref "C122") (pin "1") (pinfunction "1_1") (pintype "bidirectional"))
      (node (ref "C123") (pin "1") (pinfunction "1_1") (pintype "bidirectional"))
      (node (ref "C124") (pin "1") (pinfunction "1_1") (pintype "bidirectional"))
      (node (ref "C125") (pin "1") (pinfunction "1_1") (pintype "bidirectional"))
      (node (ref "C126") (pin "1") (pinfunction "1_1") (pintype "bidirectional"))
      (node (ref "C127") (pin "1") (pinfunction "1_1") (pintype "bidirectional"))
      (node (ref "C128") (pin "1") (pinfunction "1_1") (pintype "bidirectional"))
      (node (ref "C129") (pin "1") (pinfunction "1_1") (pintype "bidirectional"))
      (node (ref "C13") (pin "1") (pinfunction "1_1") (pintype "bidirectional"))
      (node (ref "C130") (pin "1") (pinfunction "1_1") (pintype "bidirectional"))
      (node (ref "C131") (pin "1") (pinfunction "1_1") (pintype "bidirectional"))
      (node (ref "C132") (pin "1") (pinfunction "1_1") (pintype "bidirectional"))
      (node (ref "C133") (pin "1") (pinfunction "1_1") (pintype "bidirectional"))
      (node (ref "C134") (pin "1") (pinfunction "1_1") (pintype "bidirectional"))
      (node (ref "C139") (pin "1") (pinfunction "1_1") (pintype "bidirectional"))
      (node (ref "C14") (pin "1") (pinfunction "1_1") (pintype "bidirectional"))
      (node (ref "C140") (pin "1") (pinfunction "1_1") (pintype "bidirectional"))
      (node (ref "C141") (pin "2") (pinfunction "2_2") (pintype "bidirectional"))
      (node (ref "C142") (pin "2") (pinfunction "-_2") (pintype "bidirectional"))
      (node (ref "C143") (pin "2") (pinfunction "-_2") (pintype "bidirectional"))
      (node (ref "C144") (pin "2") (pinfunction "-_2") (pintype "bidirectional"))
      (node (ref "C145") (pin "2") (pinfunction "-_2") (pintype "bidirectional"))
      (node (ref "C146") (pin "2") (pinfunction "-_2") (pintype "bidirectional"))
      (node (ref "C147") (pin "2") (pinfunction "-_2") (pintype "bidirectional"))
      (node (ref "C148") (pin "1") (pinfunction "1_1") (pintype "bidirectional"))
      (node (ref "C149") (pin "1") (pinfunction "1_1") (pintype "bidirectional"))
      (node (ref "C15") (pin "1") (pinfunction "1_1") (pintype "bidirectional"))
      (node (ref "C150") (pin "2") (pinfunction "2_2") (pintype "bidirectional"))
      (node (ref "C151") (pin "1") (pinfunction "1_1") (pintype "bidirectional"))
      (node (ref "C154") (pin "1") (pinfunction "1_1") (pintype "bidirectional"))
      (node (ref "C155") (pin "1") (pinfunction "1_1") (pintype "bidirectional"))
      (node (ref "C156") (pin "1") (pinfunction "1_1") (pintype "bidirectional"))
      (node (ref "C157") (pin "1") (pinfunction "1_1") (pintype "bidirectional"))
      (node (ref "C158") (pin "2") (pinfunction "2_2") (pintype "bidirectional"))
      (node (ref "C159") (pin "1") (pinfunction "1_1") (pintype "bidirectional"))
      (node (ref "C16") (pin "1") (pinfunction "1_1") (pintype "bidirectional"))
      (node (ref "C160") (pin "2") (pinfunction "2_2") (pintype "bidirectional"))
      (node (ref "C161") (pin "1") (pinfunction "1_1") (pintype "bidirectional"))
      (node (ref "C162") (pin "1") (pinfunction "1_1") (pintype "bidirectional"))
      (node (ref "C163") (pin "1") (pinfunction "1_1") (pintype "bidirectional"))
      (node (ref "C164") (pin "1") (pinfunction "1_1") (pintype "bidirectional"))
      (node (ref "C165") (pin "1") (pinfunction "1_1") (pintype "bidirectional"))
      (node (ref "C166") (pin "2") (pinfunction "2_2") (pintype "bidirectional"))
      (node (ref "C167") (pin "2") (pinfunction "2_2") (pintype "bidirectional"))
      (node (ref "C168") (pin "2") (pinfunction "2_2") (pintype "bidirectional"))
      (node (ref "C17") (pin "1") (pinfunction "1_1") (pintype "bidirectional"))
      (node (ref "C171") (pin "1") (pinfunction "1_1") (pintype "bidirectional"))
      (node (ref "C172") (pin "2") (pinfunction "2_2") (pintype "bidirectional"))
      (node (ref "C173") (pin "2") (pinfunction "2_2") (pintype "bidirectional"))
      (node (ref "C174") (pin "1") (pinfunction "1_1") (pintype "bidirectional"))
      (node (ref "C175") (pin "1") (pinfunction "1_1") (pintype "bidirectional"))
      (node (ref "C176") (pin "1") (pinfunction "1_1") (pintype "bidirectional"))
      (node (ref "C177") (pin "1") (pinfunction "1_1") (pintype "bidirectional"))
      (node (ref "C178") (pin "2") (pinfunction "2_2") (pintype "bidirectional"))
      (node (ref "C179") (pin "2") (pinfunction "2_2") (pintype "bidirectional"))
      (node (ref "C18") (pin "1") (pinfunction "1_1") (pintype "bidirectional"))
      (node (ref "C180") (pin "1") (pinfunction "1_1") (pintype "bidirectional"))
      (node (ref "C181") (pin "1") (pinfunction "1_1") (pintype "bidirectional"))
      (node (ref "C182") (pin "1") (pinfunction "1_1") (pintype "bidirectional"))
      (node (ref "C183") (pin "1") (pinfunction "1_1") (pintype "bidirectional"))
      (node (ref "C184") (pin "1") (pinfunction "1_1") (pintype "bidirectional"))
      (node (ref "C185") (pin "2") (pinfunction "2_2") (pintype "bidirectional"))
      (node (ref "C186") (pin "1") (pinfunction "1_1") (pintype "bidirectional"))
      (node (ref "C187") (pin "1") (pinfunction "1_1") (pintype "bidirectional"))
      (node (ref "C188") (pin "1") (pinfunction "1_1") (pintype "bidirectional"))
      (node (ref "C189") (pin "1") (pinfunction "1_1") (pintype "bidirectional"))
      (node (ref "C19") (pin "1") (pinfunction "1_1") (pintype "bidirectional"))
      (node (ref "C190") (pin "1") (pinfunction "1_1") (pintype "bidirectional"))
      (node (ref "C191") (pin "2") (pinfunction "2_2") (pintype "bidirectional"))
      (node (ref "C192") (pin "2") (pinfunction "2_2") (pintype "bidirectional"))
      (node (ref "C193") (pin "1") (pinfunction "1_1") (pintype "bidirectional"))
      (node (ref "C194") (pin "1") (pinfunction "1_1") (pintype "bidirectional"))
      (node (ref "C196") (pin "2") (pinfunction "2_2") (pintype "bidirectional"))
      (node (ref "C197") (pin "2") (pinfunction "2_2") (pintype "bidirectional"))
      (node (ref "C198") (pin "1") (pinfunction "1_1") (pintype "bidirectional"))
      (node (ref "C199") (pin "1") (pinfunction "1_1") (pintype "bidirectional"))
      (node (ref "C20") (pin "1") (pinfunction "1_1") (pintype "bidirectional"))
      (node (ref "C201") (pin "1") (pinfunction "1_1") (pintype "bidirectional"))
      (node (ref "C202") (pin "1") (pinfunction "1_1") (pintype "bidirectional"))
      (node (ref "C203") (pin "1") (pinfunction "1_1") (pintype "bidirectional"))
      (node (ref "C204") (pin "1") (pinfunction "1_1") (pintype "bidirectional"))
      (node (ref "C205") (pin "1") (pinfunction "1_1") (pintype "bidirectional"))
      (node (ref "C206") (pin "1") (pinfunction "1_1") (pintype "bidirectional"))
      (node (ref "C207") (pin "1") (pinfunction "1_1") (pintype "bidirectional"))
      (node (ref "C208") (pin "1") (pinfunction "1_1") (pintype "bidirectional"))
      (node (ref "C209") (pin "1") (pinfunction "1_1") (pintype "bidirectional"))
      (node (ref "C21") (pin "1") (pinfunction "1_1") (pintype "bidirectional"))
      (node (ref "C210") (pin "1") (pinfunction "1_1") (pintype "bidirectional"))
      (node (ref "C211") (pin "1") (pinfunction "1_1") (pintype "bidirectional"))
      (node (ref "C212") (pin "2") (pinfunction "2_2") (pintype "bidirectional"))
      (node (ref "C213") (pin "1") (pinfunction "1_1") (pintype "bidirectional"))
      (node (ref "C214") (pin "1") (pinfunction "1_1") (pintype "bidirectional"))
      (node (ref "C215") (pin "1") (pinfunction "1_1") (pintype "bidirectional"))
      (node (ref "C216") (pin "1") (pinfunction "1_1") (pintype "bidirectional"))
      (node (ref "C217") (pin "1") (pinfunction "1_1") (pintype "bidirectional"))
      (node (ref "C218") (pin "1") (pinfunction "1_1") (pintype "bidirectional"))
      (node (ref "C219") (pin "1") (pinfunction "1_1") (pintype "bidirectional"))
      (node (ref "C22") (pin "1") (pinfunction "1_1") (pintype "bidirectional"))
      (node (ref "C220") (pin "1") (pinfunction "1_1") (pintype "bidirectional"))
      (node (ref "C221") (pin "1") (pinfunction "1_1") (pintype "bidirectional"))
      (node (ref "C222") (pin "2") (pinfunction "2_2") (pintype "bidirectional"))
      (node (ref "C223") (pin "1") (pinfunction "1_1") (pintype "bidirectional"))
      (node (ref "C224") (pin "1") (pinfunction "1_1") (pintype "bidirectional"))
      (node (ref "C225") (pin "1") (pinfunction "1_1") (pintype "bidirectional"))
      (node (ref "C226") (pin "1") (pinfunction "1_1") (pintype "bidirectional"))
      (node (ref "C227") (pin "2") (pinfunction "2_2") (pintype "bidirectional"))
      (node (ref "C228") (pin "2") (pinfunction "2_2") (pintype "bidirectional"))
      (node (ref "C229") (pin "2") (pinfunction "2_2") (pintype "bidirectional"))
      (node (ref "C23") (pin "1") (pinfunction "1_1") (pintype "bidirectional"))
      (node (ref "C230") (pin "1") (pinfunction "1_1") (pintype "bidirectional"))
      (node (ref "C231") (pin "2") (pinfunction "2_2") (pintype "bidirectional"))
      (node (ref "C232") (pin "2") (pinfunction "2_2") (pintype "bidirectional"))
      (node (ref "C233") (pin "2") (pinfunction "2_2") (pintype "bidirectional"))
      (node (ref "C234") (pin "2") (pinfunction "2_2") (pintype "bidirectional"))
      (node (ref "C235") (pin "1") (pinfunction "1_1") (pintype "bidirectional"))
      (node (ref "C236") (pin "2") (pinfunction "2_2") (pintype "bidirectional"))
      (node (ref "C237") (pin "1") (pinfunction "1_1") (pintype "bidirectional"))
      (node (ref "C238") (pin "1") (pinfunction "1_1") (pintype "bidirectional"))
      (node (ref "C239") (pin "1") (pinfunction "1_1") (pintype "bidirectional"))
      (node (ref "C24") (pin "1") (pinfunction "1_1") (pintype "bidirectional"))
      (node (ref "C25") (pin "1") (pinfunction "1_1") (pintype "bidirectional"))
      (node (ref "C26") (pin "1") (pinfunction "1_1") (pintype "bidirectional"))
      (node (ref "C27") (pin "1") (pinfunction "1_1") (pintype "bidirectional"))
      (node (ref "C28") (pin "1") (pinfunction "1_1") (pintype "bidirectional"))
      (node (ref "C3") (pin "2") (pinfunction "2_2") (pintype "bidirectional"))
      (node (ref "C30") (pin "2") (pinfunction "2_2") (pintype "bidirectional"))
      (node (ref "C31") (pin "1") (pinfunction "1_1") (pintype "bidirectional"))
      (node (ref "C33") (pin "2") (pinfunction "2_2") (pintype "bidirectional"))
      (node (ref "C34") (pin "2") (pinfunction "-_2") (pintype "bidirectional"))
      (node (ref "C35") (pin "2") (pinfunction "-_2") (pintype "bidirectional"))
      (node (ref "C36") (pin "1") (pinfunction "1_1") (pintype "bidirectional"))
      (node (ref "C37") (pin "1") (pinfunction "1_1") (pintype "bidirectional"))
      (node (ref "C38") (pin "1") (pinfunction "1_1") (pintype "bidirectional"))
      (node (ref "C4") (pin "1") (pinfunction "1_1") (pintype "bidirectional"))
      (node (ref "C41") (pin "1") (pinfunction "1_1") (pintype "bidirectional"))
      (node (ref "C42") (pin "1") (pinfunction "1_1") (pintype "bidirectional"))
      (node (ref "C43") (pin "1") (pinfunction "1_1") (pintype "bidirectional"))
      (node (ref "C44") (pin "1") (pinfunction "1_1") (pintype "bidirectional"))
      (node (ref "C45") (pin "1") (pinfunction "1_1") (pintype "bidirectional"))
      (node (ref "C46") (pin "1") (pinfunction "1_1") (pintype "bidirectional"))
      (node (ref "C464") (pin "2") (pinfunction "2_2") (pintype "bidirectional"))
      (node (ref "C465") (pin "2") (pinfunction "2_2") (pintype "bidirectional"))
      (node (ref "C47") (pin "1") (pinfunction "1_1") (pintype "bidirectional"))
      (node (ref "C48") (pin "1") (pinfunction "1_1") (pintype "bidirectional"))
      (node (ref "C49") (pin "1") (pinfunction "1_1") (pintype "bidirectional"))
      (node (ref "C5") (pin "1") (pinfunction "1_1") (pintype "bidirectional"))
      (node (ref "C50") (pin "1") (pinfunction "1_1") (pintype "bidirectional"))
      (node (ref "C51") (pin "1") (pinfunction "1_1") (pintype "bidirectional"))
      (node (ref "C52") (pin "1") (pinfunction "1_1") (pintype "bidirectional"))
      (node (ref "C53") (pin "1") (pinfunction "1_1") (pintype "bidirectional"))
      (node (ref "C54") (pin "1") (pinfunction "1_1") (pintype "bidirectional"))
      (node (ref "C55") (pin "1") (pinfunction "1_1") (pintype "bidirectional"))
      (node (ref "C56") (pin "1") (pinfunction "1_1") (pintype "bidirectional"))
      (node (ref "C57") (pin "1") (pinfunction "1_1") (pintype "bidirectional"))
      (node (ref "C574") (pin "1") (pinfunction "1_1") (pintype "bidirectional"))
      (node (ref "C575") (pin "2") (pinfunction "2_2") (pintype "bidirectional"))
      (node (ref "C577") (pin "2") (pinfunction "2_2") (pintype "bidirectional"))
      (node (ref "C578") (pin "1") (pinfunction "1_1") (pintype "bidirectional"))
      (node (ref "C579") (pin "2") (pinfunction "2_2") (pintype "bidirectional"))
      (node (ref "C58") (pin "1") (pinfunction "1_1") (pintype "bidirectional"))
      (node (ref "C59") (pin "1") (pinfunction "1_1") (pintype "bidirectional"))
      (node (ref "C6") (pin "1") (pinfunction "1_1") (pintype "bidirectional"))
      (node (ref "C60") (pin "1") (pinfunction "1_1") (pintype "bidirectional"))
      (node (ref "C62") (pin "1") (pinfunction "1_1") (pintype "bidirectional"))
      (node (ref "C63") (pin "1") (pinfunction "1_1") (pintype "bidirectional"))
      (node (ref "C64") (pin "1") (pinfunction "1_1") (pintype "bidirectional"))
      (node (ref "C65") (pin "1") (pinfunction "1_1") (pintype "bidirectional"))
      (node (ref "C66") (pin "1") (pinfunction "1_1") (pintype "bidirectional"))
      (node (ref "C67") (pin "1") (pinfunction "1_1") (pintype "bidirectional"))
      (node (ref "C68") (pin "1") (pinfunction "1_1") (pintype "bidirectional"))
      (node (ref "C69") (pin "1") (pinfunction "1_1") (pintype "bidirectional"))
      (node (ref "C7") (pin "1") (pinfunction "1_1") (pintype "bidirectional"))
      (node (ref "C70") (pin "1") (pinfunction "1_1") (pintype "bidirectional"))
      (node (ref "C71") (pin "1") (pinfunction "1_1") (pintype "bidirectional"))
      (node (ref "C72") (pin "1") (pinfunction "1_1") (pintype "bidirectional"))
      (node (ref "C73") (pin "1") (pinfunction "1_1") (pintype "bidirectional"))
      (node (ref "C74") (pin "1") (pinfunction "1_1") (pintype "bidirectional"))
      (node (ref "C75") (pin "1") (pinfunction "1_1") (pintype "bidirectional"))
      (node (ref "C76") (pin "1") (pinfunction "1_1") (pintype "bidirectional"))
      (node (ref "C77") (pin "1") (pinfunction "1_1") (pintype "bidirectional"))
      (node (ref "C78") (pin "1") (pinfunction "1_1") (pintype "bidirectional"))
      (node (ref "C79") (pin "1") (pinfunction "1_1") (pintype "bidirectional"))
      (node (ref "C8") (pin "2") (pinfunction "2_2") (pintype "bidirectional"))
      (node (ref "C80") (pin "1") (pinfunction "1_1") (pintype "bidirectional"))
      (node (ref "C81") (pin "1") (pinfunction "1_1") (pintype "bidirectional"))
      (node (ref "C82") (pin "1") (pinfunction "1_1") (pintype "bidirectional"))
      (node (ref "C83") (pin "1") (pinfunction "1_1") (pintype "bidirectional"))
      (node (ref "C84") (pin "1") (pinfunction "1_1") (pintype "bidirectional"))
      (node (ref "C85") (pin "1") (pinfunction "1_1") (pintype "bidirectional"))
      (node (ref "C86") (pin "2") (pinfunction "2_2") (pintype "bidirectional"))
      (node (ref "C87") (pin "2") (pinfunction "2_2") (pintype "bidirectional"))
      (node (ref "C88") (pin "2") (pinfunction "2_2") (pintype "bidirectional"))
      (node (ref "C89") (pin "2") (pinfunction "2_2") (pintype "bidirectional"))
      (node (ref "C9") (pin "1") (pinfunction "1_1") (pintype "bidirectional"))
      (node (ref "C90") (pin "2") (pinfunction "2_2") (pintype "bidirectional"))
      (node (ref "C91") (pin "2") (pinfunction "2_2") (pintype "bidirectional"))
      (node (ref "C92") (pin "1") (pinfunction "1_1") (pintype "bidirectional"))
      (node (ref "C93") (pin "1") (pinfunction "1_1") (pintype "bidirectional"))
      (node (ref "C94") (pin "1") (pinfunction "1_1") (pintype "bidirectional"))
      (node (ref "C95") (pin "1") (pinfunction "1_1") (pintype "bidirectional"))
      (node (ref "C96") (pin "1") (pinfunction "1_1") (pintype "bidirectional"))
      (node (ref "C97") (pin "1") (pinfunction "1_1") (pintype "bidirectional"))
      (node (ref "C98") (pin "1") (pinfunction "1_1") (pintype "bidirectional"))
      (node (ref "C99") (pin "1") (pinfunction "1_1") (pintype "bidirectional"))
      (node (ref "D1") (pin "P$2") (pinfunction "2_P$2") (pintype "bidirectional"))
      (node (ref "D2") (pin "P$2") (pinfunction "2_P$2") (pintype "bidirectional"))
      (node (ref "D5") (pin "P$2") (pinfunction "2_P$2") (pintype "bidirectional"))
      (node (ref "D6") (pin "P$2") (pinfunction "2_P$2") (pintype "bidirectional"))
      (node (ref "HDMI") (pin "P$17") (pinfunction "CECGND_P$17") (pintype "bidirectional"))
      (node (ref "J1") (pin "A11") (pinfunction "11_A11") (pintype "bidirectional"))
      (node (ref "J1") (pin "A12") (pinfunction "12_A12") (pintype "bidirectional"))
      (node (ref "J1") (pin "A13") (pinfunction "13_A13") (pintype "bidirectional"))
      (node (ref "J1") (pin "A14") (pinfunction "14_A14") (pintype "bidirectional"))
      (node (ref "J1") (pin "A15") (pinfunction "15_A15") (pintype "bidirectional"))
      (node (ref "J1") (pin "A16") (pinfunction "16_A16") (pintype "bidirectional"))
      (node (ref "J1") (pin "A17") (pinfunction "17_A17") (pintype "bidirectional"))
      (node (ref "J1") (pin "A18") (pinfunction "18_A18") (pintype "bidirectional"))
      (node (ref "J1") (pin "A19") (pinfunction "19_A19") (pintype "bidirectional"))
      (node (ref "J1") (pin "A20") (pinfunction "20_A20") (pintype "bidirectional"))
      (node (ref "J1") (pin "A29") (pinfunction "29_A29") (pintype "bidirectional"))
      (node (ref "J1") (pin "A38") (pinfunction "38_A38") (pintype "bidirectional"))
      (node (ref "J1") (pin "B1") (pinfunction "1_B1") (pintype "bidirectional"))
      (node (ref "J1") (pin "B10") (pinfunction "10_B10") (pintype "bidirectional"))
      (node (ref "J1") (pin "B15") (pinfunction "15_B15") (pintype "bidirectional"))
      (node (ref "J1") (pin "B18") (pinfunction "18_B18") (pintype "bidirectional"))
      (node (ref "J1") (pin "B2") (pinfunction "2_B2") (pintype "bidirectional"))
      (node (ref "J1") (pin "B20") (pinfunction "20_B20") (pintype "bidirectional"))
      (node (ref "J1") (pin "B22") (pinfunction "22_B22") (pintype "bidirectional"))
      (node (ref "J1") (pin "B24") (pinfunction "24_B24") (pintype "bidirectional"))
      (node (ref "J1") (pin "B27") (pinfunction "27_B27") (pintype "bidirectional"))
      (node (ref "J1") (pin "B28") (pinfunction "28_B28") (pintype "bidirectional"))
      (node (ref "J1") (pin "B29") (pinfunction "29_B29") (pintype "bidirectional"))
      (node (ref "J1") (pin "B3") (pinfunction "3_B3") (pintype "bidirectional"))
      (node (ref "J1") (pin "B30") (pinfunction "30_B30") (pintype "bidirectional"))
      (node (ref "J1") (pin "B31") (pinfunction "31_B31") (pintype "bidirectional"))
      (node (ref "J1") (pin "B32") (pinfunction "32_B32") (pintype "bidirectional"))
      (node (ref "J1") (pin "B33") (pinfunction "33_B33") (pintype "bidirectional"))
      (node (ref "J1") (pin "B34") (pinfunction "34_B34") (pintype "bidirectional"))
      (node (ref "J1") (pin "B35") (pinfunction "35_B35") (pintype "bidirectional"))
      (node (ref "J1") (pin "B36") (pinfunction "36_B36") (pintype "bidirectional"))
      (node (ref "J1") (pin "B37") (pinfunction "37_B37") (pintype "bidirectional"))
      (node (ref "J1") (pin "B38") (pinfunction "38_B38") (pintype "bidirectional"))
      (node (ref "J1") (pin "B39") (pinfunction "39_B39") (pintype "bidirectional"))
      (node (ref "J1") (pin "B4") (pinfunction "4_B4") (pintype "bidirectional"))
      (node (ref "J1") (pin "B40") (pinfunction "40_B40") (pintype "bidirectional"))
      (node (ref "J1") (pin "B5") (pinfunction "5_B5") (pintype "bidirectional"))
      (node (ref "J1") (pin "B6") (pinfunction "6_B6") (pintype "bidirectional"))
      (node (ref "J1") (pin "B7") (pinfunction "7_B7") (pintype "bidirectional"))
      (node (ref "J1") (pin "B8") (pinfunction "8_B8") (pintype "bidirectional"))
      (node (ref "J1") (pin "B9") (pinfunction "9_B9") (pintype "bidirectional"))
      (node (ref "J1") (pin "C22") (pinfunction "22_C22") (pintype "bidirectional"))
      (node (ref "J1") (pin "C27") (pinfunction "27_C27") (pintype "bidirectional"))
      (node (ref "J1") (pin "C32") (pinfunction "32_C32") (pintype "bidirectional"))
      (node (ref "J1") (pin "C5") (pinfunction "5_C5") (pintype "bidirectional"))
      (node (ref "J1") (pin "C8") (pinfunction "8_C8") (pintype "bidirectional"))
      (node (ref "JP1") (pin "10") (pinfunction "10_10") (pintype "passive"))
      (node (ref "JP1") (pin "12") (pinfunction "12_12") (pintype "passive"))
      (node (ref "JP1") (pin "16") (pinfunction "16_16") (pintype "passive"))
      (node (ref "JP1") (pin "20") (pinfunction "20_20") (pintype "passive"))
      (node (ref "JP1") (pin "4") (pinfunction "4_4") (pintype "passive"))
      (node (ref "JP1") (pin "8") (pinfunction "8_8") (pintype "passive"))
      (node (ref "JP2") (pin "9") (pinfunction "9_9") (pintype "passive"))
      (node (ref "JP3") (pin "10") (pinfunction "10_10") (pintype "passive"))
      (node (ref "JP3") (pin "9") (pinfunction "9_9") (pintype "passive"))
      (node (ref "Q10") (pin "1") (pinfunction "S_1") (pintype "passive"))
      (node (ref "Q10") (pin "2") (pinfunction "S_2") (pintype "passive"))
      (node (ref "Q10") (pin "3") (pinfunction "S_3") (pintype "passive"))
      (node (ref "Q9") (pin "1") (pinfunction "S_1") (pintype "passive"))
      (node (ref "Q9") (pin "2") (pinfunction "S_2") (pintype "passive"))
      (node (ref "Q9") (pin "3") (pinfunction "S_3") (pintype "passive"))
      (node (ref "R16") (pin "1") (pinfunction "1_1") (pintype "bidirectional"))
      (node (ref "R18") (pin "1") (pinfunction "1_1") (pintype "bidirectional"))
      (node (ref "R20") (pin "1") (pinfunction "1_1") (pintype "bidirectional"))
      (node (ref "R21") (pin "1") (pinfunction "1_1") (pintype "bidirectional"))
      (node (ref "R234") (pin "1") (pinfunction "1_1") (pintype "bidirectional"))
      (node (ref "R51") (pin "2") (pinfunction "2_2") (pintype "bidirectional"))
      (node (ref "R537") (pin "1") (pinfunction "1_1") (pintype "bidirectional"))
      (node (ref "R541") (pin "1") (pinfunction "1_1") (pintype "bidirectional"))
      (node (ref "R61") (pin "2") (pinfunction "2_2") (pintype "bidirectional"))
      (node (ref "R62") (pin "2") (pinfunction "2_2") (pintype "bidirectional"))
      (node (ref "R69") (pin "1") (pinfunction "1_1") (pintype "bidirectional"))
      (node (ref "R71") (pin "1") (pinfunction "1_1") (pintype "bidirectional"))
      (node (ref "R73") (pin "1") (pinfunction "1_1") (pintype "bidirectional"))
      (node (ref "R75") (pin "1") (pinfunction "1_1") (pintype "bidirectional"))
      (node (ref "R82") (pin "1") (pinfunction "1_1") (pintype "bidirectional"))
      (node (ref "R85") (pin "1") (pinfunction "1_1") (pintype "bidirectional"))
      (node (ref "R89") (pin "1") (pinfunction "1_1") (pintype "bidirectional"))
      (node (ref "R98") (pin "1") (pinfunction "1_1") (pintype "bidirectional"))
      (node (ref "T1") (pin "6") (pinfunction "GND_6") (pintype "bidirectional"))
      (node (ref "U$10") (pin "A6") (pinfunction "VSS_A6") (pintype "bidirectional"))
      (node (ref "U$10") (pin "C4") (pinfunction "VSSQ_C4") (pintype "bidirectional"))
      (node (ref "U$10") (pin "E7") (pinfunction "VSS_E7") (pintype "bidirectional"))
      (node (ref "U$10") (pin "G5") (pinfunction "VSS_G5") (pintype "bidirectional"))
      (node (ref "U$10") (pin "H10") (pinfunction "VSS_H10") (pintype "bidirectional"))
      (node (ref "U$10") (pin "J5") (pinfunction "VSS_J5") (pintype "bidirectional"))
      (node (ref "U$10") (pin "K8") (pinfunction "VSS_K8") (pintype "bidirectional"))
      (node (ref "U$10") (pin "N2") (pinfunction "VSSQ_N2") (pintype "bidirectional"))
      (node (ref "U$10") (pin "N5") (pinfunction "VSSQ_N5") (pintype "bidirectional"))
      (node (ref "U$10") (pin "P4") (pinfunction "VSSQ_P4") (pintype "bidirectional"))
      (node (ref "U$10") (pin "P6") (pinfunction "VSSQ_P6") (pintype "bidirectional"))
      (node (ref "U$11") (pin "A6") (pinfunction "VSS_A6") (pintype "bidirectional"))
      (node (ref "U$11") (pin "C4") (pinfunction "VSSQ_C4") (pintype "bidirectional"))
      (node (ref "U$11") (pin "E7") (pinfunction "VSS_E7") (pintype "bidirectional"))
      (node (ref "U$11") (pin "G5") (pinfunction "VSS_G5") (pintype "bidirectional"))
      (node (ref "U$11") (pin "H10") (pinfunction "VSS_H10") (pintype "bidirectional"))
      (node (ref "U$11") (pin "J5") (pinfunction "VSS_J5") (pintype "bidirectional"))
      (node (ref "U$11") (pin "K8") (pinfunction "VSS_K8") (pintype "bidirectional"))
      (node (ref "U$11") (pin "N2") (pinfunction "VSSQ_N2") (pintype "bidirectional"))
      (node (ref "U$11") (pin "N5") (pinfunction "VSSQ_N5") (pintype "bidirectional"))
      (node (ref "U$11") (pin "P4") (pinfunction "VSSQ_P4") (pintype "bidirectional"))
      (node (ref "U$11") (pin "P6") (pinfunction "VSSQ_P6") (pintype "bidirectional"))
      (node (ref "U$12") (pin "14") (pinfunction "GND_14") (pintype "bidirectional"))
      (node (ref "U$12") (pin "PAD") (pinfunction "GND_PAD") (pintype "bidirectional"))
      (node (ref "U$5") (pin "2") (pinfunction "VSS_2") (pintype "bidirectional"))
      (node (ref "U$6") (pin "2") (pinfunction "VSS_2") (pintype "bidirectional"))
      (node (ref "U$6") (pin "4") (pinfunction "VSS_4") (pintype "bidirectional"))
      (node (ref "U$7") (pin "2") (pinfunction "VSS_2") (pintype "bidirectional"))
      (node (ref "U$7") (pin "4") (pinfunction "VSS_4") (pintype "bidirectional"))
      (node (ref "U$9") (pin "P$2") (pinfunction "GND_P$2") (pintype "power_in"))
      (node (ref "U$9") (pin "P$3") (pinfunction "ADR1_P$3") (pintype "bidirectional"))
      (node (ref "U$9") (pin "P$5") (pinfunction "ADR0_P$5") (pintype "bidirectional"))
      (node (ref "U1") (pin "A1") (pinfunction "VSS_24_A1") (pintype "power_in"))
      (node (ref "U1") (pin "A18") (pinfunction "VSS_8_A18") (pintype "power_in"))
      (node (ref "U1") (pin "A5") (pinfunction "VSS_RTC_A5") (pintype "power_in"))
      (node (ref "U1") (pin "A9") (pinfunction "VREFN_A9") (pintype "power_in"))
      (node (ref "U1") (pin "B4") (pinfunction "RTC_KALDO_ENN_B4") (pintype "passive"))
      (node (ref "U1") (pin "E8") (pinfunction "VSSA_ADC_E8") (pintype "power_in"))
      (node (ref "U1") (pin "F8") (pinfunction "VSS_3_F8") (pintype "power_in"))
      (node (ref "U1") (pin "G11") (pinfunction "VSS_32_G11") (pintype "power_in"))
      (node (ref "U1") (pin "G12") (pinfunction "VSS_34_G12") (pintype "power_in"))
      (node (ref "U1") (pin "G8") (pinfunction "VSS_5_G8") (pintype "power_in"))
      (node (ref "U1") (pin "G9") (pinfunction "VSS_7_G9") (pintype "power_in"))
      (node (ref "U1") (pin "H10") (pinfunction "VSS_35_H10") (pintype "power_in"))
      (node (ref "U1") (pin "H12") (pinfunction "VSS_36_H12") (pintype "power_in"))
      (node (ref "U1") (pin "H6") (pinfunction "VSS_9_H6") (pintype "power_in"))
      (node (ref "U1") (pin "H7") (pinfunction "VSS_11_H7") (pintype "power_in"))
      (node (ref "U1") (pin "H8") (pinfunction "VSS_13_H8") (pintype "power_in"))
      (node (ref "U1") (pin "H9") (pinfunction "VSS_15_H9") (pintype "power_in"))
      (node (ref "U1") (pin "J10") (pinfunction "VSS_37_J10") (pintype "power_in"))
      (node (ref "U1") (pin "J11") (pinfunction "VSS_38_J11") (pintype "power_in"))
      (node (ref "U1") (pin "J6") (pinfunction "VSS_17_J6") (pintype "power_in"))
      (node (ref "U1") (pin "J7") (pinfunction "VSS_23_J7") (pintype "power_in"))
      (node (ref "U1") (pin "J8") (pinfunction "VSS_26_J8") (pintype "power_in"))
      (node (ref "U1") (pin "J9") (pinfunction "VSS_28_J9") (pintype "power_in"))
      (node (ref "U1") (pin "K10") (pinfunction "VSS_10_K10") (pintype "power_in"))
      (node (ref "U1") (pin "K11") (pinfunction "VSS_12_K11") (pintype "power_in"))
      (node (ref "U1") (pin "K7") (pinfunction "VSS_19_K7") (pintype "power_in"))
      (node (ref "U1") (pin "K9") (pinfunction "VSS_20_K9") (pintype "power_in"))
      (node (ref "U1") (pin "L10") (pinfunction "VSS_14_L10") (pintype "power_in"))
      (node (ref "U1") (pin "L11") (pinfunction "VSS_16_L11") (pintype "power_in"))
      (node (ref "U1") (pin "L12") (pinfunction "VSS_22_L12") (pintype "power_in"))
      (node (ref "U1") (pin "L13") (pinfunction "VSS_25_L13") (pintype "power_in"))
      (node (ref "U1") (pin "M10") (pinfunction "VSS_27_M10") (pintype "power_in"))
      (node (ref "U1") (pin "M12") (pinfunction "VSS_29_M12") (pintype "power_in"))
      (node (ref "U1") (pin "M14") (pinfunction "VSSA_USB_2_M14") (pintype "power_in"))
      (node (ref "U1") (pin "M6") (pinfunction "VSS_21_M6") (pintype "power_in"))
      (node (ref "U1") (pin "M7") (pinfunction "VSS_18_M7") (pintype "power_in"))
      (node (ref "U1") (pin "M8") (pinfunction "VSS_2_M8") (pintype "power_in"))
      (node (ref "U1") (pin "M9") (pinfunction "VSS_4_M9") (pintype "power_in"))
      (node (ref "U1") (pin "N10") (pinfunction "VSS_31_N10") (pintype "power_in"))
      (node (ref "U1") (pin "N11") (pinfunction "VSS_33_N11") (pintype "power_in"))
      (node (ref "U1") (pin "N14") (pinfunction "VSSA_USB_N14") (pintype "power_in"))
      (node (ref "U1") (pin "N7") (pinfunction "VSS_6_N7") (pintype "power_in"))
      (node (ref "U1") (pin "P16") (pinfunction "USB0_ID_P16") (pintype "passive"))
      (node (ref "U1") (pin "P17") (pinfunction "USB1_ID_P17") (pintype "passive"))
      (node (ref "U1") (pin "V1") (pinfunction "VSS_30_V1") (pintype "power_in"))
      (node (ref "U1") (pin "V11") (pinfunction "VSS_OSC_V11") (pintype "power_in"))
      (node (ref "U1") (pin "V18") (pinfunction "VSS_V18") (pintype "power_in"))
      (node (ref "U10") (pin "4") (pinfunction "GND_4") (pintype "power_in"))
      (node (ref "U11") (pin "5") (pinfunction "GND_5") (pintype "power_in"))
      (node (ref "U11") (pin "7") (pinfunction "PAD_7") (pintype "power_in"))
      (node (ref "U12") (pin "18") (pinfunction "A0_18") (pintype "input"))
      (node (ref "U12") (pin "23") (pinfunction "A1_23") (pintype "input"))
      (node (ref "U12") (pin "24") (pinfunction "A2_24") (pintype "input"))
      (node (ref "U12") (pin "25") (pinfunction "EPAD_25") (pintype "passive"))
      (node (ref "U12") (pin "9") (pinfunction "GND_9") (pintype "power_in"))
      (node (ref "U13") (pin "3") (pinfunction "GND_3") (pintype "power_in"))
      (node (ref "U14") (pin "33") (pinfunction "PAD_33") (pintype "power_in"))
      (node (ref "U15") (pin "1") (pinfunction "GND_1") (pintype "power_in"))
      (node (ref "U16") (pin "1") (pinfunction "GND_1") (pintype "power_in"))
      (node (ref "U17") (pin "16") (pinfunction "DGND_2_16") (pintype "power_in"))
      (node (ref "U17") (pin "17") (pinfunction "PGND_17") (pintype "power_in"))
      (node (ref "U17") (pin "20") (pinfunction "TGND_2_20") (pintype "power_in"))
      (node (ref "U17") (pin "26") (pinfunction "TGND_3_26") (pintype "power_in"))
      (node (ref "U17") (pin "32") (pinfunction "TGND_32") (pintype "power_in"))
      (node (ref "U17") (pin "34") (pinfunction "RESERVED_34") (pintype "passive"))
      (node (ref "U17") (pin "48") (pinfunction "DGND_3_48") (pintype "power_in"))
      (node (ref "U17") (pin "56") (pinfunction "IDCK-_56") (pintype "input"))
      (node (ref "U17") (pin "6") (pinfunction "CTL3/A3/DK3_6") (pintype "input"))
      (node (ref "U17") (pin "64") (pinfunction "DGND_64") (pintype "power_in"))
      (node (ref "U17") (pin "7") (pinfunction "CTL2/A2/DK2_7") (pintype "input"))
      (node (ref "U17") (pin "8") (pinfunction "CTL1/A1/DK1_8") (pintype "input"))
      (node (ref "U17") (pin "EPAD") (pinfunction "EPAD_EPAD") (pintype "passive"))
      (node (ref "U18") (pin "3") (pinfunction "GND_3") (pintype "power_in"))
      (node (ref "U19") (pin "2") (pinfunction "GND_2") (pintype "power_in"))
      (node (ref "U2") (pin "4") (pinfunction "GND_4") (pintype "power_in"))
      (node (ref "U3") (pin "1") (pinfunction "A1_1") (pintype "passive"))
      (node (ref "U3") (pin "2") (pinfunction "A0_2") (pintype "passive"))
      (node (ref "U3") (pin "7") (pinfunction "GND_7") (pintype "power_in"))
      (node (ref "U34") (pin "14") (pinfunction "PGND2_14") (pintype "power_in"))
      (node (ref "U34") (pin "17") (pinfunction "PGND1_17") (pintype "power_in"))
      (node (ref "U34") (pin "35") (pinfunction "AGND_35") (pintype "power_in"))
      (node (ref "U34") (pin "38") (pinfunction "SYN_IN_38") (pintype "passive"))
      (node (ref "U34") (pin "41") (pinfunction "DAP_41") (pintype "power_in"))
      (node (ref "U35") (pin "5") (pinfunction "GND_5") (pintype "power_in"))
      (node (ref "U38") (pin "A2") (pinfunction "AGND_A2") (pintype "power_in"))
      (node (ref "U38") (pin "C1") (pinfunction "SENSE-_C1") (pintype "input"))
      (node (ref "U38") (pin "C3") (pinfunction "PGND_2_C3") (pintype "power_in"))
      (node (ref "U38") (pin "C4") (pinfunction "PGND_3_C4") (pintype "power_in"))
      (node (ref "U38") (pin "D4") (pinfunction "PGND_D4") (pintype "power_in"))
      (node (ref "U4") (pin "A2") (pinfunction "AGND_A2") (pintype "power_in"))
      (node (ref "U4") (pin "C1") (pinfunction "SENSE-_C1") (pintype "input"))
      (node (ref "U4") (pin "C3") (pinfunction "PGND_2_C3") (pintype "power_in"))
      (node (ref "U4") (pin "C4") (pinfunction "PGND_3_C4") (pintype "power_in"))
      (node (ref "U4") (pin "D4") (pinfunction "PGND_D4") (pintype "power_in"))
      (node (ref "U40") (pin "5") (pinfunction "GND_5") (pintype "power_in"))
      (node (ref "U40") (pin "7") (pinfunction "PAD_7") (pintype "power_in"))
      (node (ref "U41") (pin "11") (pinfunction "PAD_11") (pintype "power_in"))
      (node (ref "U41") (pin "3") (pinfunction "GND_2_3") (pintype "power_in"))
      (node (ref "U41") (pin "4") (pinfunction "GND_3_4") (pintype "power_in"))
      (node (ref "U41") (pin "5") (pinfunction "GND_5") (pintype "power_in"))
      (node (ref "U5") (pin "2") (pinfunction "A0_2") (pintype "passive"))
      (node (ref "U5") (pin "7") (pinfunction "GND_7") (pintype "power_in"))
      (node (ref "U6") (pin "16") (pinfunction "PGND_16") (pintype "power_in"))
      (node (ref "U6") (pin "21") (pinfunction "EPAD_21") (pintype "passive"))
      (node (ref "U6") (pin "3") (pinfunction "VTTGND_3") (pintype "power_in"))
      (node (ref "U6") (pin "5") (pinfunction "GND_5") (pintype "power_in"))
      (node (ref "U7") (pin "1") (pinfunction "A1_1") (pintype "passive"))
      (node (ref "U7") (pin "7") (pinfunction "GND_7") (pintype "power_in"))
      (node (ref "U76") (pin "2") (pinfunction "GND_2_2") (pintype "power_in"))
      (node (ref "U76") (pin "4") (pinfunction "GND_3_4") (pintype "power_in"))
      (node (ref "U76") (pin "6") (pinfunction "GND_6") (pintype "power_in"))
      (node (ref "U77") (pin "2") (pinfunction "GND_2") (pintype "power_in"))
      (node (ref "U78") (pin "2") (pinfunction "GND_2") (pintype "power_in"))
      (node (ref "U8") (pin "1") (pinfunction "A1_1") (pintype "passive"))
      (node (ref "U8") (pin "7") (pinfunction "GND_7") (pintype "power_in"))
      (node (ref "U9") (pin "A9") (pinfunction "VSS_A9") (pintype "bidirectional"))
      (node (ref "U9") (pin "B1") (pinfunction "VSSQ_B1") (pintype "bidirectional"))
      (node (ref "U9") (pin "B3") (pinfunction "VSS_B3") (pintype "bidirectional"))
      (node (ref "U9") (pin "B9") (pinfunction "VSSQ_B9") (pintype "bidirectional"))
      (node (ref "U9") (pin "D1") (pinfunction "VSSQ_D1") (pintype "bidirectional"))
      (node (ref "U9") (pin "D8") (pinfunction "VSSQ_D8") (pintype "bidirectional"))
      (node (ref "U9") (pin "E1") (pinfunction "VSS_E1") (pintype "bidirectional"))
      (node (ref "U9") (pin "E2") (pinfunction "VSSQ_E2") (pintype "bidirectional"))
      (node (ref "U9") (pin "E8") (pinfunction "VSSQ_E8") (pintype "bidirectional"))
      (node (ref "U9") (pin "F9") (pinfunction "VSSQ_F9") (pintype "bidirectional"))
      (node (ref "U9") (pin "G1") (pinfunction "VSSQ_G1") (pintype "bidirectional"))
      (node (ref "U9") (pin "G8") (pinfunction "VSS_G8") (pintype "bidirectional"))
      (node (ref "U9") (pin "G9") (pinfunction "VSSQ_G9") (pintype "bidirectional"))
      (node (ref "U9") (pin "H1") (pinfunction "VREFDQ_H1") (pintype "bidirectional"))
      (node (ref "U9") (pin "J2") (pinfunction "VSS_J2") (pintype "bidirectional"))
      (node (ref "U9") (pin "J8") (pinfunction "VSS_J8") (pintype "bidirectional"))
      (node (ref "U9") (pin "M1") (pinfunction "VSS_M1") (pintype "bidirectional"))
      (node (ref "U9") (pin "M9") (pinfunction "VSS_M9") (pintype "bidirectional"))
      (node (ref "U9") (pin "P1") (pinfunction "VSS_P1") (pintype "bidirectional"))
      (node (ref "U9") (pin "P9") (pinfunction "VSS_P9") (pintype "bidirectional"))
      (node (ref "U9") (pin "T1") (pinfunction "VSS_T1") (pintype "bidirectional"))
      (node (ref "U9") (pin "T9") (pinfunction "VSS_T9") (pintype "bidirectional"))
      (node (ref "X1") (pin "10") (pinfunction "C-R_10") (pintype "passive"))
      (node (ref "X1") (pin "11") (pinfunction "C-L_11") (pintype "passive"))
      (node (ref "X2") (pin "GND") (pinfunction "GND_GND") (pintype "bidirectional"))
      (node (ref "X3") (pin "GND") (pinfunction "GND_GND") (pintype "bidirectional"))
    )
    (net (code "334") (name "unconnected-(HDMI-CEC-PadP$13)") (class "Default")
      (node (ref "HDMI") (pin "P$13") (pinfunction "CEC_P$13") (pintype "bidirectional"))
    )
    (net (code "335") (name "unconnected-(HDMI-SCL-PadP$15)") (class "Default")
      (node (ref "HDMI") (pin "P$15") (pinfunction "SCL_P$15") (pintype "bidirectional"))
    )
    (net (code "336") (name "unconnected-(HDMI-SDA-PadP$16)") (class "Default")
      (node (ref "HDMI") (pin "P$16") (pinfunction "SDA_P$16") (pintype "bidirectional"))
    )
    (net (code "337") (name "unconnected-(HDMI-UTIL-PadP$14)") (class "Default")
      (node (ref "HDMI") (pin "P$14") (pinfunction "UTIL_P$14") (pintype "bidirectional"))
    )
    (net (code "338") (name "unconnected-(J1A-21-PadA21)") (class "Default")
      (node (ref "J1") (pin "A21") (pinfunction "21_A21") (pintype "bidirectional"))
    )
    (net (code "339") (name "unconnected-(J1A-22-PadA22)") (class "Default")
      (node (ref "J1") (pin "A22") (pinfunction "22_A22") (pintype "bidirectional"))
    )
    (net (code "340") (name "unconnected-(J1A-23-PadA23)") (class "Default")
      (node (ref "J1") (pin "A23") (pinfunction "23_A23") (pintype "bidirectional"))
    )
    (net (code "341") (name "unconnected-(J1A-24-PadA24)") (class "Default")
      (node (ref "J1") (pin "A24") (pinfunction "24_A24") (pintype "bidirectional"))
    )
    (net (code "342") (name "unconnected-(J1A-25-PadA25)") (class "Default")
      (node (ref "J1") (pin "A25") (pinfunction "25_A25") (pintype "bidirectional"))
    )
    (net (code "343") (name "unconnected-(J1A-26-PadA26)") (class "Default")
      (node (ref "J1") (pin "A26") (pinfunction "26_A26") (pintype "bidirectional"))
    )
    (net (code "344") (name "unconnected-(J1A-27-PadA27)") (class "Default")
      (node (ref "J1") (pin "A27") (pinfunction "27_A27") (pintype "bidirectional"))
    )
    (net (code "345") (name "unconnected-(J1A-28-PadA28)") (class "Default")
      (node (ref "J1") (pin "A28") (pinfunction "28_A28") (pintype "bidirectional"))
    )
    (net (code "346") (name "unconnected-(J1C-33-PadC33)") (class "Default")
      (node (ref "J1") (pin "C33") (pinfunction "33_C33") (pintype "bidirectional"))
    )
    (net (code "347") (name "unconnected-(J1C-34-PadC34)") (class "Default")
      (node (ref "J1") (pin "C34") (pinfunction "34_C34") (pintype "bidirectional"))
    )
    (net (code "348") (name "unconnected-(J1C-35-PadC35)") (class "Default")
      (node (ref "J1") (pin "C35") (pinfunction "35_C35") (pintype "bidirectional"))
    )
    (net (code "349") (name "unconnected-(J1C-36-PadC36)") (class "Default")
      (node (ref "J1") (pin "C36") (pinfunction "36_C36") (pintype "bidirectional"))
    )
    (net (code "350") (name "unconnected-(J1C-37-PadC37)") (class "Default")
      (node (ref "J1") (pin "C37") (pinfunction "37_C37") (pintype "bidirectional"))
    )
    (net (code "351") (name "unconnected-(J1C-38-PadC38)") (class "Default")
      (node (ref "J1") (pin "C38") (pinfunction "38_C38") (pintype "bidirectional"))
    )
    (net (code "352") (name "unconnected-(J1C-39-PadC39)") (class "Default")
      (node (ref "J1") (pin "C39") (pinfunction "39_C39") (pintype "bidirectional"))
    )
    (net (code "353") (name "unconnected-(J1C-40-PadC40)") (class "Default")
      (node (ref "J1") (pin "C40") (pinfunction "40_C40") (pintype "bidirectional"))
    )
    (net (code "354") (name "unconnected-(J1D-1-PadD1)") (class "Default")
      (node (ref "J1") (pin "D1") (pinfunction "1_D1") (pintype "bidirectional"))
    )
    (net (code "355") (name "unconnected-(J1D-2-PadD2)") (class "Default")
      (node (ref "J1") (pin "D2") (pinfunction "2_D2") (pintype "bidirectional"))
    )
    (net (code "356") (name "unconnected-(J1D-3-PadD3)") (class "Default")
      (node (ref "J1") (pin "D3") (pinfunction "3_D3") (pintype "bidirectional"))
    )
    (net (code "357") (name "unconnected-(J1D-4-PadD4)") (class "Default")
      (node (ref "J1") (pin "D4") (pinfunction "4_D4") (pintype "bidirectional"))
    )
    (net (code "358") (name "unconnected-(J1D-5-PadD5)") (class "Default")
      (node (ref "J1") (pin "D5") (pinfunction "5_D5") (pintype "bidirectional"))
    )
    (net (code "359") (name "unconnected-(J1D-6-PadD6)") (class "Default")
      (node (ref "J1") (pin "D6") (pinfunction "6_D6") (pintype "bidirectional"))
    )
    (net (code "360") (name "unconnected-(J1D-7-PadD7)") (class "Default")
      (node (ref "J1") (pin "D7") (pinfunction "7_D7") (pintype "bidirectional"))
    )
    (net (code "361") (name "unconnected-(J1D-8-PadD8)") (class "Default")
      (node (ref "J1") (pin "D8") (pinfunction "8_D8") (pintype "bidirectional"))
    )
    (net (code "362") (name "unconnected-(J1D-9-PadD9)") (class "Default")
      (node (ref "J1") (pin "D9") (pinfunction "9_D9") (pintype "bidirectional"))
    )
    (net (code "363") (name "unconnected-(J1D-10-PadD10)") (class "Default")
      (node (ref "J1") (pin "D10") (pinfunction "10_D10") (pintype "bidirectional"))
    )
    (net (code "364") (name "unconnected-(J1D-11-PadD11)") (class "Default")
      (node (ref "J1") (pin "D11") (pinfunction "11_D11") (pintype "bidirectional"))
    )
    (net (code "365") (name "unconnected-(J1D-12-PadD12)") (class "Default")
      (node (ref "J1") (pin "D12") (pinfunction "12_D12") (pintype "bidirectional"))
    )
    (net (code "366") (name "unconnected-(J1D-13-PadD13)") (class "Default")
      (node (ref "J1") (pin "D13") (pinfunction "13_D13") (pintype "bidirectional"))
    )
    (net (code "367") (name "unconnected-(J1D-14-PadD14)") (class "Default")
      (node (ref "J1") (pin "D14") (pinfunction "14_D14") (pintype "bidirectional"))
    )
    (net (code "368") (name "unconnected-(J1D-15-PadD15)") (class "Default")
      (node (ref "J1") (pin "D15") (pinfunction "15_D15") (pintype "bidirectional"))
    )
    (net (code "369") (name "unconnected-(J1D-16-PadD16)") (class "Default")
      (node (ref "J1") (pin "D16") (pinfunction "16_D16") (pintype "bidirectional"))
    )
    (net (code "370") (name "unconnected-(J1D-17-PadD17)") (class "Default")
      (node (ref "J1") (pin "D17") (pinfunction "17_D17") (pintype "bidirectional"))
    )
    (net (code "371") (name "unconnected-(J1D-18-PadD18)") (class "Default")
      (node (ref "J1") (pin "D18") (pinfunction "18_D18") (pintype "bidirectional"))
    )
    (net (code "372") (name "unconnected-(J1D-19-PadD19)") (class "Default")
      (node (ref "J1") (pin "D19") (pinfunction "19_D19") (pintype "bidirectional"))
    )
    (net (code "373") (name "unconnected-(J1D-20-PadD20)") (class "Default")
      (node (ref "J1") (pin "D20") (pinfunction "20_D20") (pintype "bidirectional"))
    )
    (net (code "374") (name "unconnected-(J1D-21-PadD21)") (class "Default")
      (node (ref "J1") (pin "D21") (pinfunction "21_D21") (pintype "bidirectional"))
    )
    (net (code "375") (name "unconnected-(J1D-22-PadD22)") (class "Default")
      (node (ref "J1") (pin "D22") (pinfunction "22_D22") (pintype "bidirectional"))
    )
    (net (code "376") (name "unconnected-(J1D-23-PadD23)") (class "Default")
      (node (ref "J1") (pin "D23") (pinfunction "23_D23") (pintype "bidirectional"))
    )
    (net (code "377") (name "unconnected-(J1D-24-PadD24)") (class "Default")
      (node (ref "J1") (pin "D24") (pinfunction "24_D24") (pintype "bidirectional"))
    )
    (net (code "378") (name "unconnected-(J1D-25-PadD25)") (class "Default")
      (node (ref "J1") (pin "D25") (pinfunction "25_D25") (pintype "bidirectional"))
    )
    (net (code "379") (name "unconnected-(J1D-26-PadD26)") (class "Default")
      (node (ref "J1") (pin "D26") (pinfunction "26_D26") (pintype "bidirectional"))
    )
    (net (code "380") (name "unconnected-(J1D-27-PadD27)") (class "Default")
      (node (ref "J1") (pin "D27") (pinfunction "27_D27") (pintype "bidirectional"))
    )
    (net (code "381") (name "unconnected-(J1D-28-PadD28)") (class "Default")
      (node (ref "J1") (pin "D28") (pinfunction "28_D28") (pintype "bidirectional"))
    )
    (net (code "382") (name "unconnected-(J1D-29-PadD29)") (class "Default")
      (node (ref "J1") (pin "D29") (pinfunction "29_D29") (pintype "bidirectional"))
    )
    (net (code "383") (name "unconnected-(J1D-30-PadD30)") (class "Default")
      (node (ref "J1") (pin "D30") (pinfunction "30_D30") (pintype "bidirectional"))
    )
    (net (code "384") (name "unconnected-(J1D-31-PadD31)") (class "Default")
      (node (ref "J1") (pin "D31") (pinfunction "31_D31") (pintype "bidirectional"))
    )
    (net (code "385") (name "unconnected-(J1D-32-PadD32)") (class "Default")
      (node (ref "J1") (pin "D32") (pinfunction "32_D32") (pintype "bidirectional"))
    )
    (net (code "386") (name "unconnected-(J1D-33-PadD33)") (class "Default")
      (node (ref "J1") (pin "D33") (pinfunction "33_D33") (pintype "bidirectional"))
    )
    (net (code "387") (name "unconnected-(J1D-34-PadD34)") (class "Default")
      (node (ref "J1") (pin "D34") (pinfunction "34_D34") (pintype "bidirectional"))
    )
    (net (code "388") (name "unconnected-(J1D-35-PadD35)") (class "Default")
      (node (ref "J1") (pin "D35") (pinfunction "35_D35") (pintype "bidirectional"))
    )
    (net (code "389") (name "unconnected-(J1D-36-PadD36)") (class "Default")
      (node (ref "J1") (pin "D36") (pinfunction "36_D36") (pintype "bidirectional"))
    )
    (net (code "390") (name "unconnected-(J1D-37-PadD37)") (class "Default")
      (node (ref "J1") (pin "D37") (pinfunction "37_D37") (pintype "bidirectional"))
    )
    (net (code "391") (name "unconnected-(J1D-38-PadD38)") (class "Default")
      (node (ref "J1") (pin "D38") (pinfunction "38_D38") (pintype "bidirectional"))
    )
    (net (code "392") (name "unconnected-(J1D-39-PadD39)") (class "Default")
      (node (ref "J1") (pin "D39") (pinfunction "39_D39") (pintype "bidirectional"))
    )
    (net (code "393") (name "unconnected-(J1D-40-PadD40)") (class "Default")
      (node (ref "J1") (pin "D40") (pinfunction "40_D40") (pintype "bidirectional"))
    )
    (net (code "394") (name "unconnected-(J1E-1-PadE1)") (class "Default")
      (node (ref "J1") (pin "E1") (pinfunction "1_E1") (pintype "bidirectional"))
    )
    (net (code "395") (name "unconnected-(J1E-2-PadE2)") (class "Default")
      (node (ref "J1") (pin "E2") (pinfunction "2_E2") (pintype "bidirectional"))
    )
    (net (code "396") (name "unconnected-(J1E-3-PadE3)") (class "Default")
      (node (ref "J1") (pin "E3") (pinfunction "3_E3") (pintype "bidirectional"))
    )
    (net (code "397") (name "unconnected-(J1E-4-PadE4)") (class "Default")
      (node (ref "J1") (pin "E4") (pinfunction "4_E4") (pintype "bidirectional"))
    )
    (net (code "398") (name "unconnected-(J1E-5-PadE5)") (class "Default")
      (node (ref "J1") (pin "E5") (pinfunction "5_E5") (pintype "bidirectional"))
    )
    (net (code "399") (name "unconnected-(J1E-6-PadE6)") (class "Default")
      (node (ref "J1") (pin "E6") (pinfunction "6_E6") (pintype "bidirectional"))
    )
    (net (code "400") (name "unconnected-(J1E-7-PadE7)") (class "Default")
      (node (ref "J1") (pin "E7") (pinfunction "7_E7") (pintype "bidirectional"))
    )
    (net (code "401") (name "unconnected-(J1E-8-PadE8)") (class "Default")
      (node (ref "J1") (pin "E8") (pinfunction "8_E8") (pintype "bidirectional"))
    )
    (net (code "402") (name "unconnected-(J1E-9-PadE9)") (class "Default")
      (node (ref "J1") (pin "E9") (pinfunction "9_E9") (pintype "bidirectional"))
    )
    (net (code "403") (name "unconnected-(J1E-10-PadE10)") (class "Default")
      (node (ref "J1") (pin "E10") (pinfunction "10_E10") (pintype "bidirectional"))
    )
    (net (code "404") (name "unconnected-(J1E-11-PadE11)") (class "Default")
      (node (ref "J1") (pin "E11") (pinfunction "11_E11") (pintype "bidirectional"))
    )
    (net (code "405") (name "unconnected-(J1E-12-PadE12)") (class "Default")
      (node (ref "J1") (pin "E12") (pinfunction "12_E12") (pintype "bidirectional"))
    )
    (net (code "406") (name "unconnected-(J1E-13-PadE13)") (class "Default")
      (node (ref "J1") (pin "E13") (pinfunction "13_E13") (pintype "bidirectional"))
    )
    (net (code "407") (name "unconnected-(J1E-14-PadE14)") (class "Default")
      (node (ref "J1") (pin "E14") (pinfunction "14_E14") (pintype "bidirectional"))
    )
    (net (code "408") (name "unconnected-(J1E-15-PadE15)") (class "Default")
      (node (ref "J1") (pin "E15") (pinfunction "15_E15") (pintype "bidirectional"))
    )
    (net (code "409") (name "unconnected-(J1E-16-PadE16)") (class "Default")
      (node (ref "J1") (pin "E16") (pinfunction "16_E16") (pintype "bidirectional"))
    )
    (net (code "410") (name "unconnected-(J1E-17-PadE17)") (class "Default")
      (node (ref "J1") (pin "E17") (pinfunction "17_E17") (pintype "bidirectional"))
    )
    (net (code "411") (name "unconnected-(J1E-18-PadE18)") (class "Default")
      (node (ref "J1") (pin "E18") (pinfunction "18_E18") (pintype "bidirectional"))
    )
    (net (code "412") (name "unconnected-(J1E-19-PadE19)") (class "Default")
      (node (ref "J1") (pin "E19") (pinfunction "19_E19") (pintype "bidirectional"))
    )
    (net (code "413") (name "unconnected-(J1E-20-PadE20)") (class "Default")
      (node (ref "J1") (pin "E20") (pinfunction "20_E20") (pintype "bidirectional"))
    )
    (net (code "414") (name "unconnected-(J1E-21-PadE21)") (class "Default")
      (node (ref "J1") (pin "E21") (pinfunction "21_E21") (pintype "bidirectional"))
    )
    (net (code "415") (name "unconnected-(J1E-22-PadE22)") (class "Default")
      (node (ref "J1") (pin "E22") (pinfunction "22_E22") (pintype "bidirectional"))
    )
    (net (code "416") (name "unconnected-(J1E-23-PadE23)") (class "Default")
      (node (ref "J1") (pin "E23") (pinfunction "23_E23") (pintype "bidirectional"))
    )
    (net (code "417") (name "unconnected-(J1E-24-PadE24)") (class "Default")
      (node (ref "J1") (pin "E24") (pinfunction "24_E24") (pintype "bidirectional"))
    )
    (net (code "418") (name "unconnected-(J1E-25-PadE25)") (class "Default")
      (node (ref "J1") (pin "E25") (pinfunction "25_E25") (pintype "bidirectional"))
    )
    (net (code "419") (name "unconnected-(J1E-26-PadE26)") (class "Default")
      (node (ref "J1") (pin "E26") (pinfunction "26_E26") (pintype "bidirectional"))
    )
    (net (code "420") (name "unconnected-(J1E-27-PadE27)") (class "Default")
      (node (ref "J1") (pin "E27") (pinfunction "27_E27") (pintype "bidirectional"))
    )
    (net (code "421") (name "unconnected-(J1E-28-PadE28)") (class "Default")
      (node (ref "J1") (pin "E28") (pinfunction "28_E28") (pintype "bidirectional"))
    )
    (net (code "422") (name "unconnected-(J1E-29-PadE29)") (class "Default")
      (node (ref "J1") (pin "E29") (pinfunction "29_E29") (pintype "bidirectional"))
    )
    (net (code "423") (name "unconnected-(J1E-30-PadE30)") (class "Default")
      (node (ref "J1") (pin "E30") (pinfunction "30_E30") (pintype "bidirectional"))
    )
    (net (code "424") (name "unconnected-(J1E-31-PadE31)") (class "Default")
      (node (ref "J1") (pin "E31") (pinfunction "31_E31") (pintype "bidirectional"))
    )
    (net (code "425") (name "unconnected-(J1E-32-PadE32)") (class "Default")
      (node (ref "J1") (pin "E32") (pinfunction "32_E32") (pintype "bidirectional"))
    )
    (net (code "426") (name "unconnected-(J1E-33-PadE33)") (class "Default")
      (node (ref "J1") (pin "E33") (pinfunction "33_E33") (pintype "bidirectional"))
    )
    (net (code "427") (name "unconnected-(J1E-34-PadE34)") (class "Default")
      (node (ref "J1") (pin "E34") (pinfunction "34_E34") (pintype "bidirectional"))
    )
    (net (code "428") (name "unconnected-(J1E-35-PadE35)") (class "Default")
      (node (ref "J1") (pin "E35") (pinfunction "35_E35") (pintype "bidirectional"))
    )
    (net (code "429") (name "unconnected-(J1E-36-PadE36)") (class "Default")
      (node (ref "J1") (pin "E36") (pinfunction "36_E36") (pintype "bidirectional"))
    )
    (net (code "430") (name "unconnected-(J1E-37-PadE37)") (class "Default")
      (node (ref "J1") (pin "E37") (pinfunction "37_E37") (pintype "bidirectional"))
    )
    (net (code "431") (name "unconnected-(J1E-38-PadE38)") (class "Default")
      (node (ref "J1") (pin "E38") (pinfunction "38_E38") (pintype "bidirectional"))
    )
    (net (code "432") (name "unconnected-(J1E-39-PadE39)") (class "Default")
      (node (ref "J1") (pin "E39") (pinfunction "39_E39") (pintype "bidirectional"))
    )
    (net (code "433") (name "unconnected-(J1E-40-PadE40)") (class "Default")
      (node (ref "J1") (pin "E40") (pinfunction "40_E40") (pintype "bidirectional"))
    )
    (net (code "434") (name "unconnected-(J1F-1-PadF1)") (class "Default")
      (node (ref "J1") (pin "F1") (pinfunction "1_F1") (pintype "bidirectional"))
    )
    (net (code "435") (name "unconnected-(J1F-2-PadF2)") (class "Default")
      (node (ref "J1") (pin "F2") (pinfunction "2_F2") (pintype "bidirectional"))
    )
    (net (code "436") (name "unconnected-(J1F-3-PadF3)") (class "Default")
      (node (ref "J1") (pin "F3") (pinfunction "3_F3") (pintype "bidirectional"))
    )
    (net (code "437") (name "unconnected-(J1F-4-PadF4)") (class "Default")
      (node (ref "J1") (pin "F4") (pinfunction "4_F4") (pintype "bidirectional"))
    )
    (net (code "438") (name "unconnected-(J1F-5-PadF5)") (class "Default")
      (node (ref "J1") (pin "F5") (pinfunction "5_F5") (pintype "bidirectional"))
    )
    (net (code "439") (name "unconnected-(J1F-6-PadF6)") (class "Default")
      (node (ref "J1") (pin "F6") (pinfunction "6_F6") (pintype "bidirectional"))
    )
    (net (code "440") (name "unconnected-(J1F-7-PadF7)") (class "Default")
      (node (ref "J1") (pin "F7") (pinfunction "7_F7") (pintype "bidirectional"))
    )
    (net (code "441") (name "unconnected-(J1F-8-PadF8)") (class "Default")
      (node (ref "J1") (pin "F8") (pinfunction "8_F8") (pintype "bidirectional"))
    )
    (net (code "442") (name "unconnected-(J1F-9-PadF9)") (class "Default")
      (node (ref "J1") (pin "F9") (pinfunction "9_F9") (pintype "bidirectional"))
    )
    (net (code "443") (name "unconnected-(J1F-10-PadF10)") (class "Default")
      (node (ref "J1") (pin "F10") (pinfunction "10_F10") (pintype "bidirectional"))
    )
    (net (code "444") (name "unconnected-(J1F-11-PadF11)") (class "Default")
      (node (ref "J1") (pin "F11") (pinfunction "11_F11") (pintype "bidirectional"))
    )
    (net (code "445") (name "unconnected-(J1F-12-PadF12)") (class "Default")
      (node (ref "J1") (pin "F12") (pinfunction "12_F12") (pintype "bidirectional"))
    )
    (net (code "446") (name "unconnected-(J1F-13-PadF13)") (class "Default")
      (node (ref "J1") (pin "F13") (pinfunction "13_F13") (pintype "bidirectional"))
    )
    (net (code "447") (name "unconnected-(J1F-14-PadF14)") (class "Default")
      (node (ref "J1") (pin "F14") (pinfunction "14_F14") (pintype "bidirectional"))
    )
    (net (code "448") (name "unconnected-(J1F-15-PadF15)") (class "Default")
      (node (ref "J1") (pin "F15") (pinfunction "15_F15") (pintype "bidirectional"))
    )
    (net (code "449") (name "unconnected-(J1F-16-PadF16)") (class "Default")
      (node (ref "J1") (pin "F16") (pinfunction "16_F16") (pintype "bidirectional"))
    )
    (net (code "450") (name "unconnected-(J1F-17-PadF17)") (class "Default")
      (node (ref "J1") (pin "F17") (pinfunction "17_F17") (pintype "bidirectional"))
    )
    (net (code "451") (name "unconnected-(J1F-18-PadF18)") (class "Default")
      (node (ref "J1") (pin "F18") (pinfunction "18_F18") (pintype "bidirectional"))
    )
    (net (code "452") (name "unconnected-(J1F-19-PadF19)") (class "Default")
      (node (ref "J1") (pin "F19") (pinfunction "19_F19") (pintype "bidirectional"))
    )
    (net (code "453") (name "unconnected-(J1F-20-PadF20)") (class "Default")
      (node (ref "J1") (pin "F20") (pinfunction "20_F20") (pintype "bidirectional"))
    )
    (net (code "454") (name "unconnected-(J1F-21-PadF21)") (class "Default")
      (node (ref "J1") (pin "F21") (pinfunction "21_F21") (pintype "bidirectional"))
    )
    (net (code "455") (name "unconnected-(J1F-22-PadF22)") (class "Default")
      (node (ref "J1") (pin "F22") (pinfunction "22_F22") (pintype "bidirectional"))
    )
    (net (code "456") (name "unconnected-(J1F-23-PadF23)") (class "Default")
      (node (ref "J1") (pin "F23") (pinfunction "23_F23") (pintype "bidirectional"))
    )
    (net (code "457") (name "unconnected-(J1F-24-PadF24)") (class "Default")
      (node (ref "J1") (pin "F24") (pinfunction "24_F24") (pintype "bidirectional"))
    )
    (net (code "458") (name "unconnected-(J1F-25-PadF25)") (class "Default")
      (node (ref "J1") (pin "F25") (pinfunction "25_F25") (pintype "bidirectional"))
    )
    (net (code "459") (name "unconnected-(J1F-26-PadF26)") (class "Default")
      (node (ref "J1") (pin "F26") (pinfunction "26_F26") (pintype "bidirectional"))
    )
    (net (code "460") (name "unconnected-(J1F-27-PadF27)") (class "Default")
      (node (ref "J1") (pin "F27") (pinfunction "27_F27") (pintype "bidirectional"))
    )
    (net (code "461") (name "unconnected-(J1F-28-PadF28)") (class "Default")
      (node (ref "J1") (pin "F28") (pinfunction "28_F28") (pintype "bidirectional"))
    )
    (net (code "462") (name "unconnected-(J1F-29-PadF29)") (class "Default")
      (node (ref "J1") (pin "F29") (pinfunction "29_F29") (pintype "bidirectional"))
    )
    (net (code "463") (name "unconnected-(J1F-30-PadF30)") (class "Default")
      (node (ref "J1") (pin "F30") (pinfunction "30_F30") (pintype "bidirectional"))
    )
    (net (code "464") (name "unconnected-(J1F-31-PadF31)") (class "Default")
      (node (ref "J1") (pin "F31") (pinfunction "31_F31") (pintype "bidirectional"))
    )
    (net (code "465") (name "unconnected-(J1F-32-PadF32)") (class "Default")
      (node (ref "J1") (pin "F32") (pinfunction "32_F32") (pintype "bidirectional"))
    )
    (net (code "466") (name "unconnected-(J1F-33-PadF33)") (class "Default")
      (node (ref "J1") (pin "F33") (pinfunction "33_F33") (pintype "bidirectional"))
    )
    (net (code "467") (name "unconnected-(J1F-34-PadF34)") (class "Default")
      (node (ref "J1") (pin "F34") (pinfunction "34_F34") (pintype "bidirectional"))
    )
    (net (code "468") (name "unconnected-(J1F-35-PadF35)") (class "Default")
      (node (ref "J1") (pin "F35") (pinfunction "35_F35") (pintype "bidirectional"))
    )
    (net (code "469") (name "unconnected-(J1F-36-PadF36)") (class "Default")
      (node (ref "J1") (pin "F36") (pinfunction "36_F36") (pintype "bidirectional"))
    )
    (net (code "470") (name "unconnected-(J1F-37-PadF37)") (class "Default")
      (node (ref "J1") (pin "F37") (pinfunction "37_F37") (pintype "bidirectional"))
    )
    (net (code "471") (name "unconnected-(J1F-38-PadF38)") (class "Default")
      (node (ref "J1") (pin "F38") (pinfunction "38_F38") (pintype "bidirectional"))
    )
    (net (code "472") (name "unconnected-(J1F-39-PadF39)") (class "Default")
      (node (ref "J1") (pin "F39") (pinfunction "39_F39") (pintype "bidirectional"))
    )
    (net (code "473") (name "unconnected-(J1F-40-PadF40)") (class "Default")
      (node (ref "J1") (pin "F40") (pinfunction "40_F40") (pintype "bidirectional"))
    )
    (net (code "474") (name "unconnected-(JP1-Pad6)") (class "Default")
      (node (ref "JP1") (pin "6") (pinfunction "6_6") (pintype "passive"))
    )
    (net (code "475") (name "unconnected-(JP1-Pad17)") (class "Default")
      (node (ref "JP1") (pin "17") (pinfunction "17_17") (pintype "passive"))
    )
    (net (code "476") (name "unconnected-(JP1-Pad18)") (class "Default")
      (node (ref "JP1") (pin "18") (pinfunction "18_18") (pintype "passive"))
    )
    (net (code "477") (name "unconnected-(JP1-Pad19)") (class "Default")
      (node (ref "JP1") (pin "19") (pinfunction "19_19") (pintype "passive"))
    )
    (net (code "478") (name "unconnected-(U$10-DS-PadH5)") (class "Default")
      (node (ref "U$10") (pin "H5") (pinfunction "DS_H5") (pintype "bidirectional"))
    )
    (net (code "479") (name "unconnected-(U$11-DS-PadH5)") (class "Default")
      (node (ref "U$11") (pin "H5") (pinfunction "DS_H5") (pintype "bidirectional"))
    )
    (net (code "480") (name "unconnected-(U$12-EXTCLK-Pad25)") (class "Default")
      (node (ref "U$12") (pin "25") (pinfunction "EXTCLK_25") (pintype "bidirectional"))
    )
    (net (code "481") (name "unconnected-(U1A-PMIC_POWER_EN-PadC6)") (class "Default")
      (node (ref "U1") (pin "C6") (pinfunction "PMIC_POWER_EN_C6") (pintype "passive"))
    )
    (net (code "482") (name "unconnected-(U1A-RESERVED-PadA3)") (class "Default")
      (node (ref "U1") (pin "A3") (pinfunction "RESERVED_A3") (pintype "passive"))
    )
    (net (code "483") (name "unconnected-(U1D-USB0_CE-PadM15)") (class "Default")
      (node (ref "U1") (pin "M15") (pinfunction "USB0_CE_M15") (pintype "passive"))
    )
    (net (code "484") (name "unconnected-(U1D-USB1_CE-PadP18)") (class "Default")
      (node (ref "U1") (pin "P18") (pinfunction "USB1_CE_P18") (pintype "passive"))
    )
    (net (code "485") (name "unconnected-(U2-ID-Pad3)") (class "Default")
      (node (ref "U2") (pin "3") (pinfunction "ID_3") (pintype "passive"))
    )
    (net (code "486") (name "unconnected-(U2-N.C.-Pad5)") (class "Default")
      (node (ref "U2") (pin "5") (pinfunction "N.C._5") (pintype "no_connect"))
    )
    (net (code "487") (name "unconnected-(U10-ID-Pad3)") (class "Default")
      (node (ref "U10") (pin "3") (pinfunction "ID_3") (pintype "passive"))
    )
    (net (code "488") (name "unconnected-(U10-N.C.-Pad5)") (class "Default")
      (node (ref "U10") (pin "5") (pinfunction "N.C._5") (pintype "no_connect"))
    )
    (net (code "489") (name "unconnected-(U11-NC-Pad2)") (class "Default")
      (node (ref "U11") (pin "2") (pinfunction "NC_2") (pintype "passive"))
    )
    (net (code "490") (name "unconnected-(U12-P13-Pad13)") (class "Default")
      (node (ref "U12") (pin "13") (pinfunction "P13_13") (pintype "bidirectional"))
    )
    (net (code "491") (name "unconnected-(U12-P14-Pad14)") (class "Default")
      (node (ref "U12") (pin "14") (pinfunction "P14_14") (pintype "bidirectional"))
    )
    (net (code "492") (name "unconnected-(U12-P15-Pad15)") (class "Default")
      (node (ref "U12") (pin "15") (pinfunction "P15_15") (pintype "bidirectional"))
    )
    (net (code "493") (name "unconnected-(U12-P16-Pad16)") (class "Default")
      (node (ref "U12") (pin "16") (pinfunction "P16_16") (pintype "bidirectional"))
    )
    (net (code "494") (name "unconnected-(U13-NC-Pad1)") (class "Default")
      (node (ref "U13") (pin "1") (pinfunction "NC_1") (pintype "passive"))
    )
    (net (code "495") (name "unconnected-(U14-NC-Pad15)") (class "Default")
      (node (ref "U14") (pin "15") (pinfunction "NC_15") (pintype "passive"))
    )
    (net (code "496") (name "unconnected-(U14-NC_2-Pad13)") (class "Default")
      (node (ref "U14") (pin "13") (pinfunction "NC_2_13") (pintype "passive"))
    )
    (net (code "497") (name "unconnected-(U17-NC-Pad49)") (class "Default")
      (node (ref "U17") (pin "49") (pinfunction "NC_49") (pintype "passive"))
    )
    (net (code "498") (name "unconnected-(U18-IO1-Pad1)") (class "Default")
      (node (ref "U18") (pin "1") (pinfunction "IO1_1") (pintype "passive"))
    )
    (net (code "499") (name "unconnected-(U18-IO2-Pad2)") (class "Default")
      (node (ref "U18") (pin "2") (pinfunction "IO2_2") (pintype "passive"))
    )
    (net (code "500") (name "unconnected-(U34-SYN_OUT-Pad39)") (class "Default")
      (node (ref "U34") (pin "39") (pinfunction "SYN_OUT_39") (pintype "output"))
    )
    (net (code "501") (name "unconnected-(U40-NC-Pad2)") (class "Default")
      (node (ref "U40") (pin "2") (pinfunction "NC_2") (pintype "passive"))
    )
    (net (code "502") (name "unconnected-(X1-NC{slash}4-Pad4)") (class "Default")
      (node (ref "X1") (pin "4") (pinfunction "NC/4_4") (pintype "input"))
    )
    (net (code "503") (name "unconnected-(X1-NC{slash}5-Pad5)") (class "Default")
      (node (ref "X1") (pin "5") (pinfunction "NC/5_5") (pintype "input"))
    )
    (net (code "504") (name "~{DDR3_CAS}") (class "Default")
      (node (ref "R31") (pin "2") (pinfunction "2_2") (pintype "bidirectional"))
      (node (ref "U1") (pin "F1") (pinfunction "DDR_CASN_F1") (pintype "passive"))
      (node (ref "U9") (pin "K3") (pinfunction "~{CAS}_K3") (pintype "bidirectional"))
    )
    (net (code "505") (name "~{DDR3_CS}") (class "Default")
      (node (ref "R28") (pin "2") (pinfunction "2_2") (pintype "bidirectional"))
      (node (ref "U1") (pin "H2") (pinfunction "DDR_CSN0_H2") (pintype "passive"))
      (node (ref "U9") (pin "L2") (pinfunction "~{CS}_L2") (pintype "bidirectional"))
    )
    (net (code "506") (name "~{DDR3_RAS}") (class "Default")
      (node (ref "R30") (pin "2") (pinfunction "2_2") (pintype "bidirectional"))
      (node (ref "U1") (pin "G4") (pinfunction "DDR_RASN_G4") (pintype "passive"))
      (node (ref "U9") (pin "J3") (pinfunction "~{RAS}_J3") (pintype "bidirectional"))
    )
    (net (code "507") (name "~{DDR3_RESET}") (class "Default")
      (node (ref "U1") (pin "G2") (pinfunction "DDR_RESETN_G2") (pintype "passive"))
      (node (ref "U9") (pin "T2") (pinfunction "~{RESET}_T2") (pintype "bidirectional"))
    )
    (net (code "508") (name "~{DDR3_WE}") (class "Default")
      (node (ref "R32") (pin "2") (pinfunction "2_2") (pintype "bidirectional"))
      (node (ref "U1") (pin "B2") (pinfunction "DDR_WEN_B2") (pintype "passive"))
      (node (ref "U9") (pin "L3") (pinfunction "~{WE}_L3") (pintype "bidirectional"))
    )
    (net (code "509") (name "~{ETH_INT}") (class "Default")
      (node (ref "R90") (pin "2") (pinfunction "2_2") (pintype "bidirectional"))
      (node (ref "U12") (pin "2") (pinfunction "P01_2") (pintype "bidirectional"))
      (node (ref "U14") (pin "8") (pinfunction "INT_PWDN_N_8") (pintype "bidirectional"))
    )
    (net (code "510") (name "~{ETH_RESET}") (class "Default")
      (node (ref "R91") (pin "2") (pinfunction "2_2") (pintype "bidirectional"))
      (node (ref "U12") (pin "3") (pinfunction "P02_3") (pintype "bidirectional"))
      (node (ref "U14") (pin "18") (pinfunction "RESET_N_18") (pintype "input"))
    )
    (net (code "511") (name "~{JTAG_SRST}") (class "Default")
      (node (ref "JP1") (pin "15") (pinfunction "15_15") (pintype "passive"))
    )
    (net (code "512") (name "~{JTAG_TRST}") (class "Default")
      (node (ref "JP1") (pin "2") (pinfunction "2_2") (pintype "passive"))
      (node (ref "R57") (pin "1") (pinfunction "1_1") (pintype "bidirectional"))
      (node (ref "U1") (pin "B10") (pinfunction "TRSTN_B10") (pintype "passive"))
      (node (ref "U78") (pin "6") (pinfunction "C_6") (pintype "input"))
    )
    (net (code "513") (name "~{MGMT_INT0}") (class "Default")
      (node (ref "J1") (pin "B26") (pinfunction "26_B26") (pintype "bidirectional"))
      (node (ref "R94") (pin "2") (pinfunction "2_2") (pintype "bidirectional"))
      (node (ref "U12") (pin "7") (pinfunction "P06_7") (pintype "bidirectional"))
    )
    (net (code "514") (name "~{MGMT_INT1}") (class "Default")
      (node (ref "J1") (pin "B25") (pinfunction "25_B25") (pintype "bidirectional"))
      (node (ref "R95") (pin "2") (pinfunction "2_2") (pintype "bidirectional"))
      (node (ref "U12") (pin "8") (pinfunction "P07_8") (pintype "bidirectional"))
    )
    (net (code "515") (name "~{MMC1_RESET}") (class "Default")
      (node (ref "R97") (pin "2") (pinfunction "2_2") (pintype "bidirectional"))
      (node (ref "U$10") (pin "K5") (pinfunction "RST_N_K5") (pintype "bidirectional"))
      (node (ref "U12") (pin "12") (pinfunction "P12_12") (pintype "bidirectional"))
    )
    (net (code "516") (name "~{MMC2_RESET}") (class "Default")
      (node (ref "R96") (pin "2") (pinfunction "2_2") (pintype "bidirectional"))
      (node (ref "U$11") (pin "K5") (pinfunction "RST_N_K5") (pintype "bidirectional"))
      (node (ref "U12") (pin "11") (pinfunction "P11_11") (pintype "bidirectional"))
    )
    (net (code "517") (name "~{NMI}") (class "Default")
      (node (ref "R55") (pin "1") (pinfunction "1_1") (pintype "bidirectional"))
      (node (ref "U1") (pin "B18") (pinfunction "EXTINTN_B18") (pintype "passive"))
      (node (ref "U12") (pin "22") (pinfunction "*INT_22") (pintype "output"))
    )
    (net (code "518") (name "~{PWM_OE}") (class "Default")
      (node (ref "R98") (pin "2") (pinfunction "2_2") (pintype "bidirectional"))
      (node (ref "U$12") (pin "23") (pinfunction "~{OE}_23") (pintype "bidirectional"))
    )
    (net (code "519") (name "~{SUPERVISOR_MASTER_RESET}") (class "Default")
      (node (ref "J1") (pin "B19") (pinfunction "19_B19") (pintype "bidirectional"))
      (node (ref "R72") (pin "1") (pinfunction "1_1") (pintype "bidirectional"))
      (node (ref "U77") (pin "1") (pinfunction "ENABLE_1") (pintype "passive"))
    )
    (net (code "520") (name "~{UART1_CTS}") (class "Default")
      (node (ref "J1") (pin "C26") (pinfunction "26_C26") (pintype "bidirectional"))
      (node (ref "U1") (pin "D18") (pinfunction "UART1_CTSN_D18") (pintype "passive"))
    )
    (net (code "521") (name "~{UART1_RTS}") (class "Default")
      (node (ref "J1") (pin "C25") (pinfunction "25_C25") (pintype "bidirectional"))
      (node (ref "U1") (pin "D17") (pinfunction "UART1_RTSN_D17") (pintype "passive"))
    )
    (net (code "522") (name "~{USB0_OVERCURRENT}") (class "Default")
      (node (ref "R76") (pin "2") (pinfunction "2_2") (pintype "bidirectional"))
      (node (ref "U12") (pin "4") (pinfunction "P03_4") (pintype "bidirectional"))
      (node (ref "U16") (pin "5") (pinfunction "*OC_5") (pintype "output"))
    )
    (net (code "523") (name "~{USB1_OVERCURRENT}") (class "Default")
      (node (ref "R74") (pin "2") (pinfunction "2_2") (pintype "bidirectional"))
      (node (ref "U12") (pin "5") (pinfunction "P04_5") (pintype "bidirectional"))
      (node (ref "U15") (pin "5") (pinfunction "*OC_5") (pintype "output"))
    )
    (net (code "524") (name "~{WARM_RESET}") (class "Default")
      (node (ref "J1") (pin "C6") (pinfunction "6_C6") (pintype "bidirectional"))
      (node (ref "R88") (pin "1") (pinfunction "1_1") (pintype "bidirectional"))
      (node (ref "R89") (pin "2") (pinfunction "2_2") (pintype "bidirectional"))
      (node (ref "U1") (pin "A10") (pinfunction "WARMRSTN_A10") (pintype "passive"))
    )
  )
)
